# debug_backplane.net
KiCad netlist of a schematic drawn in EAGLE
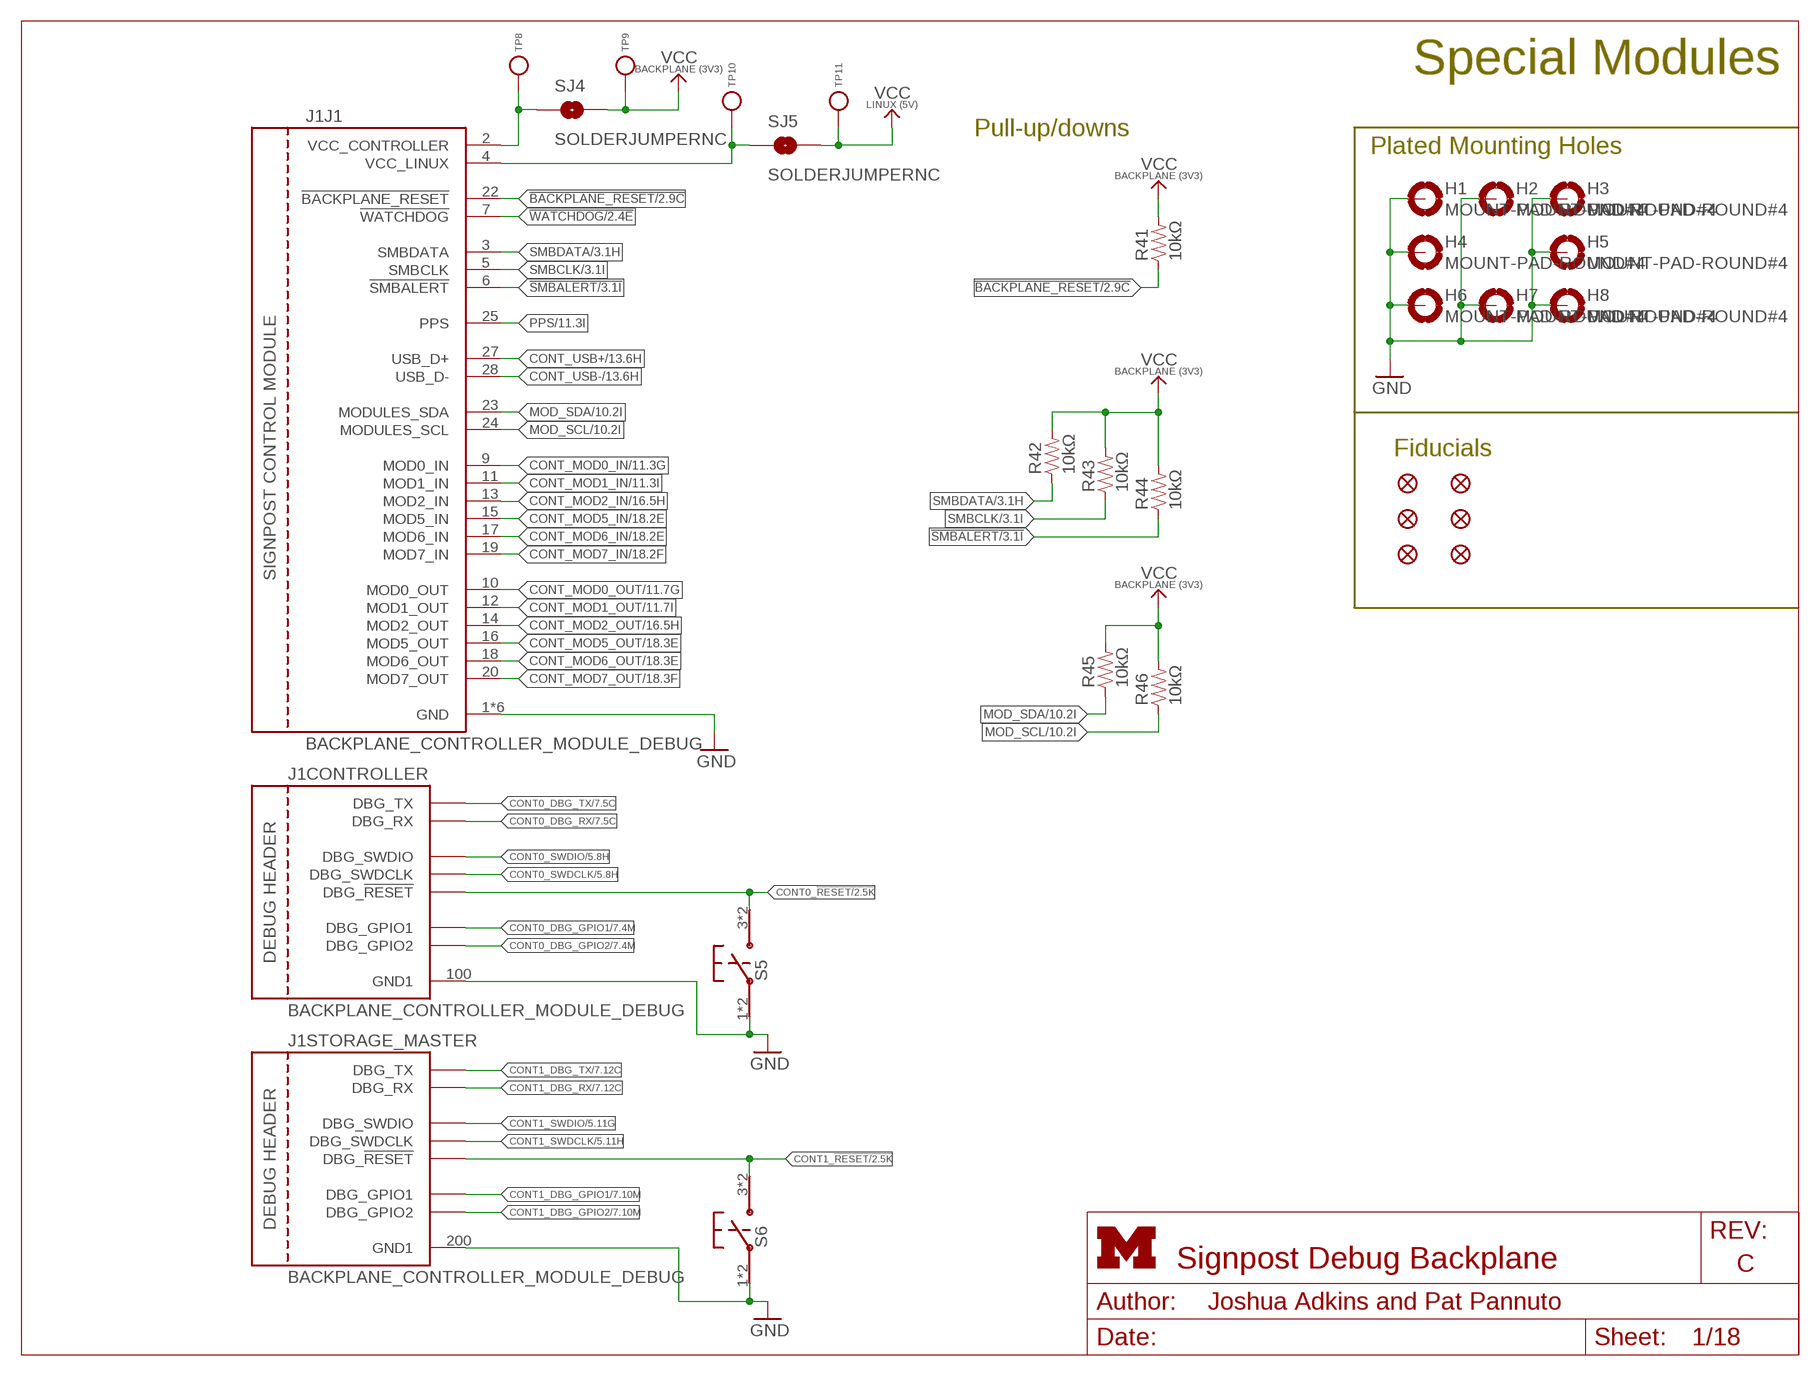
[diagram p0: schematic, sheet 1]
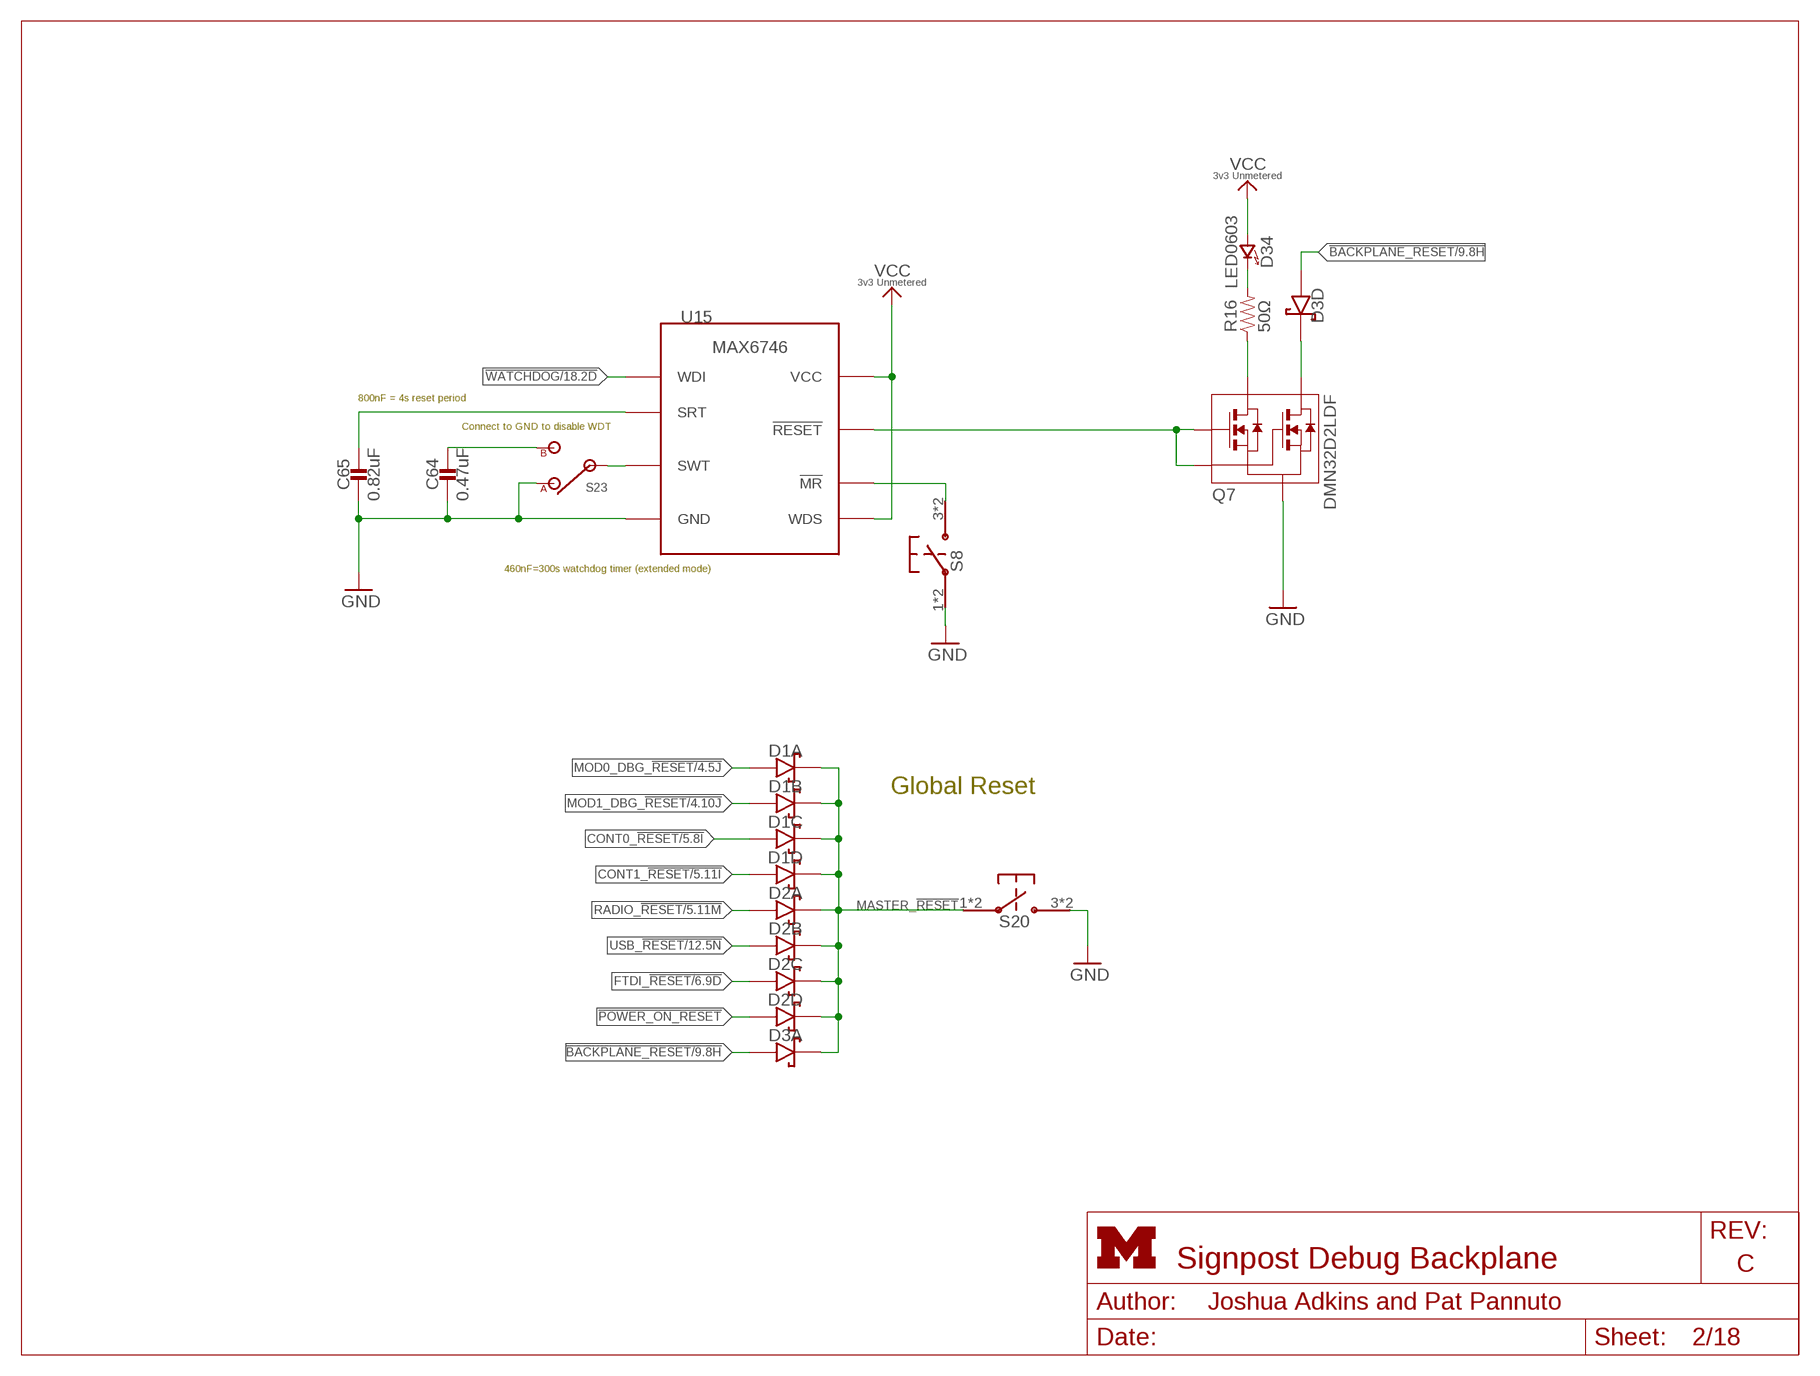
[diagram p1: schematic, sheet 2]
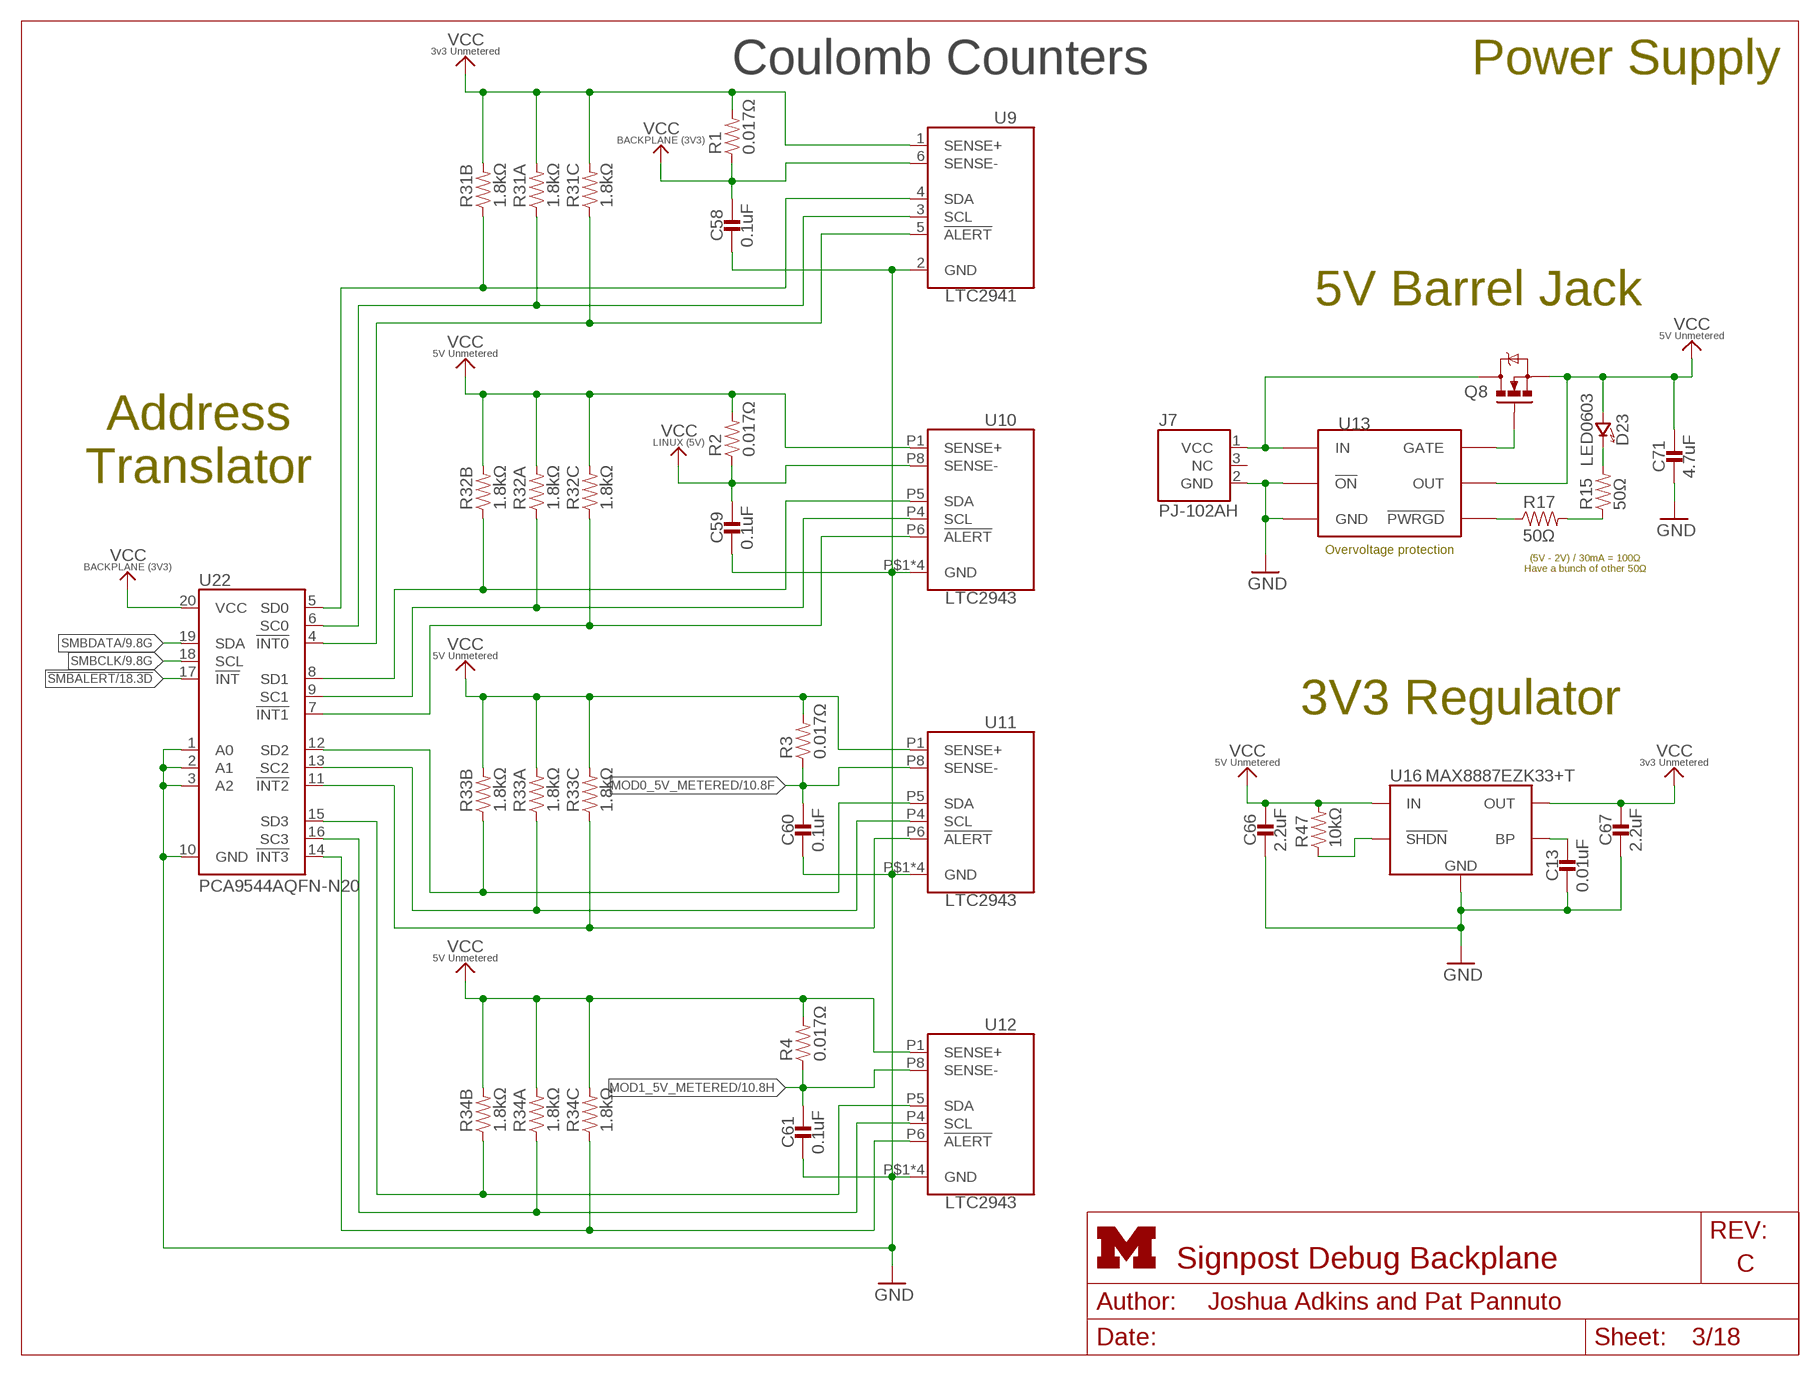
[diagram p2: schematic, sheet 3]
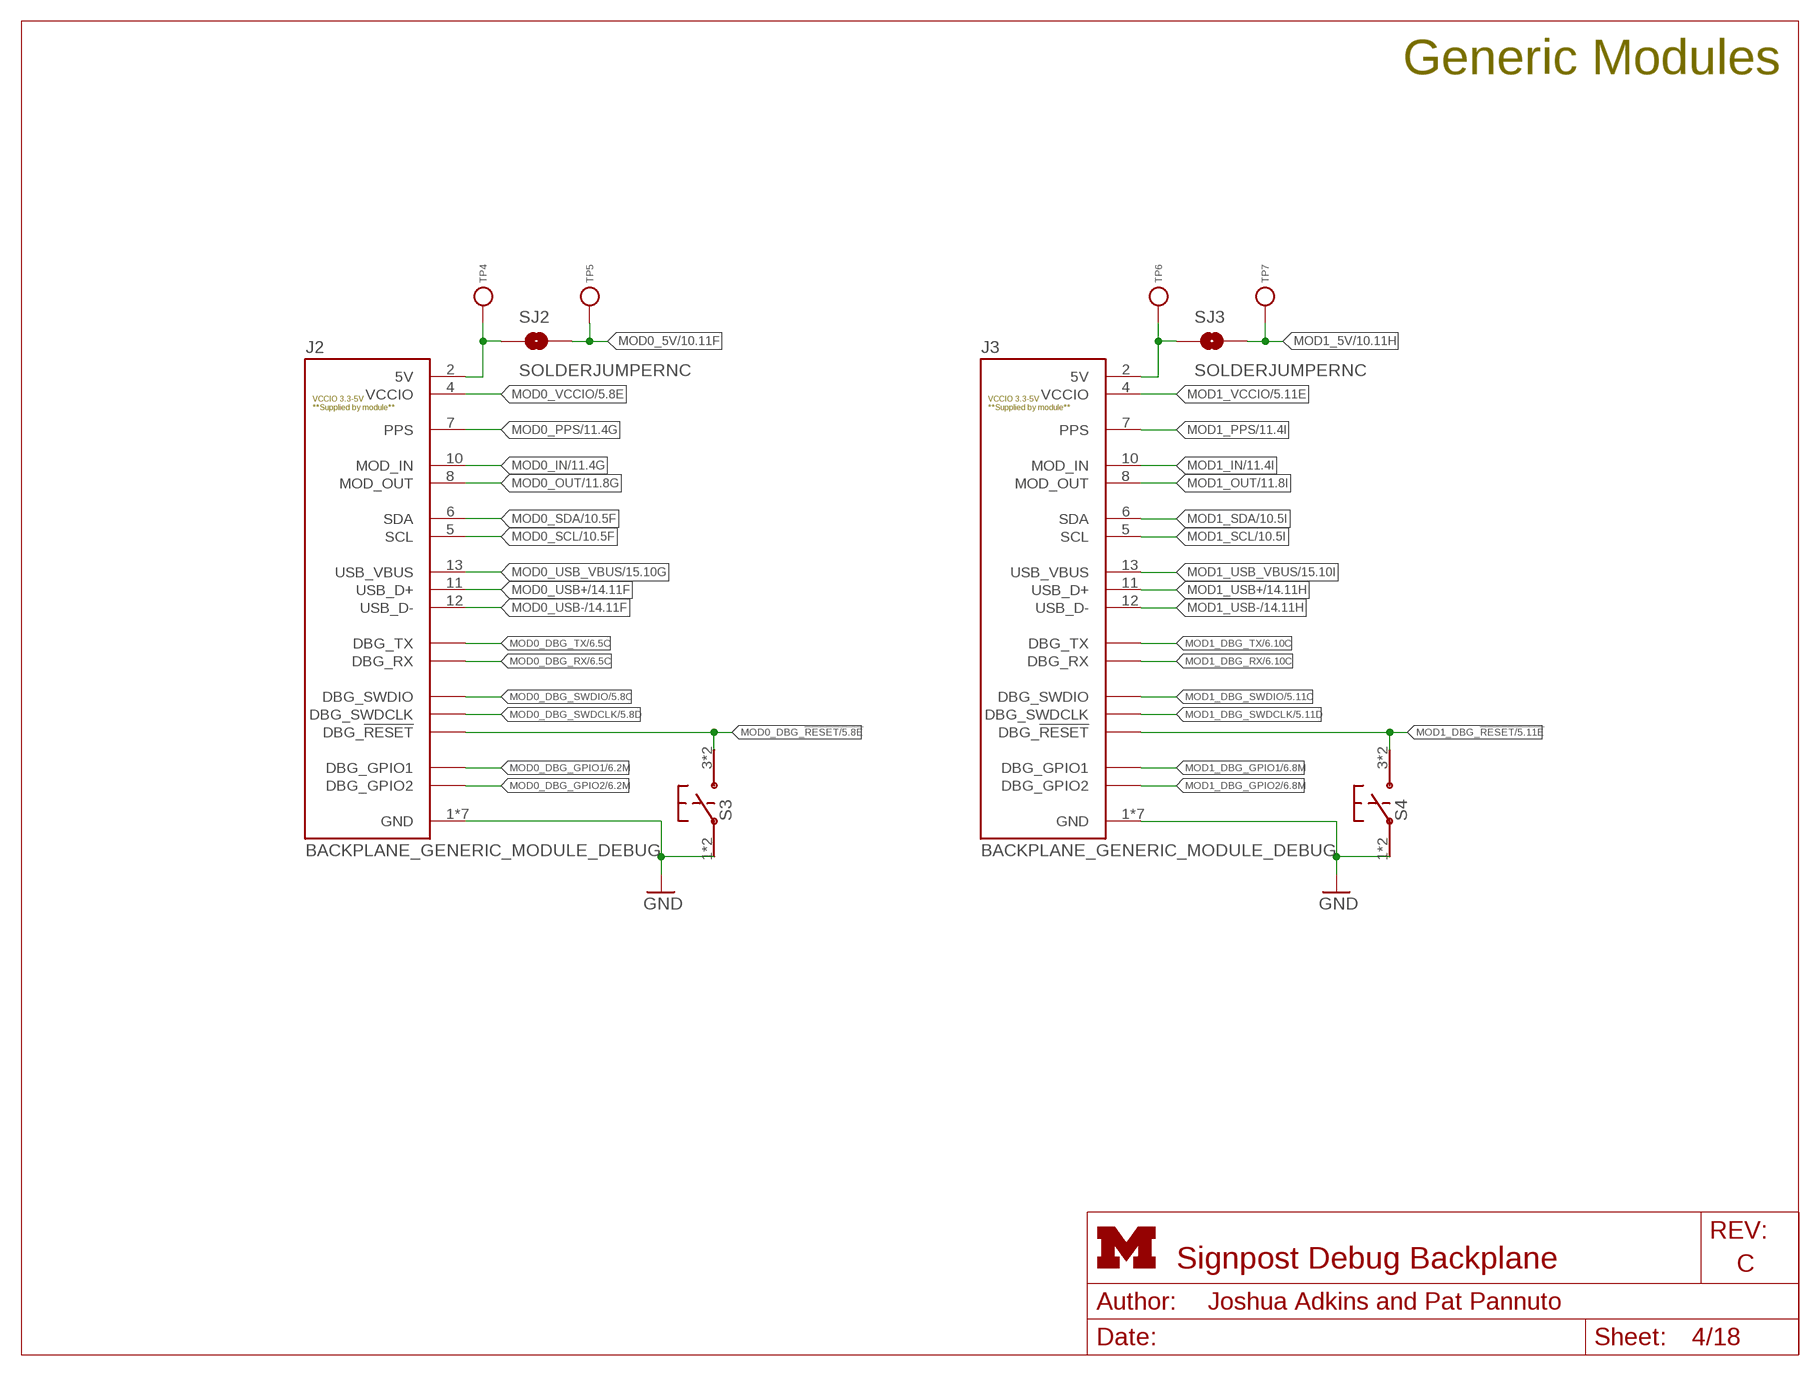
[diagram p3: schematic, sheet 4]
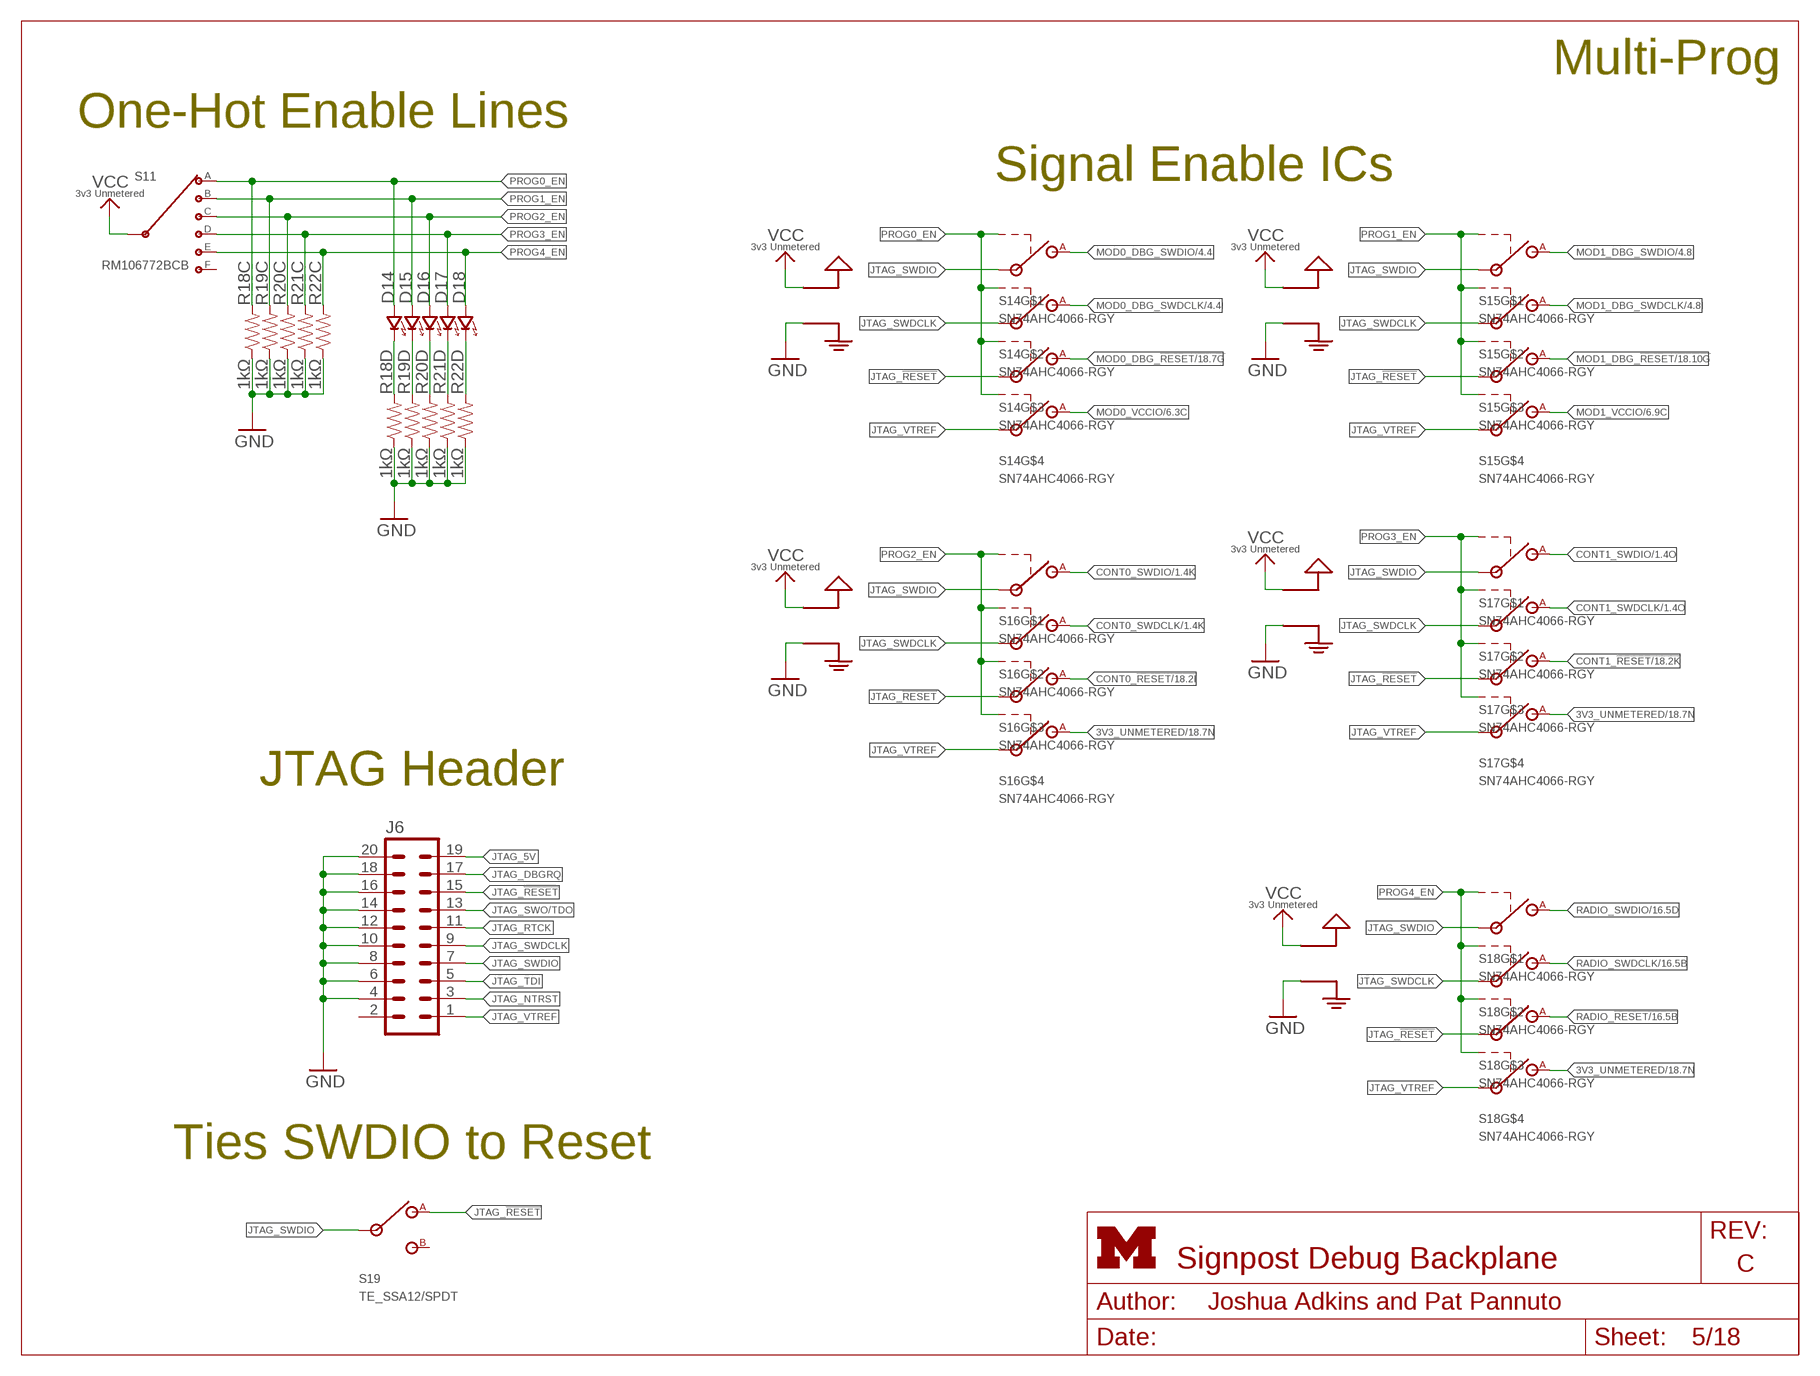
[diagram p4: schematic, sheet 5]
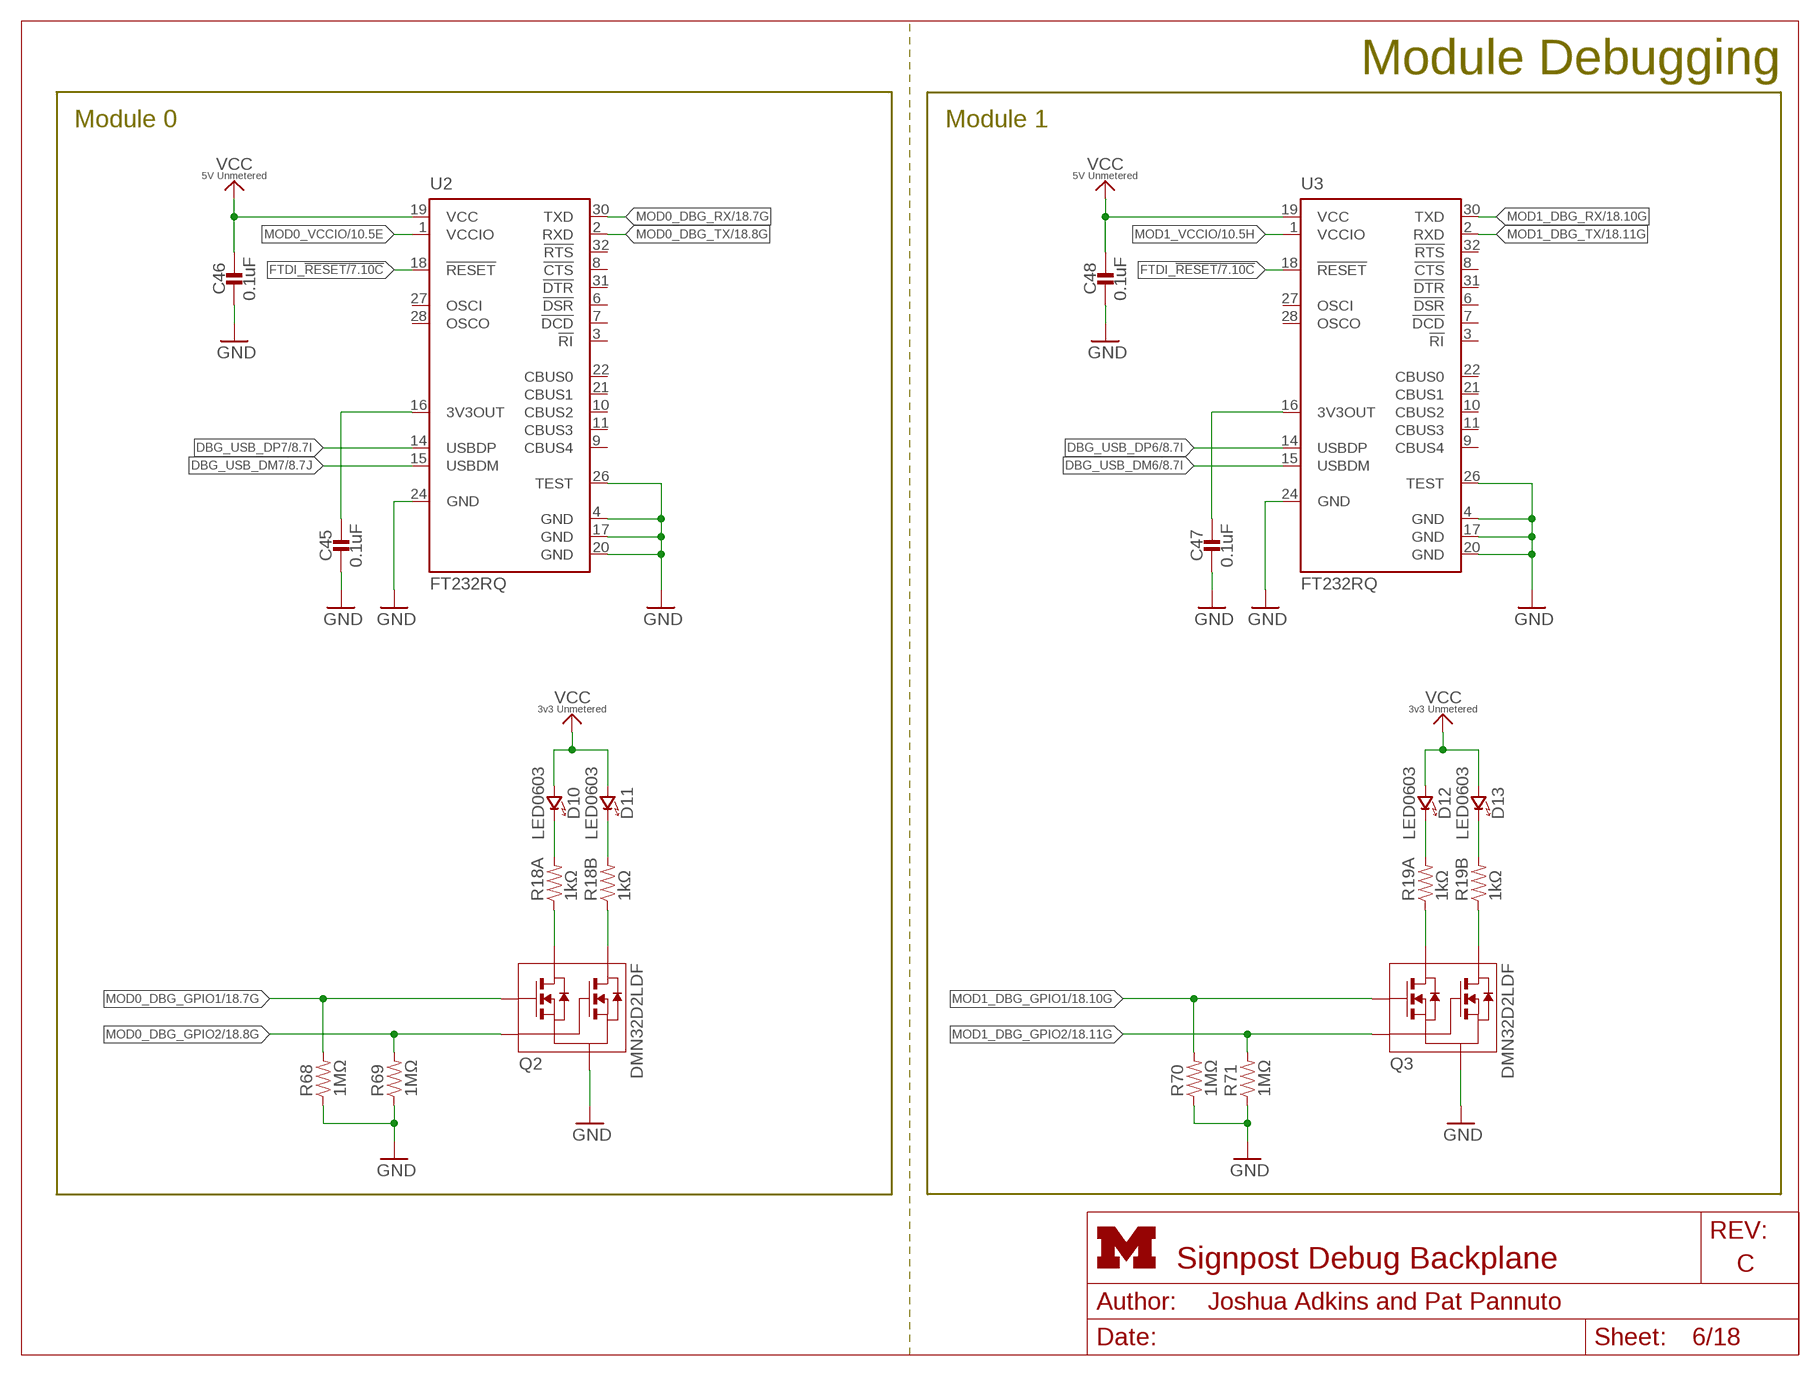
[diagram p5: schematic, sheet 6]
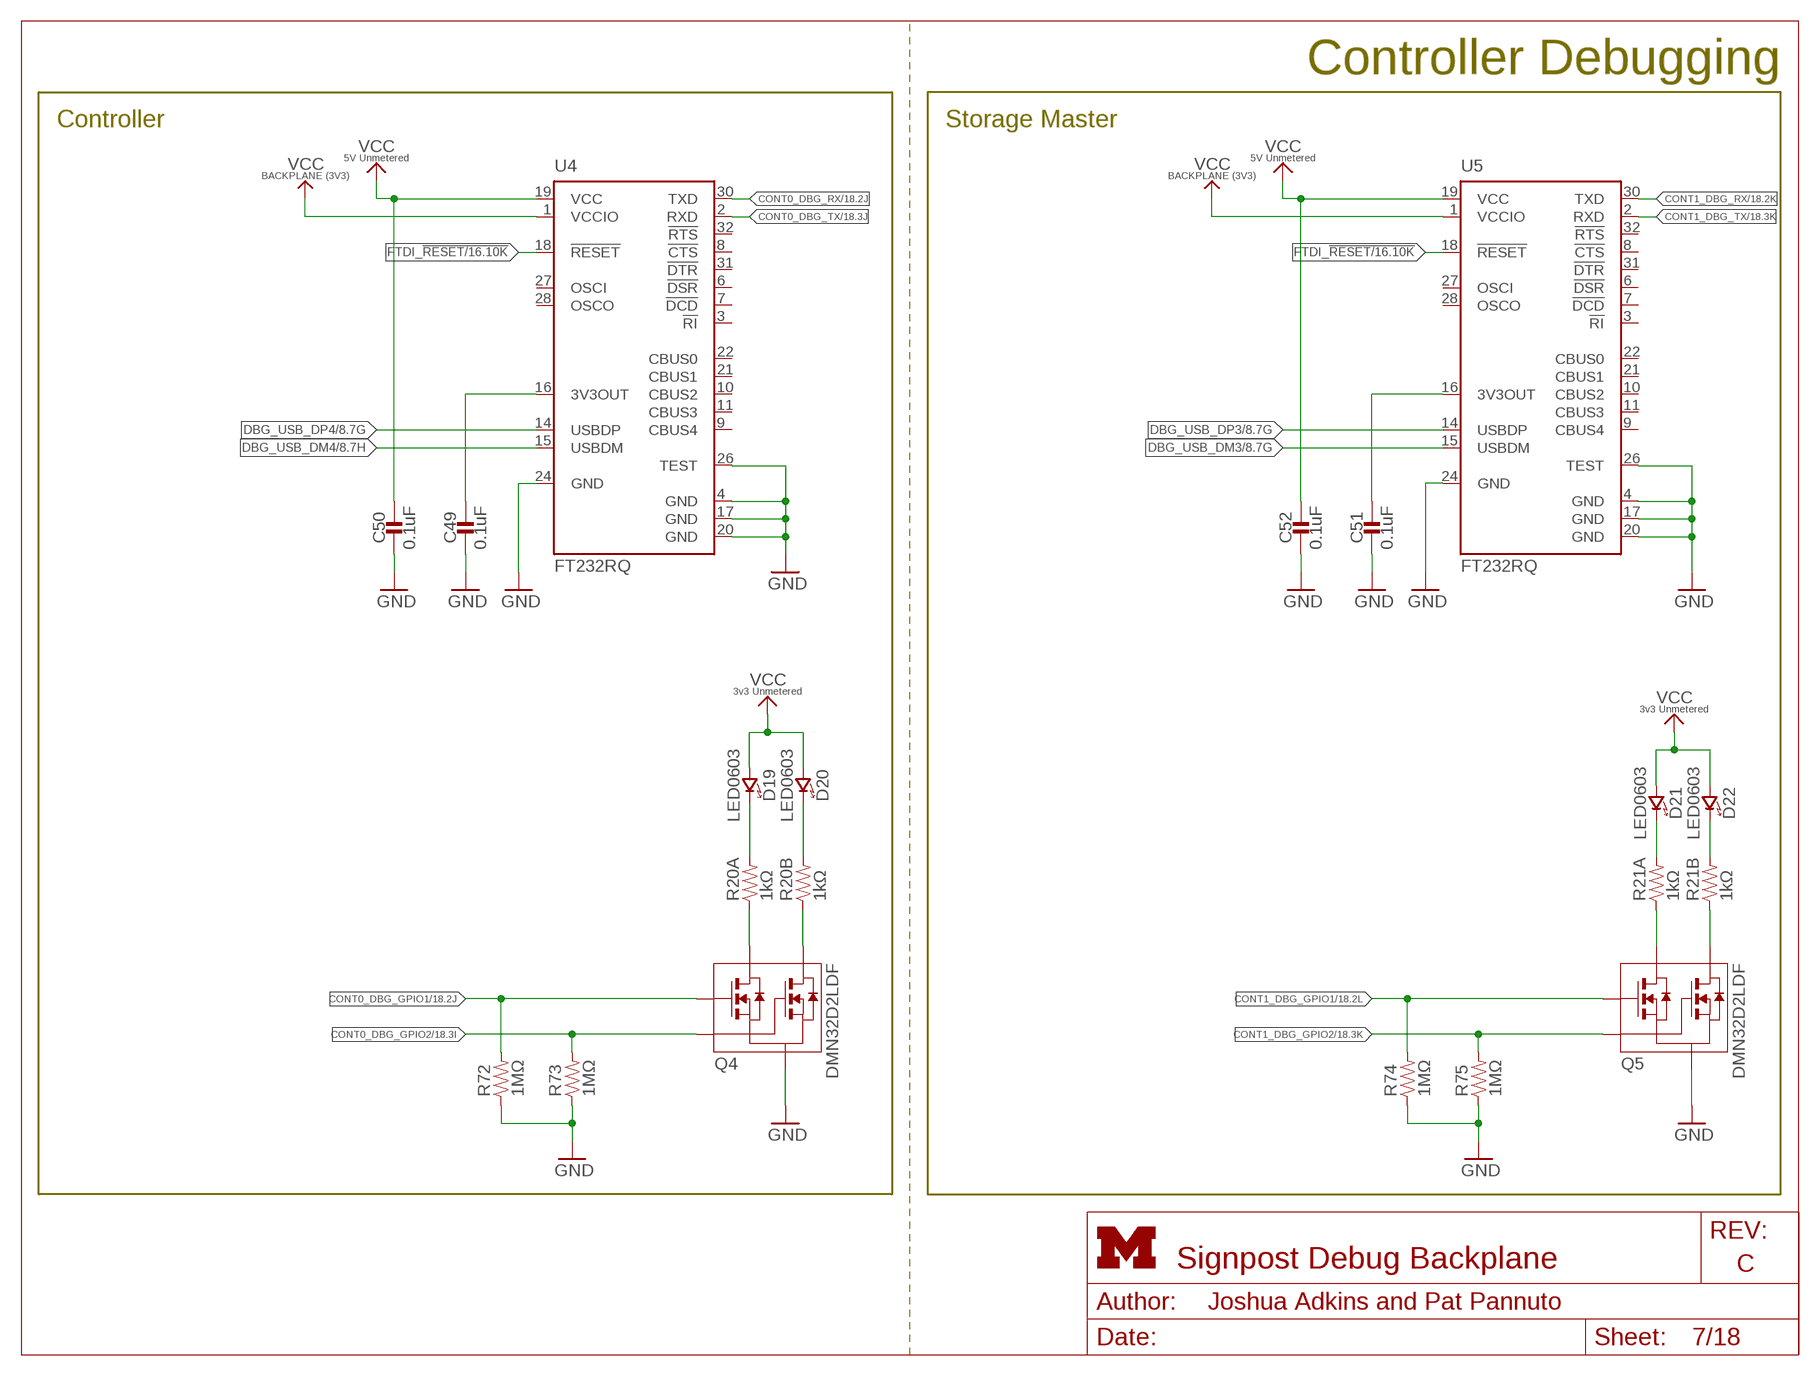
[diagram p6: schematic, sheet 7]
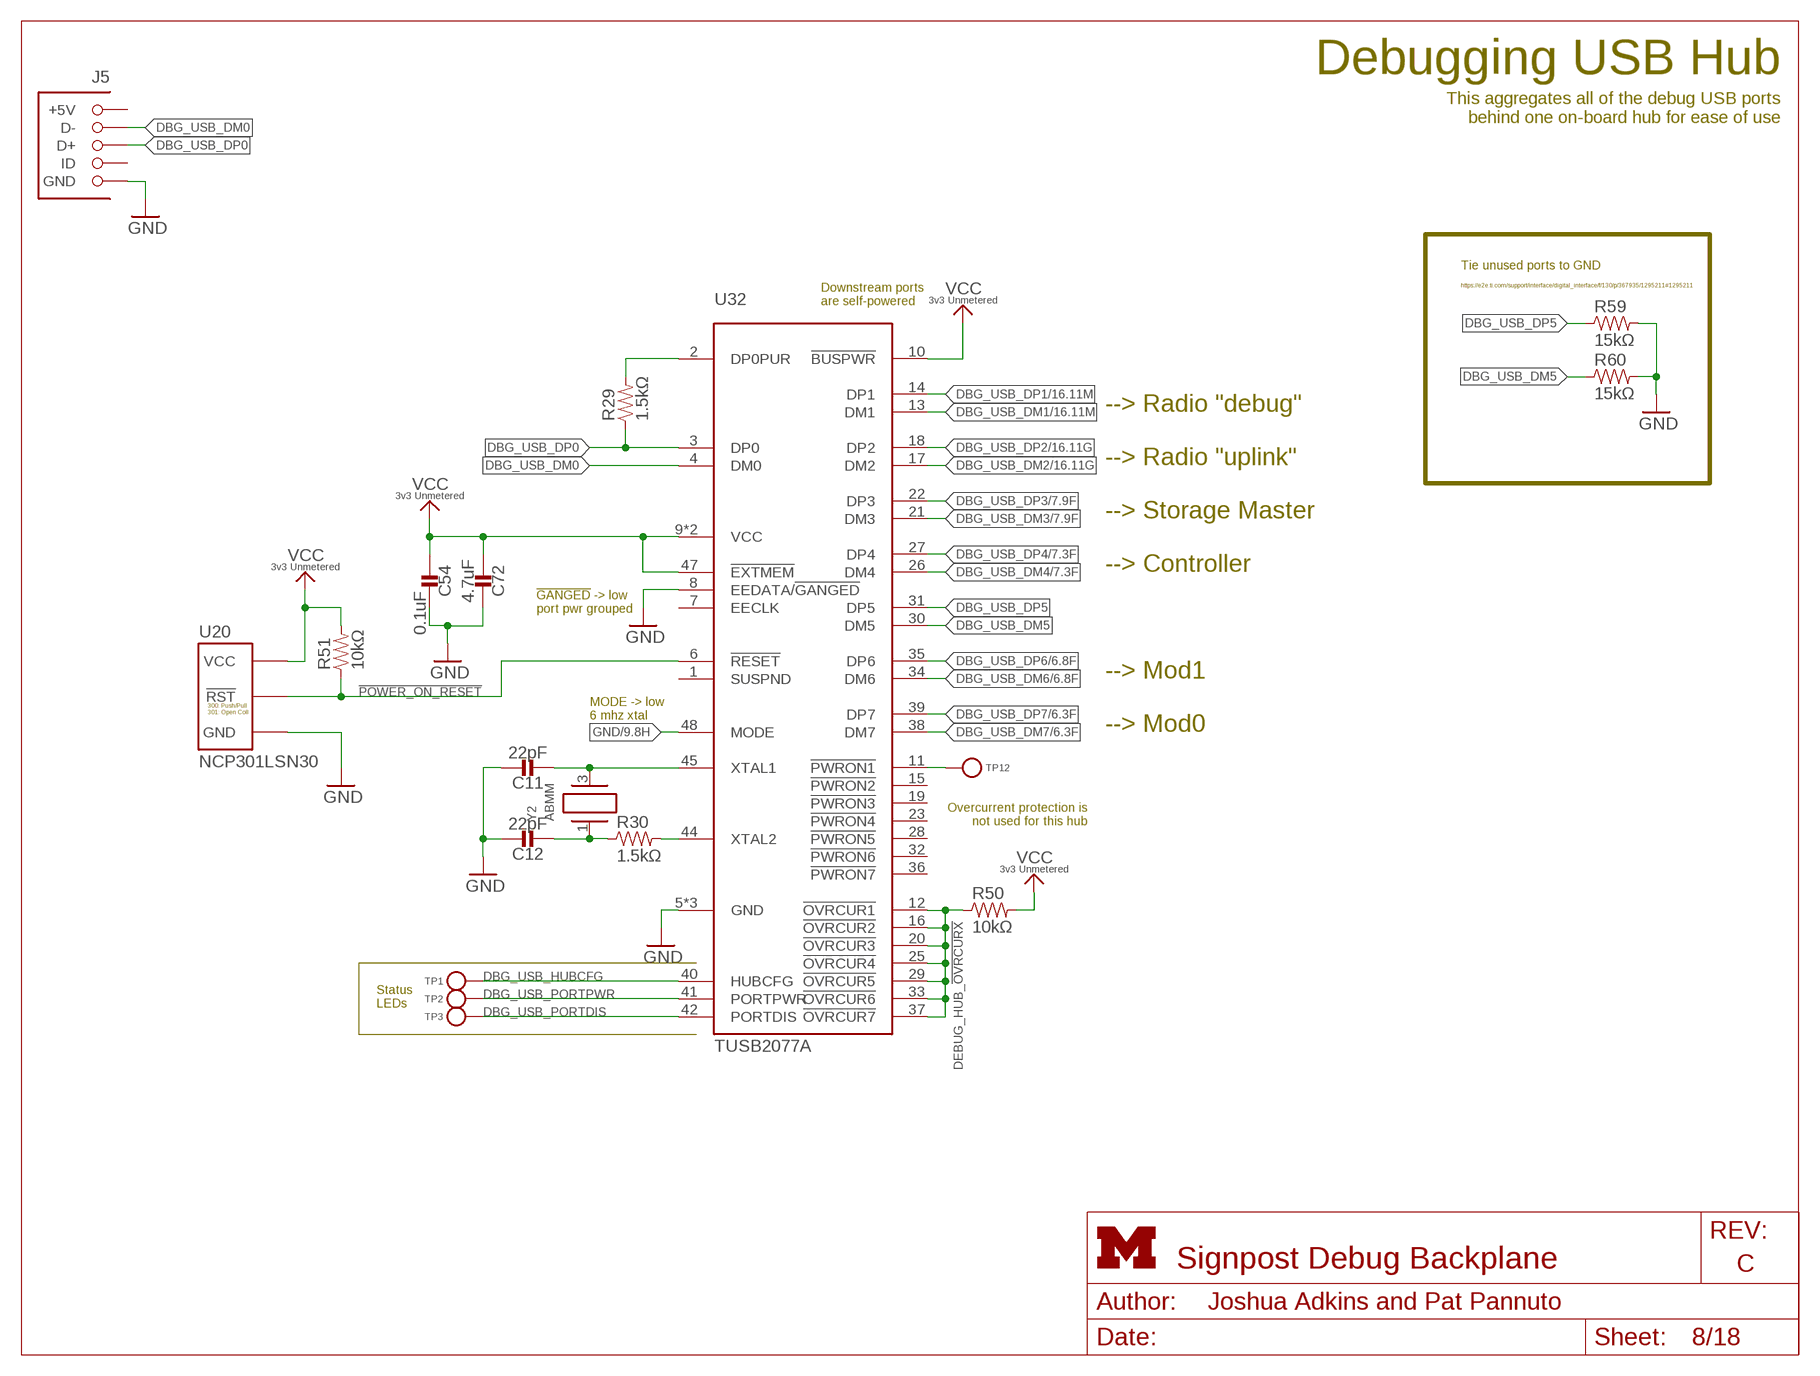
[diagram p7: schematic, sheet 8]
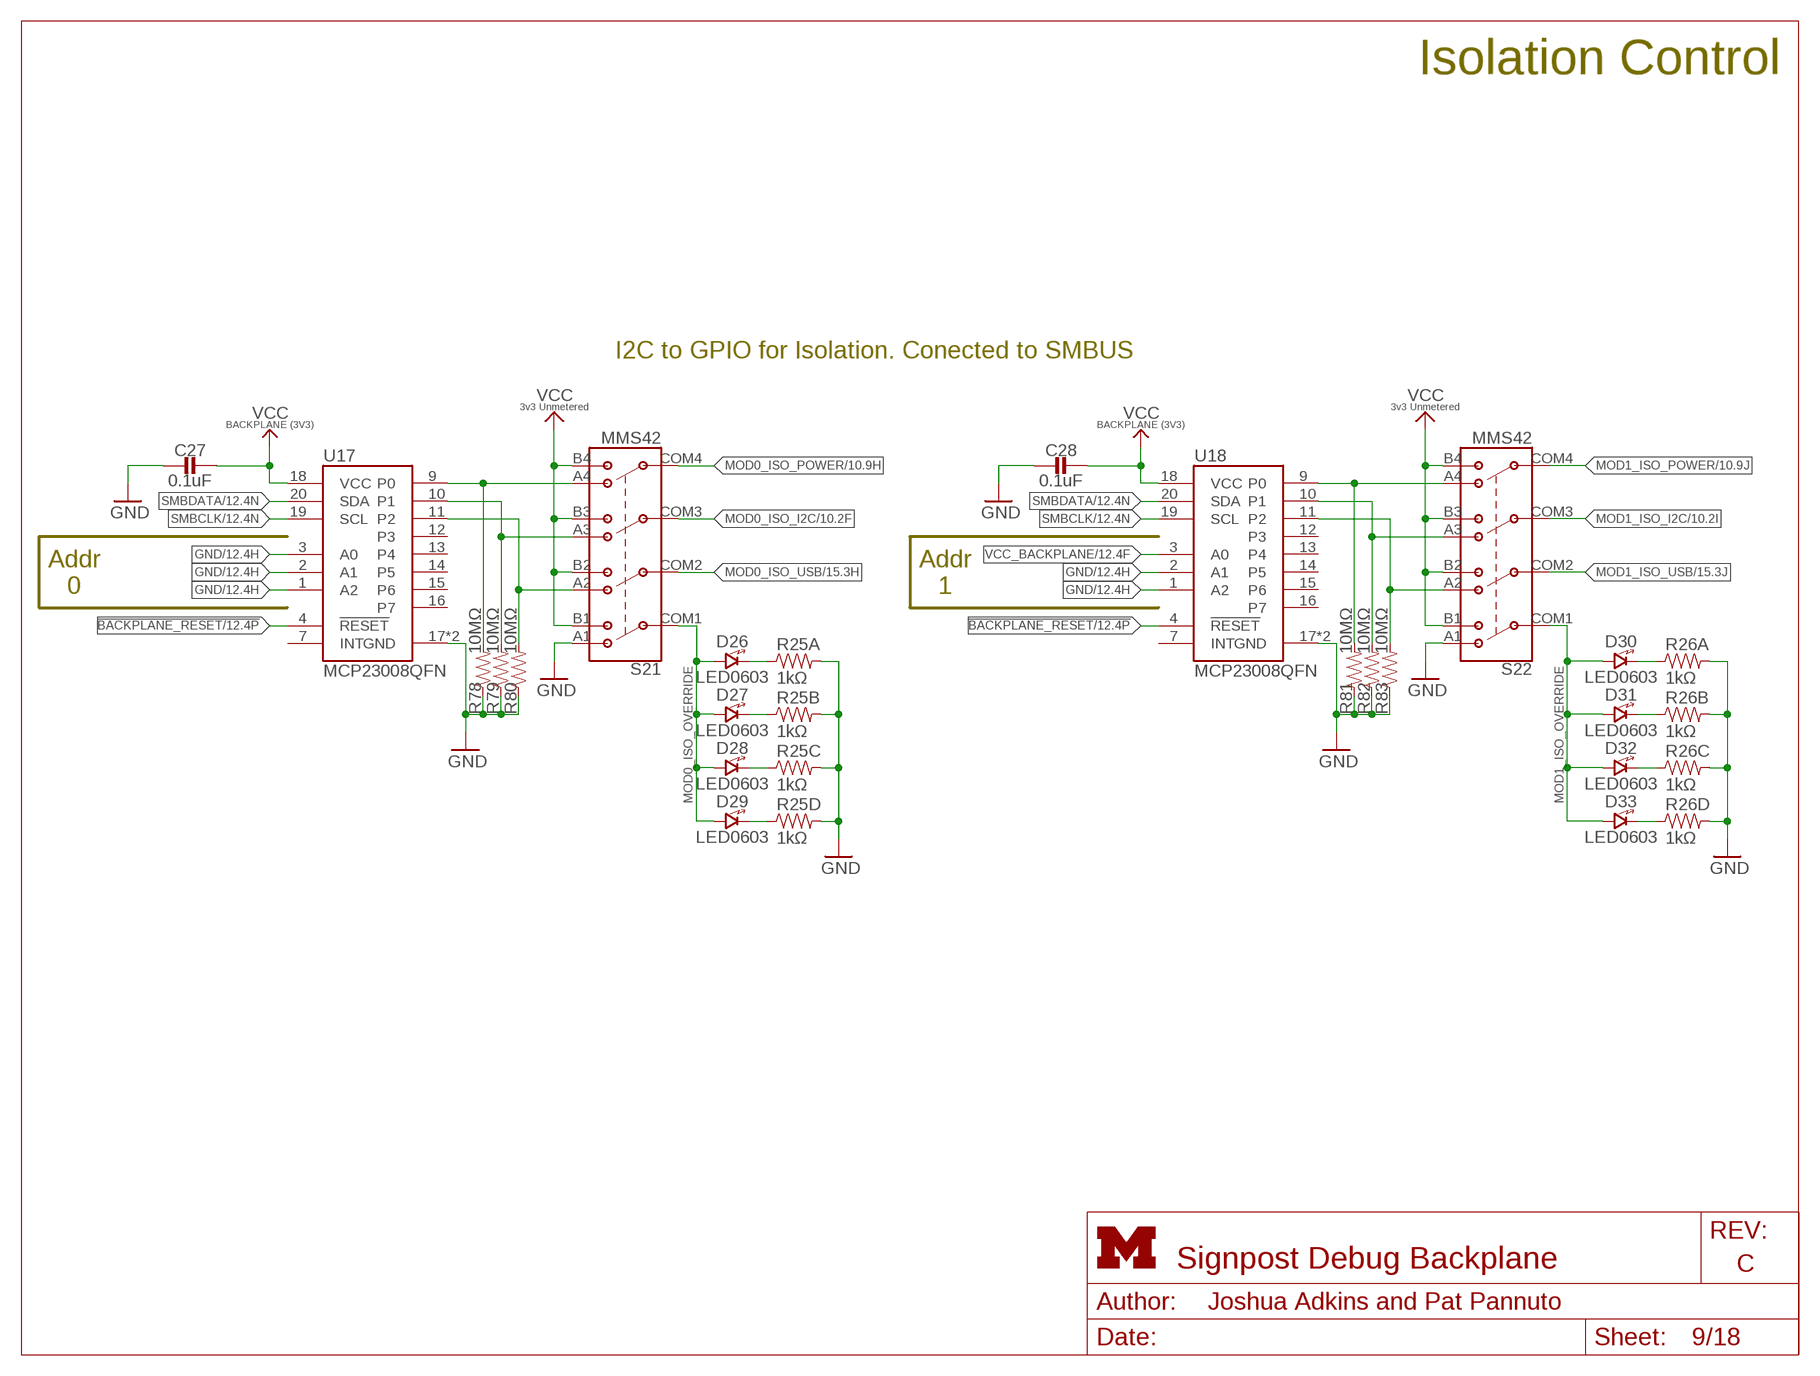
[diagram p8: schematic, sheet 9]
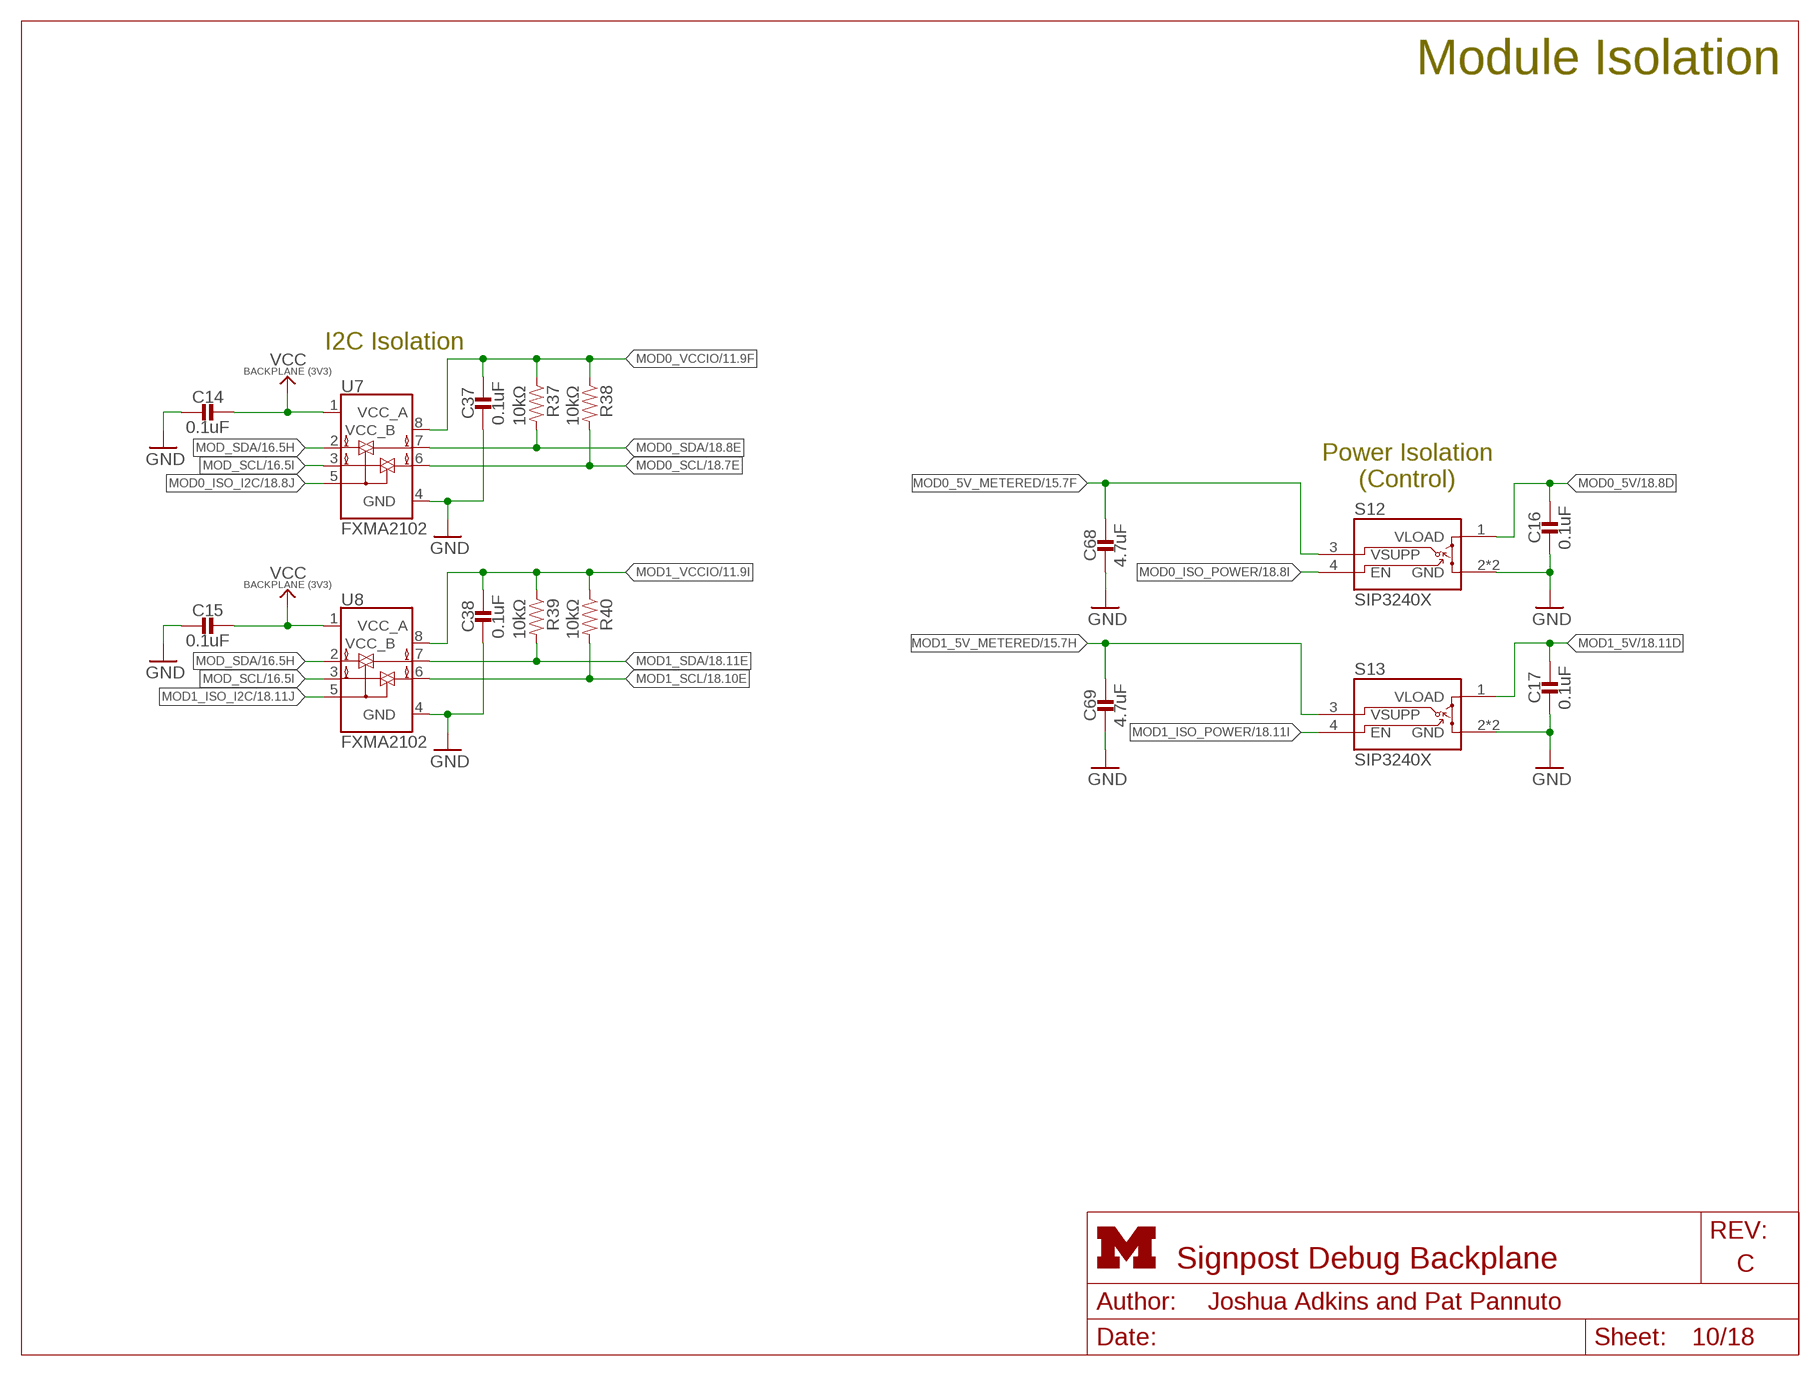
[diagram p9: schematic, sheet 10]
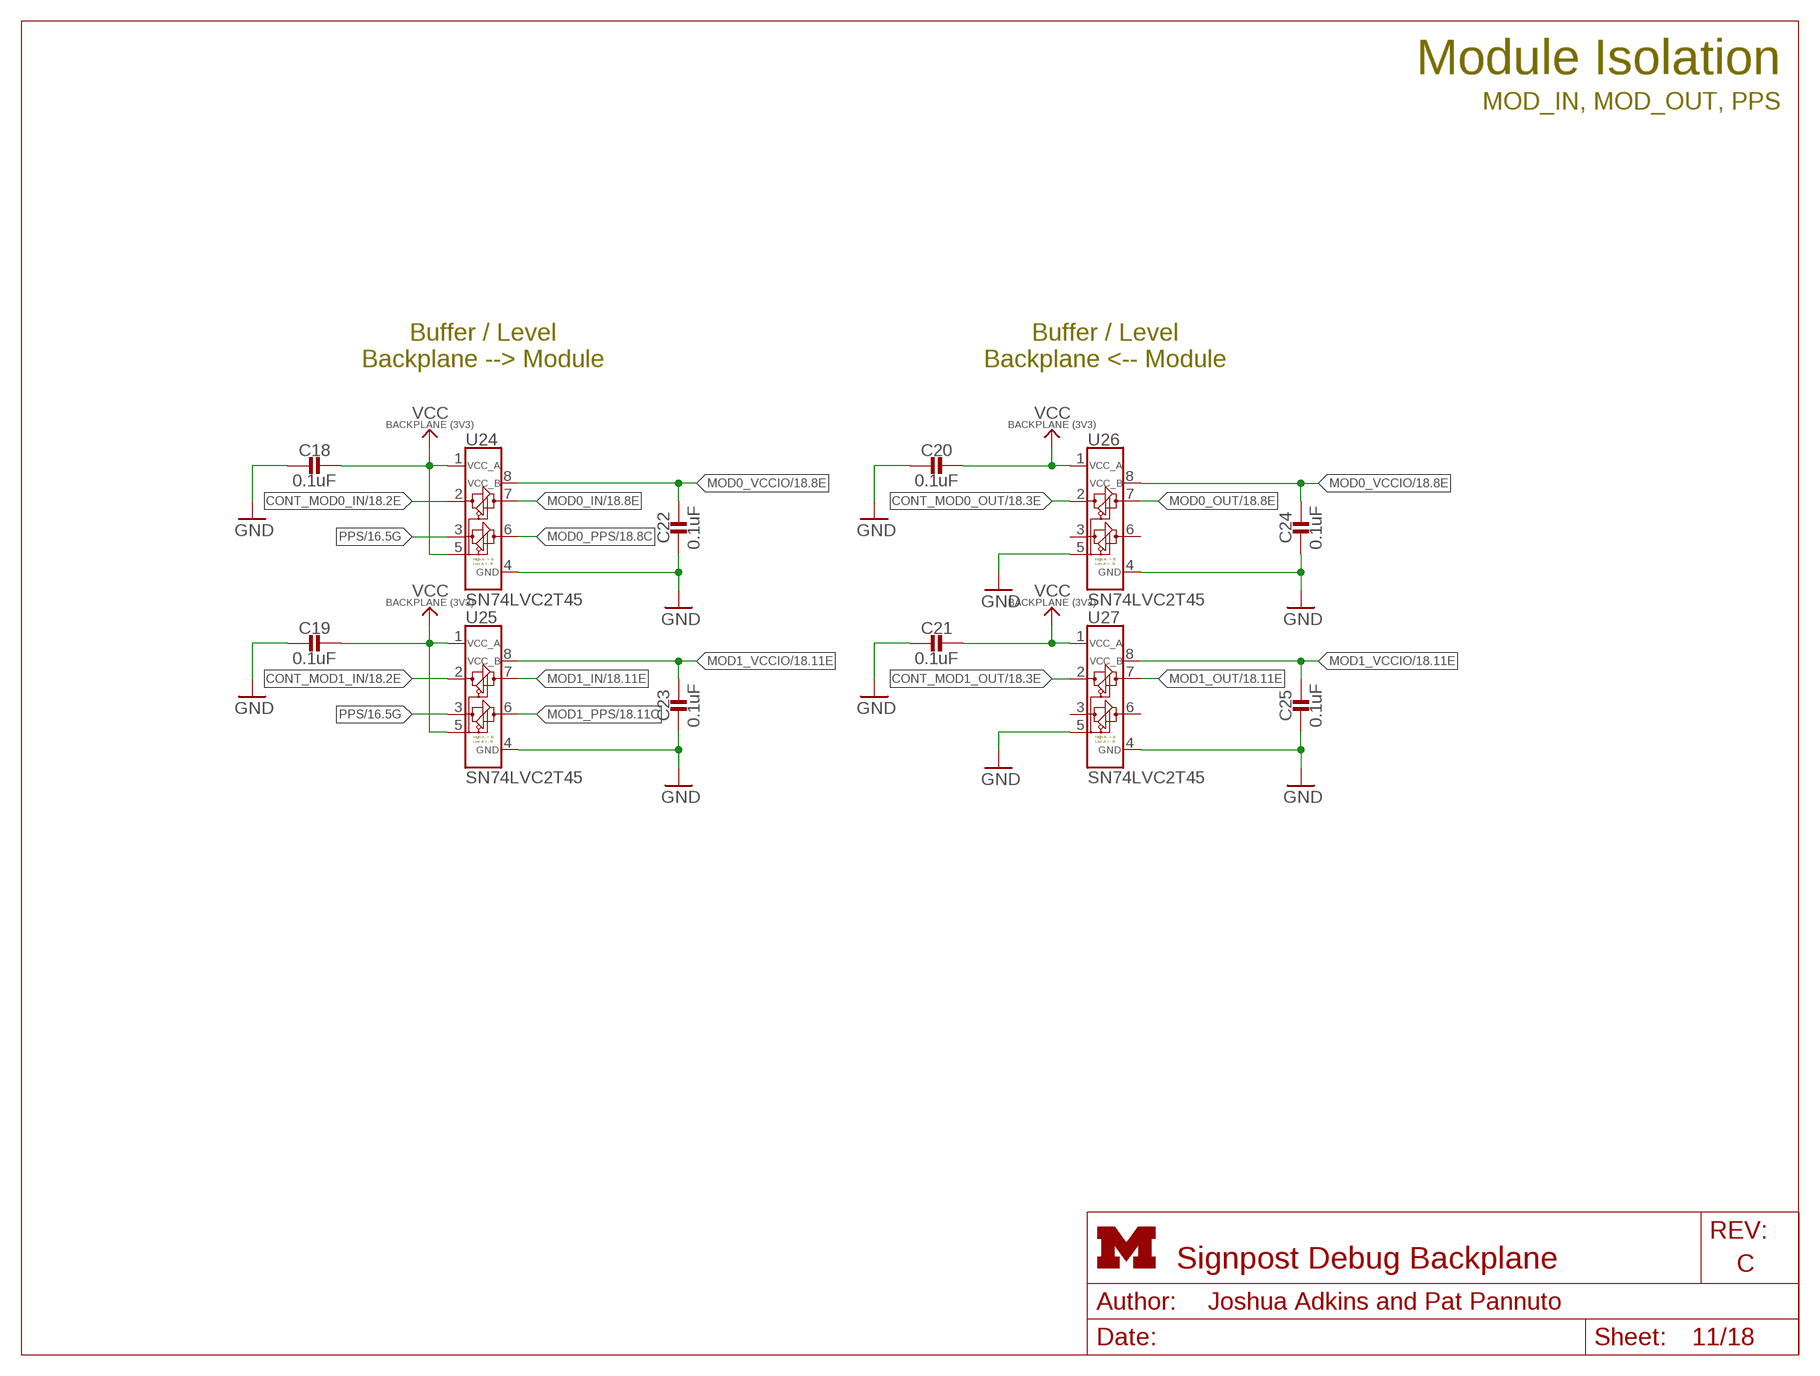
[diagram p10: schematic, sheet 11]
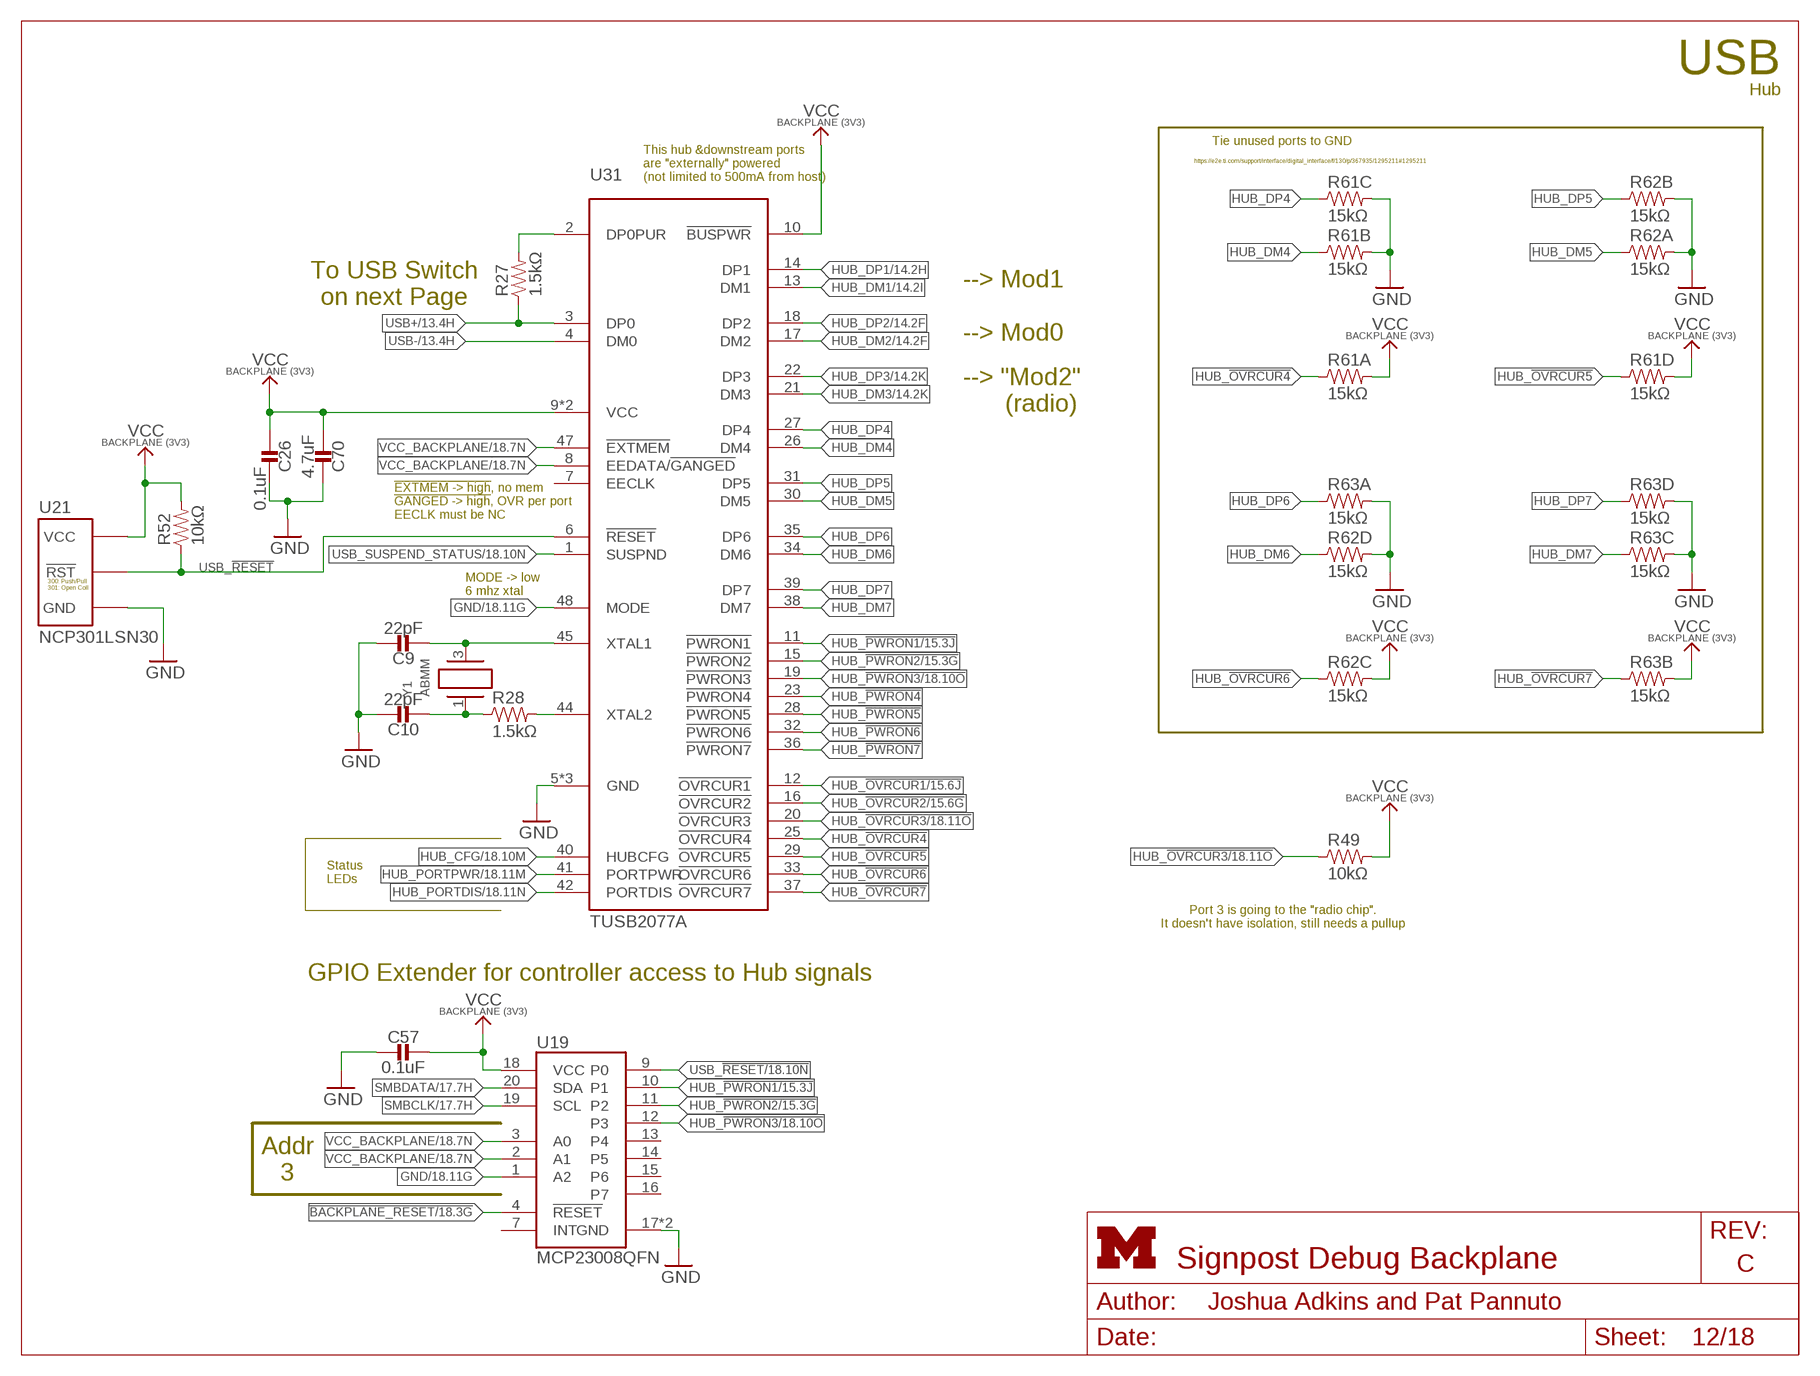
[diagram p11: schematic, sheet 12]
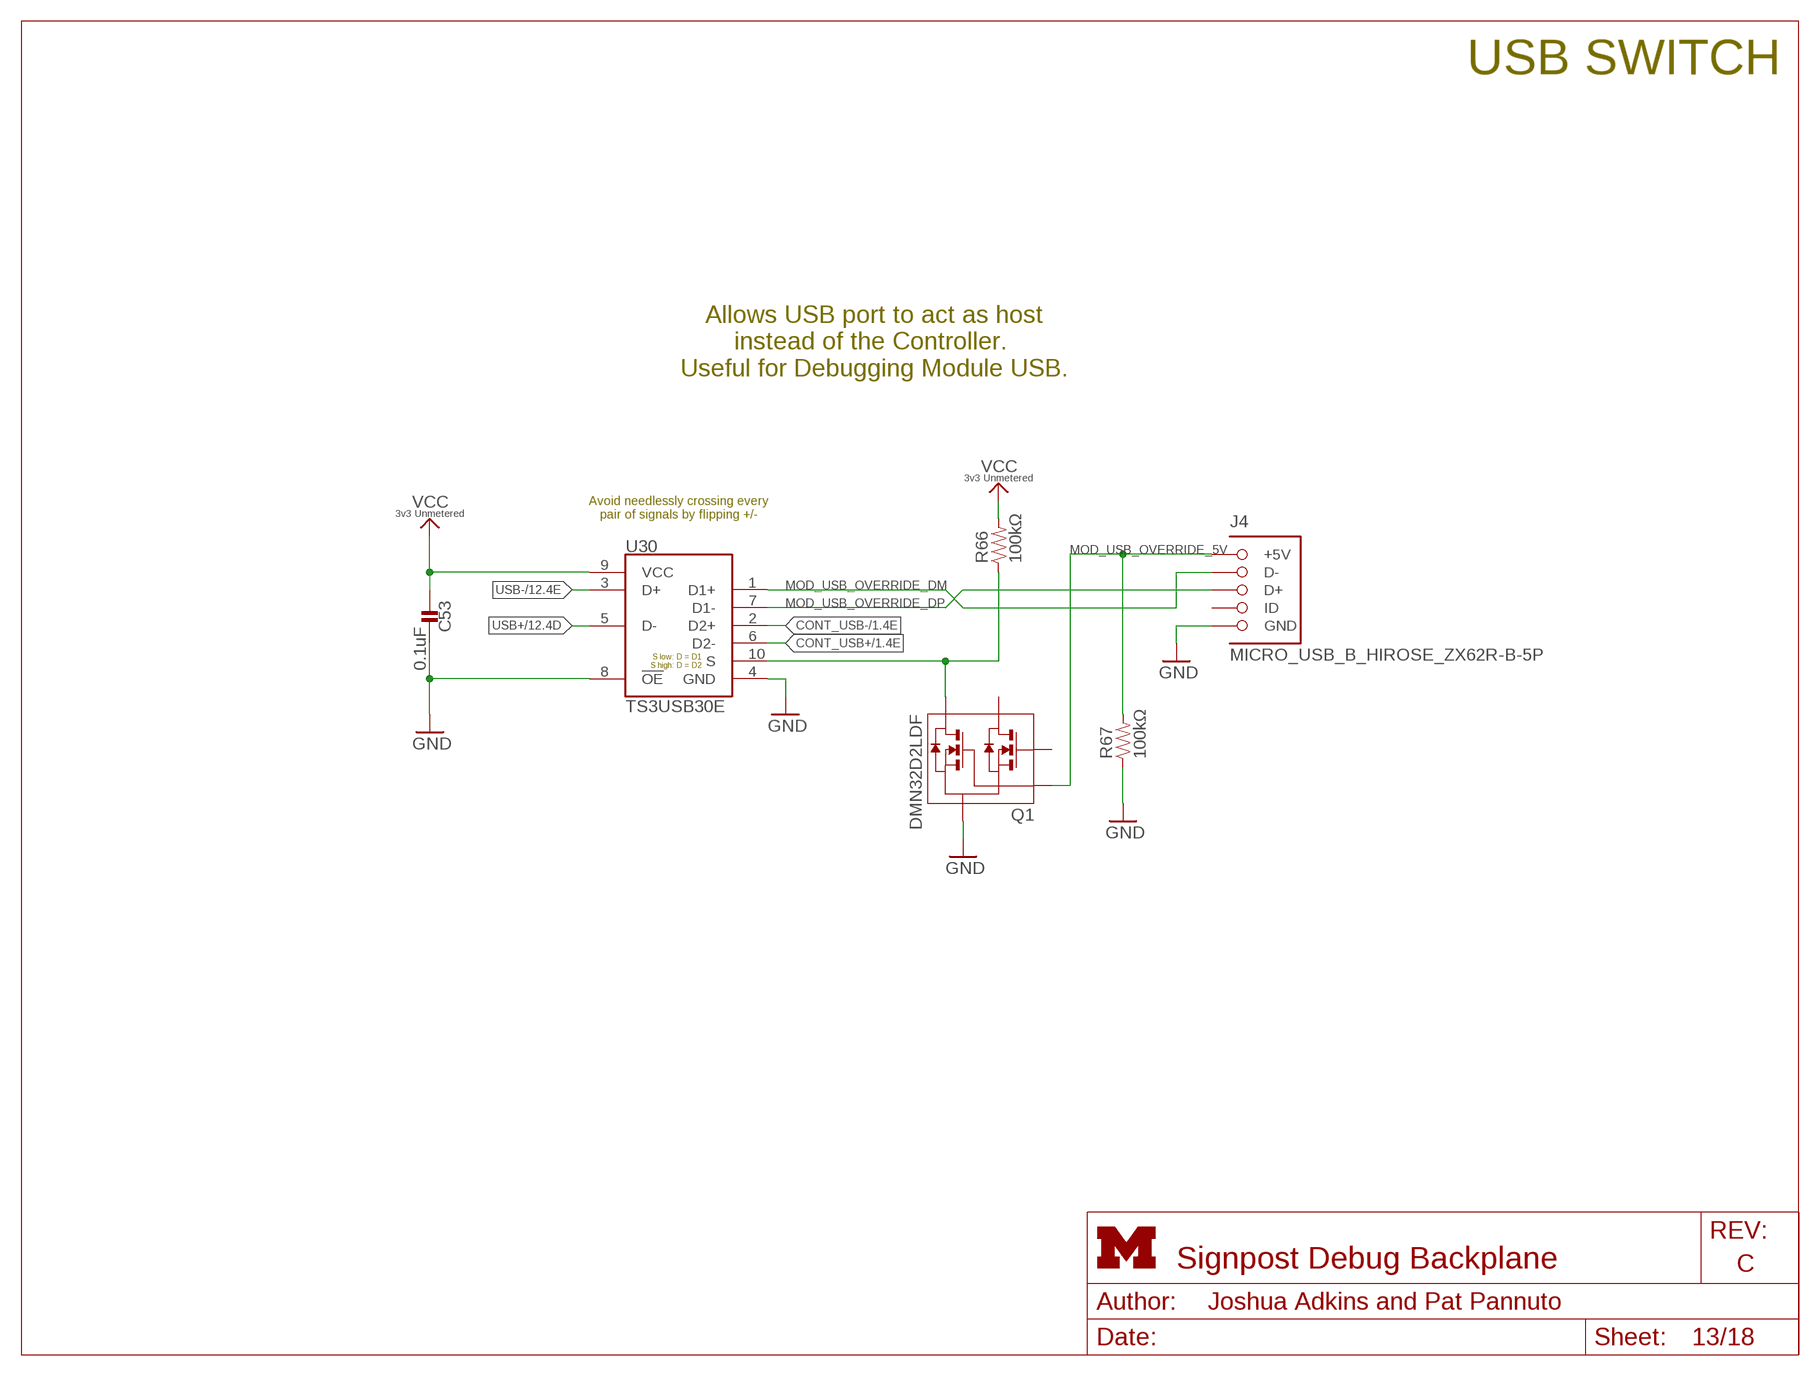
[diagram p12: schematic, sheet 13]
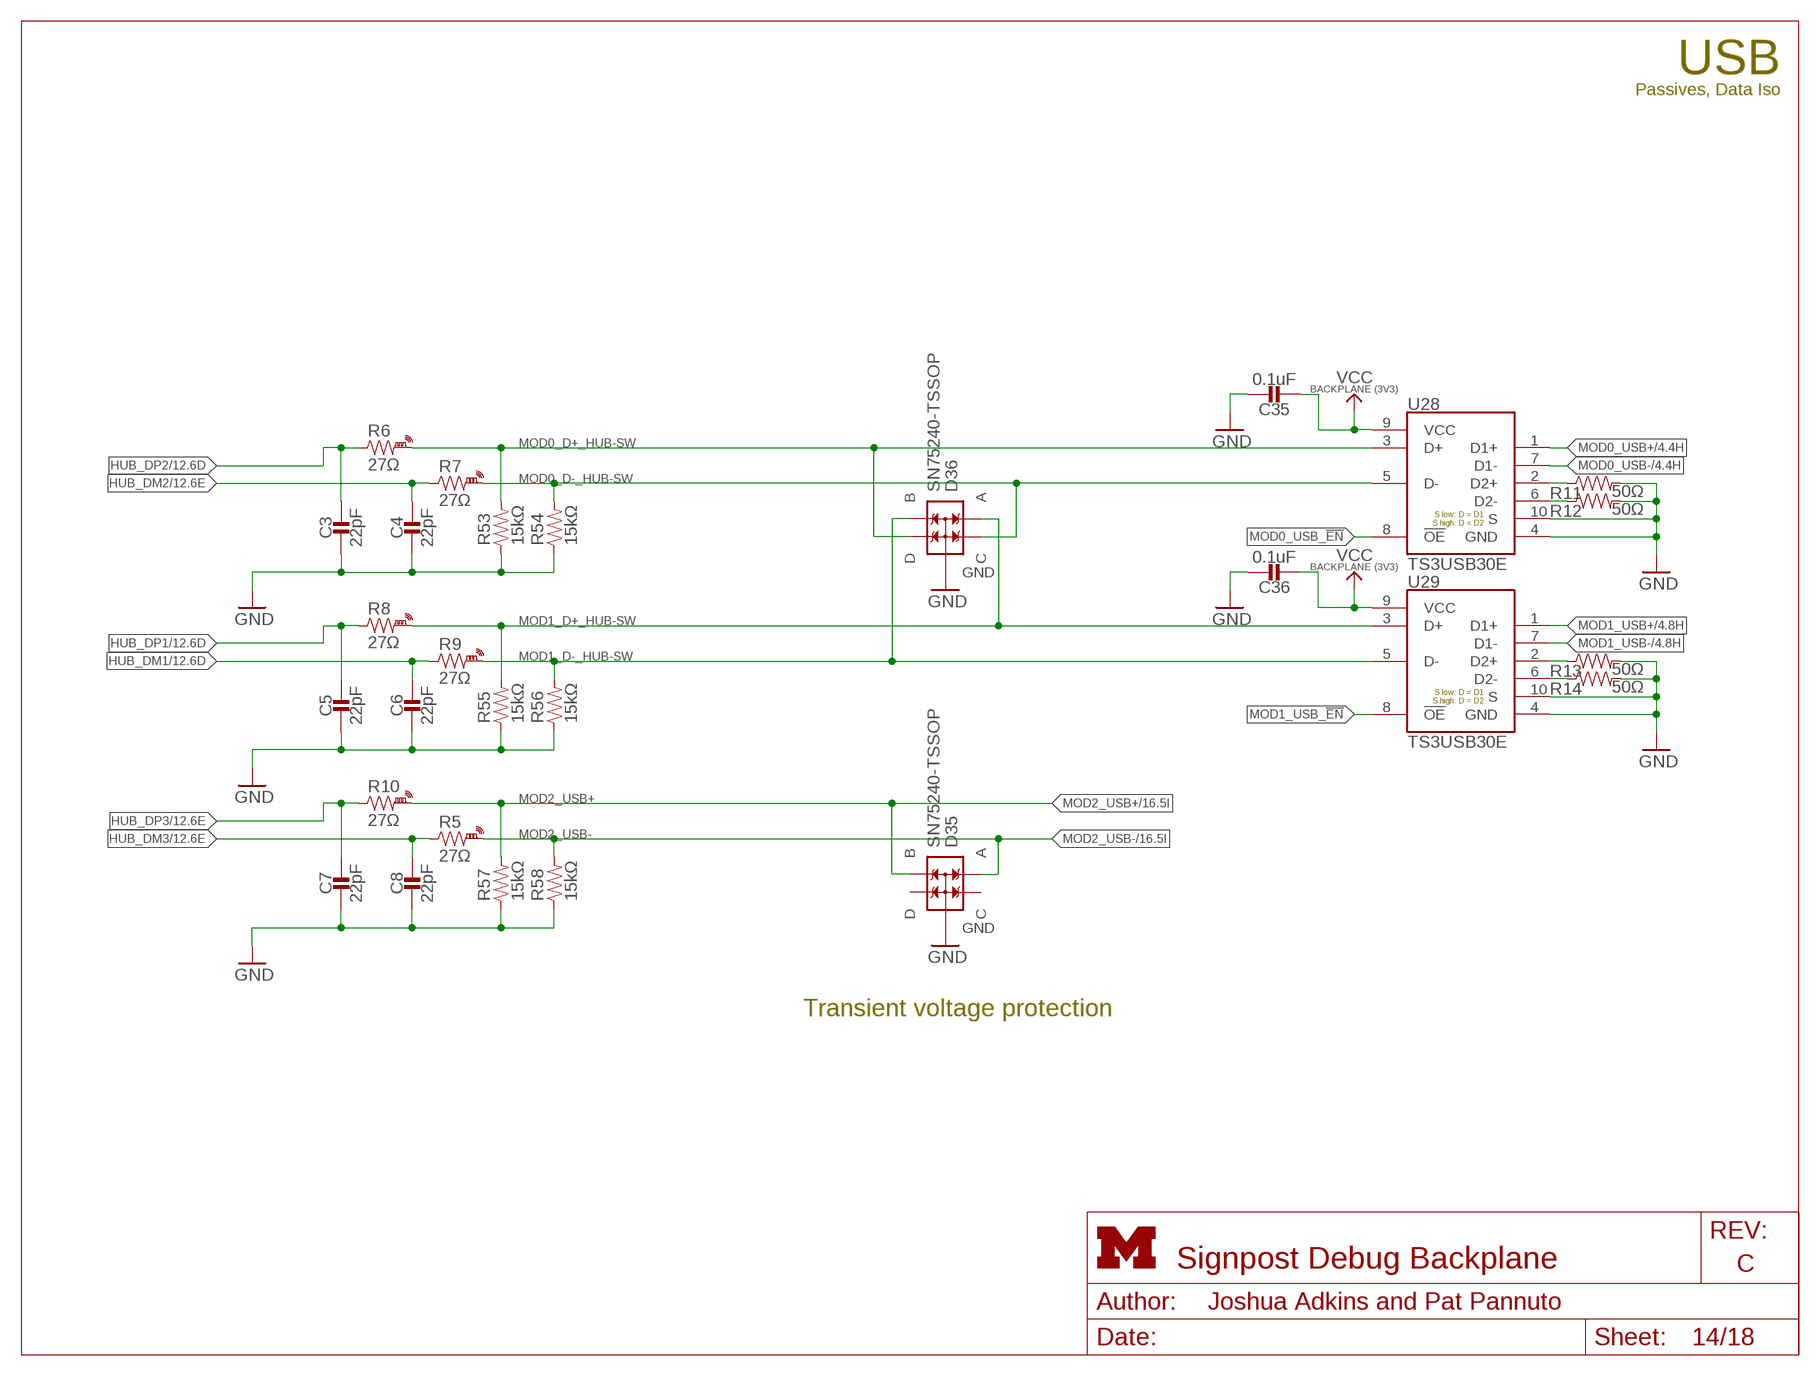
[diagram p13: schematic, sheet 14]
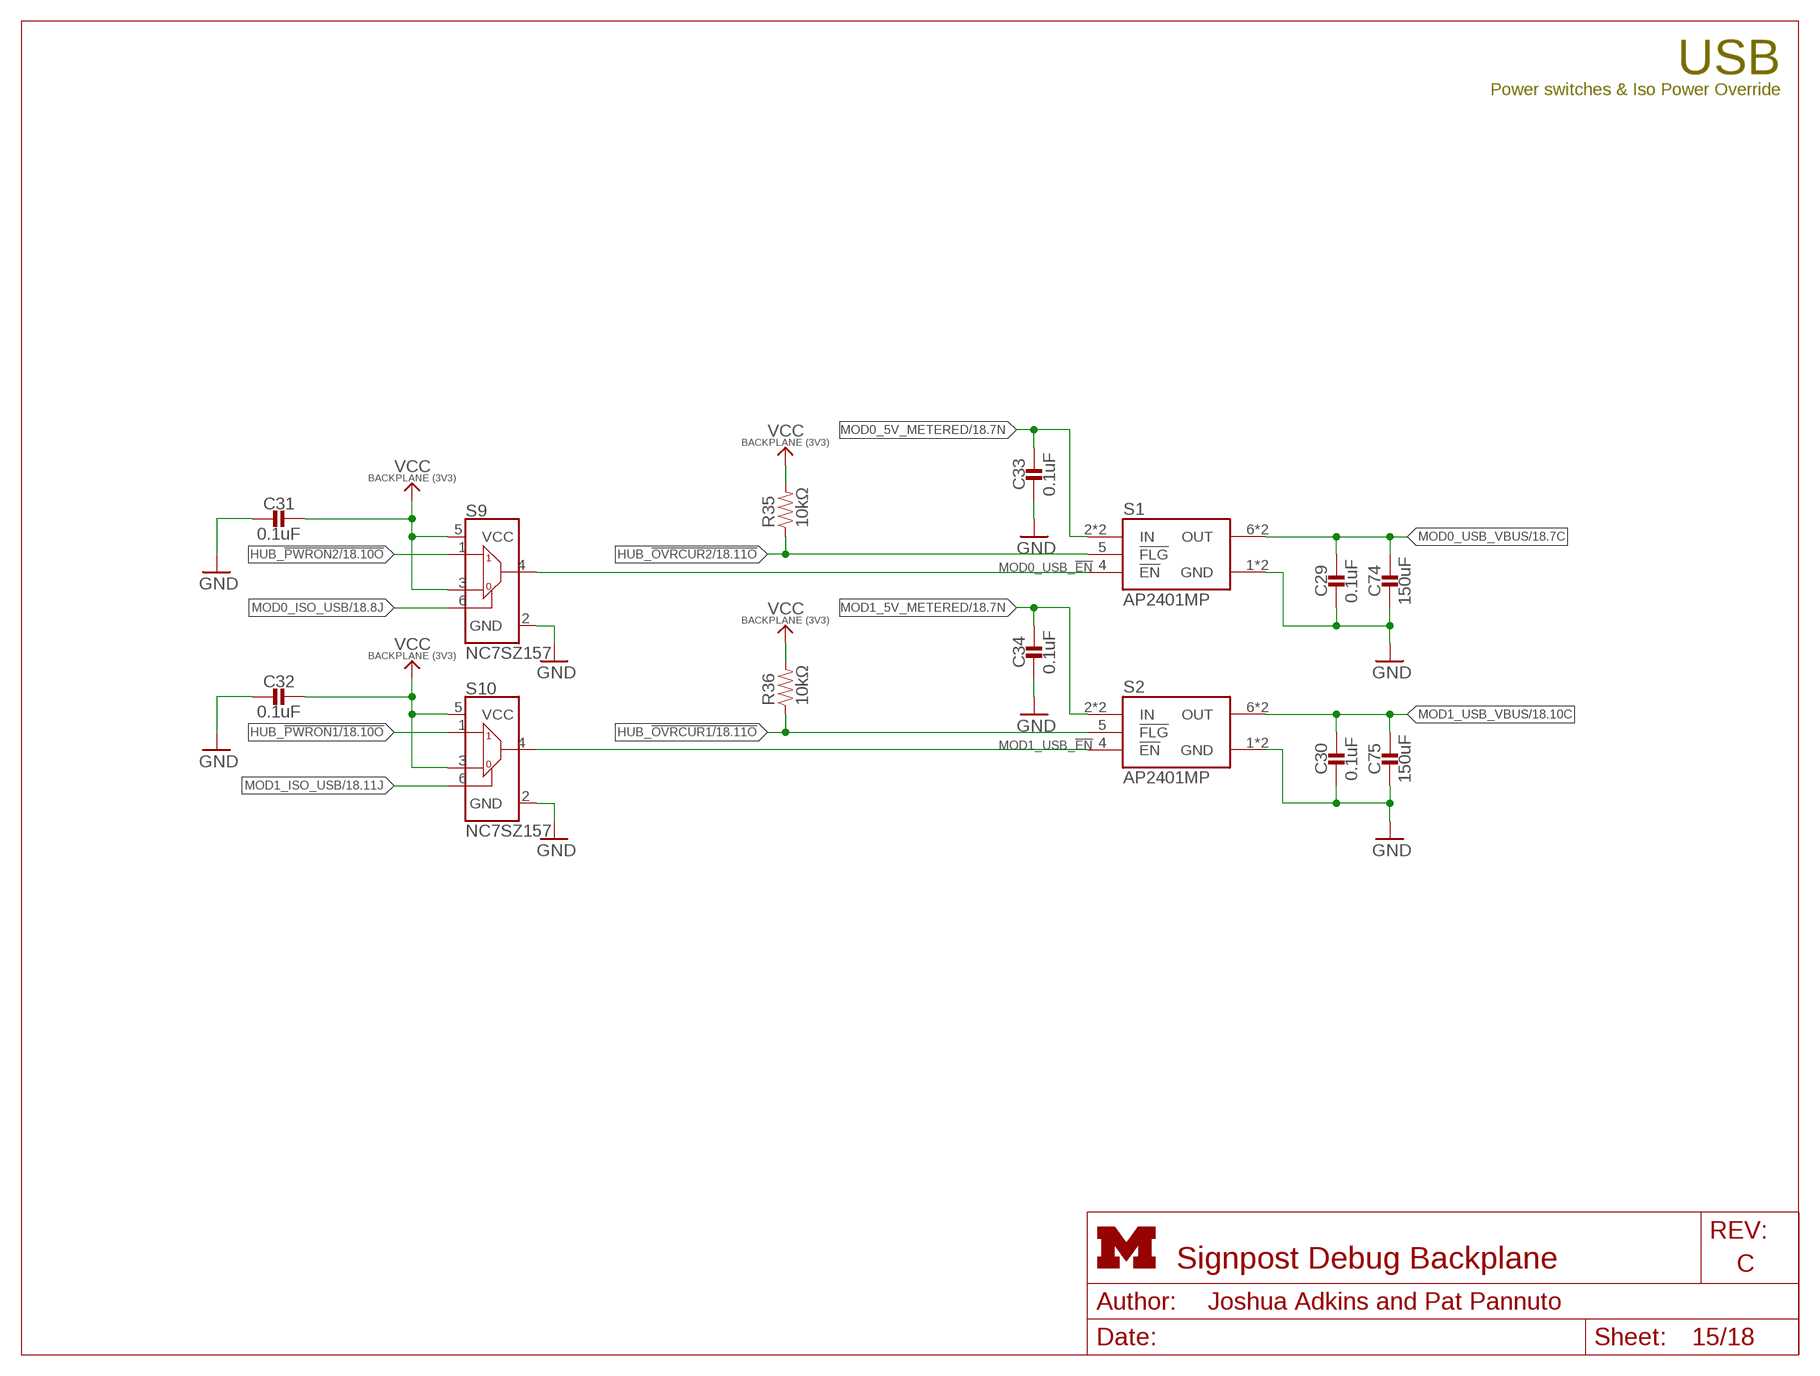
[diagram p14: schematic, sheet 15]
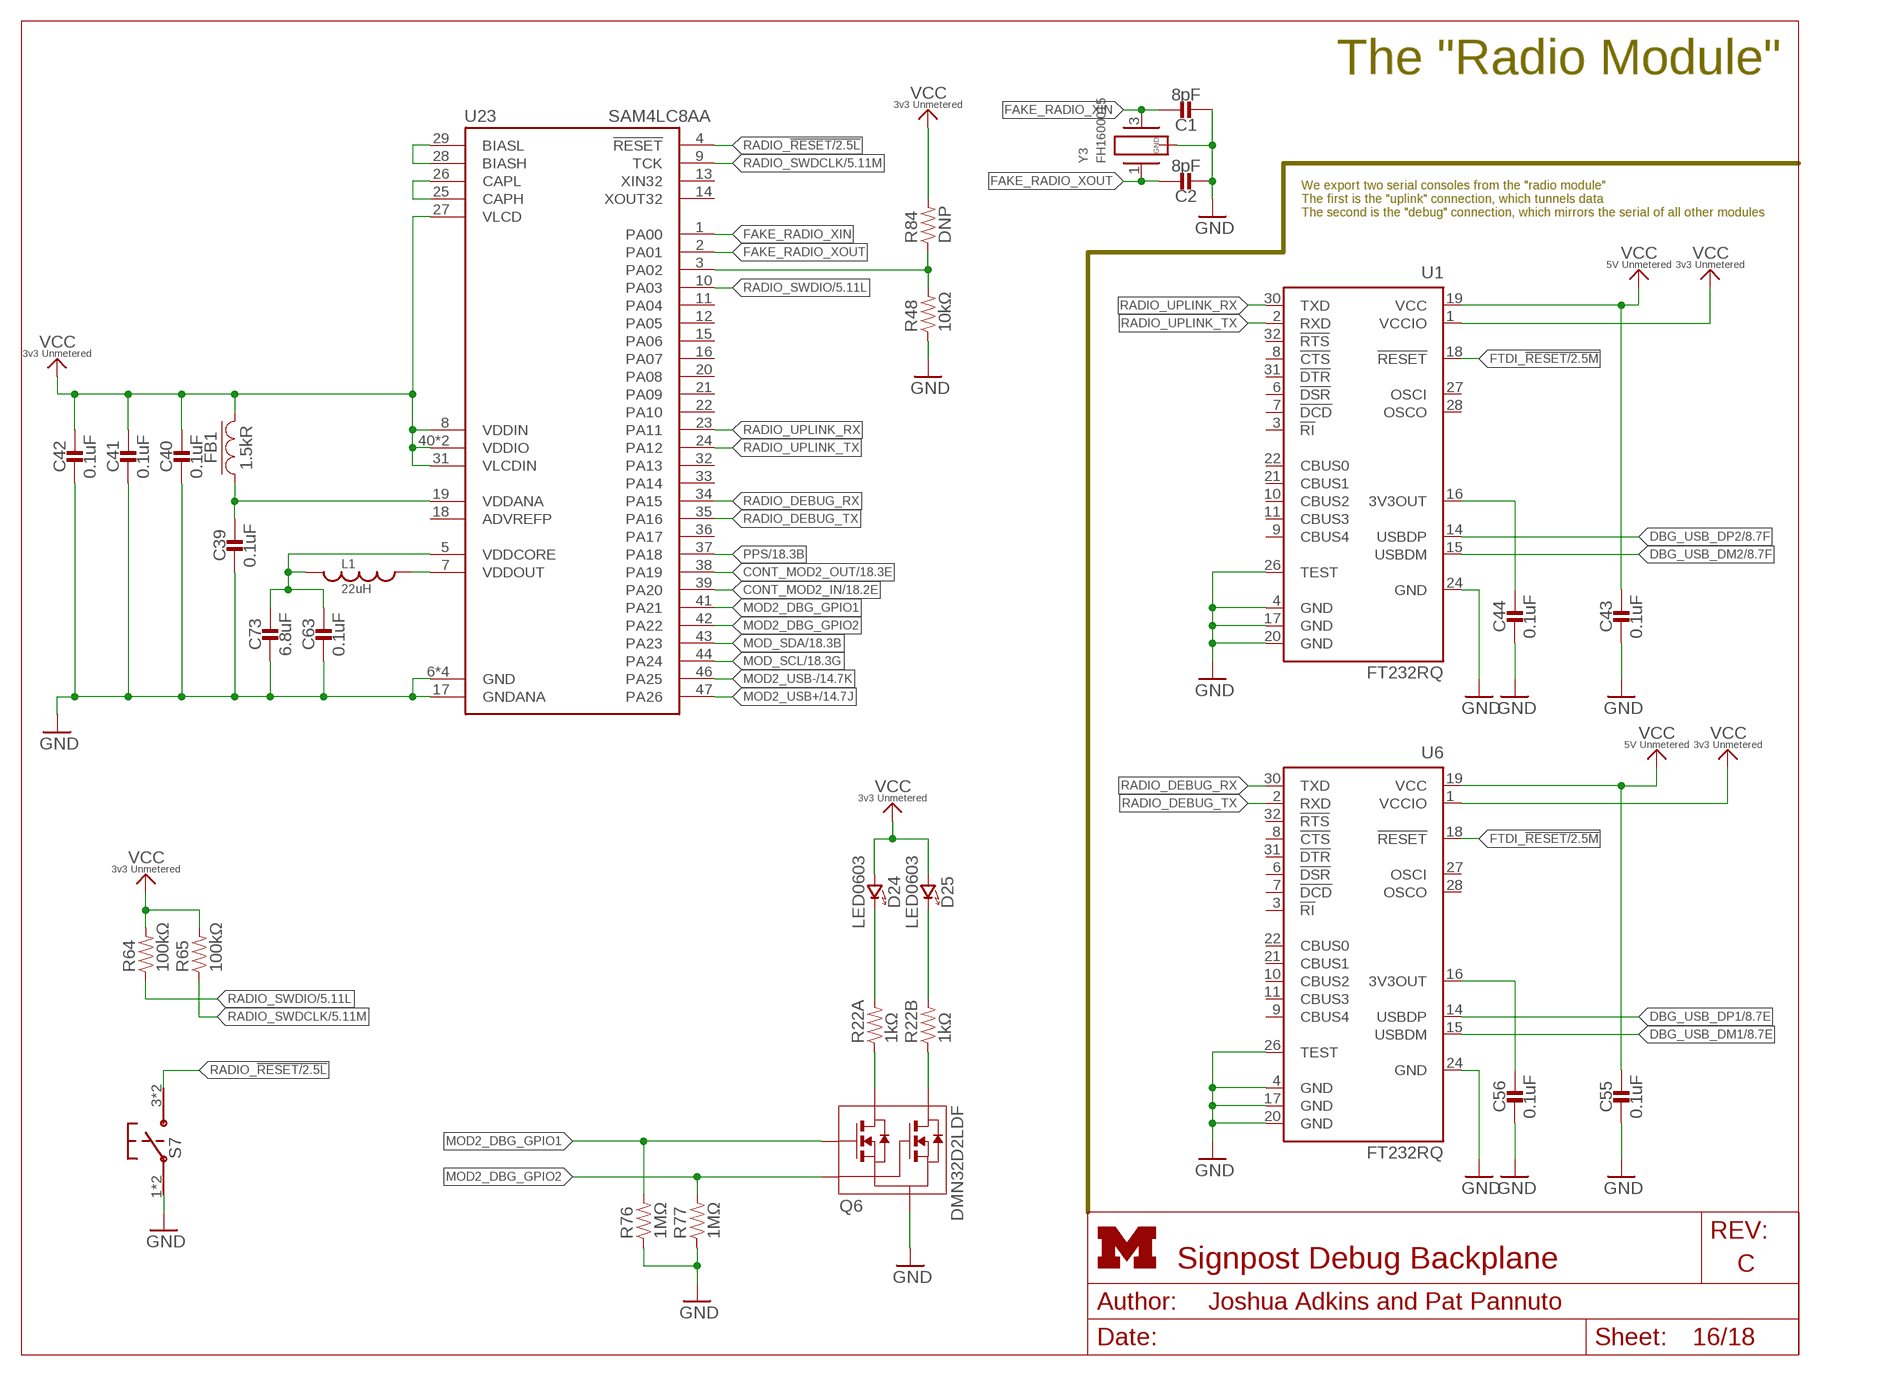
[diagram p15: schematic, sheet 16]
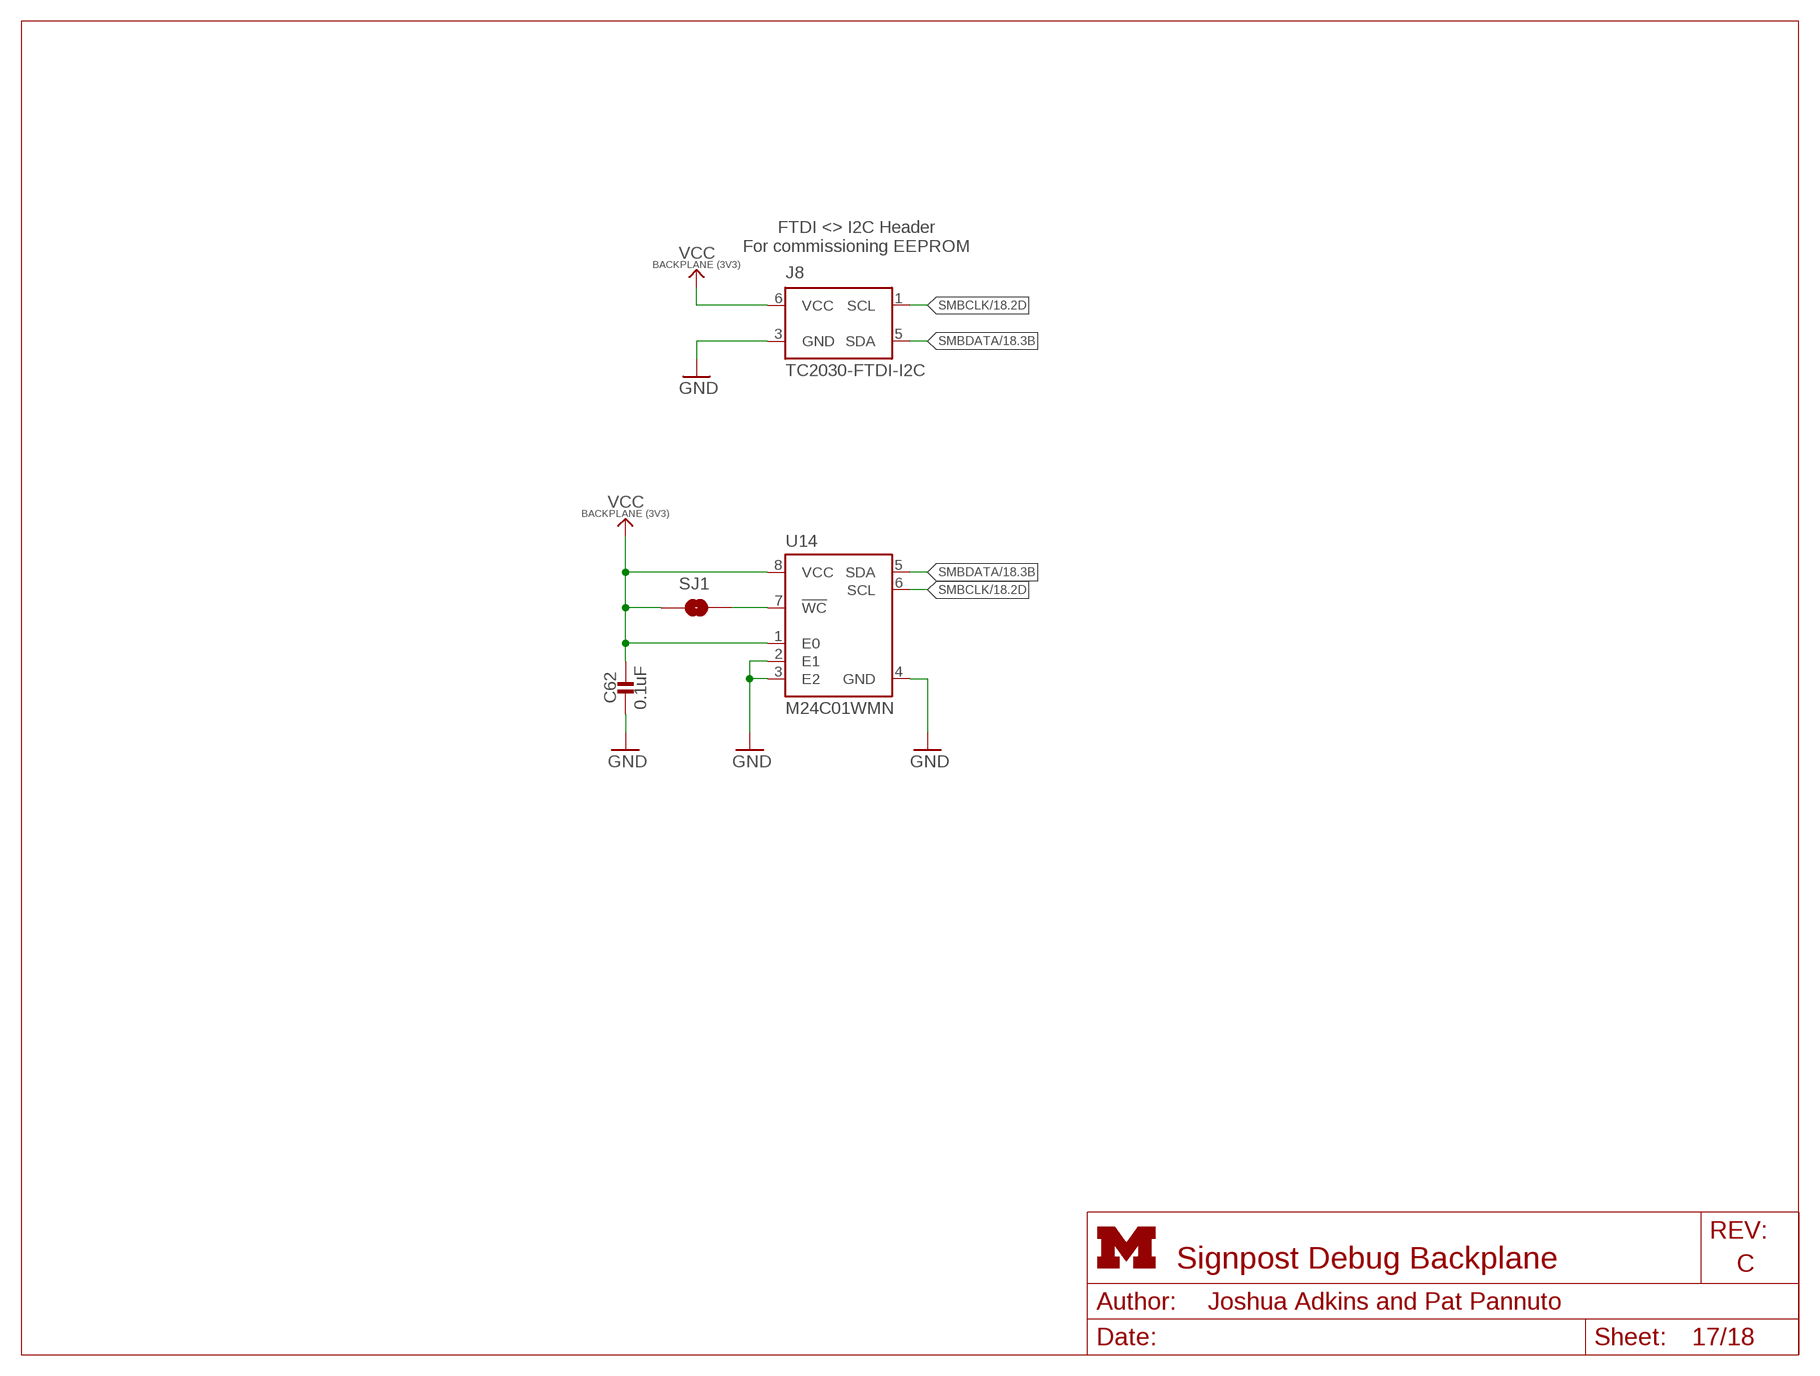
[diagram p16: schematic, sheet 17]
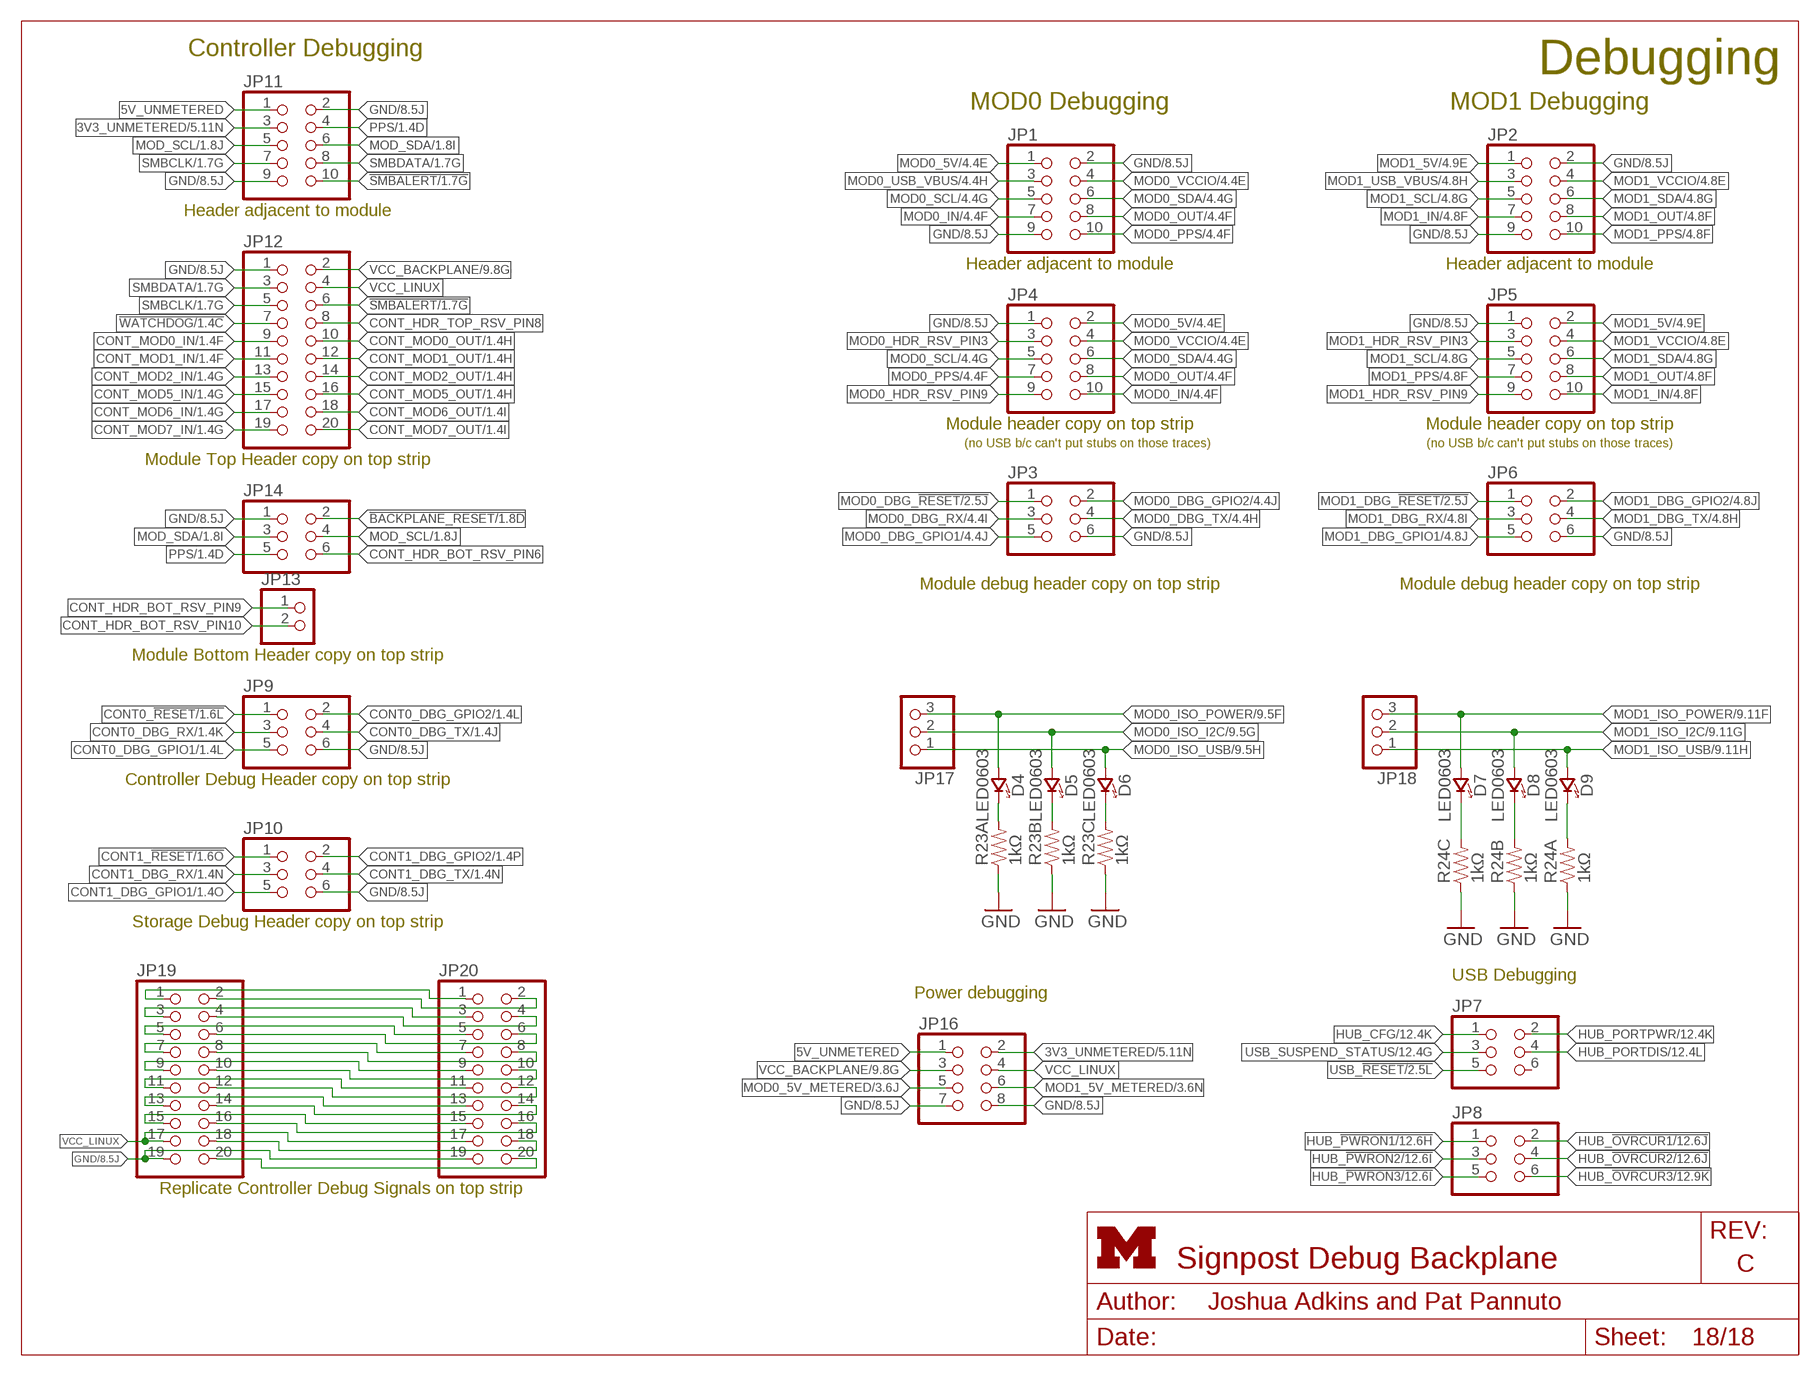
[diagram p17: schematic, sheet 18]

(export (version "E")
  (design (tool "Eeschema 10.0.6"))
  (components
    (comp (ref "C53")
      (value "0.1uF")
      (footprint "eagle-import:0603_CAP")
      (description "CAP CER 0.1UF 16V X7R 0603")
      (fields
        (field (name "DIGIKEY") "490-1532-1-ND")
        (field (name "MANUFACTURER") "Murata")
        (field (name "MPN") "GRM188R71C104KA01D")
      )
      (libsource (lib "eagle-import") (part "CAPACITOR0603_CAP"))
    )
    (comp (ref "J4")
      (value "MICRO_USB_B_HIROSE_ZX62R-B-5P")
      (footprint "eagle-import:USB_MICRO_B-HIROSE-ZX62R-B-5P")
      (libsource (lib "eagle-import") (part "MICRO_USB_B_HIROSE_ZX62R-B-5P"))
    )
    (comp (ref "Q1")
      (value "DMN32D2LDF")
      (footprint "eagle-import:SOT353")
      (fields (field (name "MANUFACTURER") "Diodes Incorporated") (field (name "MPN") "DMN32D2LDF-7"))
      (libsource (lib "eagle-import") (part "DMN32D2LDF"))
    )
    (comp (ref "R66")
      (value "100kΩ")
      (footprint "eagle-import:0603-RES")
      (description "RES SMD 100K OHM 1% 1/16W 0402")
      (fields
        (field (name "DIGIKEY") "1276-3432-1-ND")
        (field (name "MANUFACTURER") "Samsung")
        (field (name "MPN") "RC1005F104CS")
      )
      (libsource (lib "eagle-import") (part "RESISTOR0603_RES"))
    )
    (comp (ref "R67")
      (value "100kΩ")
      (footprint "eagle-import:0603-RES")
      (description "RES SMD 100K OHM 1% 1/16W 0402")
      (fields
        (field (name "DIGIKEY") "1276-3432-1-ND")
        (field (name "MANUFACTURER") "Samsung")
        (field (name "MPN") "RC1005F104CS")
      )
      (libsource (lib "eagle-import") (part "RESISTOR0603_RES"))
    )
    (comp (ref "U30")
      (value "TS3USB30E")
      (footprint "eagle-import:UQFN-10")
      (libsource (lib "eagle-import") (part "TS3USB30E"))
    )
    (comp (ref "C18")
      (value "0.1uF")
      (footprint "eagle-import:0603_CAP")
      (description "CAP CER 0.1UF 16V X7R 0603")
      (fields
        (field (name "DIGIKEY") "490-1532-1-ND")
        (field (name "MANUFACTURER") "Murata")
        (field (name "MPN") "GRM188R71C104KA01D")
      )
      (libsource (lib "eagle-import") (part "CAPACITOR0603_CAP"))
    )
    (comp (ref "C19")
      (value "0.1uF")
      (footprint "eagle-import:0603_CAP")
      (description "CAP CER 0.1UF 16V X7R 0603")
      (fields
        (field (name "DIGIKEY") "490-1532-1-ND")
        (field (name "MANUFACTURER") "Murata")
        (field (name "MPN") "GRM188R71C104KA01D")
      )
      (libsource (lib "eagle-import") (part "CAPACITOR0603_CAP"))
    )
    (comp (ref "C20")
      (value "0.1uF")
      (footprint "eagle-import:0603_CAP")
      (description "CAP CER 0.1UF 16V X7R 0603")
      (fields
        (field (name "DIGIKEY") "490-1532-1-ND")
        (field (name "MANUFACTURER") "Murata")
        (field (name "MPN") "GRM188R71C104KA01D")
      )
      (libsource (lib "eagle-import") (part "CAPACITOR0603_CAP"))
    )
    (comp (ref "C21")
      (value "0.1uF")
      (footprint "eagle-import:0603_CAP")
      (description "CAP CER 0.1UF 16V X7R 0603")
      (fields
        (field (name "DIGIKEY") "490-1532-1-ND")
        (field (name "MANUFACTURER") "Murata")
        (field (name "MPN") "GRM188R71C104KA01D")
      )
      (libsource (lib "eagle-import") (part "CAPACITOR0603_CAP"))
    )
    (comp (ref "C22")
      (value "0.1uF")
      (footprint "eagle-import:0603_CAP")
      (description "CAP CER 0.1UF 16V X7R 0603")
      (fields
        (field (name "DIGIKEY") "490-1532-1-ND")
        (field (name "MANUFACTURER") "Murata")
        (field (name "MPN") "GRM188R71C104KA01D")
      )
      (libsource (lib "eagle-import") (part "CAPACITOR0603_CAP"))
    )
    (comp (ref "C23")
      (value "0.1uF")
      (footprint "eagle-import:0603_CAP")
      (description "CAP CER 0.1UF 16V X7R 0603")
      (fields
        (field (name "DIGIKEY") "490-1532-1-ND")
        (field (name "MANUFACTURER") "Murata")
        (field (name "MPN") "GRM188R71C104KA01D")
      )
      (libsource (lib "eagle-import") (part "CAPACITOR0603_CAP"))
    )
    (comp (ref "C24")
      (value "0.1uF")
      (footprint "eagle-import:0603_CAP")
      (description "CAP CER 0.1UF 16V X7R 0603")
      (fields
        (field (name "DIGIKEY") "490-1532-1-ND")
        (field (name "MANUFACTURER") "Murata")
        (field (name "MPN") "GRM188R71C104KA01D")
      )
      (libsource (lib "eagle-import") (part "CAPACITOR0603_CAP"))
    )
    (comp (ref "C25")
      (value "0.1uF")
      (footprint "eagle-import:0603_CAP")
      (description "CAP CER 0.1UF 16V X7R 0603")
      (fields
        (field (name "DIGIKEY") "490-1532-1-ND")
        (field (name "MANUFACTURER") "Murata")
        (field (name "MPN") "GRM188R71C104KA01D")
      )
      (libsource (lib "eagle-import") (part "CAPACITOR0603_CAP"))
    )
    (comp (ref "U24")
      (value "SN74LVC2T45")
      (footprint "eagle-import:VFSOP-8")
      (libsource (lib "eagle-import") (part "SN74LVC2T45"))
    )
    (comp (ref "U25")
      (value "SN74LVC2T45")
      (footprint "eagle-import:VFSOP-8")
      (libsource (lib "eagle-import") (part "SN74LVC2T45"))
    )
    (comp (ref "U26")
      (value "SN74LVC2T45")
      (footprint "eagle-import:VFSOP-8")
      (libsource (lib "eagle-import") (part "SN74LVC2T45"))
    )
    (comp (ref "U27")
      (value "SN74LVC2T45")
      (footprint "eagle-import:VFSOP-8")
      (libsource (lib "eagle-import") (part "SN74LVC2T45"))
    )
    (comp (ref "C1")
      (value "8pF")
      (footprint "eagle-import:0603_CAP")
      (description "CAP CER 8PF 50V C0G/NP0 0603")
      (fields (field (name "MANUFACTURER") "Murata") (field (name "MPN") "GRM1885C1H8R0DA01D"))
      (libsource (lib "eagle-import") (part "CAPACITOR0603_CAP"))
    )
    (comp (ref "C2")
      (value "8pF")
      (footprint "eagle-import:0603_CAP")
      (description "CAP CER 8PF 50V C0G/NP0 0603")
      (fields (field (name "MANUFACTURER") "Murata") (field (name "MPN") "GRM1885C1H8R0DA01D"))
      (libsource (lib "eagle-import") (part "CAPACITOR0603_CAP"))
    )
    (comp (ref "C39")
      (value "0.1uF")
      (footprint "eagle-import:0603_CAP")
      (description "CAP CER 0.1UF 16V X7R 0603")
      (fields (field (name "MANUFACTURER") "Murata") (field (name "MPN") "GRM188R71C104KA01D"))
      (libsource (lib "eagle-import") (part "CAPACITOR0603_CAP"))
    )
    (comp (ref "C40")
      (value "0.1uF")
      (footprint "eagle-import:0603_CAP")
      (description "CAP CER 0.1UF 16V X7R 0603")
      (fields (field (name "MANUFACTURER") "Murata") (field (name "MPN") "GRM188R71C104KA01D"))
      (libsource (lib "eagle-import") (part "CAPACITOR0603_CAP"))
    )
    (comp (ref "C41")
      (value "0.1uF")
      (footprint "eagle-import:0603_CAP")
      (description "CAP CER 0.1UF 16V X7R 0603")
      (fields (field (name "MANUFACTURER") "Murata") (field (name "MPN") "GRM188R71C104KA01D"))
      (libsource (lib "eagle-import") (part "CAPACITOR0603_CAP"))
    )
    (comp (ref "C42")
      (value "0.1uF")
      (footprint "eagle-import:0603_CAP")
      (description "CAP CER 0.1UF 16V X7R 0603")
      (fields (field (name "MANUFACTURER") "Murata") (field (name "MPN") "GRM188R71C104KA01D"))
      (libsource (lib "eagle-import") (part "CAPACITOR0603_CAP"))
    )
    (comp (ref "C43")
      (value "0.1uF")
      (footprint "eagle-import:0603_CAP")
      (description "CAP CER 0.1UF 16V X7R 0603")
      (fields (field (name "MANUFACTURER") "Murata") (field (name "MPN") "GRM188R71C104KA01D"))
      (libsource (lib "eagle-import") (part "CAPACITOR0603_CAP"))
    )
    (comp (ref "C44")
      (value "0.1uF")
      (footprint "eagle-import:0603_CAP")
      (description "CAP CER 0.1UF 16V X7R 0603")
      (fields (field (name "MANUFACTURER") "Murata") (field (name "MPN") "GRM188R71C104KA01D"))
      (libsource (lib "eagle-import") (part "CAPACITOR0603_CAP"))
    )
    (comp (ref "C55")
      (value "0.1uF")
      (footprint "eagle-import:0603_CAP")
      (description "CAP CER 0.1UF 16V X7R 0603")
      (fields (field (name "MANUFACTURER") "Murata") (field (name "MPN") "GRM188R71C104KA01D"))
      (libsource (lib "eagle-import") (part "CAPACITOR0603_CAP"))
    )
    (comp (ref "C56")
      (value "0.1uF")
      (footprint "eagle-import:0603_CAP")
      (description "CAP CER 0.1UF 16V X7R 0603")
      (fields (field (name "MANUFACTURER") "Murata") (field (name "MPN") "GRM188R71C104KA01D"))
      (libsource (lib "eagle-import") (part "CAPACITOR0603_CAP"))
    )
    (comp (ref "C63")
      (value "0.1uF")
      (footprint "eagle-import:0603_CAP")
      (description "CAP CER 0.1UF 16V X7R 0603")
      (fields (field (name "MANUFACTURER") "Murata") (field (name "MPN") "GRM188R71C104KA01D"))
      (libsource (lib "eagle-import") (part "CAPACITOR0603_CAP"))
    )
    (comp (ref "C73")
      (value "6.8uF")
      (footprint "eagle-import:0603_CAP")
      (description "CAP CER 6.8UF 6.3V X5R 0603")
      (fields (field (name "MANUFACTURER") "TDK") (field (name "MPN") "C1608X5R0J685K080AB"))
      (libsource (lib "eagle-import") (part "CAPACITOR0603_CAP"))
    )
    (comp (ref "D24")
      (value "LED0603")
      (footprint "eagle-import:LED-0603")
      (description "LED RED CLEAR 0603 SMD")
      (fields (field (name "MANUFACTURER") "Lite-On") (field (name "MPN") "LTST-C191KRKT"))
      (libsource (lib "eagle-import") (part "LED0603"))
    )
    (comp (ref "D25")
      (value "LED0603")
      (footprint "eagle-import:LED-0603")
      (description "LED GREEN CLEAR 0603 SMD")
      (fields (field (name "MANUFACTURER") "Lite-On") (field (name "MPN") "LTST-C191KGKT"))
      (libsource (lib "eagle-import") (part "LED0603"))
    )
    (comp (ref "FB1")
      (value "1.5kR")
      (footprint "eagle-import:0603_CAP")
      (description "FERRITE BEAD 1.5 KOHM 0603 1LN")
      (fields (field (name "MANUFACTURER") "Murata") (field (name "MPN") "BLM18HE152SN1D"))
      (libsource (lib "eagle-import") (part "FERRITE_BEAD0603"))
    )
    (comp (ref "L1")
      (value "22uH")
      (footprint "eagle-import:1212")
      (fields (field (name "MANUFACTURER") "Murata") (field (name "MPN") "LQH3NPN220MJ0L"))
      (libsource (lib "eagle-import") (part "LHQ3NP"))
    )
    (comp (ref "Q6")
      (value "DMN32D2LDF")
      (footprint "eagle-import:SOT353")
      (fields (field (name "MANUFACTURER") "Diodes Incorporated") (field (name "MPN") "DMN32D2LDF-7"))
      (libsource (lib "eagle-import") (part "DMN32D2LDF"))
    )
    (comp (ref "R22")
      (value "1kΩ")
      (footprint "eagle-import:ARRAY-CONVEX-0603-4")
      (description "RES ARRAY 4 RES 1K OHM 1206")
      (fields
        (field (name "DIGIKEY") "Y9102CT-ND")
        (field (name "MANUFACTURER") "Panasonic")
        (field (name "MPN") "EXB-38V102JV")
      )
      (libsource (lib "eagle-import") (part "RESISTOR-ARRAY-41206"))
    )
    (comp (ref "R48")
      (value "10kΩ")
      (footprint "eagle-import:0603-RES")
      (description "RES SMD 10K OHM 5% 1/10W 0603")
      (fields (field (name "MANUFACTURER") "Panasonic") (field (name "MPN") "ERJ-3GEYJ103V"))
      (libsource (lib "eagle-import") (part "RESISTOR0603_RES"))
    )
    (comp (ref "R64")
      (value "100kΩ")
      (footprint "eagle-import:0603-RES")
      (description "RES SMD 100K OHM 1% 1/16W 0402")
      (fields (field (name "MANUFACTURER") "Samsung") (field (name "MPN") "RC1005F104CS"))
      (libsource (lib "eagle-import") (part "RESISTOR0603_RES"))
    )
    (comp (ref "R65")
      (value "100kΩ")
      (footprint "eagle-import:0603-RES")
      (description "RES SMD 100K OHM 1% 1/16W 0402")
      (fields (field (name "MANUFACTURER") "Samsung") (field (name "MPN") "RC1005F104CS"))
      (libsource (lib "eagle-import") (part "RESISTOR0603_RES"))
    )
    (comp (ref "R76")
      (value "1MΩ")
      (footprint "eagle-import:0603-RES")
      (description "RES SMD 1M OHM 5% 1/4W 0603")
      (fields
        (field (name "DIGIKEY") "RHM1MDCT-ND")
        (field (name "MANUFACTURER") "Rohm")
        (field (name "MPN") "ESR03EZPJ105")
      )
      (libsource (lib "eagle-import") (part "RESISTOR0603_RES"))
    )
    (comp (ref "R77")
      (value "1MΩ")
      (footprint "eagle-import:0603-RES")
      (description "RES SMD 1M OHM 5% 1/4W 0603")
      (fields
        (field (name "DIGIKEY") "RHM1MDCT-ND")
        (field (name "MANUFACTURER") "Rohm")
        (field (name "MPN") "ESR03EZPJ105")
      )
      (libsource (lib "eagle-import") (part "RESISTOR0603_RES"))
    )
    (comp (ref "R84")
      (value "DNP")
      (footprint "eagle-import:0603-RES")
      (libsource (lib "eagle-import") (part "RESISTOR0603_RES"))
    )
    (comp (ref "S7")
      (value "PTS645SM43SMTR92")
      (footprint "eagle-import:PTS645")
      (libsource (lib "eagle-import") (part "PTS645SM43SMTR92"))
    )
    (comp (ref "U1")
      (value "FT232RQ")
      (footprint "eagle-import:QFN32")
      (libsource (lib "eagle-import") (part "FT232RQ"))
    )
    (comp (ref "U6")
      (value "FT232RQ")
      (footprint "eagle-import:QFN32")
      (libsource (lib "eagle-import") (part "FT232RQ"))
    )
    (comp (ref "U23")
      (value "SAM4LC8AA")
      (footprint "eagle-import:QFN-48-7MM")
      (libsource (lib "eagle-import") (part "SAM4LC8AA"))
    )
    (comp (ref "Y3")
      (value "FH1600015")
      (footprint "eagle-import:FHXXX")
      (fields (field (name "MANUFACTURER") "Diodes Incorporated"))
      (libsource (lib "eagle-import") (part "FH1600015"))
    )
    (comp (ref "C13")
      (value "0.01uF")
      (footprint "eagle-import:0603_CAP")
      (description "CAP CER 10000PF 50V X7R 0603")
      (fields (field (name "MANUFACTURER") "Murata") (field (name "MPN") "GRM188R71H103KA01D"))
      (libsource (lib "eagle-import") (part "CAPACITOR0603_CAP"))
    )
    (comp (ref "C58")
      (value "0.1uF")
      (footprint "eagle-import:0603_CAP")
      (description "CAP CER 0.1UF 16V X7R 0603")
      (fields
        (field (name "DIGIKEY") "490-1532-1-ND")
        (field (name "MANUFACTURER") "Murata")
        (field (name "MPN") "GRM188R71C104KA01D")
      )
      (libsource (lib "eagle-import") (part "CAPACITOR0603_CAP"))
    )
    (comp (ref "C59")
      (value "0.1uF")
      (footprint "eagle-import:0603_CAP")
      (description "CAP CER 0.1UF 16V X7R 0603")
      (fields
        (field (name "DIGIKEY") "490-1532-1-ND")
        (field (name "MANUFACTURER") "Murata")
        (field (name "MPN") "GRM188R71C104KA01D")
      )
      (libsource (lib "eagle-import") (part "CAPACITOR0603_CAP"))
    )
    (comp (ref "C60")
      (value "0.1uF")
      (footprint "eagle-import:0603_CAP")
      (description "CAP CER 0.1UF 16V X7R 0603")
      (fields
        (field (name "DIGIKEY") "490-1532-1-ND")
        (field (name "MANUFACTURER") "Murata")
        (field (name "MPN") "GRM188R71C104KA01D")
      )
      (libsource (lib "eagle-import") (part "CAPACITOR0603_CAP"))
    )
    (comp (ref "C61")
      (value "0.1uF")
      (footprint "eagle-import:0603_CAP")
      (description "CAP CER 0.1UF 16V X7R 0603")
      (fields
        (field (name "DIGIKEY") "490-1532-1-ND")
        (field (name "MANUFACTURER") "Murata")
        (field (name "MPN") "GRM188R71C104KA01D")
      )
      (libsource (lib "eagle-import") (part "CAPACITOR0603_CAP"))
    )
    (comp (ref "C66")
      (value "2.2uF")
      (footprint "eagle-import:0603_CAP")
      (description "CAP CER 2.2UF 16V 10% X5R 0603")
      (fields (field (name "MANUFACTURER") "Murata") (field (name "MPN") "GRM188R61C225KE15D"))
      (libsource (lib "eagle-import") (part "CAPACITOR0603_CAP"))
    )
    (comp (ref "C67")
      (value "2.2uF")
      (footprint "eagle-import:0603_CAP")
      (description "CAP CER 2.2UF 16V 10% X5R 0603")
      (fields (field (name "MANUFACTURER") "Murata") (field (name "MPN") "GRM188R61C225KE15D"))
      (libsource (lib "eagle-import") (part "CAPACITOR0603_CAP"))
    )
    (comp (ref "C71")
      (value "4.7uF")
      (footprint "eagle-import:0603_CAP")
      (description "CAP CER 4.7UF 6.3V X7R 0603")
      (fields
        (field (name "DIGIKEY") "1276-2087-1-ND")
        (field (name "MANUFACTURER") "Samsung")
        (field (name "MPN") "CL10B475KQ8NQNC")
      )
      (libsource (lib "eagle-import") (part "CAPACITOR0603_CAP"))
    )
    (comp (ref "D23")
      (value "LED0603")
      (footprint "eagle-import:LED-0603")
      (description "LED GREEN CLEAR 0603 SMD")
      (fields (field (name "MANUFACTURER") "Lite-On") (field (name "MPN") "LTST-C191KGKT"))
      (libsource (lib "eagle-import") (part "LED0603"))
    )
    (comp (ref "J7")
      (value "PJ-102AH")
      (footprint "eagle-import:PJ-102AH")
      (libsource (lib "eagle-import") (part "PJ-102AH"))
    )
    (comp (ref "Q8")
      (value "MOSFET-NCHANNELSMD")
      (footprint "eagle-import:SOT23-3")
      (description "MOSFET N-CH 20V 2.6A SOT-23")
      (fields (field (name "MANUFACTURER") "Vishay Siliconix") (field (name "MPN") "SI2302CDS-T1-E3"))
      (libsource (lib "eagle-import") (part "MOSFET-NCHANNELSMD"))
    )
    (comp (ref "R1")
      (value "0.017Ω")
      (footprint "eagle-import:0805_RES")
      (description "RES SMD 0.017 OHM 1% 1/2W 0805")
      (fields (field (name "MANUFACTURER") "Vishay Dale") (field (name "MPN") "WSLP0805R0170FEB"))
      (libsource (lib "eagle-import") (part "RESISTOR0805_RES"))
    )
    (comp (ref "R2")
      (value "0.017Ω")
      (footprint "eagle-import:0805_RES")
      (description "RES SMD 0.017 OHM 1% 1/2W 0805")
      (fields
        (field (name "DIGIKEY") "WSLPB-.017CT-ND")
        (field (name "MANUFACTURER") "Vishay Dale")
        (field (name "MPN") "WSLP0805R0170FEB")
      )
      (libsource (lib "eagle-import") (part "RESISTOR0805_RES"))
    )
    (comp (ref "R3")
      (value "0.017Ω")
      (footprint "eagle-import:0805_RES")
      (description "RES SMD 0.017 OHM 1% 1/2W 0805")
      (fields
        (field (name "DIGIKEY") "WSLPB-.017CT-ND")
        (field (name "MANUFACTURER") "Vishay Dale")
        (field (name "MPN") "WSLP0805R0170FEB")
      )
      (libsource (lib "eagle-import") (part "RESISTOR0805_RES"))
    )
    (comp (ref "R4")
      (value "0.017Ω")
      (footprint "eagle-import:0805_RES")
      (description "RES SMD 0.017 OHM 1% 1/2W 0805")
      (fields
        (field (name "DIGIKEY") "WSLPB-.017CT-ND")
        (field (name "MANUFACTURER") "Vishay Dale")
        (field (name "MPN") "WSLP0805R0170FEB")
      )
      (libsource (lib "eagle-import") (part "RESISTOR0805_RES"))
    )
    (comp (ref "R15")
      (value "50Ω")
      (footprint "eagle-import:0603-RES")
      (description "RES SMD 49.9 OHM 1% 1/10W 0603")
      (fields
        (field (name "DIGIKEY") "RHM49.9BJCT-ND")
        (field (name "MANUFACTURER") "Rohm")
        (field (name "MPN") "TRR03EZPF49R9")
      )
      (libsource (lib "eagle-import") (part "RESISTOR0603_RES"))
    )
    (comp (ref "R17")
      (value "50Ω")
      (footprint "eagle-import:0603-RES")
      (description "RES SMD 49.9 OHM 1% 1/10W 0603")
      (fields
        (field (name "DIGIKEY") "RHM49.9BJCT-ND")
        (field (name "MANUFACTURER") "Rohm")
        (field (name "MPN") "TRR03EZPF49R9")
      )
      (libsource (lib "eagle-import") (part "RESISTOR0603_RES"))
    )
    (comp (ref "R31")
      (value "1.8kΩ")
      (footprint "eagle-import:ARRAY-CONVEX-0603-4")
      (description "RES ARRAY 4 RES 1.8K OHM 1206")
      (fields
        (field (name "MANUFACTURER") "Panasonic")
        (field (name "MPN") "EXB-38V182JV")
        (field (name "DIGIKEY") "Y9182CT-ND")
      )
      (libsource (lib "eagle-import") (part "RESISTOR-ARRAY-41206"))
    )
    (comp (ref "R32")
      (value "1.8kΩ")
      (footprint "eagle-import:ARRAY-CONVEX-0603-4")
      (description "RES ARRAY 4 RES 1.8K OHM 1206")
      (fields
        (field (name "DIGIKEY") "Y9182CT-ND")
        (field (name "MANUFACTURER") "Panasonic")
        (field (name "MPN") "EXB-38V182JV")
      )
      (libsource (lib "eagle-import") (part "RESISTOR-ARRAY-41206"))
    )
    (comp (ref "R33")
      (value "1.8kΩ")
      (footprint "eagle-import:ARRAY-CONVEX-0603-4")
      (description "RES ARRAY 4 RES 1.8K OHM 1206")
      (fields
        (field (name "DIGIKEY") "Y9182CT-ND")
        (field (name "MANUFACTURER") "Panasonic")
        (field (name "MPN") "EXB-38V182JV")
      )
      (libsource (lib "eagle-import") (part "RESISTOR-ARRAY-41206"))
    )
    (comp (ref "R34")
      (value "1.8kΩ")
      (footprint "eagle-import:ARRAY-CONVEX-0603-4")
      (description "RES ARRAY 4 RES 1.8K OHM 1206")
      (fields
        (field (name "DIGIKEY") "Y9182CT-ND")
        (field (name "MANUFACTURER") "Panasonic")
        (field (name "MPN") "EXB-38V182JV")
      )
      (libsource (lib "eagle-import") (part "RESISTOR-ARRAY-41206"))
    )
    (comp (ref "R47")
      (value "10kΩ")
      (footprint "eagle-import:0603-RES")
      (description "RES SMD 10K OHM 5% 1/10W 0603")
      (fields
        (field (name "DIGIKEY") "P10KGCT-ND")
        (field (name "MANUFACTURER") "Panasonic")
        (field (name "MPN") "ERJ-3GEYJ103V")
      )
      (libsource (lib "eagle-import") (part "RESISTOR0603_RES"))
    )
    (comp (ref "U9")
      (value "LTC2941")
      (footprint "eagle-import:DFN-6-2MMX3MM")
      (libsource (lib "eagle-import") (part "LTC2941"))
    )
    (comp (ref "U10")
      (value "LTC2943")
      (footprint "eagle-import:DFN-8")
      (libsource (lib "eagle-import") (part "LTC2943"))
    )
    (comp (ref "U11")
      (value "LTC2943")
      (footprint "eagle-import:DFN-8")
      (libsource (lib "eagle-import") (part "LTC2943"))
    )
    (comp (ref "U12")
      (value "LTC2943")
      (footprint "eagle-import:DFN-8")
      (libsource (lib "eagle-import") (part "LTC2943"))
    )
    (comp (ref "U13")
      (value "LTC4360")
      (footprint "eagle-import:SC70-8")
      (libsource (lib "eagle-import") (part "LTC4360"))
    )
    (comp (ref "U16")
      (value "MAX8887EZK33+T")
      (footprint "eagle-import:SOT-23-5")
      (libsource (lib "eagle-import") (part "MAX8887EZK33+T"))
    )
    (comp (ref "U22")
      (value "PCA9544AQFN-N20")
      (footprint "eagle-import:QFN-N20")
      (libsource (lib "eagle-import") (part "PCA9544AQFN-N20"))
    )
    (comp (ref "C29")
      (value "0.1uF")
      (footprint "eagle-import:0603_CAP")
      (description "CAP CER 0.1UF 16V X7R 0603")
      (fields
        (field (name "DIGIKEY") "490-1532-1-ND")
        (field (name "MANUFACTURER") "Murata")
        (field (name "MPN") "GRM188R71C104KA01D")
      )
      (libsource (lib "eagle-import") (part "CAPACITOR0603_CAP"))
    )
    (comp (ref "C30")
      (value "0.1uF")
      (footprint "eagle-import:0603_CAP")
      (description "CAP CER 0.1UF 16V X7R 0603")
      (fields
        (field (name "DIGIKEY") "490-1532-1-ND")
        (field (name "MANUFACTURER") "Murata")
        (field (name "MPN") "GRM188R71C104KA01D")
      )
      (libsource (lib "eagle-import") (part "CAPACITOR0603_CAP"))
    )
    (comp (ref "C31")
      (value "0.1uF")
      (footprint "eagle-import:0603_CAP")
      (description "CAP CER 0.1UF 16V X7R 0603")
      (fields
        (field (name "DIGIKEY") "490-1532-1-ND")
        (field (name "MANUFACTURER") "Murata")
        (field (name "MPN") "GRM188R71C104KA01D")
      )
      (libsource (lib "eagle-import") (part "CAPACITOR0603_CAP"))
    )
    (comp (ref "C32")
      (value "0.1uF")
      (footprint "eagle-import:0603_CAP")
      (description "CAP CER 0.1UF 16V X7R 0603")
      (fields
        (field (name "DIGIKEY") "490-1532-1-ND")
        (field (name "MANUFACTURER") "Murata")
        (field (name "MPN") "GRM188R71C104KA01D")
      )
      (libsource (lib "eagle-import") (part "CAPACITOR0603_CAP"))
    )
    (comp (ref "C33")
      (value "0.1uF")
      (footprint "eagle-import:0603_CAP")
      (description "CAP CER 0.1UF 16V X7R 0603")
      (fields
        (field (name "DIGIKEY") "490-1532-1-ND")
        (field (name "MANUFACTURER") "Murata")
        (field (name "MPN") "GRM188R71C104KA01D")
      )
      (libsource (lib "eagle-import") (part "CAPACITOR0603_CAP"))
    )
    (comp (ref "C34")
      (value "0.1uF")
      (footprint "eagle-import:0603_CAP")
      (description "CAP CER 0.1UF 16V X7R 0603")
      (fields
        (field (name "DIGIKEY") "490-1532-1-ND")
        (field (name "MANUFACTURER") "Murata")
        (field (name "MPN") "GRM188R71C104KA01D")
      )
      (libsource (lib "eagle-import") (part "CAPACITOR0603_CAP"))
    )
    (comp (ref "C74")
      (value "150uF")
      (footprint "eagle-import:1210_CAP")
      (description "CAP CER 150UF 6.3V X5R 1210")
      (fields (field (name "MANUFACTURER") "Samsung") (field (name "MPN") "CL32A157MQVNNNE"))
      (libsource (lib "eagle-import") (part "CAPACITOR1210_CAP"))
    )
    (comp (ref "C75")
      (value "150uF")
      (footprint "eagle-import:1210_CAP")
      (description "CAP CER 150UF 6.3V X5R 1210")
      (fields (field (name "MANUFACTURER") "Samsung") (field (name "MPN") "CL32A157MQVNNNE"))
      (libsource (lib "eagle-import") (part "CAPACITOR1210_CAP"))
    )
    (comp (ref "R35")
      (value "10kΩ")
      (footprint "eagle-import:0603-RES")
      (description "RES SMD 10K OHM 5% 1/10W 0603")
      (fields
        (field (name "DIGIKEY") "P10KGCT-ND")
        (field (name "MANUFACTURER") "Panasonic")
        (field (name "MPN") "ERJ-3GEYJ103V")
      )
      (libsource (lib "eagle-import") (part "RESISTOR0603_RES"))
    )
    (comp (ref "R36")
      (value "10kΩ")
      (footprint "eagle-import:0603-RES")
      (description "RES SMD 10K OHM 5% 1/10W 0603")
      (fields
        (field (name "DIGIKEY") "P10KGCT-ND")
        (field (name "MANUFACTURER") "Panasonic")
        (field (name "MPN") "ERJ-3GEYJ103V")
      )
      (libsource (lib "eagle-import") (part "RESISTOR0603_RES"))
    )
    (comp (ref "S1")
      (value "AP2401MP")
      (footprint "eagle-import:MSOP-8EP")
      (libsource (lib "eagle-import") (part "AP2401MP"))
    )
    (comp (ref "S2")
      (value "AP2401MP")
      (footprint "eagle-import:MSOP-8EP")
      (libsource (lib "eagle-import") (part "AP2401MP"))
    )
    (comp (ref "S9")
      (value "NC7SZ157")
      (footprint "eagle-import:SC70-6")
      (libsource (lib "eagle-import") (part "NC7SZ157"))
    )
    (comp (ref "S10")
      (value "NC7SZ157")
      (footprint "eagle-import:SC70-6")
      (libsource (lib "eagle-import") (part "NC7SZ157"))
    )
    (comp (ref "C64")
      (value "0.47uF")
      (footprint "eagle-import:0603_CAP")
      (description "CAP CER 0.47UF 10V X5R 0603")
      (fields (field (name "MANUFACTURER") "Murata") (field (name "MPN") "GRM188R61A474KA61D"))
      (libsource (lib "eagle-import") (part "CAPACITOR0603_CAP"))
    )
    (comp (ref "C65")
      (value "0.82uF")
      (footprint "eagle-import:0603_CAP")
      (description "CAP CER 0.82UF 6.3V X5R 0603")
      (fields (field (name "MANUFACTURER") "Murata") (field (name "MPN") "GRM188R60J824KA01D"))
      (libsource (lib "eagle-import") (part "CAPACITOR0603_CAP"))
    )
    (comp (ref "D1")
      (value "DIODE_SCHOTTKY_ARRAY-4HMD8")
      (footprint "eagle-import:HMD8")
      (fields (field (name "MANUFACTURER") "Rohm Semiconductor") (field (name "MPN") "RB521ZS8A30TE61"))
      (libsource (lib "eagle-import") (part "DIODE_SCHOTTKY_ARRAY-4HMD8"))
    )
    (comp (ref "D2")
      (value "DIODE_SCHOTTKY_ARRAY-4HMD8")
      (footprint "eagle-import:HMD8")
      (fields (field (name "MANUFACTURER") "Rohm Semiconductor") (field (name "MPN") "RB521ZS8A30TE61"))
      (libsource (lib "eagle-import") (part "DIODE_SCHOTTKY_ARRAY-4HMD8"))
    )
    (comp (ref "D3")
      (value "DIODE_SCHOTTKY_ARRAY-4HMD8")
      (footprint "eagle-import:HMD8")
      (fields (field (name "MANUFACTURER") "Rohm Semiconductor") (field (name "MPN") "RB521ZS8A30TE61"))
      (libsource (lib "eagle-import") (part "DIODE_SCHOTTKY_ARRAY-4HMD8"))
    )
    (comp (ref "D34")
      (value "LED0603")
      (footprint "eagle-import:LED-0603")
      (description "LED RED CLEAR 0603 SMD")
      (fields (field (name "MANUFACTURER") "Lite-On") (field (name "MPN") "LTST-C191KRKT"))
      (libsource (lib "eagle-import") (part "LED0603"))
    )
    (comp (ref "Q7")
      (value "DMN32D2LDF")
      (footprint "eagle-import:SOT353")
      (fields (field (name "MANUFACTURER") "Diodes Incorporated") (field (name "MPN") "DMN32D2LDF-7"))
      (libsource (lib "eagle-import") (part "DMN32D2LDF"))
    )
    (comp (ref "R16")
      (value "50Ω")
      (footprint "eagle-import:0603-RES")
      (description "RES SMD 49.9 OHM 1% 1/10W 0603")
      (fields
        (field (name "DIGIKEY") "RHM49.9BJCT-ND")
        (field (name "MANUFACTURER") "Rohm")
        (field (name "MPN") "TRR03EZPF49R9")
      )
      (libsource (lib "eagle-import") (part "RESISTOR0603_RES"))
    )
    (comp (ref "S8")
      (value "PTS645SM43SMTR92")
      (footprint "eagle-import:PTS645")
      (libsource (lib "eagle-import") (part "PTS645SM43SMTR92"))
    )
    (comp (ref "S20")
      (value "PTS645SM43SMTR92")
      (footprint "eagle-import:PTS645")
      (libsource (lib "eagle-import") (part "PTS645SM43SMTR92"))
    )
    (comp (ref "S23")
      (value "TE_SSA12/SPDT")
      (footprint "eagle-import:TE_SSA12_SPDT")
      (libsource (lib "eagle-import") (part "TE_SSA12/SPDT"))
    )
    (comp (ref "U15")
      (value "MAX6746")
      (footprint "eagle-import:SOT-23-8")
      (libsource (lib "eagle-import") (part "MAX6746"))
    )
    (comp (ref "C11")
      (value "22pF")
      (footprint "eagle-import:0603_CAP")
      (description "CAP CER 22PF 50V C0G/NP0 0603")
      (fields (field (name "MANUFACTURER") "Samsung") (field (name "MPN") "CL10C220JB8NNNC"))
      (libsource (lib "eagle-import") (part "CAPACITOR0603_CAP"))
    )
    (comp (ref "C12")
      (value "22pF")
      (footprint "eagle-import:0603_CAP")
      (description "CAP CER 22PF 50V C0G/NP0 0603")
      (fields (field (name "MANUFACTURER") "Samsung") (field (name "MPN") "CL10C220JB8NNNC"))
      (libsource (lib "eagle-import") (part "CAPACITOR0603_CAP"))
    )
    (comp (ref "C54")
      (value "0.1uF")
      (footprint "eagle-import:0603_CAP")
      (description "CAP CER 0.1UF 16V X7R 0603")
      (fields
        (field (name "DIGIKEY") "490-1532-1-ND")
        (field (name "MANUFACTURER") "Murata")
        (field (name "MPN") "GRM188R71C104KA01D")
      )
      (libsource (lib "eagle-import") (part "CAPACITOR0603_CAP"))
    )
    (comp (ref "C72")
      (value "4.7uF")
      (footprint "eagle-import:0603_CAP")
      (description "CAP CER 4.7UF 6.3V X7R 0603")
      (fields
        (field (name "DIGIKEY") "1276-2087-1-ND")
        (field (name "MANUFACTURER") "Samsung")
        (field (name "MPN") "CL10B475KQ8NQNC")
      )
      (libsource (lib "eagle-import") (part "CAPACITOR0603_CAP"))
    )
    (comp (ref "J5")
      (value "MICRO_USB_B_HIROSE_ZX62R-B-5P")
      (footprint "eagle-import:USB_MICRO_B-HIROSE-ZX62R-B-5P")
      (libsource (lib "eagle-import") (part "MICRO_USB_B_HIROSE_ZX62R-B-5P"))
    )
    (comp (ref "R29")
      (value "1.5kΩ")
      (footprint "eagle-import:0603-RES")
      (description "RES SMD 1.5K OHM 5% 1/10W 0603")
      (fields
        (field (name "DIGIKEY") "311-1.5KGRCT-ND")
        (field (name "MANUFACTURER") "Yageo")
        (field (name "MPN") "RC0603JR-071K5L")
      )
      (libsource (lib "eagle-import") (part "RESISTOR0603_RES"))
    )
    (comp (ref "R30")
      (value "1.5kΩ")
      (footprint "eagle-import:0603-RES")
      (description "RES SMD 1.5K OHM 5% 1/10W 0603")
      (fields
        (field (name "DIGIKEY") "311-1.5KGRCT-ND")
        (field (name "MANUFACTURER") "Yageo")
        (field (name "MPN") "RC0603JR-071K5L")
      )
      (libsource (lib "eagle-import") (part "RESISTOR0603_RES"))
    )
    (comp (ref "R50")
      (value "10kΩ")
      (footprint "eagle-import:0603-RES")
      (description "RES SMD 10K OHM 5% 1/10W 0603")
      (fields
        (field (name "DIGIKEY") "P10KGCT-ND")
        (field (name "MANUFACTURER") "Panasonic")
        (field (name "MPN") "ERJ-3GEYJ103V")
      )
      (libsource (lib "eagle-import") (part "RESISTOR0603_RES"))
    )
    (comp (ref "R51")
      (value "10kΩ")
      (footprint "eagle-import:0603-RES")
      (description "RES SMD 10K OHM 5% 1/10W 0603")
      (fields
        (field (name "DIGIKEY") "P10KGCT-ND")
        (field (name "MANUFACTURER") "Panasonic")
        (field (name "MPN") "ERJ-3GEYJ103V")
      )
      (libsource (lib "eagle-import") (part "RESISTOR0603_RES"))
    )
    (comp (ref "R59")
      (value "15kΩ")
      (footprint "eagle-import:0603-RES")
      (description "RES SMD 15K OHM 1% 1/10W 0603")
      (fields
        (field (name "DIGIKEY") "RHM15.0KCFCT-ND")
        (field (name "MANUFACTURER") "Rohm")
        (field (name "MPN") "MCR03ERTF1502")
      )
      (libsource (lib "eagle-import") (part "RESISTOR0603_RES"))
    )
    (comp (ref "R60")
      (value "15kΩ")
      (footprint "eagle-import:0603-RES")
      (description "RES SMD 15K OHM 1% 1/10W 0603")
      (fields
        (field (name "DIGIKEY") "RHM15.0KCFCT-ND")
        (field (name "MANUFACTURER") "Rohm")
        (field (name "MPN") "MCR03ERTF1502")
      )
      (libsource (lib "eagle-import") (part "RESISTOR0603_RES"))
    )
    (comp (ref "TP1")
      (value "TEST_POINT_0.040IN")
      (footprint "eagle-import:TESTPOINT_0.040IN")
      (libsource (lib "eagle-import") (part "TEST_POINT_0.040IN"))
    )
    (comp (ref "TP2")
      (value "TEST_POINT_0.040IN")
      (footprint "eagle-import:TESTPOINT_0.040IN")
      (libsource (lib "eagle-import") (part "TEST_POINT_0.040IN"))
    )
    (comp (ref "TP3")
      (value "TEST_POINT_0.040IN")
      (footprint "eagle-import:TESTPOINT_0.040IN")
      (libsource (lib "eagle-import") (part "TEST_POINT_0.040IN"))
    )
    (comp (ref "TP12")
      (value "TEST_POINT_0.040IN")
      (footprint "eagle-import:TESTPOINT_0.040IN")
      (libsource (lib "eagle-import") (part "TEST_POINT_0.040IN"))
    )
    (comp (ref "U20")
      (value "NCP301LSN30")
      (footprint "eagle-import:SOT23-5")
      (libsource (lib "eagle-import") (part "NCP301LSN30"))
    )
    (comp (ref "U32")
      (value "TUSB2077A")
      (footprint "eagle-import:LQFP-48")
      (libsource (lib "eagle-import") (part "TUSB2077A"))
    )
    (comp (ref "Y2")
      (value "ABMM")
      (footprint "eagle-import:ABMM")
      (fields (field (name "MANUFACTURER") "Abracon LLC") (field (name "MPN") "ABMM-6.000MHZ-B2-T"))
      (libsource (lib "eagle-import") (part "ABMM"))
    )
    (comp (ref "C3")
      (value "22pF")
      (footprint "eagle-import:0402_CAP")
      (description "CAP CER 22PF 50V C0G/NP0 0402")
      (fields (field (name "MANUFACTURER") "Murata") (field (name "MPN") "GRM1555C1H220JA01D"))
      (libsource (lib "eagle-import") (part "CAPACITOR0402_CAP"))
    )
    (comp (ref "C4")
      (value "22pF")
      (footprint "eagle-import:0402_CAP")
      (description "CAP CER 22PF 50V C0G/NP0 0402")
      (fields
        (field (name "DIGIKEY") "490-5868-1-ND")
        (field (name "MANUFACTURER") "Murata")
        (field (name "MPN") "GRM1555C1H220JA01D")
      )
      (libsource (lib "eagle-import") (part "CAPACITOR0402_CAP"))
    )
    (comp (ref "C5")
      (value "22pF")
      (footprint "eagle-import:0402_CAP")
      (description "CAP CER 22PF 50V C0G/NP0 0402")
      (fields
        (field (name "DIGIKEY") "490-5868-1-ND")
        (field (name "MANUFACTURER") "Murata")
        (field (name "MPN") "GRM1555C1H220JA01D")
      )
      (libsource (lib "eagle-import") (part "CAPACITOR0402_CAP"))
    )
    (comp (ref "C6")
      (value "22pF")
      (footprint "eagle-import:0402_CAP")
      (description "CAP CER 22PF 50V C0G/NP0 0402")
      (fields
        (field (name "DIGIKEY") "490-5868-1-ND")
        (field (name "MANUFACTURER") "Murata")
        (field (name "MPN") "GRM1555C1H220JA01D")
      )
      (libsource (lib "eagle-import") (part "CAPACITOR0402_CAP"))
    )
    (comp (ref "C7")
      (value "22pF")
      (footprint "eagle-import:0402_CAP")
      (description "CAP CER 22PF 50V C0G/NP0 0402")
      (fields
        (field (name "DIGIKEY") "490-5868-1-ND")
        (field (name "MANUFACTURER") "Murata")
        (field (name "MPN") "GRM1555C1H220JA01D")
      )
      (libsource (lib "eagle-import") (part "CAPACITOR0402_CAP"))
    )
    (comp (ref "C8")
      (value "22pF")
      (footprint "eagle-import:0402_CAP")
      (description "CAP CER 22PF 50V C0G/NP0 0402")
      (fields
        (field (name "DIGIKEY") "490-5868-1-ND")
        (field (name "MANUFACTURER") "Murata")
        (field (name "MPN") "GRM1555C1H220JA01D")
      )
      (libsource (lib "eagle-import") (part "CAPACITOR0402_CAP"))
    )
    (comp (ref "C35")
      (value "0.1uF")
      (footprint "eagle-import:0603_CAP")
      (description "CAP CER 0.1UF 16V X7R 0603")
      (fields
        (field (name "DIGIKEY") "490-1532-1-ND")
        (field (name "MANUFACTURER") "Murata")
        (field (name "MPN") "GRM188R71C104KA01D")
      )
      (libsource (lib "eagle-import") (part "CAPACITOR0603_CAP"))
    )
    (comp (ref "C36")
      (value "0.1uF")
      (footprint "eagle-import:0603_CAP")
      (description "CAP CER 0.1UF 16V X7R 0603")
      (fields
        (field (name "DIGIKEY") "490-1532-1-ND")
        (field (name "MANUFACTURER") "Murata")
        (field (name "MPN") "GRM188R71C104KA01D")
      )
      (libsource (lib "eagle-import") (part "CAPACITOR0603_CAP"))
    )
    (comp (ref "D35")
      (value "SN75240-TSSOP")
      (footprint "eagle-import:TSSOP-8")
      (fields (field (name "MANUFACTURER") "Texas Instruments") (field (name "MPN") "SN75240PWR"))
      (libsource (lib "eagle-import") (part "SN75240-TSSOP"))
    )
    (comp (ref "D36")
      (value "SN75240-TSSOP")
      (footprint "eagle-import:TSSOP-8")
      (fields (field (name "MANUFACTURER") "Texas Instruments") (field (name "MPN") "SN75240PWR"))
      (libsource (lib "eagle-import") (part "SN75240-TSSOP"))
    )
    (comp (ref "R5")
      (value "27Ω")
      (footprint "eagle-import:0402_RES-HIGH_SPEED")
      (description "RES SMD 27 OHM 5% 1/16W 0402")
      (fields
        (field (name "DIGIKEY") "541-27JCT-ND")
        (field (name "MANUFACTURER") "Vishay Dale")
        (field (name "MPN") "CRCW040227R0JNED")
      )
      (libsource (lib "eagle-import") (part "RESISTOR-HIGH_SPEED0402"))
    )
    (comp (ref "R6")
      (value "27Ω")
      (footprint "eagle-import:0402_RES-HIGH_SPEED")
      (description "RES SMD 27 OHM 5% 1/16W 0402")
      (fields (field (name "MANUFACTURER") "Vishay Dale") (field (name "MPN") "CRCW040227R0JNED"))
      (libsource (lib "eagle-import") (part "RESISTOR-HIGH_SPEED0402"))
    )
    (comp (ref "R7")
      (value "27Ω")
      (footprint "eagle-import:0402_RES-HIGH_SPEED")
      (description "RES SMD 27 OHM 5% 1/16W 0402")
      (fields
        (field (name "DIGIKEY") "541-27JCT-ND")
        (field (name "MANUFACTURER") "Vishay Dale")
        (field (name "MPN") "CRCW040227R0JNED")
      )
      (libsource (lib "eagle-import") (part "RESISTOR-HIGH_SPEED0402"))
    )
    (comp (ref "R8")
      (value "27Ω")
      (footprint "eagle-import:0402_RES-HIGH_SPEED")
      (description "RES SMD 27 OHM 5% 1/16W 0402")
      (fields
        (field (name "DIGIKEY") "541-27JCT-ND")
        (field (name "MANUFACTURER") "Vishay Dale")
        (field (name "MPN") "CRCW040227R0JNED")
      )
      (libsource (lib "eagle-import") (part "RESISTOR-HIGH_SPEED0402"))
    )
    (comp (ref "R9")
      (value "27Ω")
      (footprint "eagle-import:0402_RES-HIGH_SPEED")
      (description "RES SMD 27 OHM 5% 1/16W 0402")
      (fields
        (field (name "DIGIKEY") "541-27JCT-ND")
        (field (name "MANUFACTURER") "Vishay Dale")
        (field (name "MPN") "CRCW040227R0JNED")
      )
      (libsource (lib "eagle-import") (part "RESISTOR-HIGH_SPEED0402"))
    )
    (comp (ref "R10")
      (value "27Ω")
      (footprint "eagle-import:0402_RES-HIGH_SPEED")
      (description "RES SMD 27 OHM 5% 1/16W 0402")
      (fields
        (field (name "DIGIKEY") "541-27JCT-ND")
        (field (name "MANUFACTURER") "Vishay Dale")
        (field (name "MPN") "CRCW040227R0JNED")
      )
      (libsource (lib "eagle-import") (part "RESISTOR-HIGH_SPEED0402"))
    )
    (comp (ref "R11")
      (value "50Ω")
      (footprint "eagle-import:0603-RES")
      (description "RES SMD 49.9 OHM 1% 1/10W 0603")
      (fields (field (name "MANUFACTURER") "Rohm") (field (name "MPN") "TRR03EZPF49R9"))
      (libsource (lib "eagle-import") (part "RESISTOR0603_RES"))
    )
    (comp (ref "R12")
      (value "50Ω")
      (footprint "eagle-import:0603-RES")
      (description "RES SMD 49.9 OHM 1% 1/10W 0603")
      (fields
        (field (name "DIGIKEY") "RHM49.9BJCT-ND")
        (field (name "MANUFACTURER") "Rohm")
        (field (name "MPN") "TRR03EZPF49R9")
      )
      (libsource (lib "eagle-import") (part "RESISTOR0603_RES"))
    )
    (comp (ref "R13")
      (value "50Ω")
      (footprint "eagle-import:0603-RES")
      (description "RES SMD 49.9 OHM 1% 1/10W 0603")
      (fields
        (field (name "DIGIKEY") "RHM49.9BJCT-ND")
        (field (name "MANUFACTURER") "Rohm")
        (field (name "MPN") "TRR03EZPF49R9")
      )
      (libsource (lib "eagle-import") (part "RESISTOR0603_RES"))
    )
    (comp (ref "R14")
      (value "50Ω")
      (footprint "eagle-import:0603-RES")
      (description "RES SMD 49.9 OHM 1% 1/10W 0603")
      (fields
        (field (name "DIGIKEY") "RHM49.9BJCT-ND")
        (field (name "MANUFACTURER") "Rohm")
        (field (name "MPN") "TRR03EZPF49R9")
      )
      (libsource (lib "eagle-import") (part "RESISTOR0603_RES"))
    )
    (comp (ref "R53")
      (value "15kΩ")
      (footprint "eagle-import:0603-RES")
      (description "RES SMD 15K OHM 1% 1/10W 0603")
      (fields (field (name "MANUFACTURER") "Rohm") (field (name "MPN") "MCR03ERTF1502"))
      (libsource (lib "eagle-import") (part "RESISTOR0603_RES"))
    )
    (comp (ref "R54")
      (value "15kΩ")
      (footprint "eagle-import:0603-RES")
      (description "RES SMD 15K OHM 1% 1/10W 0603")
      (fields
        (field (name "DIGIKEY") "RHM15.0KCFCT-ND")
        (field (name "MANUFACTURER") "Rohm")
        (field (name "MPN") "MCR03ERTF1502")
      )
      (libsource (lib "eagle-import") (part "RESISTOR0603_RES"))
    )
    (comp (ref "R55")
      (value "15kΩ")
      (footprint "eagle-import:0603-RES")
      (description "RES SMD 15K OHM 1% 1/10W 0603")
      (fields
        (field (name "DIGIKEY") "RHM15.0KCFCT-ND")
        (field (name "MANUFACTURER") "Rohm")
        (field (name "MPN") "MCR03ERTF1502")
      )
      (libsource (lib "eagle-import") (part "RESISTOR0603_RES"))
    )
    (comp (ref "R56")
      (value "15kΩ")
      (footprint "eagle-import:0603-RES")
      (description "RES SMD 15K OHM 1% 1/10W 0603")
      (fields
        (field (name "DIGIKEY") "RHM15.0KCFCT-ND")
        (field (name "MANUFACTURER") "Rohm")
        (field (name "MPN") "MCR03ERTF1502")
      )
      (libsource (lib "eagle-import") (part "RESISTOR0603_RES"))
    )
    (comp (ref "R57")
      (value "15kΩ")
      (footprint "eagle-import:0603-RES")
      (description "RES SMD 15K OHM 1% 1/10W 0603")
      (fields
        (field (name "DIGIKEY") "RHM15.0KCFCT-ND")
        (field (name "MANUFACTURER") "Rohm")
        (field (name "MPN") "MCR03ERTF1502")
      )
      (libsource (lib "eagle-import") (part "RESISTOR0603_RES"))
    )
    (comp (ref "R58")
      (value "15kΩ")
      (footprint "eagle-import:0603-RES")
      (description "RES SMD 15K OHM 1% 1/10W 0603")
      (fields
        (field (name "DIGIKEY") "RHM15.0KCFCT-ND")
        (field (name "MANUFACTURER") "Rohm")
        (field (name "MPN") "MCR03ERTF1502")
      )
      (libsource (lib "eagle-import") (part "RESISTOR0603_RES"))
    )
    (comp (ref "U28")
      (value "TS3USB30E")
      (footprint "eagle-import:UQFN-10")
      (libsource (lib "eagle-import") (part "TS3USB30E"))
    )
    (comp (ref "U29")
      (value "TS3USB30E")
      (footprint "eagle-import:UQFN-10")
      (libsource (lib "eagle-import") (part "TS3USB30E"))
    )
    (comp (ref "D14")
      (value "LED0603")
      (footprint "eagle-import:LED-0603")
      (description "LED BLUE CLEAR 0603 SMD")
      (fields (field (name "MANUFACTURER") "Lite-On") (field (name "MPN") "LTST-C193TBKT-5A"))
      (libsource (lib "eagle-import") (part "LED0603"))
    )
    (comp (ref "D15")
      (value "LED0603")
      (footprint "eagle-import:LED-0603")
      (description "LED BLUE CLEAR 0603 SMD")
      (fields (field (name "MANUFACTURER") "Lite-On") (field (name "MPN") "LTST-C193TBKT-5A"))
      (libsource (lib "eagle-import") (part "LED0603"))
    )
    (comp (ref "D16")
      (value "LED0603")
      (footprint "eagle-import:LED-0603")
      (description "LED BLUE CLEAR 0603 SMD")
      (fields (field (name "MANUFACTURER") "Lite-On") (field (name "MPN") "LTST-C193TBKT-5A"))
      (libsource (lib "eagle-import") (part "LED0603"))
    )
    (comp (ref "D17")
      (value "LED0603")
      (footprint "eagle-import:LED-0603")
      (description "LED BLUE CLEAR 0603 SMD")
      (fields (field (name "MANUFACTURER") "Lite-On") (field (name "MPN") "LTST-C193TBKT-5A"))
      (libsource (lib "eagle-import") (part "LED0603"))
    )
    (comp (ref "D18")
      (value "LED0603")
      (footprint "eagle-import:LED-0603")
      (description "LED BLUE CLEAR 0603 SMD")
      (fields (field (name "MANUFACTURER") "Lite-On") (field (name "MPN") "LTST-C193TBKT-5A"))
      (libsource (lib "eagle-import") (part "LED0603"))
    )
    (comp (ref "J6")
      (value "ML20")
      (footprint "eagle-import:ML20")
      (libsource (lib "eagle-import") (part "ML20"))
    )
    (comp (ref "R18")
      (value "1kΩ")
      (footprint "eagle-import:ARRAY-CONVEX-0603-4")
      (description "RES ARRAY 4 RES 1K OHM 1206")
      (fields
        (field (name "DIGIKEY") "Y9102CT-ND")
        (field (name "MANUFACTURER") "Panasonic")
        (field (name "MPN") "EXB-38V102JV")
      )
      (libsource (lib "eagle-import") (part "RESISTOR-ARRAY-41206"))
    )
    (comp (ref "R19")
      (value "1kΩ")
      (footprint "eagle-import:ARRAY-CONVEX-0603-4")
      (description "RES ARRAY 4 RES 1K OHM 1206")
      (fields
        (field (name "DIGIKEY") "Y9102CT-ND")
        (field (name "MANUFACTURER") "Panasonic")
        (field (name "MPN") "EXB-38V102JV")
      )
      (libsource (lib "eagle-import") (part "RESISTOR-ARRAY-41206"))
    )
    (comp (ref "R20")
      (value "1kΩ")
      (footprint "eagle-import:ARRAY-CONVEX-0603-4")
      (description "RES ARRAY 4 RES 1K OHM 1206")
      (fields
        (field (name "DIGIKEY") "Y9102CT-ND")
        (field (name "MANUFACTURER") "Panasonic")
        (field (name "MPN") "EXB-38V102JV")
      )
      (libsource (lib "eagle-import") (part "RESISTOR-ARRAY-41206"))
    )
    (comp (ref "R21")
      (value "1kΩ")
      (footprint "eagle-import:ARRAY-CONVEX-0603-4")
      (description "RES ARRAY 4 RES 1K OHM 1206")
      (fields
        (field (name "DIGIKEY") "Y9102CT-ND")
        (field (name "MANUFACTURER") "Panasonic")
        (field (name "MPN") "EXB-38V102JV")
      )
      (libsource (lib "eagle-import") (part "RESISTOR-ARRAY-41206"))
    )
    (comp (ref "S11")
      (value "RM106772BCB")
      (footprint "eagle-import:RM-SWITCH")
      (libsource (lib "eagle-import") (part "RM106772BCB"))
    )
    (comp (ref "S14")
      (value "SN74AHC4066-RGY")
      (footprint "eagle-import:S-PVQFN-N14-3.5MM")
      (libsource (lib "eagle-import") (part "SN74AHC4066-RGY"))
    )
    (comp (ref "S15")
      (value "SN74AHC4066-RGY")
      (footprint "eagle-import:S-PVQFN-N14-3.5MM")
      (libsource (lib "eagle-import") (part "SN74AHC4066-RGY"))
    )
    (comp (ref "S16")
      (value "SN74AHC4066-RGY")
      (footprint "eagle-import:S-PVQFN-N14-3.5MM")
      (libsource (lib "eagle-import") (part "SN74AHC4066-RGY"))
    )
    (comp (ref "S17")
      (value "SN74AHC4066-RGY")
      (footprint "eagle-import:S-PVQFN-N14-3.5MM")
      (libsource (lib "eagle-import") (part "SN74AHC4066-RGY"))
    )
    (comp (ref "S18")
      (value "SN74AHC4066-RGY")
      (footprint "eagle-import:S-PVQFN-N14-3.5MM")
      (libsource (lib "eagle-import") (part "SN74AHC4066-RGY"))
    )
    (comp (ref "S19")
      (value "TE_SSA12/SPDT")
      (footprint "eagle-import:TE_SSA12_SPDT")
      (libsource (lib "eagle-import") (part "TE_SSA12/SPDT"))
    )
    (comp (ref "C9")
      (value "22pF")
      (footprint "eagle-import:0603_CAP")
      (description "CAP CER 22PF 50V C0G/NP0 0603")
      (fields (field (name "MANUFACTURER") "Samsung") (field (name "MPN") "CL10C220JB8NNNC"))
      (libsource (lib "eagle-import") (part "CAPACITOR0603_CAP"))
    )
    (comp (ref "C10")
      (value "22pF")
      (footprint "eagle-import:0603_CAP")
      (description "CAP CER 22PF 50V C0G/NP0 0603")
      (fields (field (name "MANUFACTURER") "Samsung") (field (name "MPN") "CL10C220JB8NNNC"))
      (libsource (lib "eagle-import") (part "CAPACITOR0603_CAP"))
    )
    (comp (ref "C26")
      (value "0.1uF")
      (footprint "eagle-import:0603_CAP")
      (description "CAP CER 0.1UF 16V X7R 0603")
      (fields
        (field (name "DIGIKEY") "490-1532-1-ND")
        (field (name "MANUFACTURER") "Murata")
        (field (name "MPN") "GRM188R71C104KA01D")
      )
      (libsource (lib "eagle-import") (part "CAPACITOR0603_CAP"))
    )
    (comp (ref "C57")
      (value "0.1uF")
      (footprint "eagle-import:0603_CAP")
      (description "CAP CER 0.1UF 16V X7R 0603")
      (fields
        (field (name "DIGIKEY") "490-1532-1-ND")
        (field (name "MANUFACTURER") "Murata")
        (field (name "MPN") "GRM188R71C104KA01D")
      )
      (libsource (lib "eagle-import") (part "CAPACITOR0603_CAP"))
    )
    (comp (ref "C70")
      (value "4.7uF")
      (footprint "eagle-import:0603_CAP")
      (description "CAP CER 4.7UF 6.3V X7R 0603")
      (fields
        (field (name "DIGIKEY") "1276-2087-1-ND")
        (field (name "MANUFACTURER") "Samsung")
        (field (name "MPN") "CL10B475KQ8NQNC")
      )
      (libsource (lib "eagle-import") (part "CAPACITOR0603_CAP"))
    )
    (comp (ref "R27")
      (value "1.5kΩ")
      (footprint "eagle-import:0603-RES")
      (description "RES SMD 1.5K OHM 5% 1/10W 0603")
      (fields (field (name "MANUFACTURER") "Yageo") (field (name "MPN") "RC0603JR-071K5L"))
      (libsource (lib "eagle-import") (part "RESISTOR0603_RES"))
    )
    (comp (ref "R28")
      (value "1.5kΩ")
      (footprint "eagle-import:0603-RES")
      (description "RES SMD 1.5K OHM 5% 1/10W 0603")
      (fields
        (field (name "DIGIKEY") "311-1.5KGRCT-ND")
        (field (name "MANUFACTURER") "Yageo")
        (field (name "MPN") "RC0603JR-071K5L")
      )
      (libsource (lib "eagle-import") (part "RESISTOR0603_RES"))
    )
    (comp (ref "R49")
      (value "10kΩ")
      (footprint "eagle-import:0603-RES")
      (description "RES SMD 10K OHM 5% 1/10W 0603")
      (fields
        (field (name "DIGIKEY") "P10KGCT-ND")
        (field (name "MANUFACTURER") "Panasonic")
        (field (name "MPN") "ERJ-3GEYJ103V")
      )
      (libsource (lib "eagle-import") (part "RESISTOR0603_RES"))
    )
    (comp (ref "R52")
      (value "10kΩ")
      (footprint "eagle-import:0603-RES")
      (description "RES SMD 10K OHM 5% 1/10W 0603")
      (fields
        (field (name "DIGIKEY") "P10KGCT-ND")
        (field (name "MANUFACTURER") "Panasonic")
        (field (name "MPN") "ERJ-3GEYJ103V")
      )
      (libsource (lib "eagle-import") (part "RESISTOR0603_RES"))
    )
    (comp (ref "R61")
      (value "15kΩ")
      (footprint "eagle-import:ARRAY-CONVEX-0603-4")
      (description "RES ARRAY 4 RES 15K OHM 1206")
      (fields
        (field (name "DIGIKEY") "Y9153CT-ND")
        (field (name "MANUFACTURER") "Panasonic")
        (field (name "MPN") "EXB-38V153JV")
      )
      (libsource (lib "eagle-import") (part "RESISTOR-ARRAY-41206"))
    )
    (comp (ref "R62")
      (value "15kΩ")
      (footprint "eagle-import:ARRAY-CONVEX-0603-4")
      (description "RES ARRAY 4 RES 15K OHM 1206")
      (fields
        (field (name "DIGIKEY") "Y9153CT-ND")
        (field (name "MANUFACTURER") "Panasonic")
        (field (name "MPN") "EXB-38V153JV")
      )
      (libsource (lib "eagle-import") (part "RESISTOR-ARRAY-41206"))
    )
    (comp (ref "R63")
      (value "15kΩ")
      (footprint "eagle-import:ARRAY-CONVEX-0603-4")
      (description "RES ARRAY 4 RES 15K OHM 1206")
      (fields
        (field (name "MANUFACTURER") "Panasonic")
        (field (name "MPN") "EXB-38V153JV")
        (field (name "DIGIKEY") "Y9153CT-ND")
      )
      (libsource (lib "eagle-import") (part "RESISTOR-ARRAY-41206"))
    )
    (comp (ref "U19")
      (value "MCP23008QFN")
      (footprint "eagle-import:QFN-20-4MM")
      (libsource (lib "eagle-import") (part "MCP23008QFN"))
    )
    (comp (ref "U21")
      (value "NCP301LSN30")
      (footprint "eagle-import:SOT23-5")
      (libsource (lib "eagle-import") (part "NCP301LSN30"))
    )
    (comp (ref "U31")
      (value "TUSB2077A")
      (footprint "eagle-import:LQFP-48")
      (libsource (lib "eagle-import") (part "TUSB2077A"))
    )
    (comp (ref "Y1")
      (value "ABMM")
      (footprint "eagle-import:ABMM")
      (fields (field (name "MANUFACTURER") "Abracon LLC") (field (name "MPN") "ABMM-6.000MHZ-B2-T"))
      (libsource (lib "eagle-import") (part "ABMM"))
    )
    (comp (ref "H1")
      (value "MOUNT-PAD-ROUND#4")
      (footprint "eagle-import:#4-PAD")
      (libsource (lib "eagle-import") (part "MOUNT-PAD-ROUND#4"))
    )
    (comp (ref "H2")
      (value "MOUNT-PAD-ROUND#4")
      (footprint "eagle-import:#4-PAD")
      (libsource (lib "eagle-import") (part "MOUNT-PAD-ROUND#4"))
    )
    (comp (ref "H3")
      (value "MOUNT-PAD-ROUND#4")
      (footprint "eagle-import:#4-PAD")
      (libsource (lib "eagle-import") (part "MOUNT-PAD-ROUND#4"))
    )
    (comp (ref "H4")
      (value "MOUNT-PAD-ROUND#4")
      (footprint "eagle-import:#4-PAD")
      (libsource (lib "eagle-import") (part "MOUNT-PAD-ROUND#4"))
    )
    (comp (ref "H5")
      (value "MOUNT-PAD-ROUND#4")
      (footprint "eagle-import:#4-PAD")
      (libsource (lib "eagle-import") (part "MOUNT-PAD-ROUND#4"))
    )
    (comp (ref "H6")
      (value "MOUNT-PAD-ROUND#4")
      (footprint "eagle-import:#4-PAD")
      (libsource (lib "eagle-import") (part "MOUNT-PAD-ROUND#4"))
    )
    (comp (ref "H7")
      (value "MOUNT-PAD-ROUND#4")
      (footprint "eagle-import:#4-PAD")
      (libsource (lib "eagle-import") (part "MOUNT-PAD-ROUND#4"))
    )
    (comp (ref "H8")
      (value "MOUNT-PAD-ROUND#4")
      (footprint "eagle-import:#4-PAD")
      (libsource (lib "eagle-import") (part "MOUNT-PAD-ROUND#4"))
    )
    (comp (ref "J1")
      (value "BACKPLANE_CONTROLLER_MODULE_DEBUG")
      (footprint "eagle-import:BACKPLANE_MODULE_20PIN_10PIN_DEBUG")
      (libsource (lib "eagle-import") (part "BACKPLANE_CONTROLLER_MODULE_DEBUG"))
    )
    (comp (ref "JP15")
      (value "FIDUCIAL1X2")
      (footprint "eagle-import:FIDUCIAL-1X2")
      (libsource (lib "eagle-import") (part "FIDUCIAL1X2"))
    )
    (comp (ref "JP21")
      (value "FIDUCIAL1X2")
      (footprint "eagle-import:FIDUCIAL-1X2")
      (libsource (lib "eagle-import") (part "FIDUCIAL1X2"))
    )
    (comp (ref "JP22")
      (value "FIDUCIAL1X2")
      (footprint "eagle-import:FIDUCIAL-1X2")
      (libsource (lib "eagle-import") (part "FIDUCIAL1X2"))
    )
    (comp (ref "JP23")
      (value "FIDUCIAL1X2")
      (footprint "eagle-import:FIDUCIAL-1X2")
      (libsource (lib "eagle-import") (part "FIDUCIAL1X2"))
    )
    (comp (ref "JP24")
      (value "FIDUCIAL1X2")
      (footprint "eagle-import:FIDUCIAL-1X2")
      (libsource (lib "eagle-import") (part "FIDUCIAL1X2"))
    )
    (comp (ref "JP25")
      (value "FIDUCIAL1X2")
      (footprint "eagle-import:FIDUCIAL-1X2")
      (libsource (lib "eagle-import") (part "FIDUCIAL1X2"))
    )
    (comp (ref "R41")
      (value "10kΩ")
      (footprint "eagle-import:0603-RES")
      (description "RES SMD 10K OHM 5% 1/10W 0603")
      (fields
        (field (name "DIGIKEY") "P10KGCT-ND")
        (field (name "MANUFACTURER") "Panasonic")
        (field (name "MPN") "ERJ-3GEYJ103V")
      )
      (libsource (lib "eagle-import") (part "RESISTOR0603_RES"))
    )
    (comp (ref "R42")
      (value "10kΩ")
      (footprint "eagle-import:0603-RES")
      (description "RES SMD 10K OHM 5% 1/10W 0603")
      (fields
        (field (name "DIGIKEY") "P10KGCT-ND")
        (field (name "MANUFACTURER") "Panasonic")
        (field (name "MPN") "ERJ-3GEYJ103V")
      )
      (libsource (lib "eagle-import") (part "RESISTOR0603_RES"))
    )
    (comp (ref "R43")
      (value "10kΩ")
      (footprint "eagle-import:0603-RES")
      (description "RES SMD 10K OHM 5% 1/10W 0603")
      (fields
        (field (name "DIGIKEY") "P10KGCT-ND")
        (field (name "MANUFACTURER") "Panasonic")
        (field (name "MPN") "ERJ-3GEYJ103V")
      )
      (libsource (lib "eagle-import") (part "RESISTOR0603_RES"))
    )
    (comp (ref "R44")
      (value "10kΩ")
      (footprint "eagle-import:0603-RES")
      (description "RES SMD 10K OHM 5% 1/10W 0603")
      (fields
        (field (name "DIGIKEY") "P10KGCT-ND")
        (field (name "MANUFACTURER") "Panasonic")
        (field (name "MPN") "ERJ-3GEYJ103V")
      )
      (libsource (lib "eagle-import") (part "RESISTOR0603_RES"))
    )
    (comp (ref "R45")
      (value "10kΩ")
      (footprint "eagle-import:0603-RES")
      (description "RES SMD 10K OHM 5% 1/10W 0603")
      (fields
        (field (name "DIGIKEY") "P10KGCT-ND")
        (field (name "MANUFACTURER") "Panasonic")
        (field (name "MPN") "ERJ-3GEYJ103V")
      )
      (libsource (lib "eagle-import") (part "RESISTOR0603_RES"))
    )
    (comp (ref "R46")
      (value "10kΩ")
      (footprint "eagle-import:0603-RES")
      (description "RES SMD 10K OHM 5% 1/10W 0603")
      (fields
        (field (name "DIGIKEY") "P10KGCT-ND")
        (field (name "MANUFACTURER") "Panasonic")
        (field (name "MPN") "ERJ-3GEYJ103V")
      )
      (libsource (lib "eagle-import") (part "RESISTOR0603_RES"))
    )
    (comp (ref "S5")
      (value "PTS645SM43SMTR92")
      (footprint "eagle-import:PTS645")
      (libsource (lib "eagle-import") (part "PTS645SM43SMTR92"))
    )
    (comp (ref "S6")
      (value "PTS645SM43SMTR92")
      (footprint "eagle-import:PTS645")
      (libsource (lib "eagle-import") (part "PTS645SM43SMTR92"))
    )
    (comp (ref "SJ4")
      (value "SOLDERJUMPERNC")
      (footprint "eagle-import:SJ_2S")
      (libsource (lib "eagle-import") (part "SOLDERJUMPERNC"))
    )
    (comp (ref "SJ5")
      (value "SOLDERJUMPERNC")
      (footprint "eagle-import:SJ_2S")
      (libsource (lib "eagle-import") (part "SOLDERJUMPERNC"))
    )
    (comp (ref "TP8")
      (value "TEST_POINT_0.040IN")
      (footprint "eagle-import:TESTPOINT_0.040IN")
      (libsource (lib "eagle-import") (part "TEST_POINT_0.040IN"))
    )
    (comp (ref "TP9")
      (value "TEST_POINT_0.040IN")
      (footprint "eagle-import:TESTPOINT_0.040IN")
      (libsource (lib "eagle-import") (part "TEST_POINT_0.040IN"))
    )
    (comp (ref "TP10")
      (value "TEST_POINT_0.040IN")
      (footprint "eagle-import:TESTPOINT_0.040IN")
      (libsource (lib "eagle-import") (part "TEST_POINT_0.040IN"))
    )
    (comp (ref "TP11")
      (value "TEST_POINT_0.040IN")
      (footprint "eagle-import:TESTPOINT_0.040IN")
      (libsource (lib "eagle-import") (part "TEST_POINT_0.040IN"))
    )
    (comp (ref "J2")
      (value "BACKPLANE_GENERIC_MODULE_DEBUG")
      (footprint "eagle-import:BACKPLANE_MODULE_14PIN_8PIN")
      (libsource (lib "eagle-import") (part "BACKPLANE_GENERIC_MODULE_DEBUG"))
    )
    (comp (ref "J3")
      (value "BACKPLANE_GENERIC_MODULE_DEBUG")
      (footprint "eagle-import:BACKPLANE_MODULE_14PIN_8PIN")
      (libsource (lib "eagle-import") (part "BACKPLANE_GENERIC_MODULE_DEBUG"))
    )
    (comp (ref "S3")
      (value "PTS645SM43SMTR92")
      (footprint "eagle-import:PTS645")
      (libsource (lib "eagle-import") (part "PTS645SM43SMTR92"))
    )
    (comp (ref "S4")
      (value "PTS645SM43SMTR92")
      (footprint "eagle-import:PTS645")
      (libsource (lib "eagle-import") (part "PTS645SM43SMTR92"))
    )
    (comp (ref "SJ2")
      (value "SOLDERJUMPERNC")
      (footprint "eagle-import:SJ_2S")
      (libsource (lib "eagle-import") (part "SOLDERJUMPERNC"))
    )
    (comp (ref "SJ3")
      (value "SOLDERJUMPERNC")
      (footprint "eagle-import:SJ_2S")
      (libsource (lib "eagle-import") (part "SOLDERJUMPERNC"))
    )
    (comp (ref "TP4")
      (value "TEST_POINT_0.040IN")
      (footprint "eagle-import:TESTPOINT_0.040IN")
      (libsource (lib "eagle-import") (part "TEST_POINT_0.040IN"))
    )
    (comp (ref "TP5")
      (value "TEST_POINT_0.040IN")
      (footprint "eagle-import:TESTPOINT_0.040IN")
      (libsource (lib "eagle-import") (part "TEST_POINT_0.040IN"))
    )
    (comp (ref "TP6")
      (value "TEST_POINT_0.040IN")
      (footprint "eagle-import:TESTPOINT_0.040IN")
      (libsource (lib "eagle-import") (part "TEST_POINT_0.040IN"))
    )
    (comp (ref "TP7")
      (value "TEST_POINT_0.040IN")
      (footprint "eagle-import:TESTPOINT_0.040IN")
      (libsource (lib "eagle-import") (part "TEST_POINT_0.040IN"))
    )
    (comp (ref "C45")
      (value "0.1uF")
      (footprint "eagle-import:0603_CAP")
      (description "CAP CER 0.1UF 16V X7R 0603")
      (fields
        (field (name "DIGIKEY") "490-1532-1-ND")
        (field (name "MANUFACTURER") "Murata")
        (field (name "MPN") "GRM188R71C104KA01D")
      )
      (libsource (lib "eagle-import") (part "CAPACITOR0603_CAP"))
    )
    (comp (ref "C46")
      (value "0.1uF")
      (footprint "eagle-import:0603_CAP")
      (description "CAP CER 0.1UF 16V X7R 0603")
      (fields
        (field (name "DIGIKEY") "490-1532-1-ND")
        (field (name "MANUFACTURER") "Murata")
        (field (name "MPN") "GRM188R71C104KA01D")
      )
      (libsource (lib "eagle-import") (part "CAPACITOR0603_CAP"))
    )
    (comp (ref "C47")
      (value "0.1uF")
      (footprint "eagle-import:0603_CAP")
      (description "CAP CER 0.1UF 16V X7R 0603")
      (fields
        (field (name "DIGIKEY") "490-1532-1-ND")
        (field (name "MANUFACTURER") "Murata")
        (field (name "MPN") "GRM188R71C104KA01D")
      )
      (libsource (lib "eagle-import") (part "CAPACITOR0603_CAP"))
    )
    (comp (ref "C48")
      (value "0.1uF")
      (footprint "eagle-import:0603_CAP")
      (description "CAP CER 0.1UF 16V X7R 0603")
      (fields
        (field (name "DIGIKEY") "490-1532-1-ND")
        (field (name "MANUFACTURER") "Murata")
        (field (name "MPN") "GRM188R71C104KA01D")
      )
      (libsource (lib "eagle-import") (part "CAPACITOR0603_CAP"))
    )
    (comp (ref "D10")
      (value "LED0603")
      (footprint "eagle-import:LED-0603")
      (description "LED RED CLEAR 0603 SMD")
      (fields (field (name "MANUFACTURER") "Lite-On") (field (name "MPN") "LTST-C191KRKT"))
      (libsource (lib "eagle-import") (part "LED0603"))
    )
    (comp (ref "D11")
      (value "LED0603")
      (footprint "eagle-import:LED-0603")
      (description "LED GREEN CLEAR 0603 SMD")
      (fields (field (name "MANUFACTURER") "Lite-On") (field (name "MPN") "LTST-C191KGKT"))
      (libsource (lib "eagle-import") (part "LED0603"))
    )
    (comp (ref "D12")
      (value "LED0603")
      (footprint "eagle-import:LED-0603")
      (description "LED RED CLEAR 0603 SMD")
      (fields (field (name "MANUFACTURER") "Lite-On") (field (name "MPN") "LTST-C191KRKT"))
      (libsource (lib "eagle-import") (part "LED0603"))
    )
    (comp (ref "D13")
      (value "LED0603")
      (footprint "eagle-import:LED-0603")
      (description "LED GREEN CLEAR 0603 SMD")
      (fields (field (name "MANUFACTURER") "Lite-On") (field (name "MPN") "LTST-C191KGKT"))
      (libsource (lib "eagle-import") (part "LED0603"))
    )
    (comp (ref "Q2")
      (value "DMN32D2LDF")
      (footprint "eagle-import:SOT353")
      (fields (field (name "MANUFACTURER") "Diodes Incorporated") (field (name "MPN") "DMN32D2LDF-7"))
      (libsource (lib "eagle-import") (part "DMN32D2LDF"))
    )
    (comp (ref "Q3")
      (value "DMN32D2LDF")
      (footprint "eagle-import:SOT353")
      (fields (field (name "MANUFACTURER") "Diodes Incorporated") (field (name "MPN") "DMN32D2LDF-7"))
      (libsource (lib "eagle-import") (part "DMN32D2LDF"))
    )
    (comp (ref "R68")
      (value "1MΩ")
      (footprint "eagle-import:0603-RES")
      (description "RES SMD 1M OHM 5% 1/4W 0603")
      (fields (field (name "MANUFACTURER") "Rohm") (field (name "MPN") "ESR03EZPJ105"))
      (libsource (lib "eagle-import") (part "RESISTOR0603_RES"))
    )
    (comp (ref "R69")
      (value "1MΩ")
      (footprint "eagle-import:0603-RES")
      (description "RES SMD 1M OHM 5% 1/4W 0603")
      (fields
        (field (name "DIGIKEY") "RHM1MDCT-ND")
        (field (name "MANUFACTURER") "Rohm")
        (field (name "MPN") "ESR03EZPJ105")
      )
      (libsource (lib "eagle-import") (part "RESISTOR0603_RES"))
    )
    (comp (ref "R70")
      (value "1MΩ")
      (footprint "eagle-import:0603-RES")
      (description "RES SMD 1M OHM 5% 1/4W 0603")
      (fields
        (field (name "DIGIKEY") "RHM1MDCT-ND")
        (field (name "MANUFACTURER") "Rohm")
        (field (name "MPN") "ESR03EZPJ105")
      )
      (libsource (lib "eagle-import") (part "RESISTOR0603_RES"))
    )
    (comp (ref "R71")
      (value "1MΩ")
      (footprint "eagle-import:0603-RES")
      (description "RES SMD 1M OHM 5% 1/4W 0603")
      (fields
        (field (name "DIGIKEY") "RHM1MDCT-ND")
        (field (name "MANUFACTURER") "Rohm")
        (field (name "MPN") "ESR03EZPJ105")
      )
      (libsource (lib "eagle-import") (part "RESISTOR0603_RES"))
    )
    (comp (ref "U2")
      (value "FT232RQ")
      (footprint "eagle-import:QFN32")
      (libsource (lib "eagle-import") (part "FT232RQ"))
    )
    (comp (ref "U3")
      (value "FT232RQ")
      (footprint "eagle-import:QFN32")
      (libsource (lib "eagle-import") (part "FT232RQ"))
    )
    (comp (ref "C14")
      (value "0.1uF")
      (footprint "eagle-import:0603_CAP")
      (description "CAP CER 0.1UF 16V X7R 0603")
      (fields
        (field (name "DIGIKEY") "490-1532-1-ND")
        (field (name "MANUFACTURER") "Murata")
        (field (name "MPN") "GRM188R71C104KA01D")
      )
      (libsource (lib "eagle-import") (part "CAPACITOR0603_CAP"))
    )
    (comp (ref "C15")
      (value "0.1uF")
      (footprint "eagle-import:0603_CAP")
      (description "CAP CER 0.1UF 16V X7R 0603")
      (fields
        (field (name "DIGIKEY") "490-1532-1-ND")
        (field (name "MANUFACTURER") "Murata")
        (field (name "MPN") "GRM188R71C104KA01D")
      )
      (libsource (lib "eagle-import") (part "CAPACITOR0603_CAP"))
    )
    (comp (ref "C16")
      (value "0.1uF")
      (footprint "eagle-import:0603_CAP")
      (description "CAP CER 0.1UF 16V X7R 0603")
      (fields
        (field (name "DIGIKEY") "490-1532-1-ND")
        (field (name "MANUFACTURER") "Murata")
        (field (name "MPN") "GRM188R71C104KA01D")
      )
      (libsource (lib "eagle-import") (part "CAPACITOR0603_CAP"))
    )
    (comp (ref "C17")
      (value "0.1uF")
      (footprint "eagle-import:0603_CAP")
      (description "CAP CER 0.1UF 16V X7R 0603")
      (fields
        (field (name "DIGIKEY") "490-1532-1-ND")
        (field (name "MANUFACTURER") "Murata")
        (field (name "MPN") "GRM188R71C104KA01D")
      )
      (libsource (lib "eagle-import") (part "CAPACITOR0603_CAP"))
    )
    (comp (ref "C37")
      (value "0.1uF")
      (footprint "eagle-import:0603_CAP")
      (description "CAP CER 0.1UF 16V X7R 0603")
      (fields
        (field (name "DIGIKEY") "490-1532-1-ND")
        (field (name "MANUFACTURER") "Murata")
        (field (name "MPN") "GRM188R71C104KA01D")
      )
      (libsource (lib "eagle-import") (part "CAPACITOR0603_CAP"))
    )
    (comp (ref "C38")
      (value "0.1uF")
      (footprint "eagle-import:0603_CAP")
      (description "CAP CER 0.1UF 16V X7R 0603")
      (fields
        (field (name "DIGIKEY") "490-1532-1-ND")
        (field (name "MANUFACTURER") "Murata")
        (field (name "MPN") "GRM188R71C104KA01D")
      )
      (libsource (lib "eagle-import") (part "CAPACITOR0603_CAP"))
    )
    (comp (ref "C68")
      (value "4.7uF")
      (footprint "eagle-import:0603_CAP")
      (description "CAP CER 4.7UF 6.3V X7R 0603")
      (fields (field (name "MANUFACTURER") "Samsung") (field (name "MPN") "CL10B475KQ8NQNC"))
      (libsource (lib "eagle-import") (part "CAPACITOR0603_CAP"))
    )
    (comp (ref "C69")
      (value "4.7uF")
      (footprint "eagle-import:0603_CAP")
      (description "CAP CER 4.7UF 6.3V X7R 0603")
      (fields
        (field (name "DIGIKEY") "1276-2087-1-ND")
        (field (name "MANUFACTURER") "Samsung")
        (field (name "MPN") "CL10B475KQ8NQNC")
      )
      (libsource (lib "eagle-import") (part "CAPACITOR0603_CAP"))
    )
    (comp (ref "R37")
      (value "10kΩ")
      (footprint "eagle-import:0603-RES")
      (description "RES SMD 10K OHM 5% 1/10W 0603")
      (fields
        (field (name "DIGIKEY") "P10KGCT-ND")
        (field (name "MANUFACTURER") "Panasonic")
        (field (name "MPN") "ERJ-3GEYJ103V")
      )
      (libsource (lib "eagle-import") (part "RESISTOR0603_RES"))
    )
    (comp (ref "R38")
      (value "10kΩ")
      (footprint "eagle-import:0603-RES")
      (description "RES SMD 10K OHM 5% 1/10W 0603")
      (fields
        (field (name "DIGIKEY") "P10KGCT-ND")
        (field (name "MANUFACTURER") "Panasonic")
        (field (name "MPN") "ERJ-3GEYJ103V")
      )
      (libsource (lib "eagle-import") (part "RESISTOR0603_RES"))
    )
    (comp (ref "R39")
      (value "10kΩ")
      (footprint "eagle-import:0603-RES")
      (description "RES SMD 10K OHM 5% 1/10W 0603")
      (fields
        (field (name "DIGIKEY") "P10KGCT-ND")
        (field (name "MANUFACTURER") "Panasonic")
        (field (name "MPN") "ERJ-3GEYJ103V")
      )
      (libsource (lib "eagle-import") (part "RESISTOR0603_RES"))
    )
    (comp (ref "R40")
      (value "10kΩ")
      (footprint "eagle-import:0603-RES")
      (description "RES SMD 10K OHM 5% 1/10W 0603")
      (fields
        (field (name "DIGIKEY") "P10KGCT-ND")
        (field (name "MANUFACTURER") "Panasonic")
        (field (name "MPN") "ERJ-3GEYJ103V")
      )
      (libsource (lib "eagle-import") (part "RESISTOR0603_RES"))
    )
    (comp (ref "S12")
      (value "SIP3240X")
      (footprint "eagle-import:TDFN4")
      (libsource (lib "eagle-import") (part "SIP3240X"))
    )
    (comp (ref "S13")
      (value "SIP3240X")
      (footprint "eagle-import:TDFN4")
      (libsource (lib "eagle-import") (part "SIP3240X"))
    )
    (comp (ref "U7")
      (value "FXMA2102")
      (footprint "eagle-import:UMLP-8")
      (libsource (lib "eagle-import") (part "FXMA2102"))
    )
    (comp (ref "U8")
      (value "FXMA2102")
      (footprint "eagle-import:UMLP-8")
      (libsource (lib "eagle-import") (part "FXMA2102"))
    )
    (comp (ref "C62")
      (value "0.1uF")
      (footprint "eagle-import:0603_CAP")
      (description "CAP CER 0.1UF 16V X7R 0603")
      (fields (field (name "MANUFACTURER") "Murata") (field (name "MPN") "GRM188R71C104KA01D"))
      (libsource (lib "eagle-import") (part "CAPACITOR0603_CAP"))
    )
    (comp (ref "J8")
      (value "TC2030-FTDI-I2C")
      (footprint "eagle-import:TC2030-IDC-NL")
      (libsource (lib "eagle-import") (part "TC2030-FTDI-I2C"))
    )
    (comp (ref "SJ1")
      (value "SOLDERJUMPERNO")
      (footprint "eagle-import:SJ_2S-NO")
      (libsource (lib "eagle-import") (part "SOLDERJUMPERNO"))
    )
    (comp (ref "U14")
      (value "M24C01WMN")
      (footprint "eagle-import:SOIC-8")
      (libsource (lib "eagle-import") (part "M24C01WMN"))
    )
    (comp (ref "C49")
      (value "0.1uF")
      (footprint "eagle-import:0603_CAP")
      (description "CAP CER 0.1UF 16V X7R 0603")
      (fields
        (field (name "DIGIKEY") "490-1532-1-ND")
        (field (name "MANUFACTURER") "Murata")
        (field (name "MPN") "GRM188R71C104KA01D")
      )
      (libsource (lib "eagle-import") (part "CAPACITOR0603_CAP"))
    )
    (comp (ref "C50")
      (value "0.1uF")
      (footprint "eagle-import:0603_CAP")
      (description "CAP CER 0.1UF 16V X7R 0603")
      (fields
        (field (name "DIGIKEY") "490-1532-1-ND")
        (field (name "MANUFACTURER") "Murata")
        (field (name "MPN") "GRM188R71C104KA01D")
      )
      (libsource (lib "eagle-import") (part "CAPACITOR0603_CAP"))
    )
    (comp (ref "C51")
      (value "0.1uF")
      (footprint "eagle-import:0603_CAP")
      (description "CAP CER 0.1UF 16V X7R 0603")
      (fields
        (field (name "DIGIKEY") "490-1532-1-ND")
        (field (name "MANUFACTURER") "Murata")
        (field (name "MPN") "GRM188R71C104KA01D")
      )
      (libsource (lib "eagle-import") (part "CAPACITOR0603_CAP"))
    )
    (comp (ref "C52")
      (value "0.1uF")
      (footprint "eagle-import:0603_CAP")
      (description "CAP CER 0.1UF 16V X7R 0603")
      (fields
        (field (name "DIGIKEY") "490-1532-1-ND")
        (field (name "MANUFACTURER") "Murata")
        (field (name "MPN") "GRM188R71C104KA01D")
      )
      (libsource (lib "eagle-import") (part "CAPACITOR0603_CAP"))
    )
    (comp (ref "D19")
      (value "LED0603")
      (footprint "eagle-import:LED-0603")
      (description "LED RED CLEAR 0603 SMD")
      (fields (field (name "MANUFACTURER") "Lite-On") (field (name "MPN") "LTST-C191KRKT"))
      (libsource (lib "eagle-import") (part "LED0603"))
    )
    (comp (ref "D20")
      (value "LED0603")
      (footprint "eagle-import:LED-0603")
      (description "LED GREEN CLEAR 0603 SMD")
      (fields (field (name "MANUFACTURER") "Lite-On") (field (name "MPN") "LTST-C191KGKT"))
      (libsource (lib "eagle-import") (part "LED0603"))
    )
    (comp (ref "D21")
      (value "LED0603")
      (footprint "eagle-import:LED-0603")
      (description "LED RED CLEAR 0603 SMD")
      (fields (field (name "MANUFACTURER") "Lite-On") (field (name "MPN") "LTST-C191KRKT"))
      (libsource (lib "eagle-import") (part "LED0603"))
    )
    (comp (ref "D22")
      (value "LED0603")
      (footprint "eagle-import:LED-0603")
      (description "LED GREEN CLEAR 0603 SMD")
      (fields (field (name "MANUFACTURER") "Lite-On") (field (name "MPN") "LTST-C191KGKT"))
      (libsource (lib "eagle-import") (part "LED0603"))
    )
    (comp (ref "Q4")
      (value "DMN32D2LDF")
      (footprint "eagle-import:SOT353")
      (fields (field (name "MANUFACTURER") "Diodes Incorporated") (field (name "MPN") "DMN32D2LDF-7"))
      (libsource (lib "eagle-import") (part "DMN32D2LDF"))
    )
    (comp (ref "Q5")
      (value "DMN32D2LDF")
      (footprint "eagle-import:SOT353")
      (fields (field (name "MANUFACTURER") "Diodes Incorporated") (field (name "MPN") "DMN32D2LDF-7"))
      (libsource (lib "eagle-import") (part "DMN32D2LDF"))
    )
    (comp (ref "R72")
      (value "1MΩ")
      (footprint "eagle-import:0603-RES")
      (description "RES SMD 1M OHM 5% 1/4W 0603")
      (fields
        (field (name "DIGIKEY") "RHM1MDCT-ND")
        (field (name "MANUFACTURER") "Rohm")
        (field (name "MPN") "ESR03EZPJ105")
      )
      (libsource (lib "eagle-import") (part "RESISTOR0603_RES"))
    )
    (comp (ref "R73")
      (value "1MΩ")
      (footprint "eagle-import:0603-RES")
      (description "RES SMD 1M OHM 5% 1/4W 0603")
      (fields
        (field (name "DIGIKEY") "RHM1MDCT-ND")
        (field (name "MANUFACTURER") "Rohm")
        (field (name "MPN") "ESR03EZPJ105")
      )
      (libsource (lib "eagle-import") (part "RESISTOR0603_RES"))
    )
    (comp (ref "R74")
      (value "1MΩ")
      (footprint "eagle-import:0603-RES")
      (description "RES SMD 1M OHM 5% 1/4W 0603")
      (fields
        (field (name "DIGIKEY") "RHM1MDCT-ND")
        (field (name "MANUFACTURER") "Rohm")
        (field (name "MPN") "ESR03EZPJ105")
      )
      (libsource (lib "eagle-import") (part "RESISTOR0603_RES"))
    )
    (comp (ref "R75")
      (value "1MΩ")
      (footprint "eagle-import:0603-RES")
      (description "RES SMD 1M OHM 5% 1/4W 0603")
      (fields
        (field (name "DIGIKEY") "RHM1MDCT-ND")
        (field (name "MANUFACTURER") "Rohm")
        (field (name "MPN") "ESR03EZPJ105")
      )
      (libsource (lib "eagle-import") (part "RESISTOR0603_RES"))
    )
    (comp (ref "U4")
      (value "FT232RQ")
      (footprint "eagle-import:QFN32")
      (libsource (lib "eagle-import") (part "FT232RQ"))
    )
    (comp (ref "U5")
      (value "FT232RQ")
      (footprint "eagle-import:QFN32")
      (libsource (lib "eagle-import") (part "FT232RQ"))
    )
    (comp (ref "C27")
      (value "0.1uF")
      (footprint "eagle-import:0603_CAP")
      (description "CAP CER 0.1UF 16V X7R 0603")
      (fields
        (field (name "DIGIKEY") "490-1532-1-ND")
        (field (name "MANUFACTURER") "Murata")
        (field (name "MPN") "GRM188R71C104KA01D")
      )
      (libsource (lib "eagle-import") (part "CAPACITOR0603_CAP"))
    )
    (comp (ref "C28")
      (value "0.1uF")
      (footprint "eagle-import:0603_CAP")
      (description "CAP CER 0.1UF 16V X7R 0603")
      (fields
        (field (name "DIGIKEY") "490-1532-1-ND")
        (field (name "MANUFACTURER") "Murata")
        (field (name "MPN") "GRM188R71C104KA01D")
      )
      (libsource (lib "eagle-import") (part "CAPACITOR0603_CAP"))
    )
    (comp (ref "D26")
      (value "LED0603")
      (footprint "eagle-import:LED-0603")
      (description "LED BLUE CLEAR 0603 SMD")
      (fields (field (name "MANUFACTURER") "Lite-On") (field (name "MPN") "LTST-C193TBKT-5A"))
      (libsource (lib "eagle-import") (part "LED0603"))
    )
    (comp (ref "D27")
      (value "LED0603")
      (footprint "eagle-import:LED-0603")
      (description "LED BLUE CLEAR 0603 SMD")
      (fields (field (name "MANUFACTURER") "Lite-On") (field (name "MPN") "LTST-C193TBKT-5A"))
      (libsource (lib "eagle-import") (part "LED0603"))
    )
    (comp (ref "D28")
      (value "LED0603")
      (footprint "eagle-import:LED-0603")
      (description "LED BLUE CLEAR 0603 SMD")
      (fields (field (name "MANUFACTURER") "Lite-On") (field (name "MPN") "LTST-C193TBKT-5A"))
      (libsource (lib "eagle-import") (part "LED0603"))
    )
    (comp (ref "D29")
      (value "LED0603")
      (footprint "eagle-import:LED-0603")
      (description "LED BLUE CLEAR 0603 SMD")
      (fields (field (name "MANUFACTURER") "Lite-On") (field (name "MPN") "LTST-C193TBKT-5A"))
      (libsource (lib "eagle-import") (part "LED0603"))
    )
    (comp (ref "D30")
      (value "LED0603")
      (footprint "eagle-import:LED-0603")
      (description "LED BLUE CLEAR 0603 SMD")
      (fields (field (name "MANUFACTURER") "Lite-On") (field (name "MPN") "LTST-C193TBKT-5A"))
      (libsource (lib "eagle-import") (part "LED0603"))
    )
    (comp (ref "D31")
      (value "LED0603")
      (footprint "eagle-import:LED-0603")
      (description "LED BLUE CLEAR 0603 SMD")
      (fields (field (name "MANUFACTURER") "Lite-On") (field (name "MPN") "LTST-C193TBKT-5A"))
      (libsource (lib "eagle-import") (part "LED0603"))
    )
    (comp (ref "D32")
      (value "LED0603")
      (footprint "eagle-import:LED-0603")
      (description "LED BLUE CLEAR 0603 SMD")
      (fields (field (name "MANUFACTURER") "Lite-On") (field (name "MPN") "LTST-C193TBKT-5A"))
      (libsource (lib "eagle-import") (part "LED0603"))
    )
    (comp (ref "D33")
      (value "LED0603")
      (footprint "eagle-import:LED-0603")
      (description "LED BLUE CLEAR 0603 SMD")
      (fields (field (name "MANUFACTURER") "Lite-On") (field (name "MPN") "LTST-C193TBKT-5A"))
      (libsource (lib "eagle-import") (part "LED0603"))
    )
    (comp (ref "R25")
      (value "1kΩ")
      (footprint "eagle-import:ARRAY-CONVEX-0603-4")
      (description "RES ARRAY 4 RES 1K OHM 1206")
      (fields
        (field (name "MANUFACTURER") "Panasonic")
        (field (name "MPN") "EXB-38V102JV")
        (field (name "DIGIKEY") "Y9102CT-ND")
      )
      (libsource (lib "eagle-import") (part "RESISTOR-ARRAY-41206"))
    )
    (comp (ref "R26")
      (value "1kΩ")
      (footprint "eagle-import:ARRAY-CONVEX-0603-4")
      (description "RES ARRAY 4 RES 1K OHM 1206")
      (fields
        (field (name "MANUFACTURER") "Panasonic")
        (field (name "MPN") "EXB-38V102JV")
        (field (name "DIGIKEY") "Y9102CT-ND")
      )
      (libsource (lib "eagle-import") (part "RESISTOR-ARRAY-41206"))
    )
    (comp (ref "R78")
      (value "10MΩ")
      (footprint "eagle-import:0603-RES")
      (description "RES SMD 10M OHM 5% 1/4W 0603")
      (fields (field (name "MANUFACTURER") "Rohm") (field (name "MPN") "ESR03EZPJ106"))
      (libsource (lib "eagle-import") (part "RESISTOR0603_RES"))
    )
    (comp (ref "R79")
      (value "10MΩ")
      (footprint "eagle-import:0603-RES")
      (description "RES SMD 10M OHM 5% 1/4W 0603")
      (fields
        (field (name "DIGIKEY") "RHM10MDCT-ND")
        (field (name "MANUFACTURER") "Rohm")
        (field (name "MPN") "ESR03EZPJ106")
      )
      (libsource (lib "eagle-import") (part "RESISTOR0603_RES"))
    )
    (comp (ref "R80")
      (value "10MΩ")
      (footprint "eagle-import:0603-RES")
      (description "RES SMD 10M OHM 5% 1/4W 0603")
      (fields
        (field (name "DIGIKEY") "RHM10MDCT-ND")
        (field (name "MANUFACTURER") "Rohm")
        (field (name "MPN") "ESR03EZPJ106")
      )
      (libsource (lib "eagle-import") (part "RESISTOR0603_RES"))
    )
    (comp (ref "R81")
      (value "10MΩ")
      (footprint "eagle-import:0603-RES")
      (description "RES SMD 10M OHM 5% 1/4W 0603")
      (fields
        (field (name "DIGIKEY") "RHM10MDCT-ND")
        (field (name "MANUFACTURER") "Rohm")
        (field (name "MPN") "ESR03EZPJ106")
      )
      (libsource (lib "eagle-import") (part "RESISTOR0603_RES"))
    )
    (comp (ref "R82")
      (value "10MΩ")
      (footprint "eagle-import:0603-RES")
      (description "RES SMD 10M OHM 5% 1/4W 0603")
      (fields
        (field (name "DIGIKEY") "RHM10MDCT-ND")
        (field (name "MANUFACTURER") "Rohm")
        (field (name "MPN") "ESR03EZPJ106")
      )
      (libsource (lib "eagle-import") (part "RESISTOR0603_RES"))
    )
    (comp (ref "R83")
      (value "10MΩ")
      (footprint "eagle-import:0603-RES")
      (description "RES SMD 10M OHM 5% 1/4W 0603")
      (fields
        (field (name "DIGIKEY") "RHM10MDCT-ND")
        (field (name "MANUFACTURER") "Rohm")
        (field (name "MPN") "ESR03EZPJ106")
      )
      (libsource (lib "eagle-import") (part "RESISTOR0603_RES"))
    )
    (comp (ref "S21")
      (value "MMS42")
      (footprint "eagle-import:MMS42")
      (libsource (lib "eagle-import") (part "MMS42"))
    )
    (comp (ref "S22")
      (value "MMS42")
      (footprint "eagle-import:MMS42")
      (libsource (lib "eagle-import") (part "MMS42"))
    )
    (comp (ref "U17")
      (value "MCP23008QFN")
      (footprint "eagle-import:QFN-20-4MM")
      (libsource (lib "eagle-import") (part "MCP23008QFN"))
    )
    (comp (ref "U18")
      (value "MCP23008QFN")
      (footprint "eagle-import:QFN-20-4MM")
      (libsource (lib "eagle-import") (part "MCP23008QFN"))
    )
    (comp (ref "D4")
      (value "LED0603")
      (footprint "eagle-import:LED-0603")
      (description "LED GREEN CLEAR 0603 SMD")
      (fields (field (name "MANUFACTURER") "Lite-On") (field (name "MPN") "LTST-C191KGKT"))
      (libsource (lib "eagle-import") (part "LED0603"))
    )
    (comp (ref "D5")
      (value "LED0603")
      (footprint "eagle-import:LED-0603")
      (description "LED GREEN CLEAR 0603 SMD")
      (fields (field (name "MANUFACTURER") "Lite-On") (field (name "MPN") "LTST-C191KGKT"))
      (libsource (lib "eagle-import") (part "LED0603"))
    )
    (comp (ref "D6")
      (value "LED0603")
      (footprint "eagle-import:LED-0603")
      (description "LED GREEN CLEAR 0603 SMD")
      (fields (field (name "MANUFACTURER") "Lite-On") (field (name "MPN") "LTST-C191KGKT"))
      (libsource (lib "eagle-import") (part "LED0603"))
    )
    (comp (ref "D7")
      (value "LED0603")
      (footprint "eagle-import:LED-0603")
      (description "LED GREEN CLEAR 0603 SMD")
      (fields (field (name "MANUFACTURER") "Lite-On") (field (name "MPN") "LTST-C191KGKT"))
      (libsource (lib "eagle-import") (part "LED0603"))
    )
    (comp (ref "D8")
      (value "LED0603")
      (footprint "eagle-import:LED-0603")
      (description "LED GREEN CLEAR 0603 SMD")
      (fields (field (name "MANUFACTURER") "Lite-On") (field (name "MPN") "LTST-C191KGKT"))
      (libsource (lib "eagle-import") (part "LED0603"))
    )
    (comp (ref "D9")
      (value "LED0603")
      (footprint "eagle-import:LED-0603")
      (description "LED GREEN CLEAR 0603 SMD")
      (fields (field (name "MANUFACTURER") "Lite-On") (field (name "MPN") "LTST-C191KGKT"))
      (libsource (lib "eagle-import") (part "LED0603"))
    )
    (comp (ref "JP1")
      (value "PINHD-2X5")
      (footprint "eagle-import:2X05")
      (libsource (lib "eagle-import") (part "PINHD-2X5"))
    )
    (comp (ref "JP2")
      (value "PINHD-2X5")
      (footprint "eagle-import:2X05")
      (libsource (lib "eagle-import") (part "PINHD-2X5"))
    )
    (comp (ref "JP3")
      (value "PINHD-2X3")
      (footprint "eagle-import:2X03")
      (libsource (lib "eagle-import") (part "PINHD-2X3"))
    )
    (comp (ref "JP4")
      (value "PINHD-2X5")
      (footprint "eagle-import:2X05")
      (libsource (lib "eagle-import") (part "PINHD-2X5"))
    )
    (comp (ref "JP5")
      (value "PINHD-2X5")
      (footprint "eagle-import:2X05")
      (libsource (lib "eagle-import") (part "PINHD-2X5"))
    )
    (comp (ref "JP6")
      (value "PINHD-2X3")
      (footprint "eagle-import:2X03")
      (libsource (lib "eagle-import") (part "PINHD-2X3"))
    )
    (comp (ref "JP7")
      (value "PINHD-2X3")
      (footprint "eagle-import:2X03")
      (libsource (lib "eagle-import") (part "PINHD-2X3"))
    )
    (comp (ref "JP8")
      (value "PINHD-2X3")
      (footprint "eagle-import:2X03")
      (libsource (lib "eagle-import") (part "PINHD-2X3"))
    )
    (comp (ref "JP9")
      (value "PINHD-2X3")
      (footprint "eagle-import:2X03")
      (libsource (lib "eagle-import") (part "PINHD-2X3"))
    )
    (comp (ref "JP10")
      (value "PINHD-2X3")
      (footprint "eagle-import:2X03")
      (libsource (lib "eagle-import") (part "PINHD-2X3"))
    )
    (comp (ref "JP11")
      (value "PINHD-2X5")
      (footprint "eagle-import:2X05")
      (libsource (lib "eagle-import") (part "PINHD-2X5"))
    )
    (comp (ref "JP12")
      (value "PINHD-2X10")
      (footprint "eagle-import:2X10")
      (libsource (lib "eagle-import") (part "PINHD-2X10"))
    )
    (comp (ref "JP13")
      (value "PINHD-1X2")
      (footprint "eagle-import:1X02")
      (libsource (lib "eagle-import") (part "PINHD-1X2"))
    )
    (comp (ref "JP14")
      (value "PINHD-2X3")
      (footprint "eagle-import:2X03")
      (libsource (lib "eagle-import") (part "PINHD-2X3"))
    )
    (comp (ref "JP16")
      (value "PINHD-2X4")
      (footprint "eagle-import:2X04")
      (libsource (lib "eagle-import") (part "PINHD-2X4"))
    )
    (comp (ref "JP17")
      (value "PINHD-1X3")
      (footprint "eagle-import:1X03")
      (libsource (lib "eagle-import") (part "PINHD-1X3"))
    )
    (comp (ref "JP18")
      (value "PINHD-1X3")
      (footprint "eagle-import:1X03")
      (libsource (lib "eagle-import") (part "PINHD-1X3"))
    )
    (comp (ref "JP19")
      (value "PINHD-2X10")
      (footprint "eagle-import:2X10")
      (libsource (lib "eagle-import") (part "PINHD-2X10"))
    )
    (comp (ref "JP20")
      (value "PINHD-2X10")
      (footprint "eagle-import:2X10")
      (libsource (lib "eagle-import") (part "PINHD-2X10"))
    )
    (comp (ref "R23")
      (value "1kΩ")
      (footprint "eagle-import:ARRAY-CONVEX-0603-4")
      (description "RES ARRAY 4 RES 1K OHM 1206")
      (fields
        (field (name "DIGIKEY") "Y9102CT-ND")
        (field (name "MANUFACTURER") "Panasonic")
        (field (name "MPN") "EXB-38V102JV")
      )
      (libsource (lib "eagle-import") (part "RESISTOR-ARRAY-41206"))
    )
    (comp (ref "R24")
      (value "1kΩ")
      (footprint "eagle-import:ARRAY-CONVEX-0603-4")
      (description "RES ARRAY 4 RES 1K OHM 1206")
      (fields
        (field (name "DIGIKEY") "Y9102CT-ND")
        (field (name "MANUFACTURER") "Panasonic")
        (field (name "MPN") "EXB-38V102JV")
      )
      (libsource (lib "eagle-import") (part "RESISTOR-ARRAY-41206"))
    )
  )
  (nets
    (net (code "1") (name "3V3_UNMETERED") (class "Default")
      (node (ref "C40") (pin "1") (pinfunction "1_1") (pintype "bidirectional"))
      (node (ref "C41") (pin "1") (pinfunction "1_1") (pintype "bidirectional"))
      (node (ref "C42") (pin "1") (pinfunction "1_1") (pintype "bidirectional"))
      (node (ref "C53") (pin "2") (pinfunction "2_2") (pintype "bidirectional"))
      (node (ref "C54") (pin "2") (pinfunction "2_2") (pintype "bidirectional"))
      (node (ref "C67") (pin "1") (pinfunction "1_1") (pintype "bidirectional"))
      (node (ref "C72") (pin "2") (pinfunction "2_2") (pintype "bidirectional"))
      (node (ref "D10") (pin "A") (pinfunction "ANODE_A") (pintype "bidirectional"))
      (node (ref "D11") (pin "A") (pinfunction "ANODE_A") (pintype "bidirectional"))
      (node (ref "D12") (pin "A") (pinfunction "ANODE_A") (pintype "bidirectional"))
      (node (ref "D13") (pin "A") (pinfunction "ANODE_A") (pintype "bidirectional"))
      (node (ref "D19") (pin "A") (pinfunction "ANODE_A") (pintype "bidirectional"))
      (node (ref "D20") (pin "A") (pinfunction "ANODE_A") (pintype "bidirectional"))
      (node (ref "D21") (pin "A") (pinfunction "ANODE_A") (pintype "bidirectional"))
      (node (ref "D22") (pin "A") (pinfunction "ANODE_A") (pintype "bidirectional"))
      (node (ref "D24") (pin "A") (pinfunction "ANODE_A") (pintype "bidirectional"))
      (node (ref "D25") (pin "A") (pinfunction "ANODE_A") (pintype "bidirectional"))
      (node (ref "D34") (pin "A") (pinfunction "ANODE_A") (pintype "bidirectional"))
      (node (ref "FB1") (pin "2") (pinfunction "P$2_2") (pintype "bidirectional"))
      (node (ref "JP11") (pin "3") (pinfunction "3_3") (pintype "passive"))
      (node (ref "JP16") (pin "2") (pinfunction "2_2") (pintype "passive"))
      (node (ref "R1") (pin "2") (pinfunction "2_2") (pintype "passive"))
      (node (ref "R31") (pin "A2") (pinfunction "2_A2") (pintype "passive"))
      (node (ref "R31") (pin "B2") (pinfunction "2_B2") (pintype "passive"))
      (node (ref "R31") (pin "C2") (pinfunction "2_C2") (pintype "passive"))
      (node (ref "R50") (pin "2") (pinfunction "2_2") (pintype "passive"))
      (node (ref "R51") (pin "2") (pinfunction "2_2") (pintype "passive"))
      (node (ref "R64") (pin "2") (pinfunction "2_2") (pintype "passive"))
      (node (ref "R65") (pin "2") (pinfunction "2_2") (pintype "passive"))
      (node (ref "R66") (pin "2") (pinfunction "2_2") (pintype "passive"))
      (node (ref "R84") (pin "2") (pinfunction "2_2") (pintype "passive"))
      (node (ref "S11") (pin "C") (pinfunction "INPUT_C") (pintype "bidirectional"))
      (node (ref "S14") (pin "14") (pinfunction "VCC_14") (pintype "bidirectional"))
      (node (ref "S15") (pin "14") (pinfunction "VCC_14") (pintype "bidirectional"))
      (node (ref "S16") (pin "10") (pinfunction "A_10") (pintype "bidirectional"))
      (node (ref "S16") (pin "14") (pinfunction "VCC_14") (pintype "bidirectional"))
      (node (ref "S17") (pin "10") (pinfunction "A_10") (pintype "bidirectional"))
      (node (ref "S17") (pin "14") (pinfunction "VCC_14") (pintype "bidirectional"))
      (node (ref "S18") (pin "10") (pinfunction "A_10") (pintype "bidirectional"))
      (node (ref "S18") (pin "14") (pinfunction "VCC_14") (pintype "bidirectional"))
      (node (ref "S21") (pin "B1") (pinfunction "1TB_B1") (pintype "bidirectional"))
      (node (ref "S21") (pin "B2") (pinfunction "2TB_B2") (pintype "bidirectional"))
      (node (ref "S21") (pin "B3") (pinfunction "3TB_B3") (pintype "bidirectional"))
      (node (ref "S21") (pin "B4") (pinfunction "4TB_B4") (pintype "bidirectional"))
      (node (ref "S22") (pin "B1") (pinfunction "1TB_B1") (pintype "bidirectional"))
      (node (ref "S22") (pin "B2") (pinfunction "2TB_B2") (pintype "bidirectional"))
      (node (ref "S22") (pin "B3") (pinfunction "3TB_B3") (pintype "bidirectional"))
      (node (ref "S22") (pin "B4") (pinfunction "4TB_B4") (pintype "bidirectional"))
      (node (ref "U1") (pin "1") (pinfunction "VCCIO_1") (pintype "power_in"))
      (node (ref "U15") (pin "5") (pinfunction "WDS_5") (pintype "bidirectional"))
      (node (ref "U15") (pin "8") (pinfunction "VCC_8") (pintype "bidirectional"))
      (node (ref "U16") (pin "5") (pinfunction "OUT_5") (pintype "bidirectional"))
      (node (ref "U20") (pin "2") (pinfunction "VCC_2") (pintype "bidirectional"))
      (node (ref "U23") (pin "27") (pinfunction "VLCD_27") (pintype "bidirectional"))
      (node (ref "U23") (pin "31") (pinfunction "VLCDIN_31") (pintype "power_in"))
      (node (ref "U23") (pin "40") (pinfunction "VDDIO_40") (pintype "power_in"))
      (node (ref "U23") (pin "45") (pinfunction "VDDIO_45") (pintype "power_in"))
      (node (ref "U23") (pin "8") (pinfunction "VDDIN_8") (pintype "power_in"))
      (node (ref "U30") (pin "9") (pinfunction "VCC_9") (pintype "bidirectional"))
      (node (ref "U32") (pin "10") (pinfunction "~{BUSPWR}_10") (pintype "bidirectional"))
      (node (ref "U32") (pin "46") (pinfunction "VCC_46") (pintype "bidirectional"))
      (node (ref "U32") (pin "47") (pinfunction "~{EXTMEM}_47") (pintype "bidirectional"))
      (node (ref "U32") (pin "9") (pinfunction "VCC_9") (pintype "bidirectional"))
      (node (ref "U6") (pin "1") (pinfunction "VCCIO_1") (pintype "power_in"))
      (node (ref "U9") (pin "1") (pinfunction "SENSE+_1") (pintype "open_collector"))
    )
    (net (code "2") (name "5V_UNMETERED") (class "Default")
      (node (ref "C43") (pin "1") (pinfunction "1_1") (pintype "bidirectional"))
      (node (ref "C46") (pin "1") (pinfunction "1_1") (pintype "bidirectional"))
      (node (ref "C48") (pin "1") (pinfunction "1_1") (pintype "bidirectional"))
      (node (ref "C50") (pin "1") (pinfunction "1_1") (pintype "bidirectional"))
      (node (ref "C52") (pin "1") (pinfunction "1_1") (pintype "bidirectional"))
      (node (ref "C55") (pin "1") (pinfunction "1_1") (pintype "bidirectional"))
      (node (ref "C66") (pin "1") (pinfunction "1_1") (pintype "bidirectional"))
      (node (ref "C71") (pin "1") (pinfunction "1_1") (pintype "bidirectional"))
      (node (ref "D23") (pin "A") (pinfunction "ANODE_A") (pintype "bidirectional"))
      (node (ref "JP11") (pin "1") (pinfunction "1_1") (pintype "passive"))
      (node (ref "JP16") (pin "1") (pinfunction "1_1") (pintype "passive"))
      (node (ref "Q8") (pin "2") (pinfunction "S_2") (pintype "passive"))
      (node (ref "R2") (pin "2") (pinfunction "2_2") (pintype "passive"))
      (node (ref "R3") (pin "2") (pinfunction "2_2") (pintype "passive"))
      (node (ref "R32") (pin "A2") (pinfunction "2_A2") (pintype "passive"))
      (node (ref "R32") (pin "B2") (pinfunction "2_B2") (pintype "passive"))
      (node (ref "R32") (pin "C2") (pinfunction "2_C2") (pintype "passive"))
      (node (ref "R33") (pin "A2") (pinfunction "2_A2") (pintype "passive"))
      (node (ref "R33") (pin "B2") (pinfunction "2_B2") (pintype "passive"))
      (node (ref "R33") (pin "C2") (pinfunction "2_C2") (pintype "passive"))
      (node (ref "R34") (pin "A2") (pinfunction "2_A2") (pintype "passive"))
      (node (ref "R34") (pin "B2") (pinfunction "2_B2") (pintype "passive"))
      (node (ref "R34") (pin "C2") (pinfunction "2_C2") (pintype "passive"))
      (node (ref "R4") (pin "2") (pinfunction "2_2") (pintype "passive"))
      (node (ref "R47") (pin "2") (pinfunction "2_2") (pintype "passive"))
      (node (ref "U1") (pin "19") (pinfunction "VCC_19") (pintype "power_in"))
      (node (ref "U10") (pin "P1") (pinfunction "SENSE+_P1") (pintype "open_collector"))
      (node (ref "U11") (pin "P1") (pinfunction "SENSE+_P1") (pintype "open_collector"))
      (node (ref "U12") (pin "P1") (pinfunction "SENSE+_P1") (pintype "open_collector"))
      (node (ref "U13") (pin "7") (pinfunction "OUT_7") (pintype "bidirectional"))
      (node (ref "U16") (pin "1") (pinfunction "IN_1") (pintype "bidirectional"))
      (node (ref "U2") (pin "19") (pinfunction "VCC_19") (pintype "power_in"))
      (node (ref "U3") (pin "19") (pinfunction "VCC_19") (pintype "power_in"))
      (node (ref "U4") (pin "19") (pinfunction "VCC_19") (pintype "power_in"))
      (node (ref "U5") (pin "19") (pinfunction "VCC_19") (pintype "power_in"))
      (node (ref "U6") (pin "19") (pinfunction "VCC_19") (pintype "power_in"))
    )
    (net (code "3") (name "CONT0_DBG_GPIO1") (class "Default")
      (node (ref "J1") (pin "101") (pinfunction "DBG_GPIO1_101") (pintype "bidirectional"))
      (node (ref "JP9") (pin "5") (pinfunction "5_5") (pintype "passive"))
      (node (ref "Q4") (pin "G1") (pinfunction "G1_G1") (pintype "input"))
      (node (ref "R72") (pin "2") (pinfunction "2_2") (pintype "passive"))
    )
    (net (code "4") (name "CONT0_DBG_GPIO2") (class "Default")
      (node (ref "J1") (pin "104") (pinfunction "DBG_GPIO2_104") (pintype "bidirectional"))
      (node (ref "JP9") (pin "2") (pinfunction "2_2") (pintype "passive"))
      (node (ref "Q4") (pin "G2") (pinfunction "G2_G2") (pintype "input"))
      (node (ref "R73") (pin "2") (pinfunction "2_2") (pintype "passive"))
    )
    (net (code "5") (name "CONT0_DBG_RX") (class "Default")
      (node (ref "J1") (pin "103") (pinfunction "DBG_RX_103") (pintype "bidirectional"))
      (node (ref "JP9") (pin "3") (pinfunction "3_3") (pintype "passive"))
      (node (ref "U4") (pin "30") (pinfunction "TXD_30") (pintype "output"))
    )
    (net (code "6") (name "CONT0_DBG_TX") (class "Default")
      (node (ref "J1") (pin "102") (pinfunction "DBG_TX_102") (pintype "bidirectional"))
      (node (ref "JP9") (pin "4") (pinfunction "4_4") (pintype "passive"))
      (node (ref "U4") (pin "2") (pinfunction "RXD_2") (pintype "input"))
    )
    (net (code "7") (name "CONT0_SWDCLK") (class "Default")
      (node (ref "J1") (pin "106") (pinfunction "DBG_SWDCLK_106") (pintype "bidirectional"))
      (node (ref "S16") (pin "3") (pinfunction "A_3") (pintype "bidirectional"))
    )
    (net (code "8") (name "CONT0_SWDIO") (class "Default")
      (node (ref "J1") (pin "107") (pinfunction "DBG_SWDIO_107") (pintype "bidirectional"))
      (node (ref "S16") (pin "2") (pinfunction "A_2") (pintype "bidirectional"))
    )
    (net (code "9") (name "CONT0_~{RESET}") (class "Default")
      (node (ref "D1") (pin "3A") (pinfunction "ANODE_3A") (pintype "bidirectional"))
      (node (ref "J1") (pin "105") (pinfunction "DBG_~{RESET}_105") (pintype "bidirectional"))
      (node (ref "JP9") (pin "1") (pinfunction "1_1") (pintype "passive"))
      (node (ref "S16") (pin "9") (pinfunction "A_9") (pintype "bidirectional"))
      (node (ref "S5") (pin "3") (pinfunction "P$2_3") (pintype "passive"))
      (node (ref "S5") (pin "4") (pinfunction "P$2_4") (pintype "passive"))
    )
    (net (code "10") (name "CONT1_DBG_GPIO1") (class "Default")
      (node (ref "J1") (pin "201") (pinfunction "DBG_GPIO1_201") (pintype "bidirectional"))
      (node (ref "JP10") (pin "5") (pinfunction "5_5") (pintype "passive"))
      (node (ref "Q5") (pin "G1") (pinfunction "G1_G1") (pintype "input"))
      (node (ref "R74") (pin "2") (pinfunction "2_2") (pintype "passive"))
    )
    (net (code "11") (name "CONT1_DBG_GPIO2") (class "Default")
      (node (ref "J1") (pin "204") (pinfunction "DBG_GPIO2_204") (pintype "bidirectional"))
      (node (ref "JP10") (pin "2") (pinfunction "2_2") (pintype "passive"))
      (node (ref "Q5") (pin "G2") (pinfunction "G2_G2") (pintype "input"))
      (node (ref "R75") (pin "2") (pinfunction "2_2") (pintype "passive"))
    )
    (net (code "12") (name "CONT1_DBG_RX") (class "Default")
      (node (ref "J1") (pin "203") (pinfunction "DBG_RX_203") (pintype "bidirectional"))
      (node (ref "JP10") (pin "3") (pinfunction "3_3") (pintype "passive"))
      (node (ref "U5") (pin "30") (pinfunction "TXD_30") (pintype "output"))
    )
    (net (code "13") (name "CONT1_DBG_TX") (class "Default")
      (node (ref "J1") (pin "202") (pinfunction "DBG_TX_202") (pintype "bidirectional"))
      (node (ref "JP10") (pin "4") (pinfunction "4_4") (pintype "passive"))
      (node (ref "U5") (pin "2") (pinfunction "RXD_2") (pintype "input"))
    )
    (net (code "14") (name "CONT1_SWDCLK") (class "Default")
      (node (ref "J1") (pin "206") (pinfunction "DBG_SWDCLK_206") (pintype "bidirectional"))
      (node (ref "S17") (pin "3") (pinfunction "A_3") (pintype "bidirectional"))
    )
    (net (code "15") (name "CONT1_SWDIO") (class "Default")
      (node (ref "J1") (pin "207") (pinfunction "DBG_SWDIO_207") (pintype "bidirectional"))
      (node (ref "S17") (pin "2") (pinfunction "A_2") (pintype "bidirectional"))
    )
    (net (code "16") (name "CONT1_~{RESET}") (class "Default")
      (node (ref "D1") (pin "4A") (pinfunction "ANODE_4A") (pintype "bidirectional"))
      (node (ref "J1") (pin "205") (pinfunction "DBG_~{RESET}_205") (pintype "bidirectional"))
      (node (ref "JP10") (pin "1") (pinfunction "1_1") (pintype "passive"))
      (node (ref "S17") (pin "9") (pinfunction "A_9") (pintype "bidirectional"))
      (node (ref "S6") (pin "3") (pinfunction "P$2_3") (pintype "passive"))
      (node (ref "S6") (pin "4") (pinfunction "P$2_4") (pintype "passive"))
    )
    (net (code "17") (name "CONT_HDR_BOT_RSV_PIN6") (class "Default")
      (node (ref "JP14") (pin "6") (pinfunction "6_6") (pintype "passive"))
    )
    (net (code "18") (name "CONT_HDR_BOT_RSV_PIN9") (class "Default")
      (node (ref "JP13") (pin "1") (pinfunction "1_1") (pintype "passive"))
    )
    (net (code "19") (name "CONT_HDR_BOT_RSV_PIN10") (class "Default")
      (node (ref "JP13") (pin "2") (pinfunction "2_2") (pintype "passive"))
    )
    (net (code "20") (name "CONT_HDR_TOP_RSV_PIN8") (class "Default")
      (node (ref "JP12") (pin "8") (pinfunction "8_8") (pintype "passive"))
    )
    (net (code "21") (name "CONT_MOD0_IN") (class "Default")
      (node (ref "J1") (pin "9") (pinfunction "MOD0_IN_9") (pintype "bidirectional"))
      (node (ref "JP12") (pin "9") (pinfunction "9_9") (pintype "passive"))
      (node (ref "U24") (pin "2") (pinfunction "A1_2") (pintype "bidirectional"))
    )
    (net (code "22") (name "CONT_MOD0_OUT") (class "Default")
      (node (ref "J1") (pin "10") (pinfunction "MOD0_OUT_10") (pintype "bidirectional"))
      (node (ref "JP12") (pin "10") (pinfunction "10_10") (pintype "passive"))
      (node (ref "U26") (pin "2") (pinfunction "A1_2") (pintype "bidirectional"))
    )
    (net (code "23") (name "CONT_MOD1_IN") (class "Default")
      (node (ref "J1") (pin "11") (pinfunction "MOD1_IN_11") (pintype "bidirectional"))
      (node (ref "JP12") (pin "11") (pinfunction "11_11") (pintype "passive"))
      (node (ref "U25") (pin "2") (pinfunction "A1_2") (pintype "bidirectional"))
    )
    (net (code "24") (name "CONT_MOD1_OUT") (class "Default")
      (node (ref "J1") (pin "12") (pinfunction "MOD1_OUT_12") (pintype "bidirectional"))
      (node (ref "JP12") (pin "12") (pinfunction "12_12") (pintype "passive"))
      (node (ref "U27") (pin "2") (pinfunction "A1_2") (pintype "bidirectional"))
    )
    (net (code "25") (name "CONT_MOD2_IN") (class "Default")
      (node (ref "J1") (pin "13") (pinfunction "MOD2_IN_13") (pintype "bidirectional"))
      (node (ref "JP12") (pin "13") (pinfunction "13_13") (pintype "passive"))
      (node (ref "U23") (pin "39") (pinfunction "PA20_39") (pintype "bidirectional"))
    )
    (net (code "26") (name "CONT_MOD2_OUT") (class "Default")
      (node (ref "J1") (pin "14") (pinfunction "MOD2_OUT_14") (pintype "bidirectional"))
      (node (ref "JP12") (pin "14") (pinfunction "14_14") (pintype "passive"))
      (node (ref "U23") (pin "38") (pinfunction "PA19_38") (pintype "bidirectional"))
    )
    (net (code "27") (name "CONT_MOD5_IN") (class "Default")
      (node (ref "J1") (pin "15") (pinfunction "MOD5_IN_15") (pintype "bidirectional"))
      (node (ref "JP12") (pin "15") (pinfunction "15_15") (pintype "passive"))
    )
    (net (code "28") (name "CONT_MOD5_OUT") (class "Default")
      (node (ref "J1") (pin "16") (pinfunction "MOD5_OUT_16") (pintype "bidirectional"))
      (node (ref "JP12") (pin "16") (pinfunction "16_16") (pintype "passive"))
    )
    (net (code "29") (name "CONT_MOD6_IN") (class "Default")
      (node (ref "J1") (pin "17") (pinfunction "MOD6_IN_17") (pintype "bidirectional"))
      (node (ref "JP12") (pin "17") (pinfunction "17_17") (pintype "passive"))
    )
    (net (code "30") (name "CONT_MOD6_OUT") (class "Default")
      (node (ref "J1") (pin "18") (pinfunction "MOD6_OUT_18") (pintype "bidirectional"))
      (node (ref "JP12") (pin "18") (pinfunction "18_18") (pintype "passive"))
    )
    (net (code "31") (name "CONT_MOD7_IN") (class "Default")
      (node (ref "J1") (pin "19") (pinfunction "MOD7_IN_19") (pintype "bidirectional"))
      (node (ref "JP12") (pin "19") (pinfunction "19_19") (pintype "passive"))
    )
    (net (code "32") (name "CONT_MOD7_OUT") (class "Default")
      (node (ref "J1") (pin "20") (pinfunction "MOD7_OUT_20") (pintype "bidirectional"))
      (node (ref "JP12") (pin "20") (pinfunction "20_20") (pintype "passive"))
    )
    (net (code "33") (name "CONT_USB+") (class "Default")
      (node (ref "J1") (pin "27") (pinfunction "USB_D+_27") (pintype "bidirectional"))
      (node (ref "U30") (pin "6") (pinfunction "D2-_6") (pintype "bidirectional"))
    )
    (net (code "34") (name "CONT_USB-") (class "Default")
      (node (ref "J1") (pin "28") (pinfunction "USB_D-_28") (pintype "bidirectional"))
      (node (ref "U30") (pin "2") (pinfunction "D2+_2") (pintype "bidirectional"))
    )
    (net (code "35") (name "DBG_USB_DM0") (class "Default")
      (node (ref "J5") (pin "2") (pinfunction "D-_2") (pintype "bidirectional"))
      (node (ref "U32") (pin "4") (pinfunction "DM0_4") (pintype "bidirectional"))
    )
    (net (code "36") (name "DBG_USB_DM1") (class "Default")
      (node (ref "U32") (pin "13") (pinfunction "DM1_13") (pintype "bidirectional"))
      (node (ref "U6") (pin "15") (pinfunction "USBDM_15") (pintype "bidirectional"))
    )
    (net (code "37") (name "DBG_USB_DM2") (class "Default")
      (node (ref "U1") (pin "15") (pinfunction "USBDM_15") (pintype "bidirectional"))
      (node (ref "U32") (pin "17") (pinfunction "DM2_17") (pintype "bidirectional"))
    )
    (net (code "38") (name "DBG_USB_DM3") (class "Default")
      (node (ref "U32") (pin "21") (pinfunction "DM3_21") (pintype "bidirectional"))
      (node (ref "U5") (pin "15") (pinfunction "USBDM_15") (pintype "bidirectional"))
    )
    (net (code "39") (name "DBG_USB_DM4") (class "Default")
      (node (ref "U32") (pin "26") (pinfunction "DM4_26") (pintype "bidirectional"))
      (node (ref "U4") (pin "15") (pinfunction "USBDM_15") (pintype "bidirectional"))
    )
    (net (code "40") (name "DBG_USB_DM5") (class "Default")
      (node (ref "R60") (pin "1") (pinfunction "1_1") (pintype "passive"))
      (node (ref "U32") (pin "30") (pinfunction "DM5_30") (pintype "bidirectional"))
    )
    (net (code "41") (name "DBG_USB_DM6") (class "Default")
      (node (ref "U3") (pin "15") (pinfunction "USBDM_15") (pintype "bidirectional"))
      (node (ref "U32") (pin "34") (pinfunction "DM6_34") (pintype "bidirectional"))
    )
    (net (code "42") (name "DBG_USB_DM7") (class "Default")
      (node (ref "U2") (pin "15") (pinfunction "USBDM_15") (pintype "bidirectional"))
      (node (ref "U32") (pin "38") (pinfunction "DM7_38") (pintype "bidirectional"))
    )
    (net (code "43") (name "DBG_USB_DP0") (class "Default")
      (node (ref "J5") (pin "3") (pinfunction "D+_3") (pintype "bidirectional"))
      (node (ref "R29") (pin "1") (pinfunction "1_1") (pintype "passive"))
      (node (ref "U32") (pin "3") (pinfunction "DP0_3") (pintype "bidirectional"))
    )
    (net (code "44") (name "DBG_USB_DP1") (class "Default")
      (node (ref "U32") (pin "14") (pinfunction "DP1_14") (pintype "bidirectional"))
      (node (ref "U6") (pin "14") (pinfunction "USBDP_14") (pintype "bidirectional"))
    )
    (net (code "45") (name "DBG_USB_DP2") (class "Default")
      (node (ref "U1") (pin "14") (pinfunction "USBDP_14") (pintype "bidirectional"))
      (node (ref "U32") (pin "18") (pinfunction "DP2_18") (pintype "bidirectional"))
    )
    (net (code "46") (name "DBG_USB_DP3") (class "Default")
      (node (ref "U32") (pin "22") (pinfunction "DP3_22") (pintype "bidirectional"))
      (node (ref "U5") (pin "14") (pinfunction "USBDP_14") (pintype "bidirectional"))
    )
    (net (code "47") (name "DBG_USB_DP4") (class "Default")
      (node (ref "U32") (pin "27") (pinfunction "DP4_27") (pintype "bidirectional"))
      (node (ref "U4") (pin "14") (pinfunction "USBDP_14") (pintype "bidirectional"))
    )
    (net (code "48") (name "DBG_USB_DP5") (class "Default")
      (node (ref "R59") (pin "1") (pinfunction "1_1") (pintype "passive"))
      (node (ref "U32") (pin "31") (pinfunction "DP5_31") (pintype "bidirectional"))
    )
    (net (code "49") (name "DBG_USB_DP6") (class "Default")
      (node (ref "U3") (pin "14") (pinfunction "USBDP_14") (pintype "bidirectional"))
      (node (ref "U32") (pin "35") (pinfunction "DP6_35") (pintype "bidirectional"))
    )
    (net (code "50") (name "DBG_USB_DP7") (class "Default")
      (node (ref "U2") (pin "14") (pinfunction "USBDP_14") (pintype "bidirectional"))
      (node (ref "U32") (pin "39") (pinfunction "DP7_39") (pintype "bidirectional"))
    )
    (net (code "51") (name "DBG_USB_HUBCFG") (class "Default")
      (node (ref "TP1") (pin "TESTPOINT") (pinfunction "TESTPOINT_TESTPOINT") (pintype "bidirectional"))
      (node (ref "U32") (pin "40") (pinfunction "HUBCFG_40") (pintype "bidirectional"))
    )
    (net (code "52") (name "DBG_USB_PORTDIS") (class "Default")
      (node (ref "TP3") (pin "TESTPOINT") (pinfunction "TESTPOINT_TESTPOINT") (pintype "bidirectional"))
      (node (ref "U32") (pin "42") (pinfunction "PORTDIS_42") (pintype "bidirectional"))
    )
    (net (code "53") (name "DBG_USB_PORTPWR") (class "Default")
      (node (ref "TP2") (pin "TESTPOINT") (pinfunction "TESTPOINT_TESTPOINT") (pintype "bidirectional"))
      (node (ref "U32") (pin "41") (pinfunction "PORTPWR_41") (pintype "bidirectional"))
    )
    (net (code "54") (name "DEBUG_HUB_~{OVRCURX}") (class "Default")
      (node (ref "R50") (pin "1") (pinfunction "1_1") (pintype "passive"))
      (node (ref "U32") (pin "12") (pinfunction "~{OVRCUR1}_12") (pintype "bidirectional"))
      (node (ref "U32") (pin "16") (pinfunction "~{OVRCUR2}_16") (pintype "bidirectional"))
      (node (ref "U32") (pin "20") (pinfunction "~{OVRCUR3}_20") (pintype "bidirectional"))
      (node (ref "U32") (pin "25") (pinfunction "~{OVRCUR4}_25") (pintype "bidirectional"))
      (node (ref "U32") (pin "29") (pinfunction "~{OVRCUR5}_29") (pintype "bidirectional"))
      (node (ref "U32") (pin "33") (pinfunction "~{OVRCUR6}_33") (pintype "bidirectional"))
      (node (ref "U32") (pin "37") (pinfunction "~{OVRCUR7}_37") (pintype "bidirectional"))
    )
    (net (code "55") (name "FAKE_RADIO_XIN") (class "Default")
      (node (ref "C1") (pin "1") (pinfunction "1_1") (pintype "bidirectional"))
      (node (ref "U23") (pin "1") (pinfunction "PA00_1") (pintype "bidirectional"))
      (node (ref "Y3") (pin "3") (pinfunction "2_3") (pintype "bidirectional"))
    )
    (net (code "56") (name "FAKE_RADIO_XOUT") (class "Default")
      (node (ref "C2") (pin "1") (pinfunction "1_1") (pintype "bidirectional"))
      (node (ref "U23") (pin "2") (pinfunction "PA01_2") (pintype "bidirectional"))
      (node (ref "Y3") (pin "1") (pinfunction "1_1") (pintype "bidirectional"))
    )
    (net (code "57") (name "FTDI_~{RESET}") (class "Default")
      (node (ref "D2") (pin "3A") (pinfunction "ANODE_3A") (pintype "bidirectional"))
      (node (ref "U1") (pin "18") (pinfunction "~{RESET}_18") (pintype "input"))
      (node (ref "U2") (pin "18") (pinfunction "~{RESET}_18") (pintype "input"))
      (node (ref "U3") (pin "18") (pinfunction "~{RESET}_18") (pintype "input"))
      (node (ref "U4") (pin "18") (pinfunction "~{RESET}_18") (pintype "input"))
      (node (ref "U5") (pin "18") (pinfunction "~{RESET}_18") (pintype "input"))
      (node (ref "U6") (pin "18") (pinfunction "~{RESET}_18") (pintype "input"))
    )
    (net (code "58") (name "GND") (class "Default")
      (node (ref "C1") (pin "2") (pinfunction "2_2") (pintype "bidirectional"))
      (node (ref "C10") (pin "1") (pinfunction "1_1") (pintype "bidirectional"))
      (node (ref "C11") (pin "1") (pinfunction "1_1") (pintype "bidirectional"))
      (node (ref "C12") (pin "1") (pinfunction "1_1") (pintype "bidirectional"))
      (node (ref "C13") (pin "2") (pinfunction "2_2") (pintype "bidirectional"))
      (node (ref "C14") (pin "2") (pinfunction "2_2") (pintype "bidirectional"))
      (node (ref "C15") (pin "2") (pinfunction "2_2") (pintype "bidirectional"))
      (node (ref "C16") (pin "2") (pinfunction "2_2") (pintype "bidirectional"))
      (node (ref "C17") (pin "2") (pinfunction "2_2") (pintype "bidirectional"))
      (node (ref "C18") (pin "2") (pinfunction "2_2") (pintype "bidirectional"))
      (node (ref "C19") (pin "2") (pinfunction "2_2") (pintype "bidirectional"))
      (node (ref "C2") (pin "2") (pinfunction "2_2") (pintype "bidirectional"))
      (node (ref "C20") (pin "2") (pinfunction "2_2") (pintype "bidirectional"))
      (node (ref "C21") (pin "2") (pinfunction "2_2") (pintype "bidirectional"))
      (node (ref "C22") (pin "2") (pinfunction "2_2") (pintype "bidirectional"))
      (node (ref "C23") (pin "2") (pinfunction "2_2") (pintype "bidirectional"))
      (node (ref "C24") (pin "2") (pinfunction "2_2") (pintype "bidirectional"))
      (node (ref "C25") (pin "2") (pinfunction "2_2") (pintype "bidirectional"))
      (node (ref "C26") (pin "1") (pinfunction "1_1") (pintype "bidirectional"))
      (node (ref "C27") (pin "2") (pinfunction "2_2") (pintype "bidirectional"))
      (node (ref "C28") (pin "2") (pinfunction "2_2") (pintype "bidirectional"))
      (node (ref "C29") (pin "2") (pinfunction "2_2") (pintype "bidirectional"))
      (node (ref "C3") (pin "2") (pinfunction "2_2") (pintype "bidirectional"))
      (node (ref "C30") (pin "2") (pinfunction "2_2") (pintype "bidirectional"))
      (node (ref "C31") (pin "2") (pinfunction "2_2") (pintype "bidirectional"))
      (node (ref "C32") (pin "2") (pinfunction "2_2") (pintype "bidirectional"))
      (node (ref "C33") (pin "2") (pinfunction "2_2") (pintype "bidirectional"))
      (node (ref "C34") (pin "2") (pinfunction "2_2") (pintype "bidirectional"))
      (node (ref "C35") (pin "1") (pinfunction "1_1") (pintype "bidirectional"))
      (node (ref "C36") (pin "1") (pinfunction "1_1") (pintype "bidirectional"))
      (node (ref "C37") (pin "2") (pinfunction "2_2") (pintype "bidirectional"))
      (node (ref "C38") (pin "2") (pinfunction "2_2") (pintype "bidirectional"))
      (node (ref "C39") (pin "2") (pinfunction "2_2") (pintype "bidirectional"))
      (node (ref "C4") (pin "2") (pinfunction "2_2") (pintype "bidirectional"))
      (node (ref "C40") (pin "2") (pinfunction "2_2") (pintype "bidirectional"))
      (node (ref "C41") (pin "2") (pinfunction "2_2") (pintype "bidirectional"))
      (node (ref "C42") (pin "2") (pinfunction "2_2") (pintype "bidirectional"))
      (node (ref "C43") (pin "2") (pinfunction "2_2") (pintype "bidirectional"))
      (node (ref "C44") (pin "2") (pinfunction "2_2") (pintype "bidirectional"))
      (node (ref "C45") (pin "2") (pinfunction "2_2") (pintype "bidirectional"))
      (node (ref "C46") (pin "2") (pinfunction "2_2") (pintype "bidirectional"))
      (node (ref "C47") (pin "2") (pinfunction "2_2") (pintype "bidirectional"))
      (node (ref "C48") (pin "2") (pinfunction "2_2") (pintype "bidirectional"))
      (node (ref "C49") (pin "2") (pinfunction "2_2") (pintype "bidirectional"))
      (node (ref "C5") (pin "2") (pinfunction "2_2") (pintype "bidirectional"))
      (node (ref "C50") (pin "2") (pinfunction "2_2") (pintype "bidirectional"))
      (node (ref "C51") (pin "2") (pinfunction "2_2") (pintype "bidirectional"))
      (node (ref "C52") (pin "2") (pinfunction "2_2") (pintype "bidirectional"))
      (node (ref "C53") (pin "1") (pinfunction "1_1") (pintype "bidirectional"))
      (node (ref "C54") (pin "1") (pinfunction "1_1") (pintype "bidirectional"))
      (node (ref "C55") (pin "2") (pinfunction "2_2") (pintype "bidirectional"))
      (node (ref "C56") (pin "2") (pinfunction "2_2") (pintype "bidirectional"))
      (node (ref "C57") (pin "2") (pinfunction "2_2") (pintype "bidirectional"))
      (node (ref "C58") (pin "2") (pinfunction "2_2") (pintype "bidirectional"))
      (node (ref "C59") (pin "2") (pinfunction "2_2") (pintype "bidirectional"))
      (node (ref "C6") (pin "2") (pinfunction "2_2") (pintype "bidirectional"))
      (node (ref "C60") (pin "2") (pinfunction "2_2") (pintype "bidirectional"))
      (node (ref "C61") (pin "2") (pinfunction "2_2") (pintype "bidirectional"))
      (node (ref "C62") (pin "2") (pinfunction "2_2") (pintype "bidirectional"))
      (node (ref "C63") (pin "2") (pinfunction "2_2") (pintype "bidirectional"))
      (node (ref "C64") (pin "2") (pinfunction "2_2") (pintype "bidirectional"))
      (node (ref "C65") (pin "2") (pinfunction "2_2") (pintype "bidirectional"))
      (node (ref "C66") (pin "2") (pinfunction "2_2") (pintype "bidirectional"))
      (node (ref "C67") (pin "2") (pinfunction "2_2") (pintype "bidirectional"))
      (node (ref "C68") (pin "2") (pinfunction "2_2") (pintype "bidirectional"))
      (node (ref "C69") (pin "2") (pinfunction "2_2") (pintype "bidirectional"))
      (node (ref "C7") (pin "2") (pinfunction "2_2") (pintype "bidirectional"))
      (node (ref "C70") (pin "1") (pinfunction "1_1") (pintype "bidirectional"))
      (node (ref "C71") (pin "2") (pinfunction "2_2") (pintype "bidirectional"))
      (node (ref "C72") (pin "1") (pinfunction "1_1") (pintype "bidirectional"))
      (node (ref "C73") (pin "2") (pinfunction "2_2") (pintype "bidirectional"))
      (node (ref "C74") (pin "2") (pinfunction "2_2") (pintype "bidirectional"))
      (node (ref "C75") (pin "2") (pinfunction "2_2") (pintype "bidirectional"))
      (node (ref "C8") (pin "2") (pinfunction "2_2") (pintype "bidirectional"))
      (node (ref "C9") (pin "1") (pinfunction "1_1") (pintype "bidirectional"))
      (node (ref "D35") (pin "1") (pinfunction "GND_1") (pintype "bidirectional"))
      (node (ref "D35") (pin "3") (pinfunction "GND_3") (pintype "bidirectional"))
      (node (ref "D35") (pin "5") (pinfunction "GND_5") (pintype "bidirectional"))
      (node (ref "D35") (pin "7") (pinfunction "GND_7") (pintype "bidirectional"))
      (node (ref "D36") (pin "1") (pinfunction "GND_1") (pintype "bidirectional"))
      (node (ref "D36") (pin "3") (pinfunction "GND_3") (pintype "bidirectional"))
      (node (ref "D36") (pin "5") (pinfunction "GND_5") (pintype "bidirectional"))
      (node (ref "D36") (pin "7") (pinfunction "GND_7") (pintype "bidirectional"))
      (node (ref "H1") (pin "B#4") (pinfunction "MOUNT_B#4") (pintype "passive"))
      (node (ref "H2") (pin "B#4") (pinfunction "MOUNT_B#4") (pintype "passive"))
      (node (ref "H3") (pin "B#4") (pinfunction "MOUNT_B#4") (pintype "passive"))
      (node (ref "H4") (pin "B#4") (pinfunction "MOUNT_B#4") (pintype "passive"))
      (node (ref "H5") (pin "B#4") (pinfunction "MOUNT_B#4") (pintype "passive"))
      (node (ref "H6") (pin "B#4") (pinfunction "MOUNT_B#4") (pintype "passive"))
      (node (ref "H7") (pin "B#4") (pinfunction "MOUNT_B#4") (pintype "passive"))
      (node (ref "H8") (pin "B#4") (pinfunction "MOUNT_B#4") (pintype "passive"))
      (node (ref "J1") (pin "1") (pinfunction "GND_1") (pintype "bidirectional"))
      (node (ref "J1") (pin "100") (pinfunction "GND1_100") (pintype "bidirectional"))
      (node (ref "J1") (pin "200") (pinfunction "GND1_200") (pintype "bidirectional"))
      (node (ref "J1") (pin "21") (pinfunction "GND_21") (pintype "bidirectional"))
      (node (ref "J1") (pin "MNT1") (pinfunction "GND_MNT1") (pintype "bidirectional"))
      (node (ref "J1") (pin "MNT2") (pinfunction "GND_MNT2") (pintype "bidirectional"))
      (node (ref "J1") (pin "MNT3") (pinfunction "GND_MNT3") (pintype "bidirectional"))
      (node (ref "J1") (pin "MNT4") (pinfunction "GND_MNT4") (pintype "bidirectional"))
      (node (ref "J2") (pin "1") (pinfunction "GND_1") (pintype "bidirectional"))
      (node (ref "J2") (pin "14") (pinfunction "GND_14") (pintype "bidirectional"))
      (node (ref "J2") (pin "15") (pinfunction "GND_15") (pintype "bidirectional"))
      (node (ref "J2") (pin "MNT1") (pinfunction "GND_MNT1") (pintype "bidirectional"))
      (node (ref "J2") (pin "MNT2") (pinfunction "GND_MNT2") (pintype "bidirectional"))
      (node (ref "J2") (pin "MNT3") (pinfunction "GND_MNT3") (pintype "bidirectional"))
      (node (ref "J2") (pin "MNT4") (pinfunction "GND_MNT4") (pintype "bidirectional"))
      (node (ref "J3") (pin "1") (pinfunction "GND_1") (pintype "bidirectional"))
      (node (ref "J3") (pin "14") (pinfunction "GND_14") (pintype "bidirectional"))
      (node (ref "J3") (pin "15") (pinfunction "GND_15") (pintype "bidirectional"))
      (node (ref "J3") (pin "MNT1") (pinfunction "GND_MNT1") (pintype "bidirectional"))
      (node (ref "J3") (pin "MNT2") (pinfunction "GND_MNT2") (pintype "bidirectional"))
      (node (ref "J3") (pin "MNT3") (pinfunction "GND_MNT3") (pintype "bidirectional"))
      (node (ref "J3") (pin "MNT4") (pinfunction "GND_MNT4") (pintype "bidirectional"))
      (node (ref "J4") (pin "5") (pinfunction "GND_5") (pintype "bidirectional"))
      (node (ref "J5") (pin "5") (pinfunction "GND_5") (pintype "bidirectional"))
      (node (ref "J6") (pin "10") (pinfunction "10_10") (pintype "passive"))
      (node (ref "J6") (pin "12") (pinfunction "12_12") (pintype "passive"))
      (node (ref "J6") (pin "14") (pinfunction "14_14") (pintype "passive"))
      (node (ref "J6") (pin "16") (pinfunction "16_16") (pintype "passive"))
      (node (ref "J6") (pin "18") (pinfunction "18_18") (pintype "passive"))
      (node (ref "J6") (pin "20") (pinfunction "20_20") (pintype "passive"))
      (node (ref "J6") (pin "4") (pinfunction "4_4") (pintype "passive"))
      (node (ref "J6") (pin "6") (pinfunction "6_6") (pintype "passive"))
      (node (ref "J6") (pin "8") (pinfunction "8_8") (pintype "passive"))
      (node (ref "J7") (pin "2") (pinfunction "GND_2") (pintype "bidirectional"))
      (node (ref "J8") (pin "3") (pinfunction "GND_3") (pintype "bidirectional"))
      (node (ref "JP1") (pin "2") (pinfunction "2_2") (pintype "passive"))
      (node (ref "JP1") (pin "9") (pinfunction "9_9") (pintype "passive"))
      (node (ref "JP10") (pin "6") (pinfunction "6_6") (pintype "passive"))
      (node (ref "JP11") (pin "2") (pinfunction "2_2") (pintype "passive"))
      (node (ref "JP11") (pin "9") (pinfunction "9_9") (pintype "passive"))
      (node (ref "JP12") (pin "1") (pinfunction "1_1") (pintype "passive"))
      (node (ref "JP14") (pin "1") (pinfunction "1_1") (pintype "passive"))
      (node (ref "JP16") (pin "7") (pinfunction "7_7") (pintype "passive"))
      (node (ref "JP16") (pin "8") (pinfunction "8_8") (pintype "passive"))
      (node (ref "JP19") (pin "19") (pinfunction "19_19") (pintype "passive"))
      (node (ref "JP2") (pin "2") (pinfunction "2_2") (pintype "passive"))
      (node (ref "JP2") (pin "9") (pinfunction "9_9") (pintype "passive"))
      (node (ref "JP20") (pin "19") (pinfunction "19_19") (pintype "passive"))
      (node (ref "JP3") (pin "6") (pinfunction "6_6") (pintype "passive"))
      (node (ref "JP4") (pin "1") (pinfunction "1_1") (pintype "passive"))
      (node (ref "JP5") (pin "1") (pinfunction "1_1") (pintype "passive"))
      (node (ref "JP6") (pin "6") (pinfunction "6_6") (pintype "passive"))
      (node (ref "JP9") (pin "6") (pinfunction "6_6") (pintype "passive"))
      (node (ref "Q1") (pin "S") (pinfunction "S_S") (pintype "bidirectional"))
      (node (ref "Q2") (pin "S") (pinfunction "S_S") (pintype "bidirectional"))
      (node (ref "Q3") (pin "S") (pinfunction "S_S") (pintype "bidirectional"))
      (node (ref "Q4") (pin "S") (pinfunction "S_S") (pintype "bidirectional"))
      (node (ref "Q5") (pin "S") (pinfunction "S_S") (pintype "bidirectional"))
      (node (ref "Q6") (pin "S") (pinfunction "S_S") (pintype "bidirectional"))
      (node (ref "Q7") (pin "S") (pinfunction "S_S") (pintype "bidirectional"))
      (node (ref "R11") (pin "2") (pinfunction "2_2") (pintype "passive"))
      (node (ref "R12") (pin "2") (pinfunction "2_2") (pintype "passive"))
      (node (ref "R13") (pin "2") (pinfunction "2_2") (pintype "passive"))
      (node (ref "R14") (pin "2") (pinfunction "2_2") (pintype "passive"))
      (node (ref "R18") (pin "C1") (pinfunction "1_C1") (pintype "passive"))
      (node (ref "R18") (pin "D1") (pinfunction "1_D1") (pintype "passive"))
      (node (ref "R19") (pin "C1") (pinfunction "1_C1") (pintype "passive"))
      (node (ref "R19") (pin "D1") (pinfunction "1_D1") (pintype "passive"))
      (node (ref "R20") (pin "C1") (pinfunction "1_C1") (pintype "passive"))
      (node (ref "R20") (pin "D1") (pinfunction "1_D1") (pintype "passive"))
      (node (ref "R21") (pin "C1") (pinfunction "1_C1") (pintype "passive"))
      (node (ref "R21") (pin "D1") (pinfunction "1_D1") (pintype "passive"))
      (node (ref "R22") (pin "C1") (pinfunction "1_C1") (pintype "passive"))
      (node (ref "R22") (pin "D1") (pinfunction "1_D1") (pintype "passive"))
      (node (ref "R23") (pin "A1") (pinfunction "1_A1") (pintype "passive"))
      (node (ref "R23") (pin "B1") (pinfunction "1_B1") (pintype "passive"))
      (node (ref "R23") (pin "C1") (pinfunction "1_C1") (pintype "passive"))
      (node (ref "R24") (pin "A1") (pinfunction "1_A1") (pintype "passive"))
      (node (ref "R24") (pin "B1") (pinfunction "1_B1") (pintype "passive"))
      (node (ref "R24") (pin "C1") (pinfunction "1_C1") (pintype "passive"))
      (node (ref "R25") (pin "A2") (pinfunction "2_A2") (pintype "passive"))
      (node (ref "R25") (pin "B2") (pinfunction "2_B2") (pintype "passive"))
      (node (ref "R25") (pin "C2") (pinfunction "2_C2") (pintype "passive"))
      (node (ref "R25") (pin "D2") (pinfunction "2_D2") (pintype "passive"))
      (node (ref "R26") (pin "A2") (pinfunction "2_A2") (pintype "passive"))
      (node (ref "R26") (pin "B2") (pinfunction "2_B2") (pintype "passive"))
      (node (ref "R26") (pin "C2") (pinfunction "2_C2") (pintype "passive"))
      (node (ref "R26") (pin "D2") (pinfunction "2_D2") (pintype "passive"))
      (node (ref "R48") (pin "1") (pinfunction "1_1") (pintype "passive"))
      (node (ref "R53") (pin "1") (pinfunction "1_1") (pintype "passive"))
      (node (ref "R54") (pin "1") (pinfunction "1_1") (pintype "passive"))
      (node (ref "R55") (pin "1") (pinfunction "1_1") (pintype "passive"))
      (node (ref "R56") (pin "1") (pinfunction "1_1") (pintype "passive"))
      (node (ref "R57") (pin "1") (pinfunction "1_1") (pintype "passive"))
      (node (ref "R58") (pin "1") (pinfunction "1_1") (pintype "passive"))
      (node (ref "R59") (pin "2") (pinfunction "2_2") (pintype "passive"))
      (node (ref "R60") (pin "2") (pinfunction "2_2") (pintype "passive"))
      (node (ref "R61") (pin "B2") (pinfunction "2_B2") (pintype "passive"))
      (node (ref "R61") (pin "C2") (pinfunction "2_C2") (pintype "passive"))
      (node (ref "R62") (pin "A2") (pinfunction "2_A2") (pintype "passive"))
      (node (ref "R62") (pin "B2") (pinfunction "2_B2") (pintype "passive"))
      (node (ref "R62") (pin "D2") (pinfunction "2_D2") (pintype "passive"))
      (node (ref "R63") (pin "A2") (pinfunction "2_A2") (pintype "passive"))
      (node (ref "R63") (pin "C2") (pinfunction "2_C2") (pintype "passive"))
      (node (ref "R63") (pin "D2") (pinfunction "2_D2") (pintype "passive"))
      (node (ref "R67") (pin "1") (pinfunction "1_1") (pintype "passive"))
      (node (ref "R68") (pin "1") (pinfunction "1_1") (pintype "passive"))
      (node (ref "R69") (pin "1") (pinfunction "1_1") (pintype "passive"))
      (node (ref "R70") (pin "1") (pinfunction "1_1") (pintype "passive"))
      (node (ref "R71") (pin "1") (pinfunction "1_1") (pintype "passive"))
      (node (ref "R72") (pin "1") (pinfunction "1_1") (pintype "passive"))
      (node (ref "R73") (pin "1") (pinfunction "1_1") (pintype "passive"))
      (node (ref "R74") (pin "1") (pinfunction "1_1") (pintype "passive"))
      (node (ref "R75") (pin "1") (pinfunction "1_1") (pintype "passive"))
      (node (ref "R76") (pin "1") (pinfunction "1_1") (pintype "passive"))
      (node (ref "R77") (pin "1") (pinfunction "1_1") (pintype "passive"))
      (node (ref "R78") (pin "1") (pinfunction "1_1") (pintype "passive"))
      (node (ref "R79") (pin "1") (pinfunction "1_1") (pintype "passive"))
      (node (ref "R80") (pin "1") (pinfunction "1_1") (pintype "passive"))
      (node (ref "R81") (pin "1") (pinfunction "1_1") (pintype "passive"))
      (node (ref "R82") (pin "1") (pinfunction "1_1") (pintype "passive"))
      (node (ref "R83") (pin "1") (pinfunction "1_1") (pintype "passive"))
      (node (ref "S1") (pin "1") (pinfunction "GND_1") (pintype "bidirectional"))
      (node (ref "S1") (pin "PAD") (pinfunction "GND_PAD") (pintype "bidirectional"))
      (node (ref "S10") (pin "2") (pinfunction "GND_2") (pintype "bidirectional"))
      (node (ref "S12") (pin "2") (pinfunction "GND_2") (pintype "bidirectional"))
      (node (ref "S12") (pin "PAD") (pinfunction "GND_PAD") (pintype "bidirectional"))
      (node (ref "S13") (pin "2") (pinfunction "GND_2") (pintype "bidirectional"))
      (node (ref "S13") (pin "PAD") (pinfunction "GND_PAD") (pintype "bidirectional"))
      (node (ref "S14") (pin "7") (pinfunction "GND_7") (pintype "bidirectional"))
      (node (ref "S15") (pin "7") (pinfunction "GND_7") (pintype "bidirectional"))
      (node (ref "S16") (pin "7") (pinfunction "GND_7") (pintype "bidirectional"))
      (node (ref "S17") (pin "7") (pinfunction "GND_7") (pintype "bidirectional"))
      (node (ref "S18") (pin "7") (pinfunction "GND_7") (pintype "bidirectional"))
      (node (ref "S2") (pin "1") (pinfunction "GND_1") (pintype "bidirectional"))
      (node (ref "S2") (pin "PAD") (pinfunction "GND_PAD") (pintype "bidirectional"))
      (node (ref "S20") (pin "3") (pinfunction "P$2_3") (pintype "passive"))
      (node (ref "S20") (pin "4") (pinfunction "P$2_4") (pintype "passive"))
      (node (ref "S21") (pin "A1") (pinfunction "1TA_A1") (pintype "bidirectional"))
      (node (ref "S22") (pin "A1") (pinfunction "1TA_A1") (pintype "bidirectional"))
      (node (ref "S23") (pin "1") (pinfunction "A_1") (pintype "bidirectional"))
      (node (ref "S3") (pin "1") (pinfunction "P$1_1") (pintype "passive"))
      (node (ref "S3") (pin "2") (pinfunction "P$1_2") (pintype "passive"))
      (node (ref "S4") (pin "1") (pinfunction "P$1_1") (pintype "passive"))
      (node (ref "S4") (pin "2") (pinfunction "P$1_2") (pintype "passive"))
      (node (ref "S5") (pin "1") (pinfunction "P$1_1") (pintype "passive"))
      (node (ref "S5") (pin "2") (pinfunction "P$1_2") (pintype "passive"))
      (node (ref "S6") (pin "1") (pinfunction "P$1_1") (pintype "passive"))
      (node (ref "S6") (pin "2") (pinfunction "P$1_2") (pintype "passive"))
      (node (ref "S7") (pin "1") (pinfunction "P$1_1") (pintype "passive"))
      (node (ref "S7") (pin "2") (pinfunction "P$1_2") (pintype "passive"))
      (node (ref "S8") (pin "1") (pinfunction "P$1_1") (pintype "passive"))
      (node (ref "S8") (pin "2") (pinfunction "P$1_2") (pintype "passive"))
      (node (ref "S9") (pin "2") (pinfunction "GND_2") (pintype "bidirectional"))
      (node (ref "U1") (pin "17") (pinfunction "GND_17") (pintype "power_in"))
      (node (ref "U1") (pin "20") (pinfunction "GND_20") (pintype "power_in"))
      (node (ref "U1") (pin "24") (pinfunction "GND_24") (pintype "power_in"))
      (node (ref "U1") (pin "26") (pinfunction "TEST_26") (pintype "input"))
      (node (ref "U1") (pin "4") (pinfunction "GND_4") (pintype "power_in"))
      (node (ref "U10") (pin "P$1") (pinfunction "GND_P$1") (pintype "open_collector"))
      (node (ref "U10") (pin "P2") (pinfunction "GND_P2") (pintype "open_collector"))
      (node (ref "U10") (pin "P3") (pinfunction "GND_P3") (pintype "open_collector"))
      (node (ref "U10") (pin "P7") (pinfunction "GND_P7") (pintype "open_collector"))
      (node (ref "U11") (pin "P$1") (pinfunction "GND_P$1") (pintype "open_collector"))
      (node (ref "U11") (pin "P2") (pinfunction "GND_P2") (pintype "open_collector"))
      (node (ref "U11") (pin "P3") (pinfunction "GND_P3") (pintype "open_collector"))
      (node (ref "U11") (pin "P7") (pinfunction "GND_P7") (pintype "open_collector"))
      (node (ref "U12") (pin "P$1") (pinfunction "GND_P$1") (pintype "open_collector"))
      (node (ref "U12") (pin "P2") (pinfunction "GND_P2") (pintype "open_collector"))
      (node (ref "U12") (pin "P3") (pinfunction "GND_P3") (pintype "open_collector"))
      (node (ref "U12") (pin "P7") (pinfunction "GND_P7") (pintype "open_collector"))
      (node (ref "U13") (pin "2") (pinfunction "GND_2") (pintype "bidirectional"))
      (node (ref "U13") (pin "3") (pinfunction "GND_3") (pintype "bidirectional"))
      (node (ref "U13") (pin "4") (pinfunction "GND_4") (pintype "bidirectional"))
      (node (ref "U13") (pin "6") (pinfunction "~{ON}_6") (pintype "bidirectional"))
      (node (ref "U14") (pin "2") (pinfunction "E1_2") (pintype "bidirectional"))
      (node (ref "U14") (pin "3") (pinfunction "E2_3") (pintype "bidirectional"))
      (node (ref "U14") (pin "4") (pinfunction "GND_4") (pintype "bidirectional"))
      (node (ref "U15") (pin "4") (pinfunction "GND_4") (pintype "bidirectional"))
      (node (ref "U16") (pin "2") (pinfunction "GND_2") (pintype "bidirectional"))
      (node (ref "U17") (pin "1") (pinfunction "A2_1") (pintype "bidirectional"))
      (node (ref "U17") (pin "17") (pinfunction "GND_17") (pintype "bidirectional"))
      (node (ref "U17") (pin "2") (pinfunction "A1_2") (pintype "bidirectional"))
      (node (ref "U17") (pin "3") (pinfunction "A0_3") (pintype "bidirectional"))
      (node (ref "U17") (pin "GND") (pinfunction "GND_GND") (pintype "bidirectional"))
      (node (ref "U18") (pin "1") (pinfunction "A2_1") (pintype "bidirectional"))
      (node (ref "U18") (pin "17") (pinfunction "GND_17") (pintype "bidirectional"))
      (node (ref "U18") (pin "2") (pinfunction "A1_2") (pintype "bidirectional"))
      (node (ref "U18") (pin "GND") (pinfunction "GND_GND") (pintype "bidirectional"))
      (node (ref "U19") (pin "1") (pinfunction "A2_1") (pintype "bidirectional"))
      (node (ref "U19") (pin "17") (pinfunction "GND_17") (pintype "bidirectional"))
      (node (ref "U19") (pin "GND") (pinfunction "GND_GND") (pintype "bidirectional"))
      (node (ref "U2") (pin "17") (pinfunction "GND_17") (pintype "power_in"))
      (node (ref "U2") (pin "20") (pinfunction "GND_20") (pintype "power_in"))
      (node (ref "U2") (pin "24") (pinfunction "GND_24") (pintype "power_in"))
      (node (ref "U2") (pin "26") (pinfunction "TEST_26") (pintype "input"))
      (node (ref "U2") (pin "4") (pinfunction "GND_4") (pintype "power_in"))
      (node (ref "U20") (pin "3") (pinfunction "GND_3") (pintype "bidirectional"))
      (node (ref "U21") (pin "3") (pinfunction "GND_3") (pintype "bidirectional"))
      (node (ref "U22") (pin "1") (pinfunction "A0_1") (pintype "bidirectional"))
      (node (ref "U22") (pin "10") (pinfunction "GND_10") (pintype "bidirectional"))
      (node (ref "U22") (pin "2") (pinfunction "A1_2") (pintype "bidirectional"))
      (node (ref "U22") (pin "3") (pinfunction "A2_3") (pintype "bidirectional"))
      (node (ref "U23") (pin "17") (pinfunction "GNDANA_17") (pintype "power_in"))
      (node (ref "U23") (pin "30") (pinfunction "GND_30") (pintype "power_in"))
      (node (ref "U23") (pin "48") (pinfunction "GND_48") (pintype "power_in"))
      (node (ref "U23") (pin "6") (pinfunction "GND_6") (pintype "power_in"))
      (node (ref "U23") (pin "THERMAL") (pinfunction "GND_THERMAL") (pintype "power_in"))
      (node (ref "U24") (pin "4") (pinfunction "GND_4") (pintype "bidirectional"))
      (node (ref "U25") (pin "4") (pinfunction "GND_4") (pintype "bidirectional"))
      (node (ref "U26") (pin "4") (pinfunction "GND_4") (pintype "bidirectional"))
      (node (ref "U26") (pin "5") (pinfunction "DIR_5") (pintype "bidirectional"))
      (node (ref "U27") (pin "4") (pinfunction "GND_4") (pintype "bidirectional"))
      (node (ref "U27") (pin "5") (pinfunction "DIR_5") (pintype "bidirectional"))
      (node (ref "U28") (pin "10") (pinfunction "S_10") (pintype "bidirectional"))
      (node (ref "U28") (pin "4") (pinfunction "GND_4") (pintype "bidirectional"))
      (node (ref "U29") (pin "10") (pinfunction "S_10") (pintype "bidirectional"))
      (node (ref "U29") (pin "4") (pinfunction "GND_4") (pintype "bidirectional"))
      (node (ref "U3") (pin "17") (pinfunction "GND_17") (pintype "power_in"))
      (node (ref "U3") (pin "20") (pinfunction "GND_20") (pintype "power_in"))
      (node (ref "U3") (pin "24") (pinfunction "GND_24") (pintype "power_in"))
      (node (ref "U3") (pin "26") (pinfunction "TEST_26") (pintype "input"))
      (node (ref "U3") (pin "4") (pinfunction "GND_4") (pintype "power_in"))
      (node (ref "U30") (pin "4") (pinfunction "GND_4") (pintype "bidirectional"))
      (node (ref "U30") (pin "8") (pinfunction "~{OE}_8") (pintype "bidirectional"))
      (node (ref "U31") (pin "24") (pinfunction "GND_24") (pintype "bidirectional"))
      (node (ref "U31") (pin "43") (pinfunction "GND_43") (pintype "bidirectional"))
      (node (ref "U31") (pin "48") (pinfunction "MODE_48") (pintype "bidirectional"))
      (node (ref "U31") (pin "5") (pinfunction "GND_5") (pintype "bidirectional"))
      (node (ref "U32") (pin "24") (pinfunction "GND_24") (pintype "bidirectional"))
      (node (ref "U32") (pin "43") (pinfunction "GND_43") (pintype "bidirectional"))
      (node (ref "U32") (pin "48") (pinfunction "MODE_48") (pintype "bidirectional"))
      (node (ref "U32") (pin "5") (pinfunction "GND_5") (pintype "bidirectional"))
      (node (ref "U32") (pin "8") (pinfunction "EEDATA/~{GANGED}_8") (pintype "bidirectional"))
      (node (ref "U4") (pin "17") (pinfunction "GND_17") (pintype "power_in"))
      (node (ref "U4") (pin "20") (pinfunction "GND_20") (pintype "power_in"))
      (node (ref "U4") (pin "24") (pinfunction "GND_24") (pintype "power_in"))
      (node (ref "U4") (pin "26") (pinfunction "TEST_26") (pintype "input"))
      (node (ref "U4") (pin "4") (pinfunction "GND_4") (pintype "power_in"))
      (node (ref "U5") (pin "17") (pinfunction "GND_17") (pintype "power_in"))
      (node (ref "U5") (pin "20") (pinfunction "GND_20") (pintype "power_in"))
      (node (ref "U5") (pin "24") (pinfunction "GND_24") (pintype "power_in"))
      (node (ref "U5") (pin "26") (pinfunction "TEST_26") (pintype "input"))
      (node (ref "U5") (pin "4") (pinfunction "GND_4") (pintype "power_in"))
      (node (ref "U6") (pin "17") (pinfunction "GND_17") (pintype "power_in"))
      (node (ref "U6") (pin "20") (pinfunction "GND_20") (pintype "power_in"))
      (node (ref "U6") (pin "24") (pinfunction "GND_24") (pintype "power_in"))
      (node (ref "U6") (pin "26") (pinfunction "TEST_26") (pintype "input"))
      (node (ref "U6") (pin "4") (pinfunction "GND_4") (pintype "power_in"))
      (node (ref "U7") (pin "4") (pinfunction "GND_4") (pintype "bidirectional"))
      (node (ref "U8") (pin "4") (pinfunction "GND_4") (pintype "bidirectional"))
      (node (ref "U9") (pin "2") (pinfunction "GND_2") (pintype "open_collector"))
      (node (ref "Y3") (pin "2") (pinfunction "GND_2") (pintype "bidirectional"))
      (node (ref "Y3") (pin "4") (pinfunction "GND_4") (pintype "bidirectional"))
    )
    (net (code "59") (name "HUB_CFG") (class "Default")
      (node (ref "JP7") (pin "1") (pinfunction "1_1") (pintype "passive"))
      (node (ref "U31") (pin "40") (pinfunction "HUBCFG_40") (pintype "bidirectional"))
    )
    (net (code "60") (name "HUB_DM1") (class "Default")
      (node (ref "C6") (pin "1") (pinfunction "1_1") (pintype "bidirectional"))
      (node (ref "R9") (pin "2") (pinfunction "P$2_2") (pintype "passive"))
      (node (ref "U31") (pin "13") (pinfunction "DM1_13") (pintype "bidirectional"))
    )
    (net (code "61") (name "HUB_DM2") (class "Default")
      (node (ref "C4") (pin "1") (pinfunction "1_1") (pintype "bidirectional"))
      (node (ref "R7") (pin "2") (pinfunction "P$2_2") (pintype "passive"))
      (node (ref "U31") (pin "17") (pinfunction "DM2_17") (pintype "bidirectional"))
    )
    (net (code "62") (name "HUB_DM3") (class "Default")
      (node (ref "C8") (pin "1") (pinfunction "1_1") (pintype "bidirectional"))
      (node (ref "R5") (pin "2") (pinfunction "P$2_2") (pintype "passive"))
      (node (ref "U31") (pin "21") (pinfunction "DM3_21") (pintype "bidirectional"))
    )
    (net (code "63") (name "HUB_DM4") (class "Default")
      (node (ref "R61") (pin "B1") (pinfunction "1_B1") (pintype "passive"))
      (node (ref "U31") (pin "26") (pinfunction "DM4_26") (pintype "bidirectional"))
    )
    (net (code "64") (name "HUB_DM5") (class "Default")
      (node (ref "R62") (pin "A1") (pinfunction "1_A1") (pintype "passive"))
      (node (ref "U31") (pin "30") (pinfunction "DM5_30") (pintype "bidirectional"))
    )
    (net (code "65") (name "HUB_DM6") (class "Default")
      (node (ref "R62") (pin "D1") (pinfunction "1_D1") (pintype "passive"))
      (node (ref "U31") (pin "34") (pinfunction "DM6_34") (pintype "bidirectional"))
    )
    (net (code "66") (name "HUB_DM7") (class "Default")
      (node (ref "R63") (pin "C1") (pinfunction "1_C1") (pintype "passive"))
      (node (ref "U31") (pin "38") (pinfunction "DM7_38") (pintype "bidirectional"))
    )
    (net (code "67") (name "HUB_DP1") (class "Default")
      (node (ref "C5") (pin "1") (pinfunction "1_1") (pintype "bidirectional"))
      (node (ref "R8") (pin "2") (pinfunction "P$2_2") (pintype "passive"))
      (node (ref "U31") (pin "14") (pinfunction "DP1_14") (pintype "bidirectional"))
    )
    (net (code "68") (name "HUB_DP2") (class "Default")
      (node (ref "C3") (pin "1") (pinfunction "1_1") (pintype "bidirectional"))
      (node (ref "R6") (pin "2") (pinfunction "P$2_2") (pintype "passive"))
      (node (ref "U31") (pin "18") (pinfunction "DP2_18") (pintype "bidirectional"))
    )
    (net (code "69") (name "HUB_DP3") (class "Default")
      (node (ref "C7") (pin "1") (pinfunction "1_1") (pintype "bidirectional"))
      (node (ref "R10") (pin "2") (pinfunction "P$2_2") (pintype "passive"))
      (node (ref "U31") (pin "22") (pinfunction "DP3_22") (pintype "bidirectional"))
    )
    (net (code "70") (name "HUB_DP4") (class "Default")
      (node (ref "R61") (pin "C1") (pinfunction "1_C1") (pintype "passive"))
      (node (ref "U31") (pin "27") (pinfunction "DP4_27") (pintype "bidirectional"))
    )
    (net (code "71") (name "HUB_DP5") (class "Default")
      (node (ref "R62") (pin "B1") (pinfunction "1_B1") (pintype "passive"))
      (node (ref "U31") (pin "31") (pinfunction "DP5_31") (pintype "bidirectional"))
    )
    (net (code "72") (name "HUB_DP6") (class "Default")
      (node (ref "R63") (pin "A1") (pinfunction "1_A1") (pintype "passive"))
      (node (ref "U31") (pin "35") (pinfunction "DP6_35") (pintype "bidirectional"))
    )
    (net (code "73") (name "HUB_DP7") (class "Default")
      (node (ref "R63") (pin "D1") (pinfunction "1_D1") (pintype "passive"))
      (node (ref "U31") (pin "39") (pinfunction "DP7_39") (pintype "bidirectional"))
    )
    (net (code "74") (name "HUB_PORTDIS") (class "Default")
      (node (ref "JP7") (pin "4") (pinfunction "4_4") (pintype "passive"))
      (node (ref "U31") (pin "42") (pinfunction "PORTDIS_42") (pintype "bidirectional"))
    )
    (net (code "75") (name "HUB_PORTPWR") (class "Default")
      (node (ref "JP7") (pin "2") (pinfunction "2_2") (pintype "passive"))
      (node (ref "U31") (pin "41") (pinfunction "PORTPWR_41") (pintype "bidirectional"))
    )
    (net (code "76") (name "HUB_~{OVRCUR1}") (class "Default")
      (node (ref "JP8") (pin "2") (pinfunction "2_2") (pintype "passive"))
      (node (ref "R36") (pin "1") (pinfunction "1_1") (pintype "passive"))
      (node (ref "S2") (pin "5") (pinfunction "~{FLG}_5") (pintype "bidirectional"))
      (node (ref "U31") (pin "12") (pinfunction "~{OVRCUR1}_12") (pintype "bidirectional"))
    )
    (net (code "77") (name "HUB_~{OVRCUR2}") (class "Default")
      (node (ref "JP8") (pin "4") (pinfunction "4_4") (pintype "passive"))
      (node (ref "R35") (pin "1") (pinfunction "1_1") (pintype "passive"))
      (node (ref "S1") (pin "5") (pinfunction "~{FLG}_5") (pintype "bidirectional"))
      (node (ref "U31") (pin "16") (pinfunction "~{OVRCUR2}_16") (pintype "bidirectional"))
    )
    (net (code "78") (name "HUB_~{OVRCUR3}") (class "Default")
      (node (ref "JP8") (pin "6") (pinfunction "6_6") (pintype "passive"))
      (node (ref "R49") (pin "1") (pinfunction "1_1") (pintype "passive"))
      (node (ref "U31") (pin "20") (pinfunction "~{OVRCUR3}_20") (pintype "bidirectional"))
    )
    (net (code "79") (name "HUB_~{OVRCUR4}") (class "Default")
      (node (ref "R61") (pin "A1") (pinfunction "1_A1") (pintype "passive"))
      (node (ref "U31") (pin "25") (pinfunction "~{OVRCUR4}_25") (pintype "bidirectional"))
    )
    (net (code "80") (name "HUB_~{OVRCUR5}") (class "Default")
      (node (ref "R61") (pin "D1") (pinfunction "1_D1") (pintype "passive"))
      (node (ref "U31") (pin "29") (pinfunction "~{OVRCUR5}_29") (pintype "bidirectional"))
    )
    (net (code "81") (name "HUB_~{OVRCUR6}") (class "Default")
      (node (ref "R62") (pin "C1") (pinfunction "1_C1") (pintype "passive"))
      (node (ref "U31") (pin "33") (pinfunction "~{OVRCUR6}_33") (pintype "bidirectional"))
    )
    (net (code "82") (name "HUB_~{OVRCUR7}") (class "Default")
      (node (ref "R63") (pin "B1") (pinfunction "1_B1") (pintype "passive"))
      (node (ref "U31") (pin "37") (pinfunction "~{OVRCUR7}_37") (pintype "bidirectional"))
    )
    (net (code "83") (name "HUB_~{PWRON1}") (class "Default")
      (node (ref "JP8") (pin "1") (pinfunction "1_1") (pintype "passive"))
      (node (ref "S10") (pin "1") (pinfunction "I1_1") (pintype "bidirectional"))
      (node (ref "U19") (pin "10") (pinfunction "P1_10") (pintype "bidirectional"))
      (node (ref "U31") (pin "11") (pinfunction "~{PWRON1}_11") (pintype "bidirectional"))
    )
    (net (code "84") (name "HUB_~{PWRON2}") (class "Default")
      (node (ref "JP8") (pin "3") (pinfunction "3_3") (pintype "passive"))
      (node (ref "S9") (pin "1") (pinfunction "I1_1") (pintype "bidirectional"))
      (node (ref "U19") (pin "11") (pinfunction "P2_11") (pintype "bidirectional"))
      (node (ref "U31") (pin "15") (pinfunction "~{PWRON2}_15") (pintype "bidirectional"))
    )
    (net (code "85") (name "HUB_~{PWRON3}") (class "Default")
      (node (ref "JP8") (pin "5") (pinfunction "5_5") (pintype "passive"))
      (node (ref "U19") (pin "12") (pinfunction "P3_12") (pintype "bidirectional"))
      (node (ref "U31") (pin "19") (pinfunction "~{PWRON3}_19") (pintype "bidirectional"))
    )
    (net (code "86") (name "HUB_~{PWRON4}") (class "Default")
      (node (ref "U31") (pin "23") (pinfunction "~{PWRON4}_23") (pintype "bidirectional"))
    )
    (net (code "87") (name "HUB_~{PWRON5}") (class "Default")
      (node (ref "U31") (pin "28") (pinfunction "~{PWRON5}_28") (pintype "bidirectional"))
    )
    (net (code "88") (name "HUB_~{PWRON6}") (class "Default")
      (node (ref "U31") (pin "32") (pinfunction "~{PWRON6}_32") (pintype "bidirectional"))
    )
    (net (code "89") (name "HUB_~{PWRON7}") (class "Default")
      (node (ref "U31") (pin "36") (pinfunction "~{PWRON7}_36") (pintype "bidirectional"))
    )
    (net (code "90") (name "JTAG_5V") (class "Default")
      (node (ref "J6") (pin "19") (pinfunction "19_19") (pintype "passive"))
    )
    (net (code "91") (name "JTAG_DBGRQ") (class "Default")
      (node (ref "J6") (pin "17") (pinfunction "17_17") (pintype "passive"))
    )
    (net (code "92") (name "JTAG_NTRST") (class "Default")
      (node (ref "J6") (pin "3") (pinfunction "3_3") (pintype "passive"))
    )
    (net (code "93") (name "JTAG_RTCK") (class "Default")
      (node (ref "J6") (pin "11") (pinfunction "11_11") (pintype "passive"))
    )
    (net (code "94") (name "JTAG_SWDCLK") (class "Default")
      (node (ref "J6") (pin "9") (pinfunction "9_9") (pintype "passive"))
      (node (ref "S14") (pin "4") (pinfunction "IN_4") (pintype "bidirectional"))
      (node (ref "S15") (pin "4") (pinfunction "IN_4") (pintype "bidirectional"))
      (node (ref "S16") (pin "4") (pinfunction "IN_4") (pintype "bidirectional"))
      (node (ref "S17") (pin "4") (pinfunction "IN_4") (pintype "bidirectional"))
      (node (ref "S18") (pin "4") (pinfunction "IN_4") (pintype "bidirectional"))
    )
    (net (code "95") (name "JTAG_SWDIO") (class "Default")
      (node (ref "J6") (pin "7") (pinfunction "7_7") (pintype "passive"))
      (node (ref "S14") (pin "1") (pinfunction "IN_1") (pintype "bidirectional"))
      (node (ref "S15") (pin "1") (pinfunction "IN_1") (pintype "bidirectional"))
      (node (ref "S16") (pin "1") (pinfunction "IN_1") (pintype "bidirectional"))
      (node (ref "S17") (pin "1") (pinfunction "IN_1") (pintype "bidirectional"))
      (node (ref "S18") (pin "1") (pinfunction "IN_1") (pintype "bidirectional"))
      (node (ref "S19") (pin "IN") (pinfunction "IN_IN") (pintype "bidirectional"))
    )
    (net (code "96") (name "JTAG_SWO{slash}TDO") (class "Default")
      (node (ref "J6") (pin "13") (pinfunction "13_13") (pintype "passive"))
    )
    (net (code "97") (name "JTAG_TDI") (class "Default")
      (node (ref "J6") (pin "5") (pinfunction "5_5") (pintype "passive"))
    )
    (net (code "98") (name "JTAG_VTREF") (class "Default")
      (node (ref "J6") (pin "1") (pinfunction "1_1") (pintype "passive"))
      (node (ref "S14") (pin "11") (pinfunction "IN_11") (pintype "bidirectional"))
      (node (ref "S15") (pin "11") (pinfunction "IN_11") (pintype "bidirectional"))
      (node (ref "S16") (pin "11") (pinfunction "IN_11") (pintype "bidirectional"))
      (node (ref "S17") (pin "11") (pinfunction "IN_11") (pintype "bidirectional"))
      (node (ref "S18") (pin "11") (pinfunction "IN_11") (pintype "bidirectional"))
    )
    (net (code "99") (name "JTAG_~{RESET}") (class "Default")
      (node (ref "J6") (pin "15") (pinfunction "15_15") (pintype "passive"))
      (node (ref "S14") (pin "8") (pinfunction "IN_8") (pintype "bidirectional"))
      (node (ref "S15") (pin "8") (pinfunction "IN_8") (pintype "bidirectional"))
      (node (ref "S16") (pin "8") (pinfunction "IN_8") (pintype "bidirectional"))
      (node (ref "S17") (pin "8") (pinfunction "IN_8") (pintype "bidirectional"))
      (node (ref "S18") (pin "8") (pinfunction "IN_8") (pintype "bidirectional"))
      (node (ref "S19") (pin "1") (pinfunction "A_1") (pintype "bidirectional"))
    )
    (net (code "100") (name "MASTER_~{RESET}") (class "Default")
      (node (ref "D1") (pin "1K") (pinfunction "CATHODE_1K") (pintype "bidirectional"))
      (node (ref "D1") (pin "2K") (pinfunction "CATHODE_2K") (pintype "bidirectional"))
      (node (ref "D1") (pin "3K") (pinfunction "CATHODE_3K") (pintype "bidirectional"))
      (node (ref "D1") (pin "4K") (pinfunction "CATHODE_4K") (pintype "bidirectional"))
      (node (ref "D2") (pin "1K") (pinfunction "CATHODE_1K") (pintype "bidirectional"))
      (node (ref "D2") (pin "2K") (pinfunction "CATHODE_2K") (pintype "bidirectional"))
      (node (ref "D2") (pin "3K") (pinfunction "CATHODE_3K") (pintype "bidirectional"))
      (node (ref "D2") (pin "4K") (pinfunction "CATHODE_4K") (pintype "bidirectional"))
      (node (ref "D3") (pin "1K") (pinfunction "CATHODE_1K") (pintype "bidirectional"))
      (node (ref "S20") (pin "1") (pinfunction "P$1_1") (pintype "passive"))
      (node (ref "S20") (pin "2") (pinfunction "P$1_2") (pintype "passive"))
    )
    (net (code "101") (name "MOD0_5V") (class "Default")
      (node (ref "C16") (pin "1") (pinfunction "1_1") (pintype "bidirectional"))
      (node (ref "JP1") (pin "1") (pinfunction "1_1") (pintype "passive"))
      (node (ref "JP4") (pin "2") (pinfunction "2_2") (pintype "passive"))
      (node (ref "S12") (pin "1") (pinfunction "VLOAD_1") (pintype "bidirectional"))
      (node (ref "SJ2") (pin "2") (pinfunction "2_2") (pintype "passive"))
      (node (ref "TP5") (pin "TESTPOINT") (pinfunction "TESTPOINT_TESTPOINT") (pintype "bidirectional"))
    )
    (net (code "102") (name "MOD0_5V_METERED") (class "Default")
      (node (ref "C33") (pin "1") (pinfunction "1_1") (pintype "bidirectional"))
      (node (ref "C60") (pin "1") (pinfunction "1_1") (pintype "bidirectional"))
      (node (ref "C68") (pin "1") (pinfunction "1_1") (pintype "bidirectional"))
      (node (ref "JP16") (pin "5") (pinfunction "5_5") (pintype "passive"))
      (node (ref "R3") (pin "1") (pinfunction "1_1") (pintype "passive"))
      (node (ref "S1") (pin "2") (pinfunction "IN_2") (pintype "bidirectional"))
      (node (ref "S1") (pin "3") (pinfunction "IN_3") (pintype "bidirectional"))
      (node (ref "S12") (pin "3") (pinfunction "VSUPP_3") (pintype "bidirectional"))
      (node (ref "U11") (pin "P8") (pinfunction "SENSE-_P8") (pintype "open_collector"))
    )
    (net (code "103") (name "MOD0_D+_HUB-SW") (class "Default")
      (node (ref "D36") (pin "4") (pinfunction "D_4") (pintype "bidirectional"))
      (node (ref "R53") (pin "2") (pinfunction "2_2") (pintype "passive"))
      (node (ref "R6") (pin "1") (pinfunction "P$1_1") (pintype "passive"))
      (node (ref "U28") (pin "3") (pinfunction "D+_3") (pintype "bidirectional"))
    )
    (net (code "104") (name "MOD0_D-_HUB-SW") (class "Default")
      (node (ref "D36") (pin "2") (pinfunction "C_2") (pintype "bidirectional"))
      (node (ref "R54") (pin "2") (pinfunction "2_2") (pintype "passive"))
      (node (ref "R7") (pin "1") (pinfunction "P$1_1") (pintype "passive"))
      (node (ref "U28") (pin "5") (pinfunction "D-_5") (pintype "bidirectional"))
    )
    (net (code "105") (name "MOD0_DBG_GPIO1") (class "Default")
      (node (ref "J2") (pin "16") (pinfunction "DBG_GPIO1_16") (pintype "bidirectional"))
      (node (ref "JP3") (pin "5") (pinfunction "5_5") (pintype "passive"))
      (node (ref "Q2") (pin "G1") (pinfunction "G1_G1") (pintype "input"))
      (node (ref "R68") (pin "2") (pinfunction "2_2") (pintype "passive"))
    )
    (net (code "106") (name "MOD0_DBG_GPIO2") (class "Default")
      (node (ref "J2") (pin "19") (pinfunction "DBG_GPIO2_19") (pintype "bidirectional"))
      (node (ref "JP3") (pin "2") (pinfunction "2_2") (pintype "passive"))
      (node (ref "Q2") (pin "G2") (pinfunction "G2_G2") (pintype "input"))
      (node (ref "R69") (pin "2") (pinfunction "2_2") (pintype "passive"))
    )
    (net (code "107") (name "MOD0_DBG_RX") (class "Default")
      (node (ref "J2") (pin "18") (pinfunction "DBG_RX_18") (pintype "bidirectional"))
      (node (ref "JP3") (pin "3") (pinfunction "3_3") (pintype "passive"))
      (node (ref "U2") (pin "30") (pinfunction "TXD_30") (pintype "output"))
    )
    (net (code "108") (name "MOD0_DBG_SWDCLK") (class "Default")
      (node (ref "J2") (pin "21") (pinfunction "DBG_SWDCLK_21") (pintype "bidirectional"))
      (node (ref "S14") (pin "3") (pinfunction "A_3") (pintype "bidirectional"))
    )
    (net (code "109") (name "MOD0_DBG_SWDIO") (class "Default")
      (node (ref "J2") (pin "22") (pinfunction "DBG_SWDIO_22") (pintype "bidirectional"))
      (node (ref "S14") (pin "2") (pinfunction "A_2") (pintype "bidirectional"))
    )
    (net (code "110") (name "MOD0_DBG_TX") (class "Default")
      (node (ref "J2") (pin "17") (pinfunction "DBG_TX_17") (pintype "bidirectional"))
      (node (ref "JP3") (pin "4") (pinfunction "4_4") (pintype "passive"))
      (node (ref "U2") (pin "2") (pinfunction "RXD_2") (pintype "input"))
    )
    (net (code "111") (name "MOD0_DBG_~{RESET}") (class "Default")
      (node (ref "D1") (pin "1A") (pinfunction "ANODE_1A") (pintype "bidirectional"))
      (node (ref "J2") (pin "20") (pinfunction "DBG_~{RESET}_20") (pintype "bidirectional"))
      (node (ref "JP3") (pin "1") (pinfunction "1_1") (pintype "passive"))
      (node (ref "S14") (pin "9") (pinfunction "A_9") (pintype "bidirectional"))
      (node (ref "S3") (pin "3") (pinfunction "P$2_3") (pintype "passive"))
      (node (ref "S3") (pin "4") (pinfunction "P$2_4") (pintype "passive"))
    )
    (net (code "112") (name "MOD0_HDR_RSV_PIN3") (class "Default")
      (node (ref "JP4") (pin "3") (pinfunction "3_3") (pintype "passive"))
    )
    (net (code "113") (name "MOD0_HDR_RSV_PIN9") (class "Default")
      (node (ref "JP4") (pin "9") (pinfunction "9_9") (pintype "passive"))
    )
    (net (code "114") (name "MOD0_IN") (class "Default")
      (node (ref "J2") (pin "10") (pinfunction "MOD_IN_10") (pintype "bidirectional"))
      (node (ref "JP1") (pin "7") (pinfunction "7_7") (pintype "passive"))
      (node (ref "JP4") (pin "10") (pinfunction "10_10") (pintype "passive"))
      (node (ref "U24") (pin "7") (pinfunction "B1_7") (pintype "bidirectional"))
    )
    (net (code "115") (name "MOD0_ISO_I2C") (class "Default")
      (node (ref "D5") (pin "A") (pinfunction "ANODE_A") (pintype "bidirectional"))
      (node (ref "JP17") (pin "2") (pinfunction "2_2") (pintype "passive"))
      (node (ref "S21") (pin "COM3") (pinfunction "3P_COM3") (pintype "bidirectional"))
      (node (ref "U7") (pin "5") (pinfunction "OE_5") (pintype "bidirectional"))
    )
    (net (code "116") (name "MOD0_ISO_OVERRIDE") (class "Default")
      (node (ref "D26") (pin "A") (pinfunction "ANODE_A") (pintype "bidirectional"))
      (node (ref "D27") (pin "A") (pinfunction "ANODE_A") (pintype "bidirectional"))
      (node (ref "D28") (pin "A") (pinfunction "ANODE_A") (pintype "bidirectional"))
      (node (ref "D29") (pin "A") (pinfunction "ANODE_A") (pintype "bidirectional"))
      (node (ref "S21") (pin "COM1") (pinfunction "1P_COM1") (pintype "bidirectional"))
    )
    (net (code "117") (name "MOD0_ISO_POWER") (class "Default")
      (node (ref "D4") (pin "A") (pinfunction "ANODE_A") (pintype "bidirectional"))
      (node (ref "JP17") (pin "3") (pinfunction "3_3") (pintype "passive"))
      (node (ref "S12") (pin "4") (pinfunction "EN_4") (pintype "bidirectional"))
      (node (ref "S21") (pin "COM4") (pinfunction "4P_COM4") (pintype "bidirectional"))
    )
    (net (code "118") (name "MOD0_ISO_USB") (class "Default")
      (node (ref "D6") (pin "A") (pinfunction "ANODE_A") (pintype "bidirectional"))
      (node (ref "JP17") (pin "1") (pinfunction "1_1") (pintype "passive"))
      (node (ref "S21") (pin "COM2") (pinfunction "2P_COM2") (pintype "bidirectional"))
      (node (ref "S9") (pin "6") (pinfunction "S_6") (pintype "bidirectional"))
    )
    (net (code "119") (name "MOD0_OUT") (class "Default")
      (node (ref "J2") (pin "8") (pinfunction "MOD_OUT_8") (pintype "bidirectional"))
      (node (ref "JP1") (pin "8") (pinfunction "8_8") (pintype "passive"))
      (node (ref "JP4") (pin "8") (pinfunction "8_8") (pintype "passive"))
      (node (ref "U26") (pin "7") (pinfunction "B1_7") (pintype "bidirectional"))
    )
    (net (code "120") (name "MOD0_PPS") (class "Default")
      (node (ref "J2") (pin "7") (pinfunction "PPS_7") (pintype "bidirectional"))
      (node (ref "JP1") (pin "10") (pinfunction "10_10") (pintype "passive"))
      (node (ref "JP4") (pin "7") (pinfunction "7_7") (pintype "passive"))
      (node (ref "U24") (pin "6") (pinfunction "B2_6") (pintype "bidirectional"))
    )
    (net (code "121") (name "MOD0_SCL") (class "Default")
      (node (ref "J2") (pin "5") (pinfunction "SCL_5") (pintype "bidirectional"))
      (node (ref "JP1") (pin "5") (pinfunction "5_5") (pintype "passive"))
      (node (ref "JP4") (pin "5") (pinfunction "5_5") (pintype "passive"))
      (node (ref "R38") (pin "2") (pinfunction "2_2") (pintype "passive"))
      (node (ref "U7") (pin "6") (pinfunction "B1_6") (pintype "bidirectional"))
    )
    (net (code "122") (name "MOD0_SDA") (class "Default")
      (node (ref "J2") (pin "6") (pinfunction "SDA_6") (pintype "bidirectional"))
      (node (ref "JP1") (pin "6") (pinfunction "6_6") (pintype "passive"))
      (node (ref "JP4") (pin "6") (pinfunction "6_6") (pintype "passive"))
      (node (ref "R37") (pin "2") (pinfunction "2_2") (pintype "passive"))
      (node (ref "U7") (pin "7") (pinfunction "B0_7") (pintype "bidirectional"))
    )
    (net (code "123") (name "MOD0_USB+") (class "Default")
      (node (ref "J2") (pin "11") (pinfunction "USB_D+_11") (pintype "bidirectional"))
      (node (ref "U28") (pin "1") (pinfunction "D1+_1") (pintype "bidirectional"))
    )
    (net (code "124") (name "MOD0_USB-") (class "Default")
      (node (ref "J2") (pin "12") (pinfunction "USB_D-_12") (pintype "bidirectional"))
      (node (ref "U28") (pin "7") (pinfunction "D1-_7") (pintype "bidirectional"))
    )
    (net (code "125") (name "MOD0_USB_VBUS") (class "Default")
      (node (ref "C29") (pin "1") (pinfunction "1_1") (pintype "bidirectional"))
      (node (ref "C74") (pin "1") (pinfunction "1_1") (pintype "bidirectional"))
      (node (ref "J2") (pin "13") (pinfunction "USB_VBUS_13") (pintype "bidirectional"))
      (node (ref "JP1") (pin "3") (pinfunction "3_3") (pintype "passive"))
      (node (ref "S1") (pin "6") (pinfunction "OUT_6") (pintype "bidirectional"))
      (node (ref "S1") (pin "7") (pinfunction "OUT_7") (pintype "bidirectional"))
    )
    (net (code "126") (name "MOD0_USB_~{EN}") (class "Default")
      (node (ref "S1") (pin "4") (pinfunction "~{EN}_4") (pintype "bidirectional"))
      (node (ref "S9") (pin "4") (pinfunction "Z_4") (pintype "bidirectional"))
      (node (ref "U28") (pin "8") (pinfunction "~{OE}_8") (pintype "bidirectional"))
    )
    (net (code "127") (name "MOD0_VCCIO") (class "Default")
      (node (ref "C22") (pin "1") (pinfunction "1_1") (pintype "bidirectional"))
      (node (ref "C24") (pin "1") (pinfunction "1_1") (pintype "bidirectional"))
      (node (ref "C37") (pin "1") (pinfunction "1_1") (pintype "bidirectional"))
      (node (ref "J2") (pin "4") (pinfunction "VCCIO_4") (pintype "bidirectional"))
      (node (ref "JP1") (pin "4") (pinfunction "4_4") (pintype "passive"))
      (node (ref "JP4") (pin "4") (pinfunction "4_4") (pintype "passive"))
      (node (ref "R37") (pin "1") (pinfunction "1_1") (pintype "passive"))
      (node (ref "R38") (pin "1") (pinfunction "1_1") (pintype "passive"))
      (node (ref "S14") (pin "10") (pinfunction "A_10") (pintype "bidirectional"))
      (node (ref "U2") (pin "1") (pinfunction "VCCIO_1") (pintype "power_in"))
      (node (ref "U24") (pin "8") (pinfunction "VCC_B_8") (pintype "bidirectional"))
      (node (ref "U26") (pin "8") (pinfunction "VCC_B_8") (pintype "bidirectional"))
      (node (ref "U7") (pin "8") (pinfunction "VCC_B_8") (pintype "bidirectional"))
    )
    (net (code "128") (name "MOD1_5V") (class "Default")
      (node (ref "C17") (pin "1") (pinfunction "1_1") (pintype "bidirectional"))
      (node (ref "JP2") (pin "1") (pinfunction "1_1") (pintype "passive"))
      (node (ref "JP5") (pin "2") (pinfunction "2_2") (pintype "passive"))
      (node (ref "S13") (pin "1") (pinfunction "VLOAD_1") (pintype "bidirectional"))
      (node (ref "SJ3") (pin "2") (pinfunction "2_2") (pintype "passive"))
      (node (ref "TP7") (pin "TESTPOINT") (pinfunction "TESTPOINT_TESTPOINT") (pintype "bidirectional"))
    )
    (net (code "129") (name "MOD1_5V_METERED") (class "Default")
      (node (ref "C34") (pin "1") (pinfunction "1_1") (pintype "bidirectional"))
      (node (ref "C61") (pin "1") (pinfunction "1_1") (pintype "bidirectional"))
      (node (ref "C69") (pin "1") (pinfunction "1_1") (pintype "bidirectional"))
      (node (ref "JP16") (pin "6") (pinfunction "6_6") (pintype "passive"))
      (node (ref "R4") (pin "1") (pinfunction "1_1") (pintype "passive"))
      (node (ref "S13") (pin "3") (pinfunction "VSUPP_3") (pintype "bidirectional"))
      (node (ref "S2") (pin "2") (pinfunction "IN_2") (pintype "bidirectional"))
      (node (ref "S2") (pin "3") (pinfunction "IN_3") (pintype "bidirectional"))
      (node (ref "U12") (pin "P8") (pinfunction "SENSE-_P8") (pintype "open_collector"))
    )
    (net (code "130") (name "MOD1_D+_HUB-SW") (class "Default")
      (node (ref "D36") (pin "8") (pinfunction "A_8") (pintype "bidirectional"))
      (node (ref "R55") (pin "2") (pinfunction "2_2") (pintype "passive"))
      (node (ref "R8") (pin "1") (pinfunction "P$1_1") (pintype "passive"))
      (node (ref "U29") (pin "3") (pinfunction "D+_3") (pintype "bidirectional"))
    )
    (net (code "131") (name "MOD1_D-_HUB-SW") (class "Default")
      (node (ref "D36") (pin "6") (pinfunction "B_6") (pintype "bidirectional"))
      (node (ref "R56") (pin "2") (pinfunction "2_2") (pintype "passive"))
      (node (ref "R9") (pin "1") (pinfunction "P$1_1") (pintype "passive"))
      (node (ref "U29") (pin "5") (pinfunction "D-_5") (pintype "bidirectional"))
    )
    (net (code "132") (name "MOD1_DBG_GPIO1") (class "Default")
      (node (ref "J3") (pin "16") (pinfunction "DBG_GPIO1_16") (pintype "bidirectional"))
      (node (ref "JP6") (pin "5") (pinfunction "5_5") (pintype "passive"))
      (node (ref "Q3") (pin "G1") (pinfunction "G1_G1") (pintype "input"))
      (node (ref "R70") (pin "2") (pinfunction "2_2") (pintype "passive"))
    )
    (net (code "133") (name "MOD1_DBG_GPIO2") (class "Default")
      (node (ref "J3") (pin "19") (pinfunction "DBG_GPIO2_19") (pintype "bidirectional"))
      (node (ref "JP6") (pin "2") (pinfunction "2_2") (pintype "passive"))
      (node (ref "Q3") (pin "G2") (pinfunction "G2_G2") (pintype "input"))
      (node (ref "R71") (pin "2") (pinfunction "2_2") (pintype "passive"))
    )
    (net (code "134") (name "MOD1_DBG_RX") (class "Default")
      (node (ref "J3") (pin "18") (pinfunction "DBG_RX_18") (pintype "bidirectional"))
      (node (ref "JP6") (pin "3") (pinfunction "3_3") (pintype "passive"))
      (node (ref "U3") (pin "30") (pinfunction "TXD_30") (pintype "output"))
    )
    (net (code "135") (name "MOD1_DBG_SWDCLK") (class "Default")
      (node (ref "J3") (pin "21") (pinfunction "DBG_SWDCLK_21") (pintype "bidirectional"))
      (node (ref "S15") (pin "3") (pinfunction "A_3") (pintype "bidirectional"))
    )
    (net (code "136") (name "MOD1_DBG_SWDIO") (class "Default")
      (node (ref "J3") (pin "22") (pinfunction "DBG_SWDIO_22") (pintype "bidirectional"))
      (node (ref "S15") (pin "2") (pinfunction "A_2") (pintype "bidirectional"))
    )
    (net (code "137") (name "MOD1_DBG_TX") (class "Default")
      (node (ref "J3") (pin "17") (pinfunction "DBG_TX_17") (pintype "bidirectional"))
      (node (ref "JP6") (pin "4") (pinfunction "4_4") (pintype "passive"))
      (node (ref "U3") (pin "2") (pinfunction "RXD_2") (pintype "input"))
    )
    (net (code "138") (name "MOD1_DBG_~{RESET}") (class "Default")
      (node (ref "D1") (pin "2A") (pinfunction "ANODE_2A") (pintype "bidirectional"))
      (node (ref "J3") (pin "20") (pinfunction "DBG_~{RESET}_20") (pintype "bidirectional"))
      (node (ref "JP6") (pin "1") (pinfunction "1_1") (pintype "passive"))
      (node (ref "S15") (pin "9") (pinfunction "A_9") (pintype "bidirectional"))
      (node (ref "S4") (pin "3") (pinfunction "P$2_3") (pintype "passive"))
      (node (ref "S4") (pin "4") (pinfunction "P$2_4") (pintype "passive"))
    )
    (net (code "139") (name "MOD1_HDR_RSV_PIN3") (class "Default")
      (node (ref "JP5") (pin "3") (pinfunction "3_3") (pintype "passive"))
    )
    (net (code "140") (name "MOD1_HDR_RSV_PIN9") (class "Default")
      (node (ref "JP5") (pin "9") (pinfunction "9_9") (pintype "passive"))
    )
    (net (code "141") (name "MOD1_IN") (class "Default")
      (node (ref "J3") (pin "10") (pinfunction "MOD_IN_10") (pintype "bidirectional"))
      (node (ref "JP2") (pin "7") (pinfunction "7_7") (pintype "passive"))
      (node (ref "JP5") (pin "10") (pinfunction "10_10") (pintype "passive"))
      (node (ref "U25") (pin "7") (pinfunction "B1_7") (pintype "bidirectional"))
    )
    (net (code "142") (name "MOD1_ISO_I2C") (class "Default")
      (node (ref "D8") (pin "A") (pinfunction "ANODE_A") (pintype "bidirectional"))
      (node (ref "JP18") (pin "2") (pinfunction "2_2") (pintype "passive"))
      (node (ref "S22") (pin "COM3") (pinfunction "3P_COM3") (pintype "bidirectional"))
      (node (ref "U8") (pin "5") (pinfunction "OE_5") (pintype "bidirectional"))
    )
    (net (code "143") (name "MOD1_ISO_OVERRIDE") (class "Default")
      (node (ref "D30") (pin "A") (pinfunction "ANODE_A") (pintype "bidirectional"))
      (node (ref "D31") (pin "A") (pinfunction "ANODE_A") (pintype "bidirectional"))
      (node (ref "D32") (pin "A") (pinfunction "ANODE_A") (pintype "bidirectional"))
      (node (ref "D33") (pin "A") (pinfunction "ANODE_A") (pintype "bidirectional"))
      (node (ref "S22") (pin "COM1") (pinfunction "1P_COM1") (pintype "bidirectional"))
    )
    (net (code "144") (name "MOD1_ISO_POWER") (class "Default")
      (node (ref "D7") (pin "A") (pinfunction "ANODE_A") (pintype "bidirectional"))
      (node (ref "JP18") (pin "3") (pinfunction "3_3") (pintype "passive"))
      (node (ref "S13") (pin "4") (pinfunction "EN_4") (pintype "bidirectional"))
      (node (ref "S22") (pin "COM4") (pinfunction "4P_COM4") (pintype "bidirectional"))
    )
    (net (code "145") (name "MOD1_ISO_USB") (class "Default")
      (node (ref "D9") (pin "A") (pinfunction "ANODE_A") (pintype "bidirectional"))
      (node (ref "JP18") (pin "1") (pinfunction "1_1") (pintype "passive"))
      (node (ref "S10") (pin "6") (pinfunction "S_6") (pintype "bidirectional"))
      (node (ref "S22") (pin "COM2") (pinfunction "2P_COM2") (pintype "bidirectional"))
    )
    (net (code "146") (name "MOD1_OUT") (class "Default")
      (node (ref "J3") (pin "8") (pinfunction "MOD_OUT_8") (pintype "bidirectional"))
      (node (ref "JP2") (pin "8") (pinfunction "8_8") (pintype "passive"))
      (node (ref "JP5") (pin "8") (pinfunction "8_8") (pintype "passive"))
      (node (ref "U27") (pin "7") (pinfunction "B1_7") (pintype "bidirectional"))
    )
    (net (code "147") (name "MOD1_PPS") (class "Default")
      (node (ref "J3") (pin "7") (pinfunction "PPS_7") (pintype "bidirectional"))
      (node (ref "JP2") (pin "10") (pinfunction "10_10") (pintype "passive"))
      (node (ref "JP5") (pin "7") (pinfunction "7_7") (pintype "passive"))
      (node (ref "U25") (pin "6") (pinfunction "B2_6") (pintype "bidirectional"))
    )
    (net (code "148") (name "MOD1_SCL") (class "Default")
      (node (ref "J3") (pin "5") (pinfunction "SCL_5") (pintype "bidirectional"))
      (node (ref "JP2") (pin "5") (pinfunction "5_5") (pintype "passive"))
      (node (ref "JP5") (pin "5") (pinfunction "5_5") (pintype "passive"))
      (node (ref "R40") (pin "2") (pinfunction "2_2") (pintype "passive"))
      (node (ref "U8") (pin "6") (pinfunction "B1_6") (pintype "bidirectional"))
    )
    (net (code "149") (name "MOD1_SDA") (class "Default")
      (node (ref "J3") (pin "6") (pinfunction "SDA_6") (pintype "bidirectional"))
      (node (ref "JP2") (pin "6") (pinfunction "6_6") (pintype "passive"))
      (node (ref "JP5") (pin "6") (pinfunction "6_6") (pintype "passive"))
      (node (ref "R39") (pin "2") (pinfunction "2_2") (pintype "passive"))
      (node (ref "U8") (pin "7") (pinfunction "B0_7") (pintype "bidirectional"))
    )
    (net (code "150") (name "MOD1_USB+") (class "Default")
      (node (ref "J3") (pin "11") (pinfunction "USB_D+_11") (pintype "bidirectional"))
      (node (ref "U29") (pin "1") (pinfunction "D1+_1") (pintype "bidirectional"))
    )
    (net (code "151") (name "MOD1_USB-") (class "Default")
      (node (ref "J3") (pin "12") (pinfunction "USB_D-_12") (pintype "bidirectional"))
      (node (ref "U29") (pin "7") (pinfunction "D1-_7") (pintype "bidirectional"))
    )
    (net (code "152") (name "MOD1_USB_VBUS") (class "Default")
      (node (ref "C30") (pin "1") (pinfunction "1_1") (pintype "bidirectional"))
      (node (ref "C75") (pin "1") (pinfunction "1_1") (pintype "bidirectional"))
      (node (ref "J3") (pin "13") (pinfunction "USB_VBUS_13") (pintype "bidirectional"))
      (node (ref "JP2") (pin "3") (pinfunction "3_3") (pintype "passive"))
      (node (ref "S2") (pin "6") (pinfunction "OUT_6") (pintype "bidirectional"))
      (node (ref "S2") (pin "7") (pinfunction "OUT_7") (pintype "bidirectional"))
    )
    (net (code "153") (name "MOD1_USB_~{EN}") (class "Default")
      (node (ref "S10") (pin "4") (pinfunction "Z_4") (pintype "bidirectional"))
      (node (ref "S2") (pin "4") (pinfunction "~{EN}_4") (pintype "bidirectional"))
      (node (ref "U29") (pin "8") (pinfunction "~{OE}_8") (pintype "bidirectional"))
    )
    (net (code "154") (name "MOD1_VCCIO") (class "Default")
      (node (ref "C23") (pin "1") (pinfunction "1_1") (pintype "bidirectional"))
      (node (ref "C25") (pin "1") (pinfunction "1_1") (pintype "bidirectional"))
      (node (ref "C38") (pin "1") (pinfunction "1_1") (pintype "bidirectional"))
      (node (ref "J3") (pin "4") (pinfunction "VCCIO_4") (pintype "bidirectional"))
      (node (ref "JP2") (pin "4") (pinfunction "4_4") (pintype "passive"))
      (node (ref "JP5") (pin "4") (pinfunction "4_4") (pintype "passive"))
      (node (ref "R39") (pin "1") (pinfunction "1_1") (pintype "passive"))
      (node (ref "R40") (pin "1") (pinfunction "1_1") (pintype "passive"))
      (node (ref "S15") (pin "10") (pinfunction "A_10") (pintype "bidirectional"))
      (node (ref "U25") (pin "8") (pinfunction "VCC_B_8") (pintype "bidirectional"))
      (node (ref "U27") (pin "8") (pinfunction "VCC_B_8") (pintype "bidirectional"))
      (node (ref "U3") (pin "1") (pinfunction "VCCIO_1") (pintype "power_in"))
      (node (ref "U8") (pin "8") (pinfunction "VCC_B_8") (pintype "bidirectional"))
    )
    (net (code "155") (name "MOD2_DBG_GPIO1") (class "Default")
      (node (ref "Q6") (pin "G1") (pinfunction "G1_G1") (pintype "input"))
      (node (ref "R76") (pin "2") (pinfunction "2_2") (pintype "passive"))
      (node (ref "U23") (pin "41") (pinfunction "PA21_41") (pintype "bidirectional"))
    )
    (net (code "156") (name "MOD2_DBG_GPIO2") (class "Default")
      (node (ref "Q6") (pin "G2") (pinfunction "G2_G2") (pintype "input"))
      (node (ref "R77") (pin "2") (pinfunction "2_2") (pintype "passive"))
      (node (ref "U23") (pin "42") (pinfunction "PA22_42") (pintype "bidirectional"))
    )
    (net (code "157") (name "MOD2_USB+") (class "Default")
      (node (ref "D35") (pin "6") (pinfunction "B_6") (pintype "bidirectional"))
      (node (ref "R10") (pin "1") (pinfunction "P$1_1") (pintype "passive"))
      (node (ref "R57") (pin "2") (pinfunction "2_2") (pintype "passive"))
      (node (ref "U23") (pin "47") (pinfunction "PA26_47") (pintype "bidirectional"))
    )
    (net (code "158") (name "MOD2_USB-") (class "Default")
      (node (ref "D35") (pin "8") (pinfunction "A_8") (pintype "bidirectional"))
      (node (ref "R5") (pin "1") (pinfunction "P$1_1") (pintype "passive"))
      (node (ref "R58") (pin "2") (pinfunction "2_2") (pintype "passive"))
      (node (ref "U23") (pin "46") (pinfunction "PA25_46") (pintype "bidirectional"))
    )
    (net (code "159") (name "MOD_SCL") (class "Default")
      (node (ref "J1") (pin "24") (pinfunction "MODULES_SCL_24") (pintype "bidirectional"))
      (node (ref "JP11") (pin "5") (pinfunction "5_5") (pintype "passive"))
      (node (ref "JP14") (pin "4") (pinfunction "4_4") (pintype "passive"))
      (node (ref "R46") (pin "1") (pinfunction "1_1") (pintype "passive"))
      (node (ref "U23") (pin "44") (pinfunction "PA24_44") (pintype "bidirectional"))
      (node (ref "U7") (pin "3") (pinfunction "A1_3") (pintype "bidirectional"))
      (node (ref "U8") (pin "3") (pinfunction "A1_3") (pintype "bidirectional"))
    )
    (net (code "160") (name "MOD_SDA") (class "Default")
      (node (ref "J1") (pin "23") (pinfunction "MODULES_SDA_23") (pintype "bidirectional"))
      (node (ref "JP11") (pin "6") (pinfunction "6_6") (pintype "passive"))
      (node (ref "JP14") (pin "3") (pinfunction "3_3") (pintype "passive"))
      (node (ref "R45") (pin "1") (pinfunction "1_1") (pintype "passive"))
      (node (ref "U23") (pin "43") (pinfunction "PA23_43") (pintype "bidirectional"))
      (node (ref "U7") (pin "2") (pinfunction "A0_2") (pintype "bidirectional"))
      (node (ref "U8") (pin "2") (pinfunction "A0_2") (pintype "bidirectional"))
    )
    (net (code "161") (name "MOD_USB_OVERRIDE_5V") (class "Default")
      (node (ref "J4") (pin "1") (pinfunction "+5V_1") (pintype "bidirectional"))
      (node (ref "Q1") (pin "G2") (pinfunction "G2_G2") (pintype "input"))
      (node (ref "R67") (pin "2") (pinfunction "2_2") (pintype "passive"))
    )
    (net (code "162") (name "MOD_USB_OVERRIDE_DM") (class "Default")
      (node (ref "J4") (pin "2") (pinfunction "D-_2") (pintype "bidirectional"))
      (node (ref "U30") (pin "1") (pinfunction "D1+_1") (pintype "bidirectional"))
    )
    (net (code "163") (name "MOD_USB_OVERRIDE_DP") (class "Default")
      (node (ref "J4") (pin "3") (pinfunction "D+_3") (pintype "bidirectional"))
      (node (ref "U30") (pin "7") (pinfunction "D1-_7") (pintype "bidirectional"))
    )
    (net (code "164") (name "Net-(C10-Pad2)") (class "Default")
      (node (ref "C10") (pin "2") (pinfunction "2_2") (pintype "bidirectional"))
      (node (ref "R28") (pin "1") (pinfunction "1_1") (pintype "passive"))
      (node (ref "Y1") (pin "1") (pinfunction "1_1") (pintype "bidirectional"))
    )
    (net (code "165") (name "Net-(C12-Pad2)") (class "Default")
      (node (ref "C12") (pin "2") (pinfunction "2_2") (pintype "bidirectional"))
      (node (ref "R30") (pin "1") (pinfunction "1_1") (pintype "passive"))
      (node (ref "Y2") (pin "1") (pinfunction "1_1") (pintype "bidirectional"))
    )
    (net (code "166") (name "Net-(D3D-CATHODE)") (class "Default")
      (node (ref "D3") (pin "4K") (pinfunction "CATHODE_4K") (pintype "bidirectional"))
      (node (ref "Q7") (pin "D2") (pinfunction "D2_D2") (pintype "bidirectional"))
    )
    (net (code "167") (name "Net-(D4-CATHODE)") (class "Default")
      (node (ref "D4") (pin "C") (pinfunction "CATHODE_C") (pintype "bidirectional"))
      (node (ref "R23") (pin "A2") (pinfunction "2_A2") (pintype "passive"))
    )
    (net (code "168") (name "Net-(D5-CATHODE)") (class "Default")
      (node (ref "D5") (pin "C") (pinfunction "CATHODE_C") (pintype "bidirectional"))
      (node (ref "R23") (pin "B2") (pinfunction "2_B2") (pintype "passive"))
    )
    (net (code "169") (name "Net-(D6-CATHODE)") (class "Default")
      (node (ref "D6") (pin "C") (pinfunction "CATHODE_C") (pintype "bidirectional"))
      (node (ref "R23") (pin "C2") (pinfunction "2_C2") (pintype "passive"))
    )
    (net (code "170") (name "Net-(D7-CATHODE)") (class "Default")
      (node (ref "D7") (pin "C") (pinfunction "CATHODE_C") (pintype "bidirectional"))
      (node (ref "R24") (pin "C2") (pinfunction "2_C2") (pintype "passive"))
    )
    (net (code "171") (name "Net-(D8-CATHODE)") (class "Default")
      (node (ref "D8") (pin "C") (pinfunction "CATHODE_C") (pintype "bidirectional"))
      (node (ref "R24") (pin "B2") (pinfunction "2_B2") (pintype "passive"))
    )
    (net (code "172") (name "Net-(D9-CATHODE)") (class "Default")
      (node (ref "D9") (pin "C") (pinfunction "CATHODE_C") (pintype "bidirectional"))
      (node (ref "R24") (pin "A2") (pinfunction "2_A2") (pintype "passive"))
    )
    (net (code "173") (name "Net-(D10-CATHODE)") (class "Default")
      (node (ref "D10") (pin "C") (pinfunction "CATHODE_C") (pintype "bidirectional"))
      (node (ref "R18") (pin "A2") (pinfunction "2_A2") (pintype "passive"))
    )
    (net (code "174") (name "Net-(D11-CATHODE)") (class "Default")
      (node (ref "D11") (pin "C") (pinfunction "CATHODE_C") (pintype "bidirectional"))
      (node (ref "R18") (pin "B2") (pinfunction "2_B2") (pintype "passive"))
    )
    (net (code "175") (name "Net-(D12-CATHODE)") (class "Default")
      (node (ref "D12") (pin "C") (pinfunction "CATHODE_C") (pintype "bidirectional"))
      (node (ref "R19") (pin "A2") (pinfunction "2_A2") (pintype "passive"))
    )
    (net (code "176") (name "Net-(D13-CATHODE)") (class "Default")
      (node (ref "D13") (pin "C") (pinfunction "CATHODE_C") (pintype "bidirectional"))
      (node (ref "R19") (pin "B2") (pinfunction "2_B2") (pintype "passive"))
    )
    (net (code "177") (name "Net-(D14-CATHODE)") (class "Default")
      (node (ref "D14") (pin "C") (pinfunction "CATHODE_C") (pintype "bidirectional"))
      (node (ref "R18") (pin "D2") (pinfunction "2_D2") (pintype "passive"))
    )
    (net (code "178") (name "Net-(D15-CATHODE)") (class "Default")
      (node (ref "D15") (pin "C") (pinfunction "CATHODE_C") (pintype "bidirectional"))
      (node (ref "R19") (pin "D2") (pinfunction "2_D2") (pintype "passive"))
    )
    (net (code "179") (name "Net-(D16-CATHODE)") (class "Default")
      (node (ref "D16") (pin "C") (pinfunction "CATHODE_C") (pintype "bidirectional"))
      (node (ref "R20") (pin "D2") (pinfunction "2_D2") (pintype "passive"))
    )
    (net (code "180") (name "Net-(D17-CATHODE)") (class "Default")
      (node (ref "D17") (pin "C") (pinfunction "CATHODE_C") (pintype "bidirectional"))
      (node (ref "R21") (pin "D2") (pinfunction "2_D2") (pintype "passive"))
    )
    (net (code "181") (name "Net-(D18-CATHODE)") (class "Default")
      (node (ref "D18") (pin "C") (pinfunction "CATHODE_C") (pintype "bidirectional"))
      (node (ref "R22") (pin "D2") (pinfunction "2_D2") (pintype "passive"))
    )
    (net (code "182") (name "Net-(D19-CATHODE)") (class "Default")
      (node (ref "D19") (pin "C") (pinfunction "CATHODE_C") (pintype "bidirectional"))
      (node (ref "R20") (pin "A2") (pinfunction "2_A2") (pintype "passive"))
    )
    (net (code "183") (name "Net-(D20-CATHODE)") (class "Default")
      (node (ref "D20") (pin "C") (pinfunction "CATHODE_C") (pintype "bidirectional"))
      (node (ref "R20") (pin "B2") (pinfunction "2_B2") (pintype "passive"))
    )
    (net (code "184") (name "Net-(D21-CATHODE)") (class "Default")
      (node (ref "D21") (pin "C") (pinfunction "CATHODE_C") (pintype "bidirectional"))
      (node (ref "R21") (pin "A2") (pinfunction "2_A2") (pintype "passive"))
    )
    (net (code "185") (name "Net-(D22-CATHODE)") (class "Default")
      (node (ref "D22") (pin "C") (pinfunction "CATHODE_C") (pintype "bidirectional"))
      (node (ref "R21") (pin "B2") (pinfunction "2_B2") (pintype "passive"))
    )
    (net (code "186") (name "Net-(D23-CATHODE)") (class "Default")
      (node (ref "D23") (pin "C") (pinfunction "CATHODE_C") (pintype "bidirectional"))
      (node (ref "R15") (pin "2") (pinfunction "2_2") (pintype "passive"))
    )
    (net (code "187") (name "Net-(D24-CATHODE)") (class "Default")
      (node (ref "D24") (pin "C") (pinfunction "CATHODE_C") (pintype "bidirectional"))
      (node (ref "R22") (pin "A2") (pinfunction "2_A2") (pintype "passive"))
    )
    (net (code "188") (name "Net-(D25-CATHODE)") (class "Default")
      (node (ref "D25") (pin "C") (pinfunction "CATHODE_C") (pintype "bidirectional"))
      (node (ref "R22") (pin "B2") (pinfunction "2_B2") (pintype "passive"))
    )
    (net (code "189") (name "Net-(D26-CATHODE)") (class "Default")
      (node (ref "D26") (pin "C") (pinfunction "CATHODE_C") (pintype "bidirectional"))
      (node (ref "R25") (pin "A1") (pinfunction "1_A1") (pintype "passive"))
    )
    (net (code "190") (name "Net-(D27-CATHODE)") (class "Default")
      (node (ref "D27") (pin "C") (pinfunction "CATHODE_C") (pintype "bidirectional"))
      (node (ref "R25") (pin "B1") (pinfunction "1_B1") (pintype "passive"))
    )
    (net (code "191") (name "Net-(D28-CATHODE)") (class "Default")
      (node (ref "D28") (pin "C") (pinfunction "CATHODE_C") (pintype "bidirectional"))
      (node (ref "R25") (pin "C1") (pinfunction "1_C1") (pintype "passive"))
    )
    (net (code "192") (name "Net-(D29-CATHODE)") (class "Default")
      (node (ref "D29") (pin "C") (pinfunction "CATHODE_C") (pintype "bidirectional"))
      (node (ref "R25") (pin "D1") (pinfunction "1_D1") (pintype "passive"))
    )
    (net (code "193") (name "Net-(D30-CATHODE)") (class "Default")
      (node (ref "D30") (pin "C") (pinfunction "CATHODE_C") (pintype "bidirectional"))
      (node (ref "R26") (pin "A1") (pinfunction "1_A1") (pintype "passive"))
    )
    (net (code "194") (name "Net-(D31-CATHODE)") (class "Default")
      (node (ref "D31") (pin "C") (pinfunction "CATHODE_C") (pintype "bidirectional"))
      (node (ref "R26") (pin "B1") (pinfunction "1_B1") (pintype "passive"))
    )
    (net (code "195") (name "Net-(D32-CATHODE)") (class "Default")
      (node (ref "D32") (pin "C") (pinfunction "CATHODE_C") (pintype "bidirectional"))
      (node (ref "R26") (pin "C1") (pinfunction "1_C1") (pintype "passive"))
    )
    (net (code "196") (name "Net-(D33-CATHODE)") (class "Default")
      (node (ref "D33") (pin "C") (pinfunction "CATHODE_C") (pintype "bidirectional"))
      (node (ref "R26") (pin "D1") (pinfunction "1_D1") (pintype "passive"))
    )
    (net (code "197") (name "Net-(D34-CATHODE)") (class "Default")
      (node (ref "D34") (pin "C") (pinfunction "CATHODE_C") (pintype "bidirectional"))
      (node (ref "R16") (pin "2") (pinfunction "2_2") (pintype "passive"))
    )
    (net (code "198") (name "Net-(FB1-P$1)") (class "Default")
      (node (ref "C39") (pin "1") (pinfunction "1_1") (pintype "bidirectional"))
      (node (ref "FB1") (pin "1") (pinfunction "P$1_1") (pintype "bidirectional"))
      (node (ref "U23") (pin "19") (pinfunction "VDDANA_19") (pintype "power_in"))
    )
    (net (code "199") (name "Net-(J1B-VCC_CONTROLLER)") (class "Default")
      (node (ref "J1") (pin "2") (pinfunction "VCC_CONTROLLER_2") (pintype "bidirectional"))
      (node (ref "SJ4") (pin "1") (pinfunction "1_1") (pintype "passive"))
      (node (ref "TP8") (pin "TESTPOINT") (pinfunction "TESTPOINT_TESTPOINT") (pintype "bidirectional"))
    )
    (net (code "200") (name "Net-(J1B-VCC_LINUX)") (class "Default")
      (node (ref "J1") (pin "4") (pinfunction "VCC_LINUX_4") (pintype "bidirectional"))
      (node (ref "SJ5") (pin "1") (pinfunction "1_1") (pintype "passive"))
      (node (ref "TP10") (pin "TESTPOINT") (pinfunction "TESTPOINT_TESTPOINT") (pintype "bidirectional"))
    )
    (net (code "201") (name "Net-(J2-5V)") (class "Default")
      (node (ref "J2") (pin "2") (pinfunction "5V_2") (pintype "bidirectional"))
      (node (ref "SJ2") (pin "1") (pinfunction "1_1") (pintype "passive"))
      (node (ref "TP4") (pin "TESTPOINT") (pinfunction "TESTPOINT_TESTPOINT") (pintype "bidirectional"))
    )
    (net (code "202") (name "Net-(J3-5V)") (class "Default")
      (node (ref "J3") (pin "2") (pinfunction "5V_2") (pintype "bidirectional"))
      (node (ref "SJ3") (pin "1") (pinfunction "1_1") (pintype "passive"))
      (node (ref "TP6") (pin "TESTPOINT") (pinfunction "TESTPOINT_TESTPOINT") (pintype "bidirectional"))
    )
    (net (code "203") (name "Net-(J7-VCC)") (class "Default")
      (node (ref "J7") (pin "1") (pinfunction "VCC_1") (pintype "bidirectional"))
      (node (ref "Q8") (pin "3") (pinfunction "D_3") (pintype "passive"))
      (node (ref "U13") (pin "1") (pinfunction "IN_1") (pintype "bidirectional"))
    )
    (net (code "204") (name "Net-(JP19-Pad1)") (class "Default")
      (node (ref "JP19") (pin "1") (pinfunction "1_1") (pintype "passive"))
      (node (ref "JP20") (pin "1") (pinfunction "1_1") (pintype "passive"))
    )
    (net (code "205") (name "Net-(JP19-Pad2)") (class "Default")
      (node (ref "JP19") (pin "2") (pinfunction "2_2") (pintype "passive"))
      (node (ref "JP20") (pin "2") (pinfunction "2_2") (pintype "passive"))
    )
    (net (code "206") (name "Net-(JP19-Pad3)") (class "Default")
      (node (ref "JP19") (pin "3") (pinfunction "3_3") (pintype "passive"))
      (node (ref "JP20") (pin "3") (pinfunction "3_3") (pintype "passive"))
    )
    (net (code "207") (name "Net-(JP19-Pad4)") (class "Default")
      (node (ref "JP19") (pin "4") (pinfunction "4_4") (pintype "passive"))
      (node (ref "JP20") (pin "4") (pinfunction "4_4") (pintype "passive"))
    )
    (net (code "208") (name "Net-(JP19-Pad5)") (class "Default")
      (node (ref "JP19") (pin "5") (pinfunction "5_5") (pintype "passive"))
      (node (ref "JP20") (pin "5") (pinfunction "5_5") (pintype "passive"))
    )
    (net (code "209") (name "Net-(JP19-Pad6)") (class "Default")
      (node (ref "JP19") (pin "6") (pinfunction "6_6") (pintype "passive"))
      (node (ref "JP20") (pin "6") (pinfunction "6_6") (pintype "passive"))
    )
    (net (code "210") (name "Net-(JP19-Pad7)") (class "Default")
      (node (ref "JP19") (pin "7") (pinfunction "7_7") (pintype "passive"))
      (node (ref "JP20") (pin "7") (pinfunction "7_7") (pintype "passive"))
    )
    (net (code "211") (name "Net-(JP19-Pad8)") (class "Default")
      (node (ref "JP19") (pin "8") (pinfunction "8_8") (pintype "passive"))
      (node (ref "JP20") (pin "8") (pinfunction "8_8") (pintype "passive"))
    )
    (net (code "212") (name "Net-(JP19-Pad9)") (class "Default")
      (node (ref "JP19") (pin "9") (pinfunction "9_9") (pintype "passive"))
      (node (ref "JP20") (pin "9") (pinfunction "9_9") (pintype "passive"))
    )
    (net (code "213") (name "Net-(JP19-Pad10)") (class "Default")
      (node (ref "JP19") (pin "10") (pinfunction "10_10") (pintype "passive"))
      (node (ref "JP20") (pin "10") (pinfunction "10_10") (pintype "passive"))
    )
    (net (code "214") (name "Net-(JP19-Pad11)") (class "Default")
      (node (ref "JP19") (pin "11") (pinfunction "11_11") (pintype "passive"))
      (node (ref "JP20") (pin "11") (pinfunction "11_11") (pintype "passive"))
    )
    (net (code "215") (name "Net-(JP19-Pad12)") (class "Default")
      (node (ref "JP19") (pin "12") (pinfunction "12_12") (pintype "passive"))
      (node (ref "JP20") (pin "12") (pinfunction "12_12") (pintype "passive"))
    )
    (net (code "216") (name "Net-(JP19-Pad13)") (class "Default")
      (node (ref "JP19") (pin "13") (pinfunction "13_13") (pintype "passive"))
      (node (ref "JP20") (pin "13") (pinfunction "13_13") (pintype "passive"))
    )
    (net (code "217") (name "Net-(JP19-Pad14)") (class "Default")
      (node (ref "JP19") (pin "14") (pinfunction "14_14") (pintype "passive"))
      (node (ref "JP20") (pin "14") (pinfunction "14_14") (pintype "passive"))
    )
    (net (code "218") (name "Net-(JP19-Pad15)") (class "Default")
      (node (ref "JP19") (pin "15") (pinfunction "15_15") (pintype "passive"))
      (node (ref "JP20") (pin "15") (pinfunction "15_15") (pintype "passive"))
    )
    (net (code "219") (name "Net-(JP19-Pad16)") (class "Default")
      (node (ref "JP19") (pin "16") (pinfunction "16_16") (pintype "passive"))
      (node (ref "JP20") (pin "16") (pinfunction "16_16") (pintype "passive"))
    )
    (net (code "220") (name "Net-(JP19-Pad18)") (class "Default")
      (node (ref "JP19") (pin "18") (pinfunction "18_18") (pintype "passive"))
      (node (ref "JP20") (pin "18") (pinfunction "18_18") (pintype "passive"))
    )
    (net (code "221") (name "Net-(JP19-Pad20)") (class "Default")
      (node (ref "JP19") (pin "20") (pinfunction "20_20") (pintype "passive"))
      (node (ref "JP20") (pin "20") (pinfunction "20_20") (pintype "passive"))
    )
    (net (code "222") (name "Net-(L1-1)") (class "Default")
      (node (ref "L1") (pin "P$1") (pinfunction "1_P$1") (pintype "bidirectional"))
      (node (ref "U23") (pin "7") (pinfunction "VDDOUT_7") (pintype "power_in"))
    )
    (net (code "223") (name "Net-(L1-2)") (class "Default")
      (node (ref "C63") (pin "1") (pinfunction "1_1") (pintype "bidirectional"))
      (node (ref "C73") (pin "1") (pinfunction "1_1") (pintype "bidirectional"))
      (node (ref "L1") (pin "P$2") (pinfunction "2_P$2") (pintype "bidirectional"))
      (node (ref "U23") (pin "5") (pinfunction "VDDCORE_5") (pintype "power_in"))
    )
    (net (code "224") (name "Net-(Q7-PadD1)") (class "Default")
      (node (ref "Q7") (pin "D1") (pinfunction "D1_D1") (pintype "bidirectional"))
      (node (ref "R16") (pin "1") (pinfunction "1_1") (pintype "passive"))
    )
    (net (code "225") (name "Net-(Q8-G)") (class "Default")
      (node (ref "Q8") (pin "1") (pinfunction "G_1") (pintype "passive"))
      (node (ref "U13") (pin "8") (pinfunction "GATE_8") (pintype "bidirectional"))
    )
    (net (code "226") (name "Net-(R15-Pad1)") (class "Default")
      (node (ref "R15") (pin "1") (pinfunction "1_1") (pintype "passive"))
      (node (ref "R17") (pin "2") (pinfunction "2_2") (pintype "passive"))
    )
    (net (code "227") (name "Net-(R18A-1)") (class "Default")
      (node (ref "Q2") (pin "D1") (pinfunction "D1_D1") (pintype "bidirectional"))
      (node (ref "R18") (pin "A1") (pinfunction "1_A1") (pintype "passive"))
    )
    (net (code "228") (name "Net-(R18B-1)") (class "Default")
      (node (ref "Q2") (pin "D2") (pinfunction "D2_D2") (pintype "bidirectional"))
      (node (ref "R18") (pin "B1") (pinfunction "1_B1") (pintype "passive"))
    )
    (net (code "229") (name "Net-(R19A-1)") (class "Default")
      (node (ref "Q3") (pin "D1") (pinfunction "D1_D1") (pintype "bidirectional"))
      (node (ref "R19") (pin "A1") (pinfunction "1_A1") (pintype "passive"))
    )
    (net (code "230") (name "Net-(R19B-1)") (class "Default")
      (node (ref "Q3") (pin "D2") (pinfunction "D2_D2") (pintype "bidirectional"))
      (node (ref "R19") (pin "B1") (pinfunction "1_B1") (pintype "passive"))
    )
    (net (code "231") (name "Net-(R20A-1)") (class "Default")
      (node (ref "Q4") (pin "D1") (pinfunction "D1_D1") (pintype "bidirectional"))
      (node (ref "R20") (pin "A1") (pinfunction "1_A1") (pintype "passive"))
    )
    (net (code "232") (name "Net-(R20B-1)") (class "Default")
      (node (ref "Q4") (pin "D2") (pinfunction "D2_D2") (pintype "bidirectional"))
      (node (ref "R20") (pin "B1") (pinfunction "1_B1") (pintype "passive"))
    )
    (net (code "233") (name "Net-(R21A-1)") (class "Default")
      (node (ref "Q5") (pin "D1") (pinfunction "D1_D1") (pintype "bidirectional"))
      (node (ref "R21") (pin "A1") (pinfunction "1_A1") (pintype "passive"))
    )
    (net (code "234") (name "Net-(R21B-1)") (class "Default")
      (node (ref "Q5") (pin "D2") (pinfunction "D2_D2") (pintype "bidirectional"))
      (node (ref "R21") (pin "B1") (pinfunction "1_B1") (pintype "passive"))
    )
    (net (code "235") (name "Net-(R22A-1)") (class "Default")
      (node (ref "Q6") (pin "D1") (pinfunction "D1_D1") (pintype "bidirectional"))
      (node (ref "R22") (pin "A1") (pinfunction "1_A1") (pintype "passive"))
    )
    (net (code "236") (name "Net-(R22B-1)") (class "Default")
      (node (ref "Q6") (pin "D2") (pinfunction "D2_D2") (pintype "bidirectional"))
      (node (ref "R22") (pin "B1") (pinfunction "1_B1") (pintype "passive"))
    )
    (net (code "237") (name "Net-(R31A-1)") (class "Default")
      (node (ref "R31") (pin "A1") (pinfunction "1_A1") (pintype "passive"))
      (node (ref "U22") (pin "6") (pinfunction "SC0_6") (pintype "bidirectional"))
      (node (ref "U9") (pin "3") (pinfunction "SCL_3") (pintype "open_collector"))
    )
    (net (code "238") (name "Net-(R31B-1)") (class "Default")
      (node (ref "R31") (pin "B1") (pinfunction "1_B1") (pintype "passive"))
      (node (ref "U22") (pin "5") (pinfunction "SD0_5") (pintype "bidirectional"))
      (node (ref "U9") (pin "4") (pinfunction "SDA_4") (pintype "open_collector"))
    )
    (net (code "239") (name "Net-(R31C-1)") (class "Default")
      (node (ref "R31") (pin "C1") (pinfunction "1_C1") (pintype "passive"))
      (node (ref "U22") (pin "4") (pinfunction "~{INT0}_4") (pintype "bidirectional"))
      (node (ref "U9") (pin "5") (pinfunction "~{ALERT}_5") (pintype "open_collector"))
    )
    (net (code "240") (name "Net-(R32A-1)") (class "Default")
      (node (ref "R32") (pin "A1") (pinfunction "1_A1") (pintype "passive"))
      (node (ref "U10") (pin "P4") (pinfunction "SCL_P4") (pintype "open_collector"))
      (node (ref "U22") (pin "9") (pinfunction "SC1_9") (pintype "bidirectional"))
    )
    (net (code "241") (name "Net-(R32B-1)") (class "Default")
      (node (ref "R32") (pin "B1") (pinfunction "1_B1") (pintype "passive"))
      (node (ref "U10") (pin "P5") (pinfunction "SDA_P5") (pintype "open_collector"))
      (node (ref "U22") (pin "8") (pinfunction "SD1_8") (pintype "bidirectional"))
    )
    (net (code "242") (name "Net-(R32C-1)") (class "Default")
      (node (ref "R32") (pin "C1") (pinfunction "1_C1") (pintype "passive"))
      (node (ref "U10") (pin "P6") (pinfunction "~{ALERT}_P6") (pintype "open_collector"))
      (node (ref "U22") (pin "7") (pinfunction "~{INT1}_7") (pintype "bidirectional"))
    )
    (net (code "243") (name "Net-(R33A-1)") (class "Default")
      (node (ref "R33") (pin "A1") (pinfunction "1_A1") (pintype "passive"))
      (node (ref "U11") (pin "P4") (pinfunction "SCL_P4") (pintype "open_collector"))
      (node (ref "U22") (pin "13") (pinfunction "SC2_13") (pintype "bidirectional"))
    )
    (net (code "244") (name "Net-(R33B-1)") (class "Default")
      (node (ref "R33") (pin "B1") (pinfunction "1_B1") (pintype "passive"))
      (node (ref "U11") (pin "P5") (pinfunction "SDA_P5") (pintype "open_collector"))
      (node (ref "U22") (pin "12") (pinfunction "SD2_12") (pintype "bidirectional"))
    )
    (net (code "245") (name "Net-(R33C-1)") (class "Default")
      (node (ref "R33") (pin "C1") (pinfunction "1_C1") (pintype "passive"))
      (node (ref "U11") (pin "P6") (pinfunction "~{ALERT}_P6") (pintype "open_collector"))
      (node (ref "U22") (pin "11") (pinfunction "~{INT2}_11") (pintype "bidirectional"))
    )
    (net (code "246") (name "Net-(R34A-1)") (class "Default")
      (node (ref "R34") (pin "A1") (pinfunction "1_A1") (pintype "passive"))
      (node (ref "U12") (pin "P4") (pinfunction "SCL_P4") (pintype "open_collector"))
      (node (ref "U22") (pin "16") (pinfunction "SC3_16") (pintype "bidirectional"))
    )
    (net (code "247") (name "Net-(R34B-1)") (class "Default")
      (node (ref "R34") (pin "B1") (pinfunction "1_B1") (pintype "passive"))
      (node (ref "U12") (pin "P5") (pinfunction "SDA_P5") (pintype "open_collector"))
      (node (ref "U22") (pin "15") (pinfunction "SD3_15") (pintype "bidirectional"))
    )
    (net (code "248") (name "Net-(R34C-1)") (class "Default")
      (node (ref "R34") (pin "C1") (pinfunction "1_C1") (pintype "passive"))
      (node (ref "U12") (pin "P6") (pinfunction "~{ALERT}_P6") (pintype "open_collector"))
      (node (ref "U22") (pin "14") (pinfunction "~{INT3}_14") (pintype "bidirectional"))
    )
    (net (code "249") (name "Net-(S21-2TA)") (class "Default")
      (node (ref "R80") (pin "2") (pinfunction "2_2") (pintype "passive"))
      (node (ref "S21") (pin "A2") (pinfunction "2TA_A2") (pintype "bidirectional"))
      (node (ref "U17") (pin "11") (pinfunction "P2_11") (pintype "bidirectional"))
    )
    (net (code "250") (name "Net-(S21-3TA)") (class "Default")
      (node (ref "R79") (pin "2") (pinfunction "2_2") (pintype "passive"))
      (node (ref "S21") (pin "A3") (pinfunction "3TA_A3") (pintype "bidirectional"))
      (node (ref "U17") (pin "10") (pinfunction "P1_10") (pintype "bidirectional"))
    )
    (net (code "251") (name "Net-(S21-4TA)") (class "Default")
      (node (ref "R78") (pin "2") (pinfunction "2_2") (pintype "passive"))
      (node (ref "S21") (pin "A4") (pinfunction "4TA_A4") (pintype "bidirectional"))
      (node (ref "U17") (pin "9") (pinfunction "P0_9") (pintype "bidirectional"))
    )
    (net (code "252") (name "Net-(S22-2TA)") (class "Default")
      (node (ref "R83") (pin "2") (pinfunction "2_2") (pintype "passive"))
      (node (ref "S22") (pin "A2") (pinfunction "2TA_A2") (pintype "bidirectional"))
      (node (ref "U18") (pin "11") (pinfunction "P2_11") (pintype "bidirectional"))
    )
    (net (code "253") (name "Net-(S22-3TA)") (class "Default")
      (node (ref "R82") (pin "2") (pinfunction "2_2") (pintype "passive"))
      (node (ref "S22") (pin "A3") (pinfunction "3TA_A3") (pintype "bidirectional"))
      (node (ref "U18") (pin "10") (pinfunction "P1_10") (pintype "bidirectional"))
    )
    (net (code "254") (name "Net-(S22-4TA)") (class "Default")
      (node (ref "R81") (pin "2") (pinfunction "2_2") (pintype "passive"))
      (node (ref "S22") (pin "A4") (pinfunction "4TA_A4") (pintype "bidirectional"))
      (node (ref "U18") (pin "9") (pinfunction "P0_9") (pintype "bidirectional"))
    )
    (net (code "255") (name "Net-(S23-B)") (class "Default")
      (node (ref "C64") (pin "1") (pinfunction "1_1") (pintype "bidirectional"))
      (node (ref "S23") (pin "2") (pinfunction "B_2") (pintype "bidirectional"))
    )
    (net (code "256") (name "Net-(U1-3V3OUT)") (class "Default")
      (node (ref "C44") (pin "1") (pinfunction "1_1") (pintype "bidirectional"))
      (node (ref "U1") (pin "16") (pinfunction "3V3OUT_16") (pintype "output"))
    )
    (net (code "257") (name "Net-(U2-3V3OUT)") (class "Default")
      (node (ref "C45") (pin "1") (pinfunction "1_1") (pintype "bidirectional"))
      (node (ref "U2") (pin "16") (pinfunction "3V3OUT_16") (pintype "output"))
    )
    (net (code "258") (name "Net-(U3-3V3OUT)") (class "Default")
      (node (ref "C47") (pin "1") (pinfunction "1_1") (pintype "bidirectional"))
      (node (ref "U3") (pin "16") (pinfunction "3V3OUT_16") (pintype "output"))
    )
    (net (code "259") (name "Net-(U4-3V3OUT)") (class "Default")
      (node (ref "C49") (pin "1") (pinfunction "1_1") (pintype "bidirectional"))
      (node (ref "U4") (pin "16") (pinfunction "3V3OUT_16") (pintype "output"))
    )
    (net (code "260") (name "Net-(U5-3V3OUT)") (class "Default")
      (node (ref "C51") (pin "1") (pinfunction "1_1") (pintype "bidirectional"))
      (node (ref "U5") (pin "16") (pinfunction "3V3OUT_16") (pintype "output"))
    )
    (net (code "261") (name "Net-(U6-3V3OUT)") (class "Default")
      (node (ref "C56") (pin "1") (pinfunction "1_1") (pintype "bidirectional"))
      (node (ref "U6") (pin "16") (pinfunction "3V3OUT_16") (pintype "output"))
    )
    (net (code "262") (name "Net-(U13-~{PWRGD})") (class "Default")
      (node (ref "R17") (pin "1") (pinfunction "1_1") (pintype "passive"))
      (node (ref "U13") (pin "5") (pinfunction "~{PWRGD}_5") (pintype "bidirectional"))
    )
    (net (code "263") (name "Net-(U14-~{WC})") (class "Default")
      (node (ref "SJ1") (pin "2") (pinfunction "2_2") (pintype "passive"))
      (node (ref "U14") (pin "7") (pinfunction "~{WC}_7") (pintype "bidirectional"))
    )
    (net (code "264") (name "Net-(U15-SRT)") (class "Default")
      (node (ref "C65") (pin "1") (pinfunction "1_1") (pintype "bidirectional"))
      (node (ref "U15") (pin "3") (pinfunction "SRT_3") (pintype "bidirectional"))
    )
    (net (code "265") (name "Net-(U15-SWT)") (class "Default")
      (node (ref "S23") (pin "IN") (pinfunction "IN_IN") (pintype "bidirectional"))
      (node (ref "U15") (pin "2") (pinfunction "SWT_2") (pintype "bidirectional"))
    )
    (net (code "266") (name "Net-(U15-~{MR})") (class "Default")
      (node (ref "S8") (pin "3") (pinfunction "P$2_3") (pintype "passive"))
      (node (ref "S8") (pin "4") (pinfunction "P$2_4") (pintype "passive"))
      (node (ref "U15") (pin "1") (pinfunction "~{MR}_1") (pintype "bidirectional"))
    )
    (net (code "267") (name "Net-(U15-~{RESET})") (class "Default")
      (node (ref "Q7") (pin "G1") (pinfunction "G1_G1") (pintype "input"))
      (node (ref "Q7") (pin "G2") (pinfunction "G2_G2") (pintype "input"))
      (node (ref "U15") (pin "7") (pinfunction "~{RESET}_7") (pintype "bidirectional"))
    )
    (net (code "268") (name "Net-(U16-BP)") (class "Default")
      (node (ref "C13") (pin "1") (pinfunction "1_1") (pintype "bidirectional"))
      (node (ref "U16") (pin "4") (pinfunction "BP_4") (pintype "bidirectional"))
    )
    (net (code "269") (name "Net-(U16-~{SHDN})") (class "Default")
      (node (ref "R47") (pin "1") (pinfunction "1_1") (pintype "passive"))
      (node (ref "U16") (pin "3") (pinfunction "~{SHDN}_3") (pintype "bidirectional"))
    )
    (net (code "270") (name "Net-(U23-BIASH)") (class "Default")
      (node (ref "U23") (pin "28") (pinfunction "BIASH_28") (pintype "bidirectional"))
      (node (ref "U23") (pin "29") (pinfunction "BIASL_29") (pintype "bidirectional"))
    )
    (net (code "271") (name "Net-(U23-CAPH)") (class "Default")
      (node (ref "U23") (pin "25") (pinfunction "CAPH_25") (pintype "bidirectional"))
      (node (ref "U23") (pin "26") (pinfunction "CAPL_26") (pintype "bidirectional"))
    )
    (net (code "272") (name "Net-(U23-PA02)") (class "Default")
      (node (ref "R48") (pin "2") (pinfunction "2_2") (pintype "passive"))
      (node (ref "R84") (pin "1") (pinfunction "1_1") (pintype "passive"))
      (node (ref "U23") (pin "3") (pinfunction "PA02_3") (pintype "bidirectional"))
    )
    (net (code "273") (name "Net-(U28-D2+)") (class "Default")
      (node (ref "R11") (pin "1") (pinfunction "1_1") (pintype "passive"))
      (node (ref "U28") (pin "2") (pinfunction "D2+_2") (pintype "bidirectional"))
    )
    (net (code "274") (name "Net-(U28-D2-)") (class "Default")
      (node (ref "R12") (pin "1") (pinfunction "1_1") (pintype "passive"))
      (node (ref "U28") (pin "6") (pinfunction "D2-_6") (pintype "bidirectional"))
    )
    (net (code "275") (name "Net-(U29-D2+)") (class "Default")
      (node (ref "R13") (pin "1") (pinfunction "1_1") (pintype "passive"))
      (node (ref "U29") (pin "2") (pinfunction "D2+_2") (pintype "bidirectional"))
    )
    (net (code "276") (name "Net-(U29-D2-)") (class "Default")
      (node (ref "R14") (pin "1") (pinfunction "1_1") (pintype "passive"))
      (node (ref "U29") (pin "6") (pinfunction "D2-_6") (pintype "bidirectional"))
    )
    (net (code "277") (name "Net-(U30-S)") (class "Default")
      (node (ref "Q1") (pin "D2") (pinfunction "D2_D2") (pintype "bidirectional"))
      (node (ref "R66") (pin "1") (pinfunction "1_1") (pintype "passive"))
      (node (ref "U30") (pin "10") (pinfunction "S_10") (pintype "bidirectional"))
    )
    (net (code "278") (name "Net-(U31-DP0PUR)") (class "Default")
      (node (ref "R27") (pin "2") (pinfunction "2_2") (pintype "passive"))
      (node (ref "U31") (pin "2") (pinfunction "DP0PUR_2") (pintype "bidirectional"))
    )
    (net (code "279") (name "Net-(U31-XTAL1)") (class "Default")
      (node (ref "C9") (pin "2") (pinfunction "2_2") (pintype "bidirectional"))
      (node (ref "U31") (pin "45") (pinfunction "XTAL1_45") (pintype "bidirectional"))
      (node (ref "Y1") (pin "3") (pinfunction "2_3") (pintype "bidirectional"))
    )
    (net (code "280") (name "Net-(U31-XTAL2)") (class "Default")
      (node (ref "R28") (pin "2") (pinfunction "2_2") (pintype "passive"))
      (node (ref "U31") (pin "44") (pinfunction "XTAL2_44") (pintype "bidirectional"))
    )
    (net (code "281") (name "Net-(U32-DP0PUR)") (class "Default")
      (node (ref "R29") (pin "2") (pinfunction "2_2") (pintype "passive"))
      (node (ref "U32") (pin "2") (pinfunction "DP0PUR_2") (pintype "bidirectional"))
    )
    (net (code "282") (name "Net-(U32-XTAL1)") (class "Default")
      (node (ref "C11") (pin "2") (pinfunction "2_2") (pintype "bidirectional"))
      (node (ref "U32") (pin "45") (pinfunction "XTAL1_45") (pintype "bidirectional"))
      (node (ref "Y2") (pin "3") (pinfunction "2_3") (pintype "bidirectional"))
    )
    (net (code "283") (name "Net-(U32-XTAL2)") (class "Default")
      (node (ref "R30") (pin "2") (pinfunction "2_2") (pintype "passive"))
      (node (ref "U32") (pin "44") (pinfunction "XTAL2_44") (pintype "bidirectional"))
    )
    (net (code "284") (name "Net-(U32-~{PWRON1})") (class "Default")
      (node (ref "TP12") (pin "TESTPOINT") (pinfunction "TESTPOINT_TESTPOINT") (pintype "bidirectional"))
      (node (ref "U32") (pin "11") (pinfunction "~{PWRON1}_11") (pintype "bidirectional"))
    )
    (net (code "285") (name "PPS") (class "Default")
      (node (ref "J1") (pin "25") (pinfunction "PPS_25") (pintype "bidirectional"))
      (node (ref "JP11") (pin "4") (pinfunction "4_4") (pintype "passive"))
      (node (ref "JP14") (pin "5") (pinfunction "5_5") (pintype "passive"))
      (node (ref "U23") (pin "37") (pinfunction "PA18_37") (pintype "bidirectional"))
      (node (ref "U24") (pin "3") (pinfunction "A2_3") (pintype "bidirectional"))
      (node (ref "U25") (pin "3") (pinfunction "A2_3") (pintype "bidirectional"))
    )
    (net (code "286") (name "PROG0_EN") (class "Default")
      (node (ref "D14") (pin "A") (pinfunction "ANODE_A") (pintype "bidirectional"))
      (node (ref "R18") (pin "C2") (pinfunction "2_C2") (pintype "passive"))
      (node (ref "S11") (pin "1") (pinfunction "A_1") (pintype "bidirectional"))
      (node (ref "S14") (pin "12") (pinfunction "CTRL_12") (pintype "bidirectional"))
      (node (ref "S14") (pin "13") (pinfunction "CTRL_13") (pintype "bidirectional"))
      (node (ref "S14") (pin "5") (pinfunction "CTRL_5") (pintype "bidirectional"))
      (node (ref "S14") (pin "6") (pinfunction "CTRL_6") (pintype "bidirectional"))
    )
    (net (code "287") (name "PROG1_EN") (class "Default")
      (node (ref "D15") (pin "A") (pinfunction "ANODE_A") (pintype "bidirectional"))
      (node (ref "R19") (pin "C2") (pinfunction "2_C2") (pintype "passive"))
      (node (ref "S11") (pin "2") (pinfunction "B_2") (pintype "bidirectional"))
      (node (ref "S15") (pin "12") (pinfunction "CTRL_12") (pintype "bidirectional"))
      (node (ref "S15") (pin "13") (pinfunction "CTRL_13") (pintype "bidirectional"))
      (node (ref "S15") (pin "5") (pinfunction "CTRL_5") (pintype "bidirectional"))
      (node (ref "S15") (pin "6") (pinfunction "CTRL_6") (pintype "bidirectional"))
    )
    (net (code "288") (name "PROG2_EN") (class "Default")
      (node (ref "D16") (pin "A") (pinfunction "ANODE_A") (pintype "bidirectional"))
      (node (ref "R20") (pin "C2") (pinfunction "2_C2") (pintype "passive"))
      (node (ref "S11") (pin "3") (pinfunction "C_3") (pintype "bidirectional"))
      (node (ref "S16") (pin "12") (pinfunction "CTRL_12") (pintype "bidirectional"))
      (node (ref "S16") (pin "13") (pinfunction "CTRL_13") (pintype "bidirectional"))
      (node (ref "S16") (pin "5") (pinfunction "CTRL_5") (pintype "bidirectional"))
      (node (ref "S16") (pin "6") (pinfunction "CTRL_6") (pintype "bidirectional"))
    )
    (net (code "289") (name "PROG3_EN") (class "Default")
      (node (ref "D17") (pin "A") (pinfunction "ANODE_A") (pintype "bidirectional"))
      (node (ref "R21") (pin "C2") (pinfunction "2_C2") (pintype "passive"))
      (node (ref "S11") (pin "4") (pinfunction "D_4") (pintype "bidirectional"))
      (node (ref "S17") (pin "12") (pinfunction "CTRL_12") (pintype "bidirectional"))
      (node (ref "S17") (pin "13") (pinfunction "CTRL_13") (pintype "bidirectional"))
      (node (ref "S17") (pin "5") (pinfunction "CTRL_5") (pintype "bidirectional"))
      (node (ref "S17") (pin "6") (pinfunction "CTRL_6") (pintype "bidirectional"))
    )
    (net (code "290") (name "PROG4_EN") (class "Default")
      (node (ref "D18") (pin "A") (pinfunction "ANODE_A") (pintype "bidirectional"))
      (node (ref "R22") (pin "C2") (pinfunction "2_C2") (pintype "passive"))
      (node (ref "S11") (pin "5") (pinfunction "E_5") (pintype "bidirectional"))
      (node (ref "S18") (pin "12") (pinfunction "CTRL_12") (pintype "bidirectional"))
      (node (ref "S18") (pin "13") (pinfunction "CTRL_13") (pintype "bidirectional"))
      (node (ref "S18") (pin "5") (pinfunction "CTRL_5") (pintype "bidirectional"))
      (node (ref "S18") (pin "6") (pinfunction "CTRL_6") (pintype "bidirectional"))
    )
    (net (code "291") (name "RADIO_DEBUG_RX") (class "Default")
      (node (ref "U23") (pin "34") (pinfunction "PA15_34") (pintype "bidirectional"))
      (node (ref "U6") (pin "30") (pinfunction "TXD_30") (pintype "output"))
    )
    (net (code "292") (name "RADIO_DEBUG_TX") (class "Default")
      (node (ref "U23") (pin "35") (pinfunction "PA16_35") (pintype "bidirectional"))
      (node (ref "U6") (pin "2") (pinfunction "RXD_2") (pintype "input"))
    )
    (net (code "293") (name "RADIO_SWDCLK") (class "Default")
      (node (ref "R65") (pin "1") (pinfunction "1_1") (pintype "passive"))
      (node (ref "S18") (pin "3") (pinfunction "A_3") (pintype "bidirectional"))
      (node (ref "U23") (pin "9") (pinfunction "TCK_9") (pintype "bidirectional"))
    )
    (net (code "294") (name "RADIO_SWDIO") (class "Default")
      (node (ref "R64") (pin "1") (pinfunction "1_1") (pintype "passive"))
      (node (ref "S18") (pin "2") (pinfunction "A_2") (pintype "bidirectional"))
      (node (ref "U23") (pin "10") (pinfunction "PA03_10") (pintype "bidirectional"))
    )
    (net (code "295") (name "RADIO_UPLINK_RX") (class "Default")
      (node (ref "U1") (pin "30") (pinfunction "TXD_30") (pintype "output"))
      (node (ref "U23") (pin "23") (pinfunction "PA11_23") (pintype "bidirectional"))
    )
    (net (code "296") (name "RADIO_UPLINK_TX") (class "Default")
      (node (ref "U1") (pin "2") (pinfunction "RXD_2") (pintype "input"))
      (node (ref "U23") (pin "24") (pinfunction "PA12_24") (pintype "bidirectional"))
    )
    (net (code "297") (name "RADIO_~{RESET}") (class "Default")
      (node (ref "D2") (pin "1A") (pinfunction "ANODE_1A") (pintype "bidirectional"))
      (node (ref "S18") (pin "9") (pinfunction "A_9") (pintype "bidirectional"))
      (node (ref "S7") (pin "3") (pinfunction "P$2_3") (pintype "passive"))
      (node (ref "S7") (pin "4") (pinfunction "P$2_4") (pintype "passive"))
      (node (ref "U23") (pin "4") (pinfunction "~{RESET}_4") (pintype "bidirectional"))
    )
    (net (code "298") (name "SMBCLK") (class "Default")
      (node (ref "J1") (pin "5") (pinfunction "SMBCLK_5") (pintype "bidirectional"))
      (node (ref "J8") (pin "1") (pinfunction "SCL_1") (pintype "bidirectional"))
      (node (ref "JP11") (pin "7") (pinfunction "7_7") (pintype "passive"))
      (node (ref "JP12") (pin "5") (pinfunction "5_5") (pintype "passive"))
      (node (ref "R43") (pin "1") (pinfunction "1_1") (pintype "passive"))
      (node (ref "U14") (pin "6") (pinfunction "SCL_6") (pintype "bidirectional"))
      (node (ref "U17") (pin "19") (pinfunction "SCL_19") (pintype "bidirectional"))
      (node (ref "U18") (pin "19") (pinfunction "SCL_19") (pintype "bidirectional"))
      (node (ref "U19") (pin "19") (pinfunction "SCL_19") (pintype "bidirectional"))
      (node (ref "U22") (pin "18") (pinfunction "SCL_18") (pintype "bidirectional"))
    )
    (net (code "299") (name "SMBDATA") (class "Default")
      (node (ref "J1") (pin "3") (pinfunction "SMBDATA_3") (pintype "bidirectional"))
      (node (ref "J8") (pin "5") (pinfunction "SDA_5") (pintype "bidirectional"))
      (node (ref "JP11") (pin "8") (pinfunction "8_8") (pintype "passive"))
      (node (ref "JP12") (pin "3") (pinfunction "3_3") (pintype "passive"))
      (node (ref "R42") (pin "1") (pinfunction "1_1") (pintype "passive"))
      (node (ref "U14") (pin "5") (pinfunction "SDA_5") (pintype "bidirectional"))
      (node (ref "U17") (pin "20") (pinfunction "SDA_20") (pintype "bidirectional"))
      (node (ref "U18") (pin "20") (pinfunction "SDA_20") (pintype "bidirectional"))
      (node (ref "U19") (pin "20") (pinfunction "SDA_20") (pintype "bidirectional"))
      (node (ref "U22") (pin "19") (pinfunction "SDA_19") (pintype "bidirectional"))
    )
    (net (code "300") (name "USB+") (class "Default")
      (node (ref "R27") (pin "1") (pinfunction "1_1") (pintype "passive"))
      (node (ref "U30") (pin "5") (pinfunction "D-_5") (pintype "bidirectional"))
      (node (ref "U31") (pin "3") (pinfunction "DP0_3") (pintype "bidirectional"))
    )
    (net (code "301") (name "USB-") (class "Default")
      (node (ref "U30") (pin "3") (pinfunction "D+_3") (pintype "bidirectional"))
      (node (ref "U31") (pin "4") (pinfunction "DM0_4") (pintype "bidirectional"))
    )
    (net (code "302") (name "USB_SUSPEND_STATUS") (class "Default")
      (node (ref "JP7") (pin "3") (pinfunction "3_3") (pintype "passive"))
      (node (ref "U31") (pin "1") (pinfunction "SUSPND_1") (pintype "bidirectional"))
    )
    (net (code "303") (name "USB_~{RESET}") (class "Default")
      (node (ref "D2") (pin "2A") (pinfunction "ANODE_2A") (pintype "bidirectional"))
      (node (ref "JP7") (pin "5") (pinfunction "5_5") (pintype "passive"))
      (node (ref "R52") (pin "1") (pinfunction "1_1") (pintype "passive"))
      (node (ref "U19") (pin "9") (pinfunction "P0_9") (pintype "bidirectional"))
      (node (ref "U21") (pin "1") (pinfunction "~{RST}_1") (pintype "bidirectional"))
      (node (ref "U31") (pin "6") (pinfunction "~{RESET}_6") (pintype "bidirectional"))
    )
    (net (code "304") (name "VCC_BACKPLANE") (class "Default")
      (node (ref "C14") (pin "1") (pinfunction "1_1") (pintype "bidirectional"))
      (node (ref "C15") (pin "1") (pinfunction "1_1") (pintype "bidirectional"))
      (node (ref "C18") (pin "1") (pinfunction "1_1") (pintype "bidirectional"))
      (node (ref "C19") (pin "1") (pinfunction "1_1") (pintype "bidirectional"))
      (node (ref "C20") (pin "1") (pinfunction "1_1") (pintype "bidirectional"))
      (node (ref "C21") (pin "1") (pinfunction "1_1") (pintype "bidirectional"))
      (node (ref "C26") (pin "2") (pinfunction "2_2") (pintype "bidirectional"))
      (node (ref "C27") (pin "1") (pinfunction "1_1") (pintype "bidirectional"))
      (node (ref "C28") (pin "1") (pinfunction "1_1") (pintype "bidirectional"))
      (node (ref "C31") (pin "1") (pinfunction "1_1") (pintype "bidirectional"))
      (node (ref "C32") (pin "1") (pinfunction "1_1") (pintype "bidirectional"))
      (node (ref "C35") (pin "2") (pinfunction "2_2") (pintype "bidirectional"))
      (node (ref "C36") (pin "2") (pinfunction "2_2") (pintype "bidirectional"))
      (node (ref "C57") (pin "1") (pinfunction "1_1") (pintype "bidirectional"))
      (node (ref "C58") (pin "1") (pinfunction "1_1") (pintype "bidirectional"))
      (node (ref "C62") (pin "1") (pinfunction "1_1") (pintype "bidirectional"))
      (node (ref "C70") (pin "2") (pinfunction "2_2") (pintype "bidirectional"))
      (node (ref "J8") (pin "6") (pinfunction "VCC_6") (pintype "bidirectional"))
      (node (ref "JP12") (pin "2") (pinfunction "2_2") (pintype "passive"))
      (node (ref "JP16") (pin "3") (pinfunction "3_3") (pintype "passive"))
      (node (ref "R1") (pin "1") (pinfunction "1_1") (pintype "passive"))
      (node (ref "R35") (pin "2") (pinfunction "2_2") (pintype "passive"))
      (node (ref "R36") (pin "2") (pinfunction "2_2") (pintype "passive"))
      (node (ref "R41") (pin "2") (pinfunction "2_2") (pintype "passive"))
      (node (ref "R42") (pin "2") (pinfunction "2_2") (pintype "passive"))
      (node (ref "R43") (pin "2") (pinfunction "2_2") (pintype "passive"))
      (node (ref "R44") (pin "2") (pinfunction "2_2") (pintype "passive"))
      (node (ref "R45") (pin "2") (pinfunction "2_2") (pintype "passive"))
      (node (ref "R46") (pin "2") (pinfunction "2_2") (pintype "passive"))
      (node (ref "R49") (pin "2") (pinfunction "2_2") (pintype "passive"))
      (node (ref "R52") (pin "2") (pinfunction "2_2") (pintype "passive"))
      (node (ref "R61") (pin "A2") (pinfunction "2_A2") (pintype "passive"))
      (node (ref "R61") (pin "D2") (pinfunction "2_D2") (pintype "passive"))
      (node (ref "R62") (pin "C2") (pinfunction "2_C2") (pintype "passive"))
      (node (ref "R63") (pin "B2") (pinfunction "2_B2") (pintype "passive"))
      (node (ref "S10") (pin "3") (pinfunction "I0_3") (pintype "bidirectional"))
      (node (ref "S10") (pin "5") (pinfunction "VCC_5") (pintype "bidirectional"))
      (node (ref "S9") (pin "3") (pinfunction "I0_3") (pintype "bidirectional"))
      (node (ref "S9") (pin "5") (pinfunction "VCC_5") (pintype "bidirectional"))
      (node (ref "SJ1") (pin "1") (pinfunction "1_1") (pintype "passive"))
      (node (ref "SJ4") (pin "2") (pinfunction "2_2") (pintype "passive"))
      (node (ref "TP9") (pin "TESTPOINT") (pinfunction "TESTPOINT_TESTPOINT") (pintype "bidirectional"))
      (node (ref "U14") (pin "1") (pinfunction "E0_1") (pintype "bidirectional"))
      (node (ref "U14") (pin "8") (pinfunction "VCC_8") (pintype "bidirectional"))
      (node (ref "U17") (pin "18") (pinfunction "VCC_18") (pintype "bidirectional"))
      (node (ref "U18") (pin "18") (pinfunction "VCC_18") (pintype "bidirectional"))
      (node (ref "U18") (pin "3") (pinfunction "A0_3") (pintype "bidirectional"))
      (node (ref "U19") (pin "18") (pinfunction "VCC_18") (pintype "bidirectional"))
      (node (ref "U19") (pin "2") (pinfunction "A1_2") (pintype "bidirectional"))
      (node (ref "U19") (pin "3") (pinfunction "A0_3") (pintype "bidirectional"))
      (node (ref "U21") (pin "2") (pinfunction "VCC_2") (pintype "bidirectional"))
      (node (ref "U22") (pin "20") (pinfunction "VCC_20") (pintype "bidirectional"))
      (node (ref "U24") (pin "1") (pinfunction "VCC_A_1") (pintype "bidirectional"))
      (node (ref "U24") (pin "5") (pinfunction "DIR_5") (pintype "bidirectional"))
      (node (ref "U25") (pin "1") (pinfunction "VCC_A_1") (pintype "bidirectional"))
      (node (ref "U25") (pin "5") (pinfunction "DIR_5") (pintype "bidirectional"))
      (node (ref "U26") (pin "1") (pinfunction "VCC_A_1") (pintype "bidirectional"))
      (node (ref "U27") (pin "1") (pinfunction "VCC_A_1") (pintype "bidirectional"))
      (node (ref "U28") (pin "9") (pinfunction "VCC_9") (pintype "bidirectional"))
      (node (ref "U29") (pin "9") (pinfunction "VCC_9") (pintype "bidirectional"))
      (node (ref "U31") (pin "10") (pinfunction "~{BUSPWR}_10") (pintype "bidirectional"))
      (node (ref "U31") (pin "46") (pinfunction "VCC_46") (pintype "bidirectional"))
      (node (ref "U31") (pin "47") (pinfunction "~{EXTMEM}_47") (pintype "bidirectional"))
      (node (ref "U31") (pin "8") (pinfunction "EEDATA/~{GANGED}_8") (pintype "bidirectional"))
      (node (ref "U31") (pin "9") (pinfunction "VCC_9") (pintype "bidirectional"))
      (node (ref "U4") (pin "1") (pinfunction "VCCIO_1") (pintype "power_in"))
      (node (ref "U5") (pin "1") (pinfunction "VCCIO_1") (pintype "power_in"))
      (node (ref "U7") (pin "1") (pinfunction "VCC_A_1") (pintype "bidirectional"))
      (node (ref "U8") (pin "1") (pinfunction "VCC_A_1") (pintype "bidirectional"))
      (node (ref "U9") (pin "6") (pinfunction "SENSE-_6") (pintype "open_collector"))
    )
    (net (code "305") (name "VCC_LINUX") (class "Default")
      (node (ref "C59") (pin "1") (pinfunction "1_1") (pintype "bidirectional"))
      (node (ref "JP12") (pin "4") (pinfunction "4_4") (pintype "passive"))
      (node (ref "JP16") (pin "4") (pinfunction "4_4") (pintype "passive"))
      (node (ref "JP19") (pin "17") (pinfunction "17_17") (pintype "passive"))
      (node (ref "JP20") (pin "17") (pinfunction "17_17") (pintype "passive"))
      (node (ref "R2") (pin "1") (pinfunction "1_1") (pintype "passive"))
      (node (ref "SJ5") (pin "2") (pinfunction "2_2") (pintype "passive"))
      (node (ref "TP11") (pin "TESTPOINT") (pinfunction "TESTPOINT_TESTPOINT") (pintype "bidirectional"))
      (node (ref "U10") (pin "P8") (pinfunction "SENSE-_P8") (pintype "open_collector"))
    )
    (net (code "306") (name "unconnected-(D35-C-Pad2)") (class "Default")
      (node (ref "D35") (pin "2") (pinfunction "C_2") (pintype "bidirectional"))
    )
    (net (code "307") (name "unconnected-(D35-D-Pad4)") (class "Default")
      (node (ref "D35") (pin "4") (pinfunction "D_4") (pintype "bidirectional"))
    )
    (net (code "308") (name "unconnected-(J4-ID-Pad4)") (class "Default")
      (node (ref "J4") (pin "4") (pinfunction "ID_4") (pintype "bidirectional"))
    )
    (net (code "309") (name "unconnected-(J5-+5V-Pad1)") (class "Default")
      (node (ref "J5") (pin "1") (pinfunction "+5V_1") (pintype "bidirectional"))
    )
    (net (code "310") (name "unconnected-(J5-ID-Pad4)") (class "Default")
      (node (ref "J5") (pin "4") (pinfunction "ID_4") (pintype "bidirectional"))
    )
    (net (code "311") (name "unconnected-(J6-Pad2)") (class "Default")
      (node (ref "J6") (pin "2") (pinfunction "2_2") (pintype "passive"))
    )
    (net (code "312") (name "unconnected-(J7-NC-Pad3)") (class "Default")
      (node (ref "J7") (pin "3") (pinfunction "NC_3") (pintype "bidirectional"))
    )
    (net (code "313") (name "unconnected-(JP7-Pad6)") (class "Default")
      (node (ref "JP7") (pin "6") (pinfunction "6_6") (pintype "passive"))
    )
    (net (code "314") (name "unconnected-(Q1-PadD1)") (class "Default")
      (node (ref "Q1") (pin "D1") (pinfunction "D1_D1") (pintype "bidirectional"))
    )
    (net (code "315") (name "unconnected-(Q1-PadG1)") (class "Default")
      (node (ref "Q1") (pin "G1") (pinfunction "G1_G1") (pintype "input"))
    )
    (net (code "316") (name "unconnected-(S11-F-Pad6)") (class "Default")
      (node (ref "S11") (pin "6") (pinfunction "F_6") (pintype "bidirectional"))
    )
    (net (code "317") (name "unconnected-(S19-B-Pad2)") (class "Default")
      (node (ref "S19") (pin "2") (pinfunction "B_2") (pintype "bidirectional"))
    )
    (net (code "318") (name "unconnected-(U1-CBUS0-Pad22)") (class "Default")
      (node (ref "U1") (pin "22") (pinfunction "CBUS0_22") (pintype "bidirectional"))
    )
    (net (code "319") (name "unconnected-(U1-CBUS1-Pad21)") (class "Default")
      (node (ref "U1") (pin "21") (pinfunction "CBUS1_21") (pintype "bidirectional"))
    )
    (net (code "320") (name "unconnected-(U1-CBUS2-Pad10)") (class "Default")
      (node (ref "U1") (pin "10") (pinfunction "CBUS2_10") (pintype "bidirectional"))
    )
    (net (code "321") (name "unconnected-(U1-CBUS3-Pad11)") (class "Default")
      (node (ref "U1") (pin "11") (pinfunction "CBUS3_11") (pintype "bidirectional"))
    )
    (net (code "322") (name "unconnected-(U1-CBUS4-Pad9)") (class "Default")
      (node (ref "U1") (pin "9") (pinfunction "CBUS4_9") (pintype "bidirectional"))
    )
    (net (code "323") (name "unconnected-(U1-OSCI-Pad27)") (class "Default")
      (node (ref "U1") (pin "27") (pinfunction "OSCI_27") (pintype "input"))
    )
    (net (code "324") (name "unconnected-(U1-OSCO-Pad28)") (class "Default")
      (node (ref "U1") (pin "28") (pinfunction "OSCO_28") (pintype "output"))
    )
    (net (code "325") (name "unconnected-(U1-~{CTS}-Pad8)") (class "Default")
      (node (ref "U1") (pin "8") (pinfunction "~{CTS}_8") (pintype "input"))
    )
    (net (code "326") (name "unconnected-(U1-~{DCD}-Pad7)") (class "Default")
      (node (ref "U1") (pin "7") (pinfunction "~{DCD}_7") (pintype "input"))
    )
    (net (code "327") (name "unconnected-(U1-~{DSR}-Pad6)") (class "Default")
      (node (ref "U1") (pin "6") (pinfunction "~{DSR}_6") (pintype "input"))
    )
    (net (code "328") (name "unconnected-(U1-~{DTR}-Pad31)") (class "Default")
      (node (ref "U1") (pin "31") (pinfunction "~{DTR}_31") (pintype "output"))
    )
    (net (code "329") (name "unconnected-(U1-~{RI}-Pad3)") (class "Default")
      (node (ref "U1") (pin "3") (pinfunction "~{RI}_3") (pintype "input"))
    )
    (net (code "330") (name "unconnected-(U1-~{RTS}-Pad32)") (class "Default")
      (node (ref "U1") (pin "32") (pinfunction "~{RTS}_32") (pintype "output"))
    )
    (net (code "331") (name "unconnected-(U2-CBUS0-Pad22)") (class "Default")
      (node (ref "U2") (pin "22") (pinfunction "CBUS0_22") (pintype "bidirectional"))
    )
    (net (code "332") (name "unconnected-(U2-CBUS1-Pad21)") (class "Default")
      (node (ref "U2") (pin "21") (pinfunction "CBUS1_21") (pintype "bidirectional"))
    )
    (net (code "333") (name "unconnected-(U2-CBUS2-Pad10)") (class "Default")
      (node (ref "U2") (pin "10") (pinfunction "CBUS2_10") (pintype "bidirectional"))
    )
    (net (code "334") (name "unconnected-(U2-CBUS3-Pad11)") (class "Default")
      (node (ref "U2") (pin "11") (pinfunction "CBUS3_11") (pintype "bidirectional"))
    )
    (net (code "335") (name "unconnected-(U2-CBUS4-Pad9)") (class "Default")
      (node (ref "U2") (pin "9") (pinfunction "CBUS4_9") (pintype "bidirectional"))
    )
    (net (code "336") (name "unconnected-(U2-OSCI-Pad27)") (class "Default")
      (node (ref "U2") (pin "27") (pinfunction "OSCI_27") (pintype "input"))
    )
    (net (code "337") (name "unconnected-(U2-OSCO-Pad28)") (class "Default")
      (node (ref "U2") (pin "28") (pinfunction "OSCO_28") (pintype "output"))
    )
    (net (code "338") (name "unconnected-(U2-~{CTS}-Pad8)") (class "Default")
      (node (ref "U2") (pin "8") (pinfunction "~{CTS}_8") (pintype "input"))
    )
    (net (code "339") (name "unconnected-(U2-~{DCD}-Pad7)") (class "Default")
      (node (ref "U2") (pin "7") (pinfunction "~{DCD}_7") (pintype "input"))
    )
    (net (code "340") (name "unconnected-(U2-~{DSR}-Pad6)") (class "Default")
      (node (ref "U2") (pin "6") (pinfunction "~{DSR}_6") (pintype "input"))
    )
    (net (code "341") (name "unconnected-(U2-~{DTR}-Pad31)") (class "Default")
      (node (ref "U2") (pin "31") (pinfunction "~{DTR}_31") (pintype "output"))
    )
    (net (code "342") (name "unconnected-(U2-~{RI}-Pad3)") (class "Default")
      (node (ref "U2") (pin "3") (pinfunction "~{RI}_3") (pintype "input"))
    )
    (net (code "343") (name "unconnected-(U2-~{RTS}-Pad32)") (class "Default")
      (node (ref "U2") (pin "32") (pinfunction "~{RTS}_32") (pintype "output"))
    )
    (net (code "344") (name "unconnected-(U3-CBUS0-Pad22)") (class "Default")
      (node (ref "U3") (pin "22") (pinfunction "CBUS0_22") (pintype "bidirectional"))
    )
    (net (code "345") (name "unconnected-(U3-CBUS1-Pad21)") (class "Default")
      (node (ref "U3") (pin "21") (pinfunction "CBUS1_21") (pintype "bidirectional"))
    )
    (net (code "346") (name "unconnected-(U3-CBUS2-Pad10)") (class "Default")
      (node (ref "U3") (pin "10") (pinfunction "CBUS2_10") (pintype "bidirectional"))
    )
    (net (code "347") (name "unconnected-(U3-CBUS3-Pad11)") (class "Default")
      (node (ref "U3") (pin "11") (pinfunction "CBUS3_11") (pintype "bidirectional"))
    )
    (net (code "348") (name "unconnected-(U3-CBUS4-Pad9)") (class "Default")
      (node (ref "U3") (pin "9") (pinfunction "CBUS4_9") (pintype "bidirectional"))
    )
    (net (code "349") (name "unconnected-(U3-OSCI-Pad27)") (class "Default")
      (node (ref "U3") (pin "27") (pinfunction "OSCI_27") (pintype "input"))
    )
    (net (code "350") (name "unconnected-(U3-OSCO-Pad28)") (class "Default")
      (node (ref "U3") (pin "28") (pinfunction "OSCO_28") (pintype "output"))
    )
    (net (code "351") (name "unconnected-(U3-~{CTS}-Pad8)") (class "Default")
      (node (ref "U3") (pin "8") (pinfunction "~{CTS}_8") (pintype "input"))
    )
    (net (code "352") (name "unconnected-(U3-~{DCD}-Pad7)") (class "Default")
      (node (ref "U3") (pin "7") (pinfunction "~{DCD}_7") (pintype "input"))
    )
    (net (code "353") (name "unconnected-(U3-~{DSR}-Pad6)") (class "Default")
      (node (ref "U3") (pin "6") (pinfunction "~{DSR}_6") (pintype "input"))
    )
    (net (code "354") (name "unconnected-(U3-~{DTR}-Pad31)") (class "Default")
      (node (ref "U3") (pin "31") (pinfunction "~{DTR}_31") (pintype "output"))
    )
    (net (code "355") (name "unconnected-(U3-~{RI}-Pad3)") (class "Default")
      (node (ref "U3") (pin "3") (pinfunction "~{RI}_3") (pintype "input"))
    )
    (net (code "356") (name "unconnected-(U3-~{RTS}-Pad32)") (class "Default")
      (node (ref "U3") (pin "32") (pinfunction "~{RTS}_32") (pintype "output"))
    )
    (net (code "357") (name "unconnected-(U4-CBUS0-Pad22)") (class "Default")
      (node (ref "U4") (pin "22") (pinfunction "CBUS0_22") (pintype "bidirectional"))
    )
    (net (code "358") (name "unconnected-(U4-CBUS1-Pad21)") (class "Default")
      (node (ref "U4") (pin "21") (pinfunction "CBUS1_21") (pintype "bidirectional"))
    )
    (net (code "359") (name "unconnected-(U4-CBUS2-Pad10)") (class "Default")
      (node (ref "U4") (pin "10") (pinfunction "CBUS2_10") (pintype "bidirectional"))
    )
    (net (code "360") (name "unconnected-(U4-CBUS3-Pad11)") (class "Default")
      (node (ref "U4") (pin "11") (pinfunction "CBUS3_11") (pintype "bidirectional"))
    )
    (net (code "361") (name "unconnected-(U4-CBUS4-Pad9)") (class "Default")
      (node (ref "U4") (pin "9") (pinfunction "CBUS4_9") (pintype "bidirectional"))
    )
    (net (code "362") (name "unconnected-(U4-OSCI-Pad27)") (class "Default")
      (node (ref "U4") (pin "27") (pinfunction "OSCI_27") (pintype "input"))
    )
    (net (code "363") (name "unconnected-(U4-OSCO-Pad28)") (class "Default")
      (node (ref "U4") (pin "28") (pinfunction "OSCO_28") (pintype "output"))
    )
    (net (code "364") (name "unconnected-(U4-~{CTS}-Pad8)") (class "Default")
      (node (ref "U4") (pin "8") (pinfunction "~{CTS}_8") (pintype "input"))
    )
    (net (code "365") (name "unconnected-(U4-~{DCD}-Pad7)") (class "Default")
      (node (ref "U4") (pin "7") (pinfunction "~{DCD}_7") (pintype "input"))
    )
    (net (code "366") (name "unconnected-(U4-~{DSR}-Pad6)") (class "Default")
      (node (ref "U4") (pin "6") (pinfunction "~{DSR}_6") (pintype "input"))
    )
    (net (code "367") (name "unconnected-(U4-~{DTR}-Pad31)") (class "Default")
      (node (ref "U4") (pin "31") (pinfunction "~{DTR}_31") (pintype "output"))
    )
    (net (code "368") (name "unconnected-(U4-~{RI}-Pad3)") (class "Default")
      (node (ref "U4") (pin "3") (pinfunction "~{RI}_3") (pintype "input"))
    )
    (net (code "369") (name "unconnected-(U4-~{RTS}-Pad32)") (class "Default")
      (node (ref "U4") (pin "32") (pinfunction "~{RTS}_32") (pintype "output"))
    )
    (net (code "370") (name "unconnected-(U5-CBUS0-Pad22)") (class "Default")
      (node (ref "U5") (pin "22") (pinfunction "CBUS0_22") (pintype "bidirectional"))
    )
    (net (code "371") (name "unconnected-(U5-CBUS1-Pad21)") (class "Default")
      (node (ref "U5") (pin "21") (pinfunction "CBUS1_21") (pintype "bidirectional"))
    )
    (net (code "372") (name "unconnected-(U5-CBUS2-Pad10)") (class "Default")
      (node (ref "U5") (pin "10") (pinfunction "CBUS2_10") (pintype "bidirectional"))
    )
    (net (code "373") (name "unconnected-(U5-CBUS3-Pad11)") (class "Default")
      (node (ref "U5") (pin "11") (pinfunction "CBUS3_11") (pintype "bidirectional"))
    )
    (net (code "374") (name "unconnected-(U5-CBUS4-Pad9)") (class "Default")
      (node (ref "U5") (pin "9") (pinfunction "CBUS4_9") (pintype "bidirectional"))
    )
    (net (code "375") (name "unconnected-(U5-OSCI-Pad27)") (class "Default")
      (node (ref "U5") (pin "27") (pinfunction "OSCI_27") (pintype "input"))
    )
    (net (code "376") (name "unconnected-(U5-OSCO-Pad28)") (class "Default")
      (node (ref "U5") (pin "28") (pinfunction "OSCO_28") (pintype "output"))
    )
    (net (code "377") (name "unconnected-(U5-~{CTS}-Pad8)") (class "Default")
      (node (ref "U5") (pin "8") (pinfunction "~{CTS}_8") (pintype "input"))
    )
    (net (code "378") (name "unconnected-(U5-~{DCD}-Pad7)") (class "Default")
      (node (ref "U5") (pin "7") (pinfunction "~{DCD}_7") (pintype "input"))
    )
    (net (code "379") (name "unconnected-(U5-~{DSR}-Pad6)") (class "Default")
      (node (ref "U5") (pin "6") (pinfunction "~{DSR}_6") (pintype "input"))
    )
    (net (code "380") (name "unconnected-(U5-~{DTR}-Pad31)") (class "Default")
      (node (ref "U5") (pin "31") (pinfunction "~{DTR}_31") (pintype "output"))
    )
    (net (code "381") (name "unconnected-(U5-~{RI}-Pad3)") (class "Default")
      (node (ref "U5") (pin "3") (pinfunction "~{RI}_3") (pintype "input"))
    )
    (net (code "382") (name "unconnected-(U5-~{RTS}-Pad32)") (class "Default")
      (node (ref "U5") (pin "32") (pinfunction "~{RTS}_32") (pintype "output"))
    )
    (net (code "383") (name "unconnected-(U6-CBUS0-Pad22)") (class "Default")
      (node (ref "U6") (pin "22") (pinfunction "CBUS0_22") (pintype "bidirectional"))
    )
    (net (code "384") (name "unconnected-(U6-CBUS1-Pad21)") (class "Default")
      (node (ref "U6") (pin "21") (pinfunction "CBUS1_21") (pintype "bidirectional"))
    )
    (net (code "385") (name "unconnected-(U6-CBUS2-Pad10)") (class "Default")
      (node (ref "U6") (pin "10") (pinfunction "CBUS2_10") (pintype "bidirectional"))
    )
    (net (code "386") (name "unconnected-(U6-CBUS3-Pad11)") (class "Default")
      (node (ref "U6") (pin "11") (pinfunction "CBUS3_11") (pintype "bidirectional"))
    )
    (net (code "387") (name "unconnected-(U6-CBUS4-Pad9)") (class "Default")
      (node (ref "U6") (pin "9") (pinfunction "CBUS4_9") (pintype "bidirectional"))
    )
    (net (code "388") (name "unconnected-(U6-OSCI-Pad27)") (class "Default")
      (node (ref "U6") (pin "27") (pinfunction "OSCI_27") (pintype "input"))
    )
    (net (code "389") (name "unconnected-(U6-OSCO-Pad28)") (class "Default")
      (node (ref "U6") (pin "28") (pinfunction "OSCO_28") (pintype "output"))
    )
    (net (code "390") (name "unconnected-(U6-~{CTS}-Pad8)") (class "Default")
      (node (ref "U6") (pin "8") (pinfunction "~{CTS}_8") (pintype "input"))
    )
    (net (code "391") (name "unconnected-(U6-~{DCD}-Pad7)") (class "Default")
      (node (ref "U6") (pin "7") (pinfunction "~{DCD}_7") (pintype "input"))
    )
    (net (code "392") (name "unconnected-(U6-~{DSR}-Pad6)") (class "Default")
      (node (ref "U6") (pin "6") (pinfunction "~{DSR}_6") (pintype "input"))
    )
    (net (code "393") (name "unconnected-(U6-~{DTR}-Pad31)") (class "Default")
      (node (ref "U6") (pin "31") (pinfunction "~{DTR}_31") (pintype "output"))
    )
    (net (code "394") (name "unconnected-(U6-~{RI}-Pad3)") (class "Default")
      (node (ref "U6") (pin "3") (pinfunction "~{RI}_3") (pintype "input"))
    )
    (net (code "395") (name "unconnected-(U6-~{RTS}-Pad32)") (class "Default")
      (node (ref "U6") (pin "32") (pinfunction "~{RTS}_32") (pintype "output"))
    )
    (net (code "396") (name "unconnected-(U17-INT-Pad7)") (class "Default")
      (node (ref "U17") (pin "7") (pinfunction "INT_7") (pintype "bidirectional"))
    )
    (net (code "397") (name "unconnected-(U17-P3-Pad12)") (class "Default")
      (node (ref "U17") (pin "12") (pinfunction "P3_12") (pintype "bidirectional"))
    )
    (net (code "398") (name "unconnected-(U17-P4-Pad13)") (class "Default")
      (node (ref "U17") (pin "13") (pinfunction "P4_13") (pintype "bidirectional"))
    )
    (net (code "399") (name "unconnected-(U17-P5-Pad14)") (class "Default")
      (node (ref "U17") (pin "14") (pinfunction "P5_14") (pintype "bidirectional"))
    )
    (net (code "400") (name "unconnected-(U17-P6-Pad15)") (class "Default")
      (node (ref "U17") (pin "15") (pinfunction "P6_15") (pintype "bidirectional"))
    )
    (net (code "401") (name "unconnected-(U17-P7-Pad16)") (class "Default")
      (node (ref "U17") (pin "16") (pinfunction "P7_16") (pintype "bidirectional"))
    )
    (net (code "402") (name "unconnected-(U18-INT-Pad7)") (class "Default")
      (node (ref "U18") (pin "7") (pinfunction "INT_7") (pintype "bidirectional"))
    )
    (net (code "403") (name "unconnected-(U18-P3-Pad12)") (class "Default")
      (node (ref "U18") (pin "12") (pinfunction "P3_12") (pintype "bidirectional"))
    )
    (net (code "404") (name "unconnected-(U18-P4-Pad13)") (class "Default")
      (node (ref "U18") (pin "13") (pinfunction "P4_13") (pintype "bidirectional"))
    )
    (net (code "405") (name "unconnected-(U18-P5-Pad14)") (class "Default")
      (node (ref "U18") (pin "14") (pinfunction "P5_14") (pintype "bidirectional"))
    )
    (net (code "406") (name "unconnected-(U18-P6-Pad15)") (class "Default")
      (node (ref "U18") (pin "15") (pinfunction "P6_15") (pintype "bidirectional"))
    )
    (net (code "407") (name "unconnected-(U18-P7-Pad16)") (class "Default")
      (node (ref "U18") (pin "16") (pinfunction "P7_16") (pintype "bidirectional"))
    )
    (net (code "408") (name "unconnected-(U19-INT-Pad7)") (class "Default")
      (node (ref "U19") (pin "7") (pinfunction "INT_7") (pintype "bidirectional"))
    )
    (net (code "409") (name "unconnected-(U19-P4-Pad13)") (class "Default")
      (node (ref "U19") (pin "13") (pinfunction "P4_13") (pintype "bidirectional"))
    )
    (net (code "410") (name "unconnected-(U19-P5-Pad14)") (class "Default")
      (node (ref "U19") (pin "14") (pinfunction "P5_14") (pintype "bidirectional"))
    )
    (net (code "411") (name "unconnected-(U19-P6-Pad15)") (class "Default")
      (node (ref "U19") (pin "15") (pinfunction "P6_15") (pintype "bidirectional"))
    )
    (net (code "412") (name "unconnected-(U19-P7-Pad16)") (class "Default")
      (node (ref "U19") (pin "16") (pinfunction "P7_16") (pintype "bidirectional"))
    )
    (net (code "413") (name "unconnected-(U23-ADVREFP-Pad18)") (class "Default")
      (node (ref "U23") (pin "18") (pinfunction "ADVREFP_18") (pintype "bidirectional"))
    )
    (net (code "414") (name "unconnected-(U23-PA04-Pad11)") (class "Default")
      (node (ref "U23") (pin "11") (pinfunction "PA04_11") (pintype "bidirectional"))
    )
    (net (code "415") (name "unconnected-(U23-PA05-Pad12)") (class "Default")
      (node (ref "U23") (pin "12") (pinfunction "PA05_12") (pintype "bidirectional"))
    )
    (net (code "416") (name "unconnected-(U23-PA06-Pad15)") (class "Default")
      (node (ref "U23") (pin "15") (pinfunction "PA06_15") (pintype "bidirectional"))
    )
    (net (code "417") (name "unconnected-(U23-PA07-Pad16)") (class "Default")
      (node (ref "U23") (pin "16") (pinfunction "PA07_16") (pintype "bidirectional"))
    )
    (net (code "418") (name "unconnected-(U23-PA08-Pad20)") (class "Default")
      (node (ref "U23") (pin "20") (pinfunction "PA08_20") (pintype "bidirectional"))
    )
    (net (code "419") (name "unconnected-(U23-PA09-Pad21)") (class "Default")
      (node (ref "U23") (pin "21") (pinfunction "PA09_21") (pintype "bidirectional"))
    )
    (net (code "420") (name "unconnected-(U23-PA10-Pad22)") (class "Default")
      (node (ref "U23") (pin "22") (pinfunction "PA10_22") (pintype "bidirectional"))
    )
    (net (code "421") (name "unconnected-(U23-PA13-Pad32)") (class "Default")
      (node (ref "U23") (pin "32") (pinfunction "PA13_32") (pintype "bidirectional"))
    )
    (net (code "422") (name "unconnected-(U23-PA14-Pad33)") (class "Default")
      (node (ref "U23") (pin "33") (pinfunction "PA14_33") (pintype "bidirectional"))
    )
    (net (code "423") (name "unconnected-(U23-PA17-Pad36)") (class "Default")
      (node (ref "U23") (pin "36") (pinfunction "PA17_36") (pintype "bidirectional"))
    )
    (net (code "424") (name "unconnected-(U23-XIN32-Pad13)") (class "Default")
      (node (ref "U23") (pin "13") (pinfunction "XIN32_13") (pintype "bidirectional"))
    )
    (net (code "425") (name "unconnected-(U23-XOUT32-Pad14)") (class "Default")
      (node (ref "U23") (pin "14") (pinfunction "XOUT32_14") (pintype "bidirectional"))
    )
    (net (code "426") (name "unconnected-(U26-A2-Pad3)") (class "Default")
      (node (ref "U26") (pin "3") (pinfunction "A2_3") (pintype "bidirectional"))
    )
    (net (code "427") (name "unconnected-(U26-B2-Pad6)") (class "Default")
      (node (ref "U26") (pin "6") (pinfunction "B2_6") (pintype "bidirectional"))
    )
    (net (code "428") (name "unconnected-(U27-A2-Pad3)") (class "Default")
      (node (ref "U27") (pin "3") (pinfunction "A2_3") (pintype "bidirectional"))
    )
    (net (code "429") (name "unconnected-(U27-B2-Pad6)") (class "Default")
      (node (ref "U27") (pin "6") (pinfunction "B2_6") (pintype "bidirectional"))
    )
    (net (code "430") (name "unconnected-(U31-EECLK-Pad7)") (class "Default")
      (node (ref "U31") (pin "7") (pinfunction "EECLK_7") (pintype "bidirectional"))
    )
    (net (code "431") (name "unconnected-(U32-EECLK-Pad7)") (class "Default")
      (node (ref "U32") (pin "7") (pinfunction "EECLK_7") (pintype "bidirectional"))
    )
    (net (code "432") (name "unconnected-(U32-SUSPND-Pad1)") (class "Default")
      (node (ref "U32") (pin "1") (pinfunction "SUSPND_1") (pintype "bidirectional"))
    )
    (net (code "433") (name "unconnected-(U32-~{PWRON2}-Pad15)") (class "Default")
      (node (ref "U32") (pin "15") (pinfunction "~{PWRON2}_15") (pintype "bidirectional"))
    )
    (net (code "434") (name "unconnected-(U32-~{PWRON3}-Pad19)") (class "Default")
      (node (ref "U32") (pin "19") (pinfunction "~{PWRON3}_19") (pintype "bidirectional"))
    )
    (net (code "435") (name "unconnected-(U32-~{PWRON4}-Pad23)") (class "Default")
      (node (ref "U32") (pin "23") (pinfunction "~{PWRON4}_23") (pintype "bidirectional"))
    )
    (net (code "436") (name "unconnected-(U32-~{PWRON5}-Pad28)") (class "Default")
      (node (ref "U32") (pin "28") (pinfunction "~{PWRON5}_28") (pintype "bidirectional"))
    )
    (net (code "437") (name "unconnected-(U32-~{PWRON6}-Pad32)") (class "Default")
      (node (ref "U32") (pin "32") (pinfunction "~{PWRON6}_32") (pintype "bidirectional"))
    )
    (net (code "438") (name "unconnected-(U32-~{PWRON7}-Pad36)") (class "Default")
      (node (ref "U32") (pin "36") (pinfunction "~{PWRON7}_36") (pintype "bidirectional"))
    )
    (net (code "439") (name "~{BACKPLANE_RESET}") (class "Default")
      (node (ref "D3") (pin "1A") (pinfunction "ANODE_1A") (pintype "bidirectional"))
      (node (ref "D3") (pin "4A") (pinfunction "ANODE_4A") (pintype "bidirectional"))
      (node (ref "J1") (pin "22") (pinfunction "~{BACKPLANE_RESET}_22") (pintype "bidirectional"))
      (node (ref "JP14") (pin "2") (pinfunction "2_2") (pintype "passive"))
      (node (ref "R41") (pin "1") (pinfunction "1_1") (pintype "passive"))
      (node (ref "U17") (pin "4") (pinfunction "~{RESET}_4") (pintype "bidirectional"))
      (node (ref "U18") (pin "4") (pinfunction "~{RESET}_4") (pintype "bidirectional"))
      (node (ref "U19") (pin "4") (pinfunction "~{RESET}_4") (pintype "bidirectional"))
    )
    (net (code "440") (name "~{POWER_ON_RESET}") (class "Default")
      (node (ref "D2") (pin "4A") (pinfunction "ANODE_4A") (pintype "bidirectional"))
      (node (ref "R51") (pin "1") (pinfunction "1_1") (pintype "passive"))
      (node (ref "U20") (pin "1") (pinfunction "~{RST}_1") (pintype "bidirectional"))
      (node (ref "U32") (pin "6") (pinfunction "~{RESET}_6") (pintype "bidirectional"))
    )
    (net (code "441") (name "~{SMBALERT}") (class "Default")
      (node (ref "J1") (pin "6") (pinfunction "~{SMBALERT}_6") (pintype "bidirectional"))
      (node (ref "JP11") (pin "10") (pinfunction "10_10") (pintype "passive"))
      (node (ref "JP12") (pin "6") (pinfunction "6_6") (pintype "passive"))
      (node (ref "R44") (pin "1") (pinfunction "1_1") (pintype "passive"))
      (node (ref "U22") (pin "17") (pinfunction "~{INT}_17") (pintype "bidirectional"))
    )
    (net (code "442") (name "~{WATCHDOG}") (class "Default")
      (node (ref "J1") (pin "7") (pinfunction "~{WATCHDOG}_7") (pintype "bidirectional"))
      (node (ref "JP12") (pin "7") (pinfunction "7_7") (pintype "passive"))
      (node (ref "U15") (pin "6") (pinfunction "WDI_6") (pintype "bidirectional"))
    )
  )
)
